# main.net
KiCad netlist of a schematic drawn in EAGLE
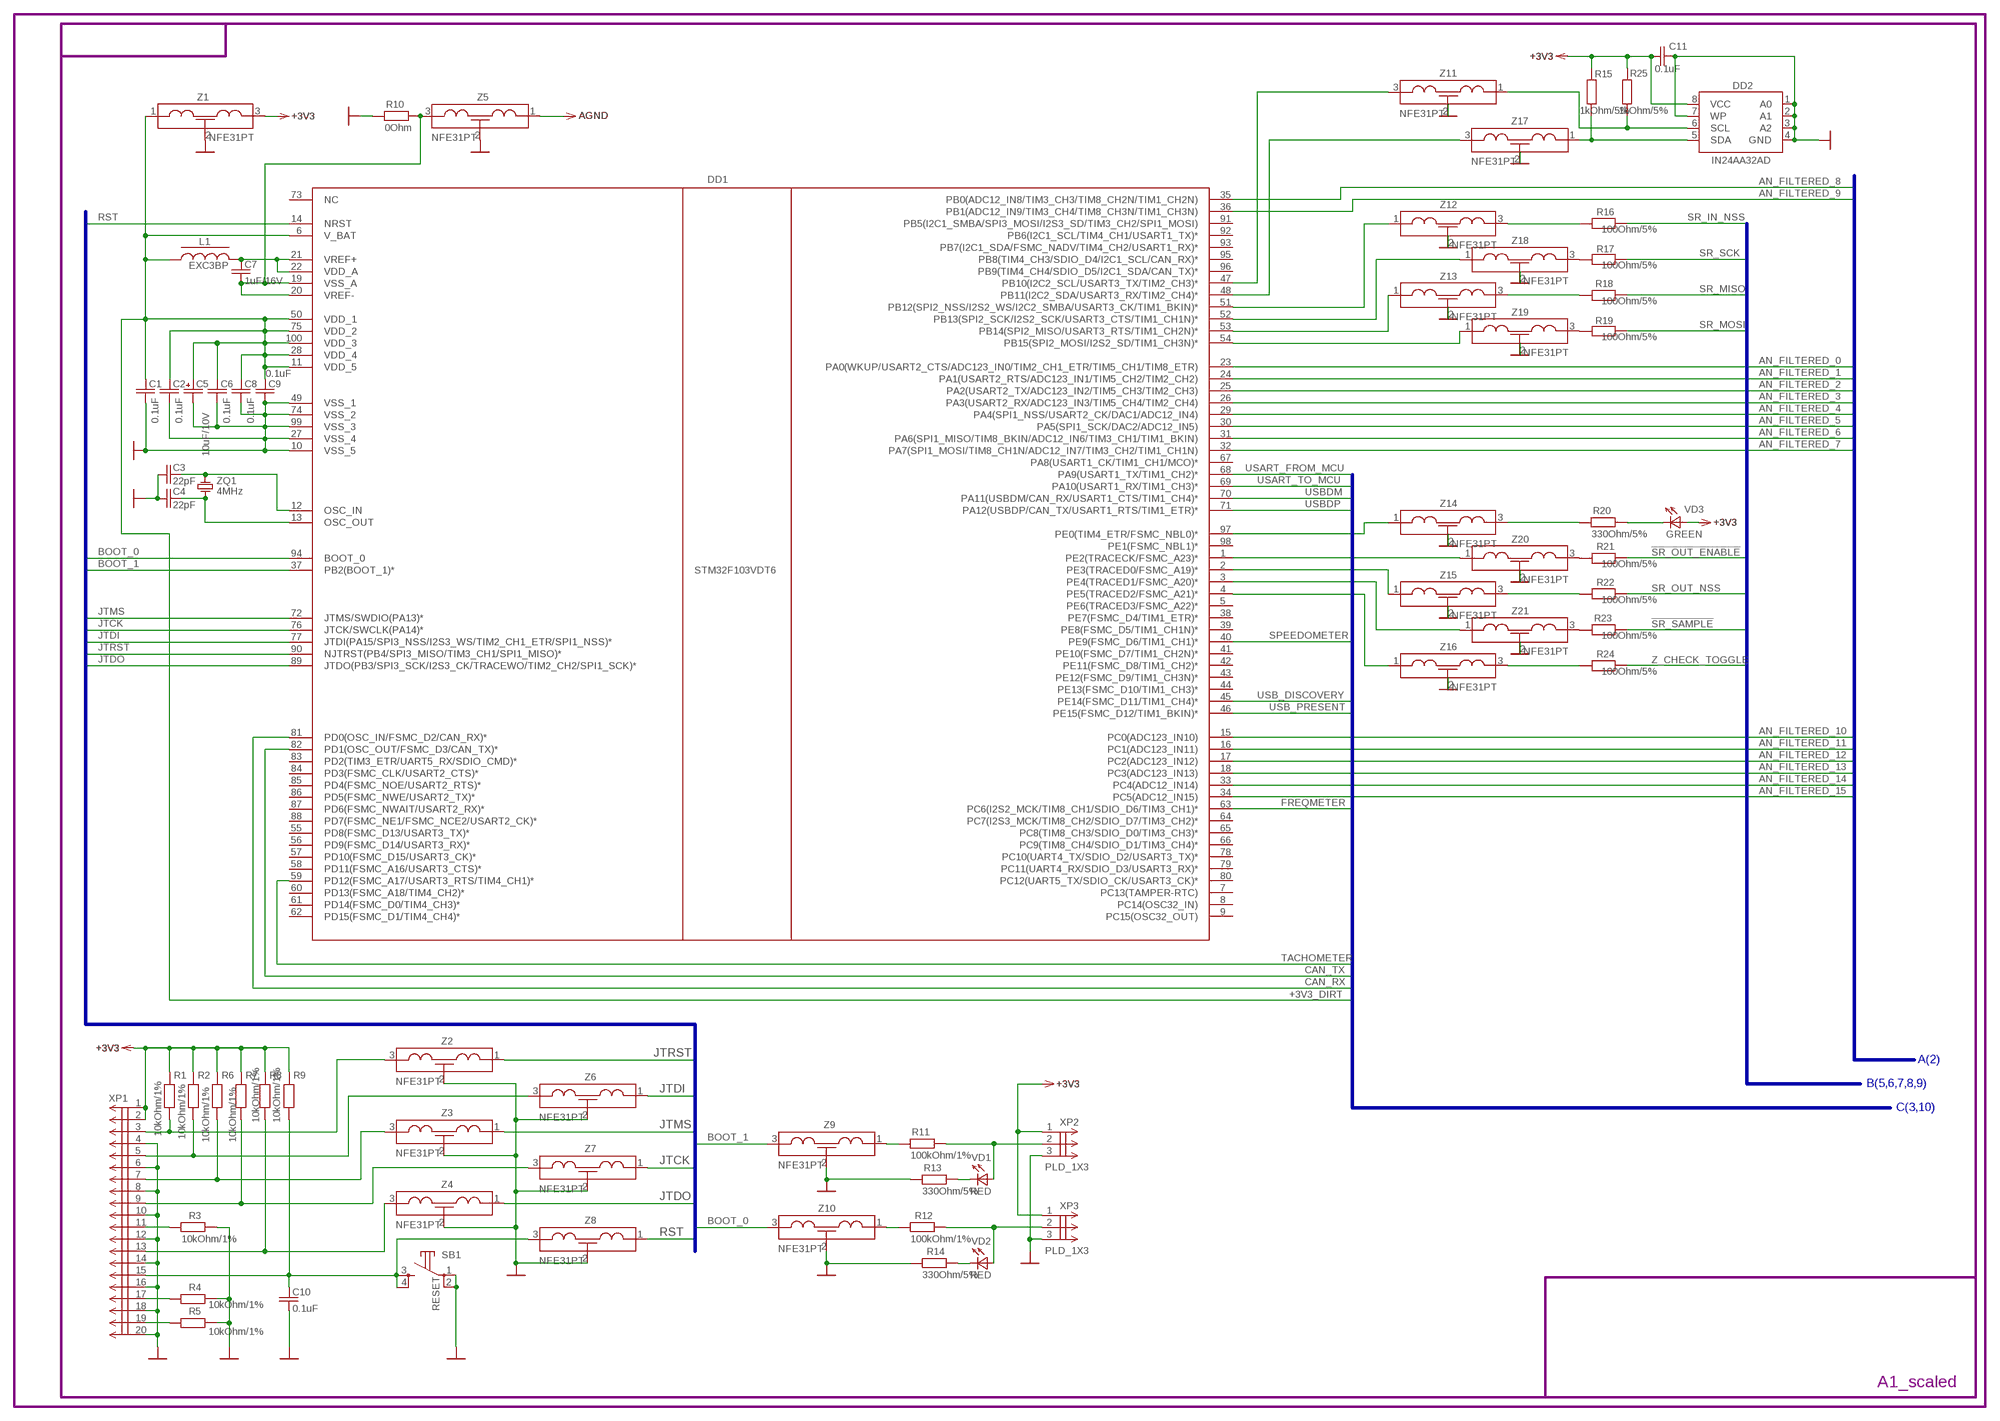
[diagram p0: schematic, sheet 1]
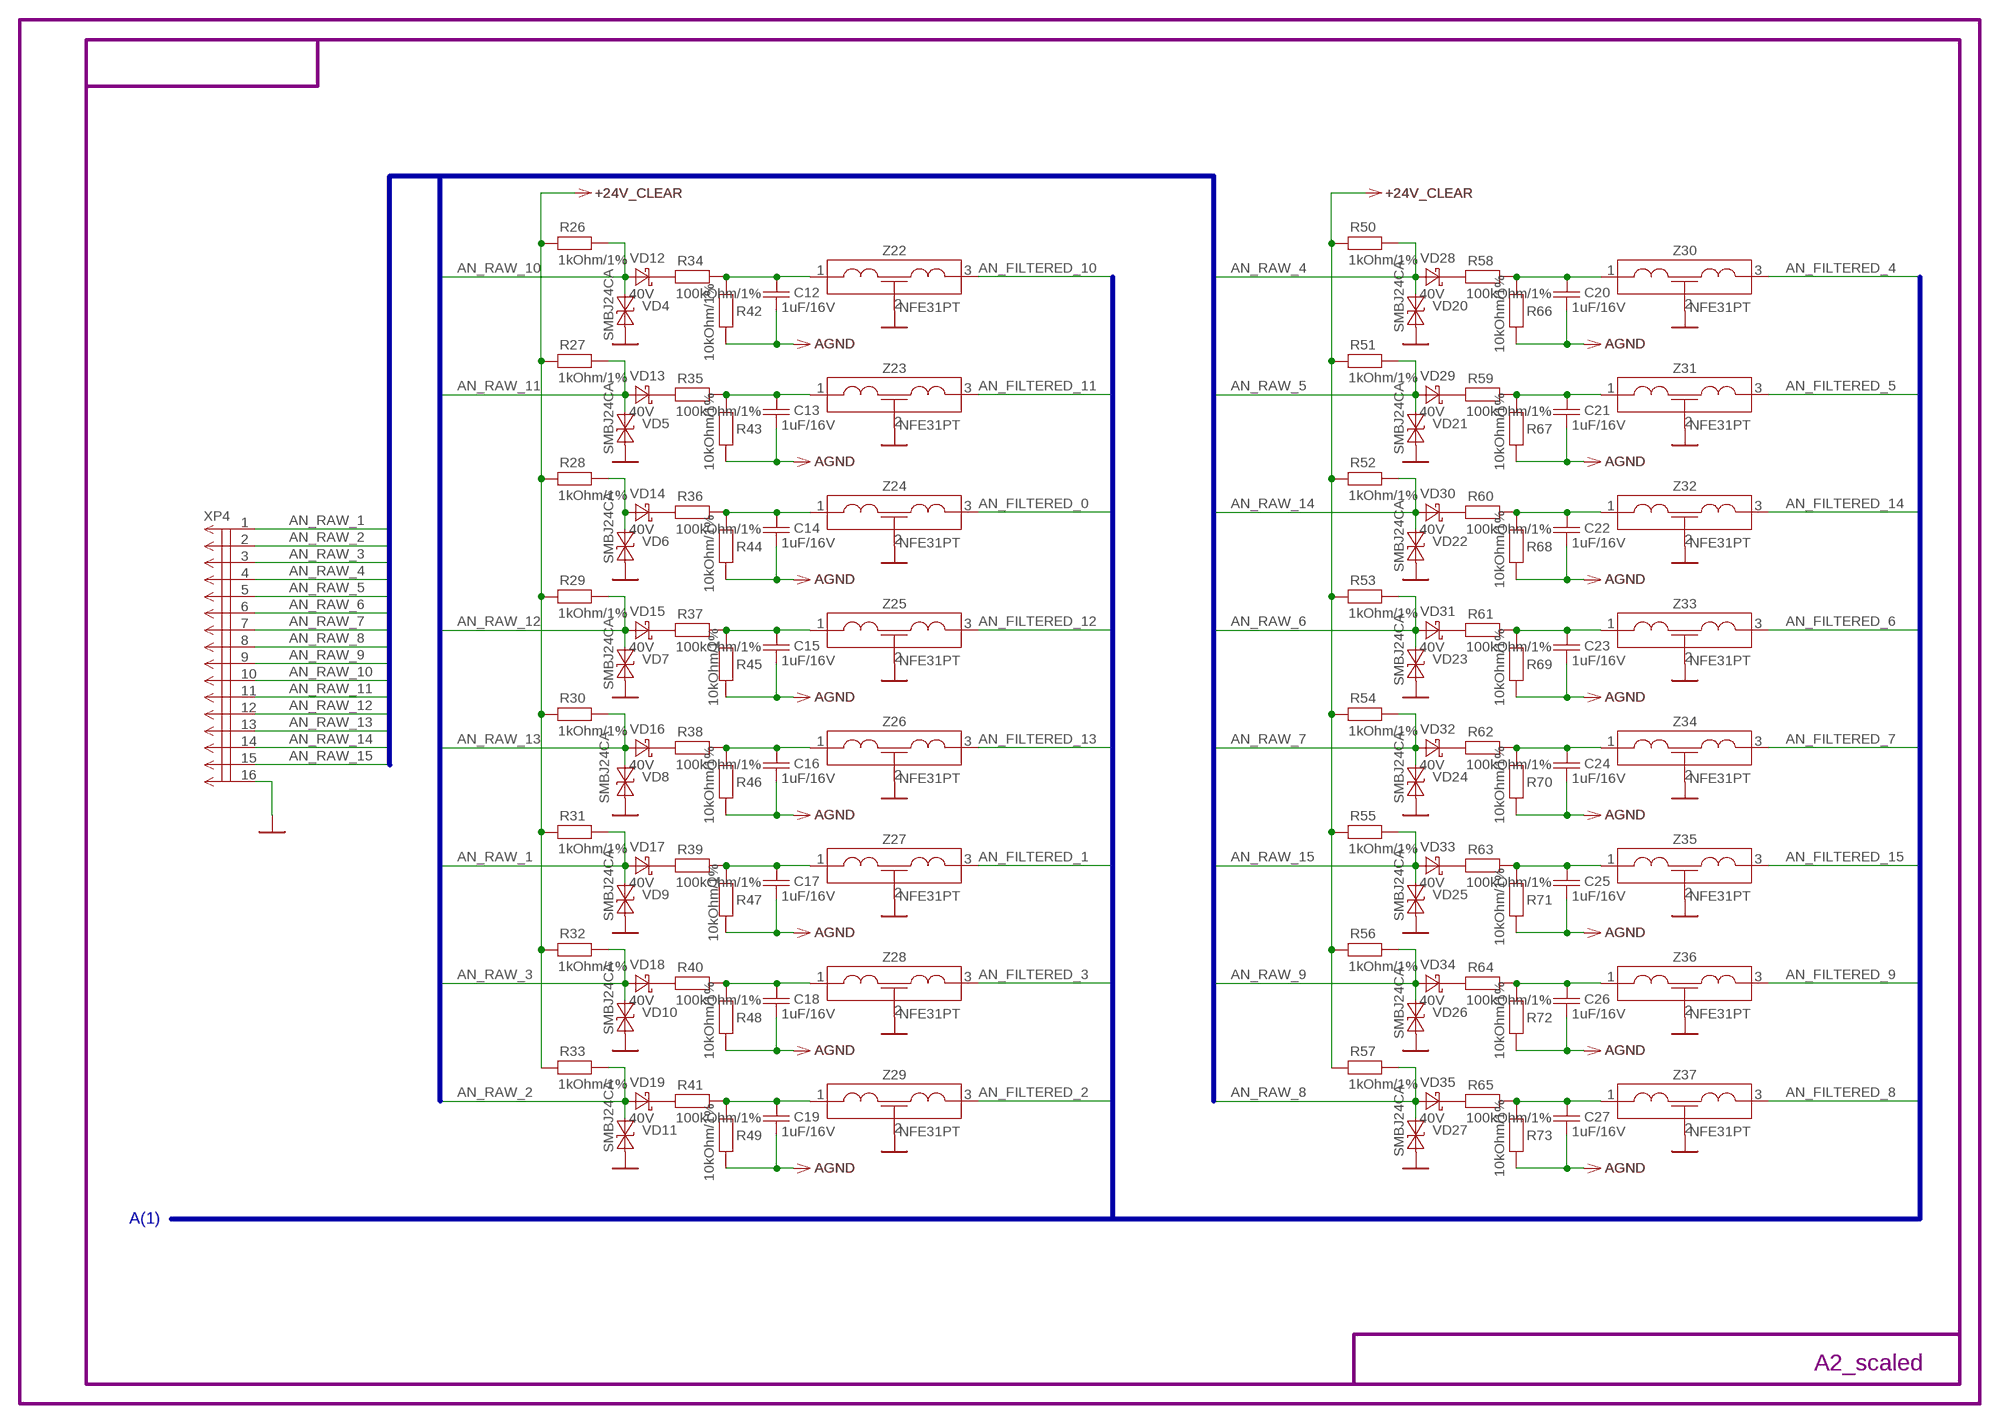
[diagram p1: schematic, sheet 2]
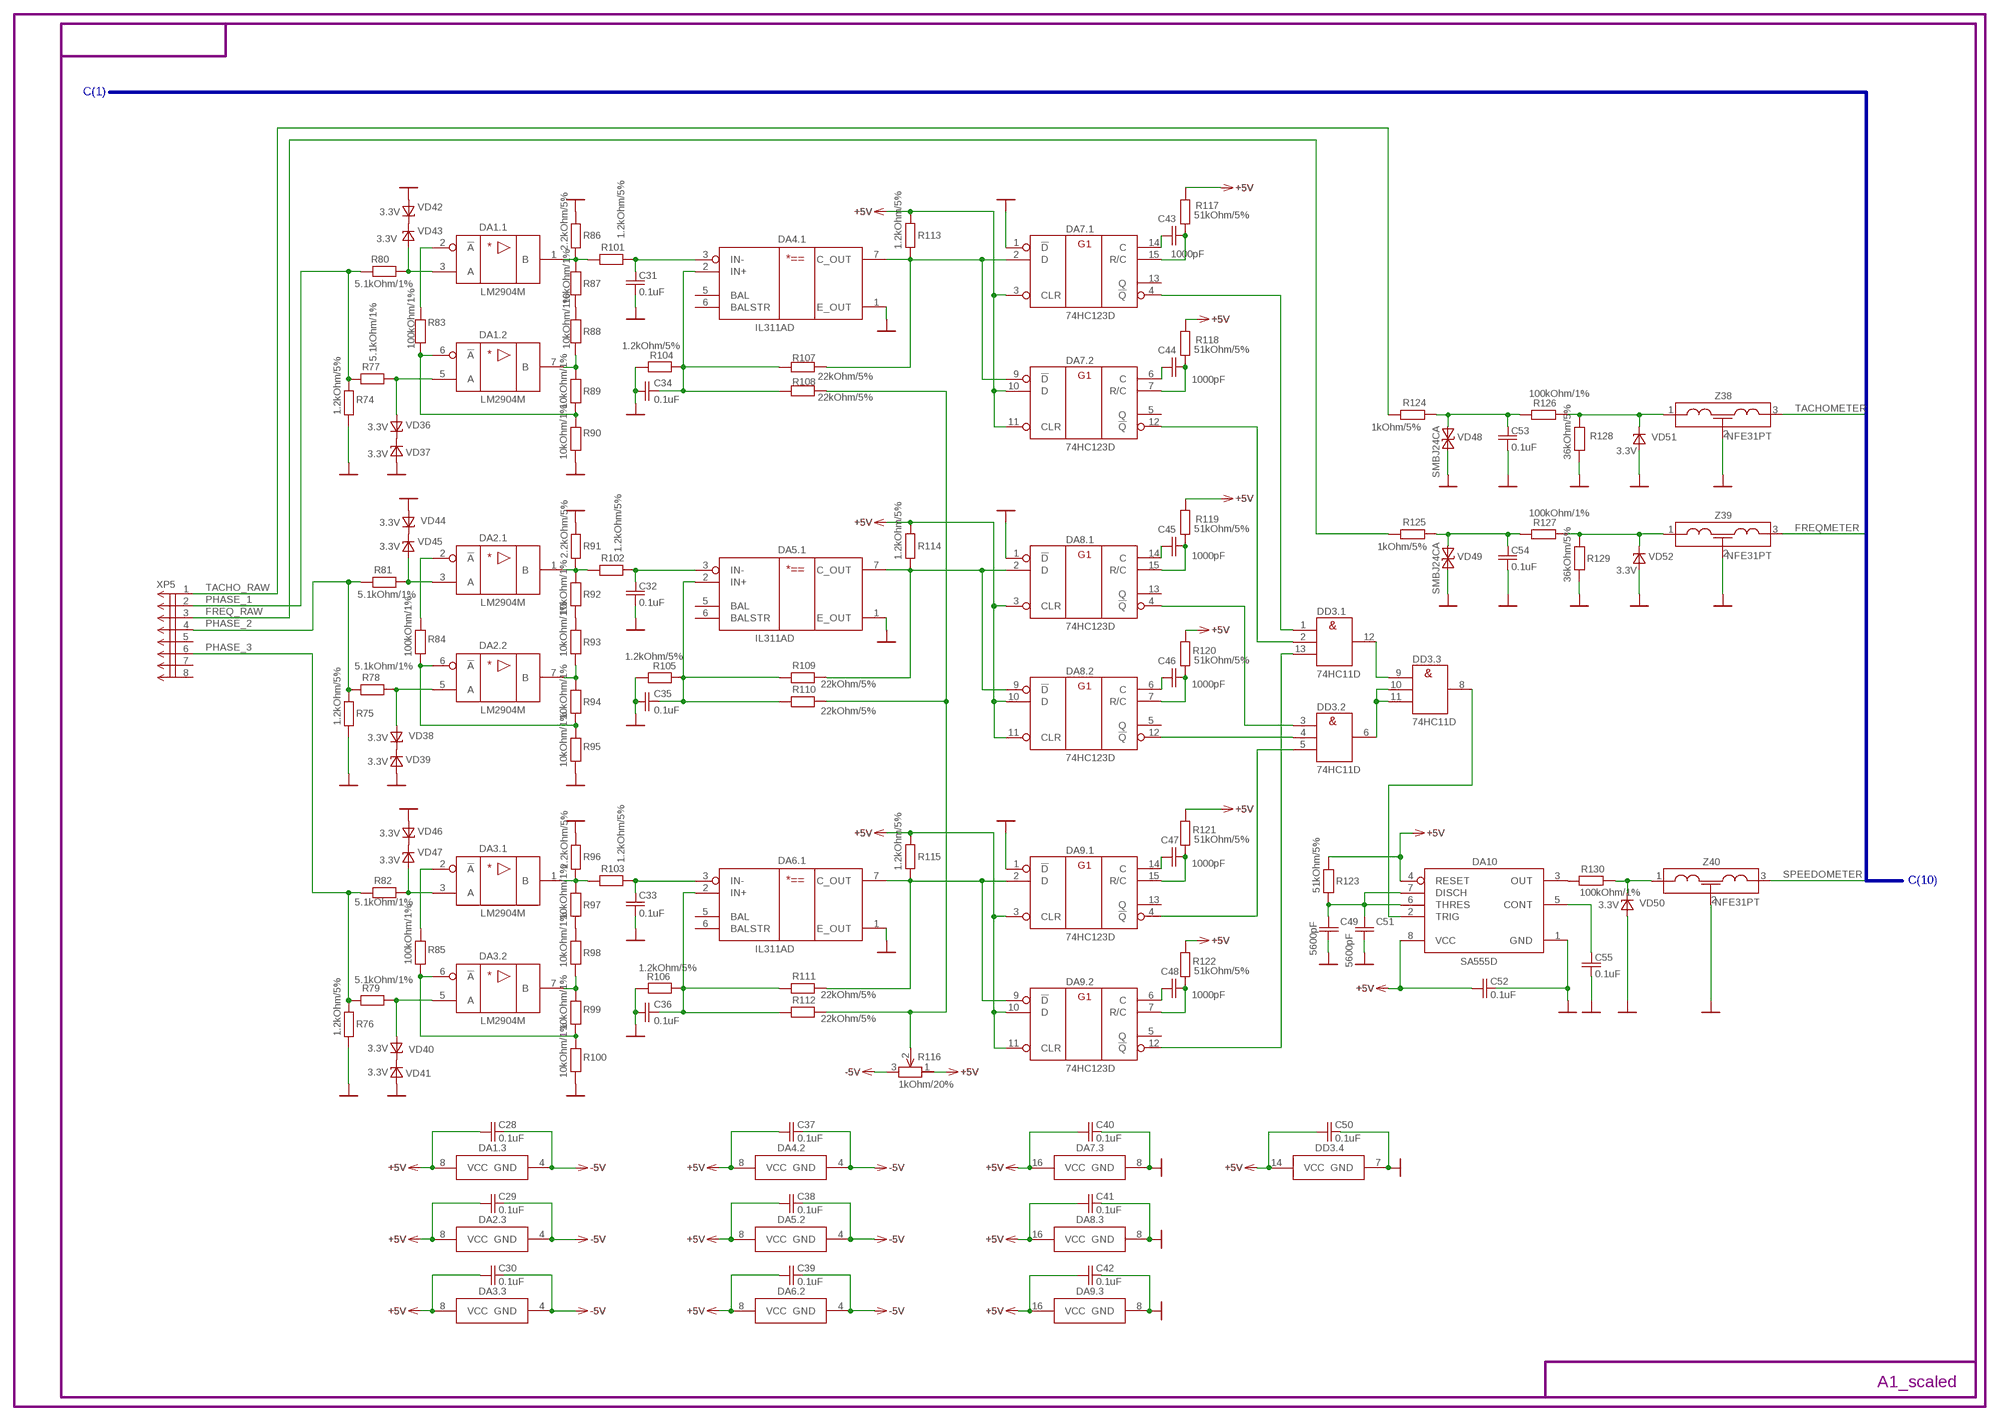
[diagram p2: schematic, sheet 3]
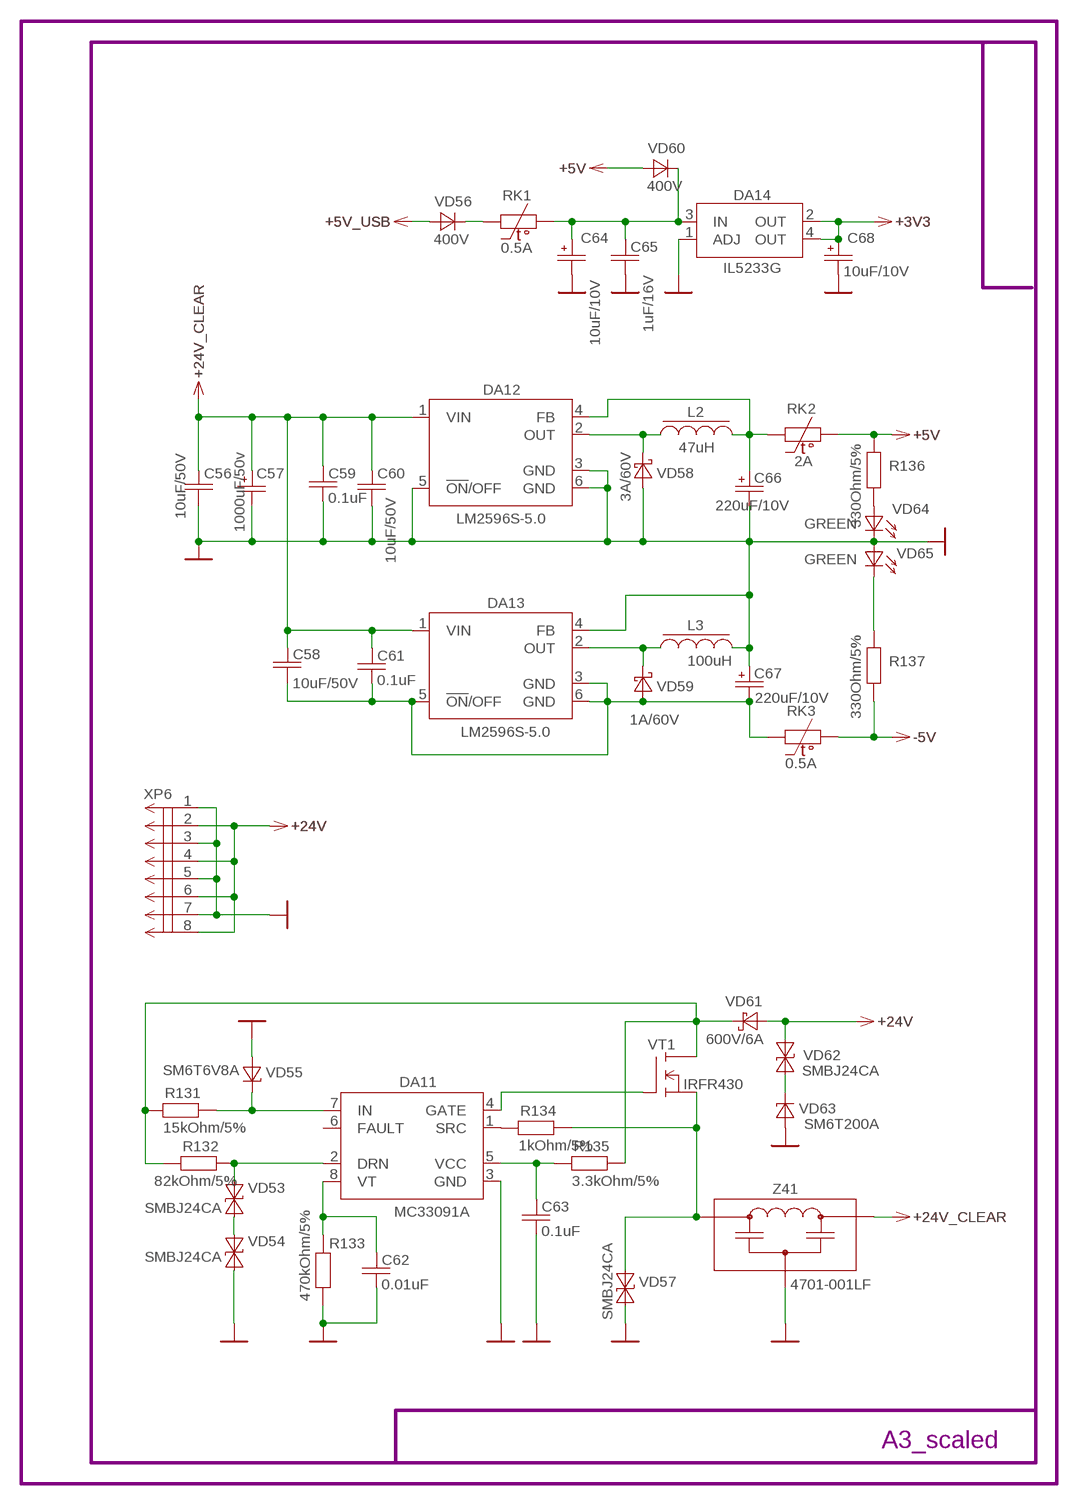
[diagram p3: schematic, sheet 4]
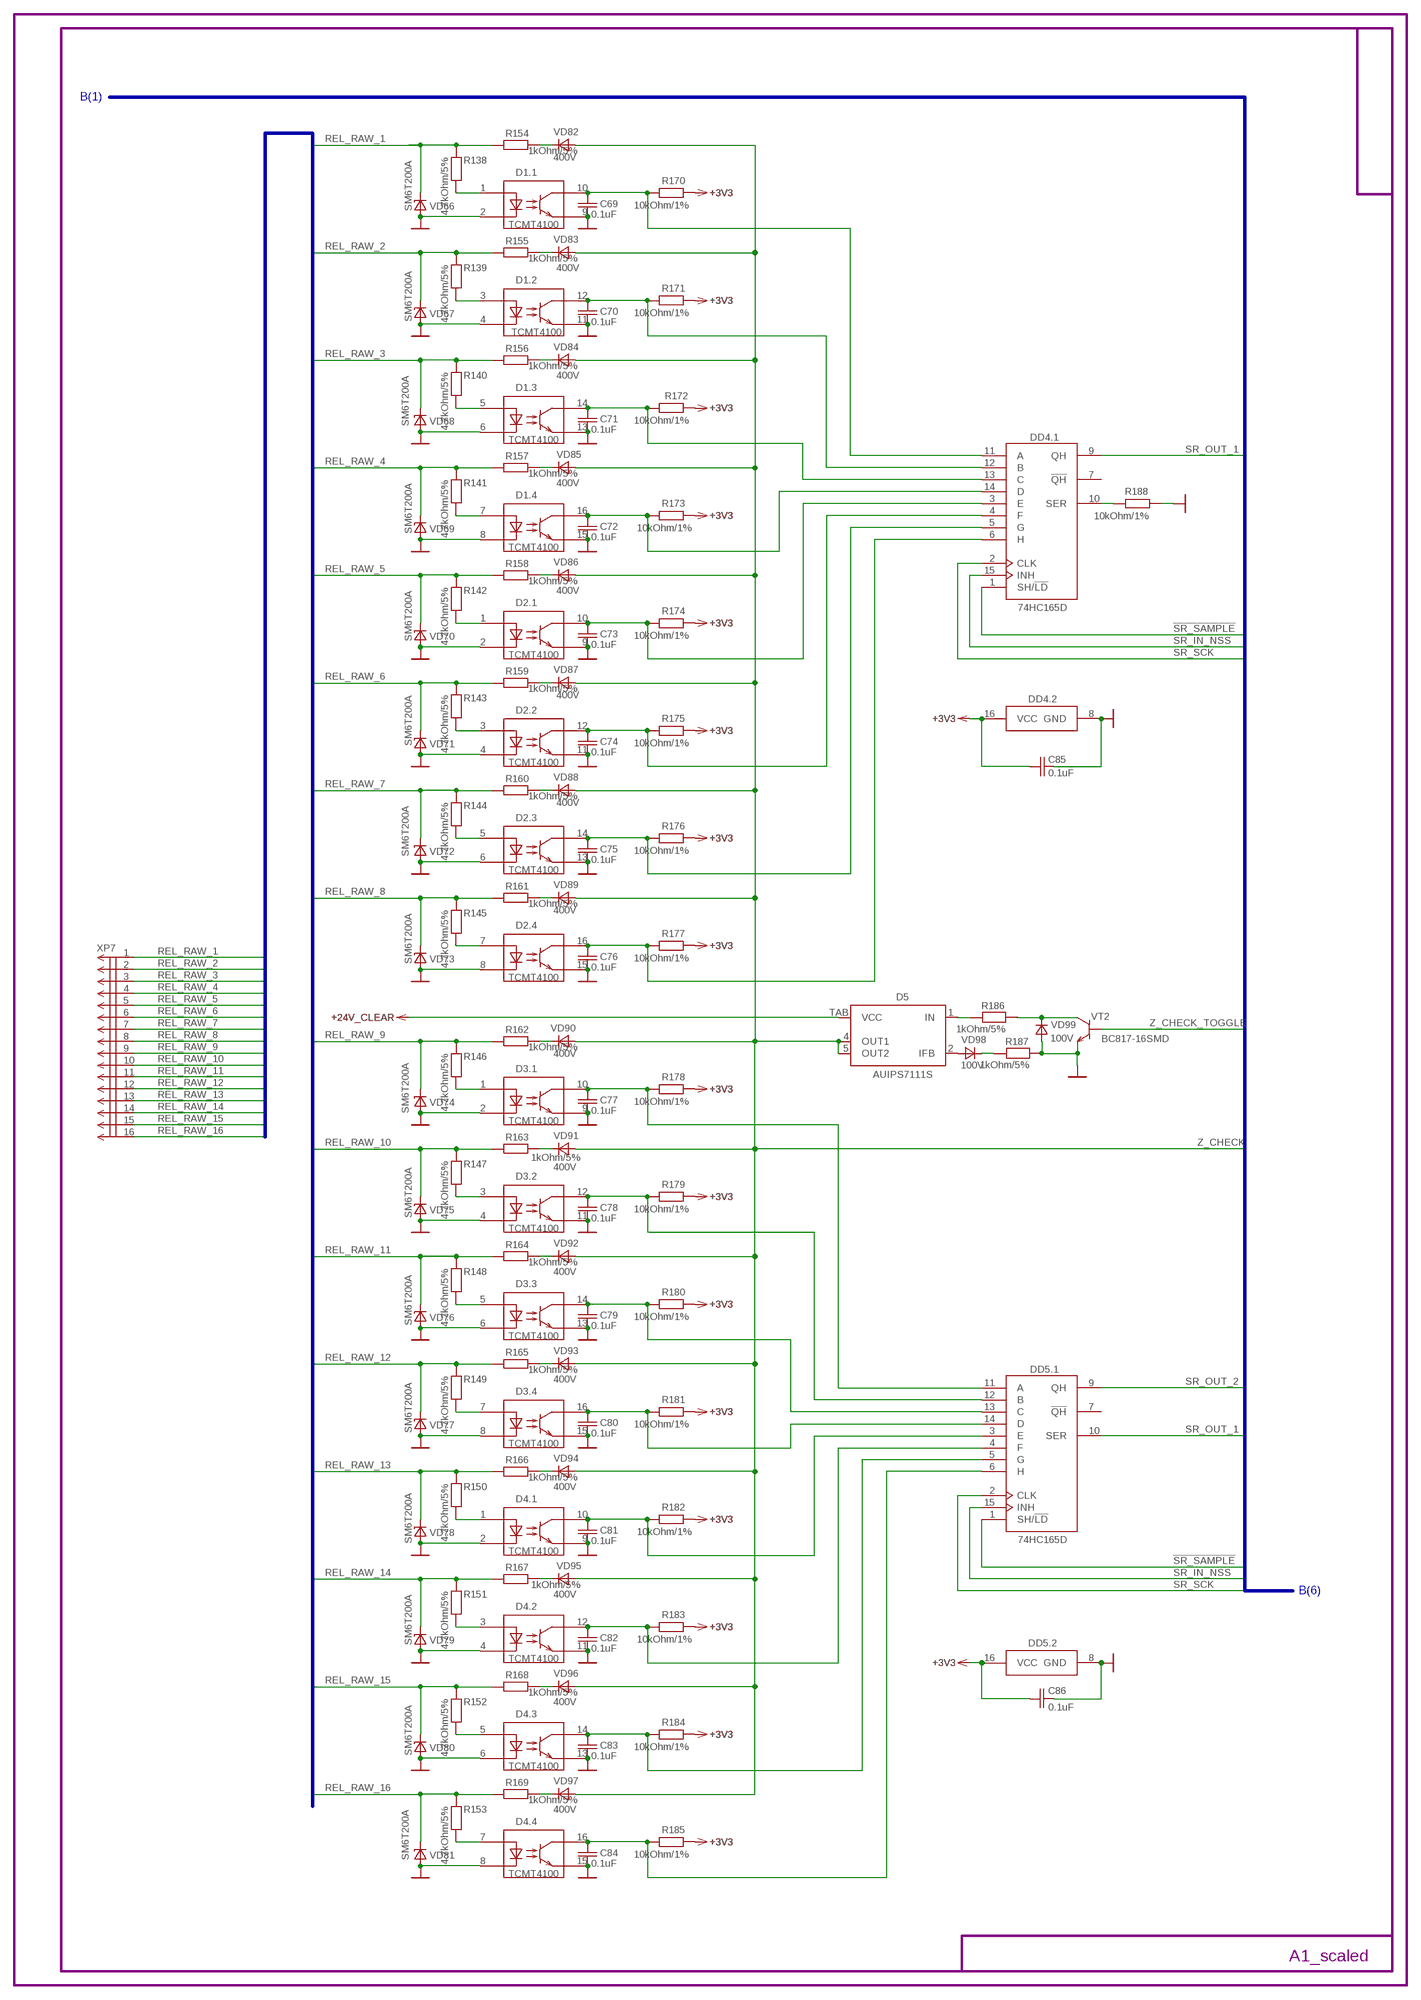
[diagram p4: schematic, sheet 5]
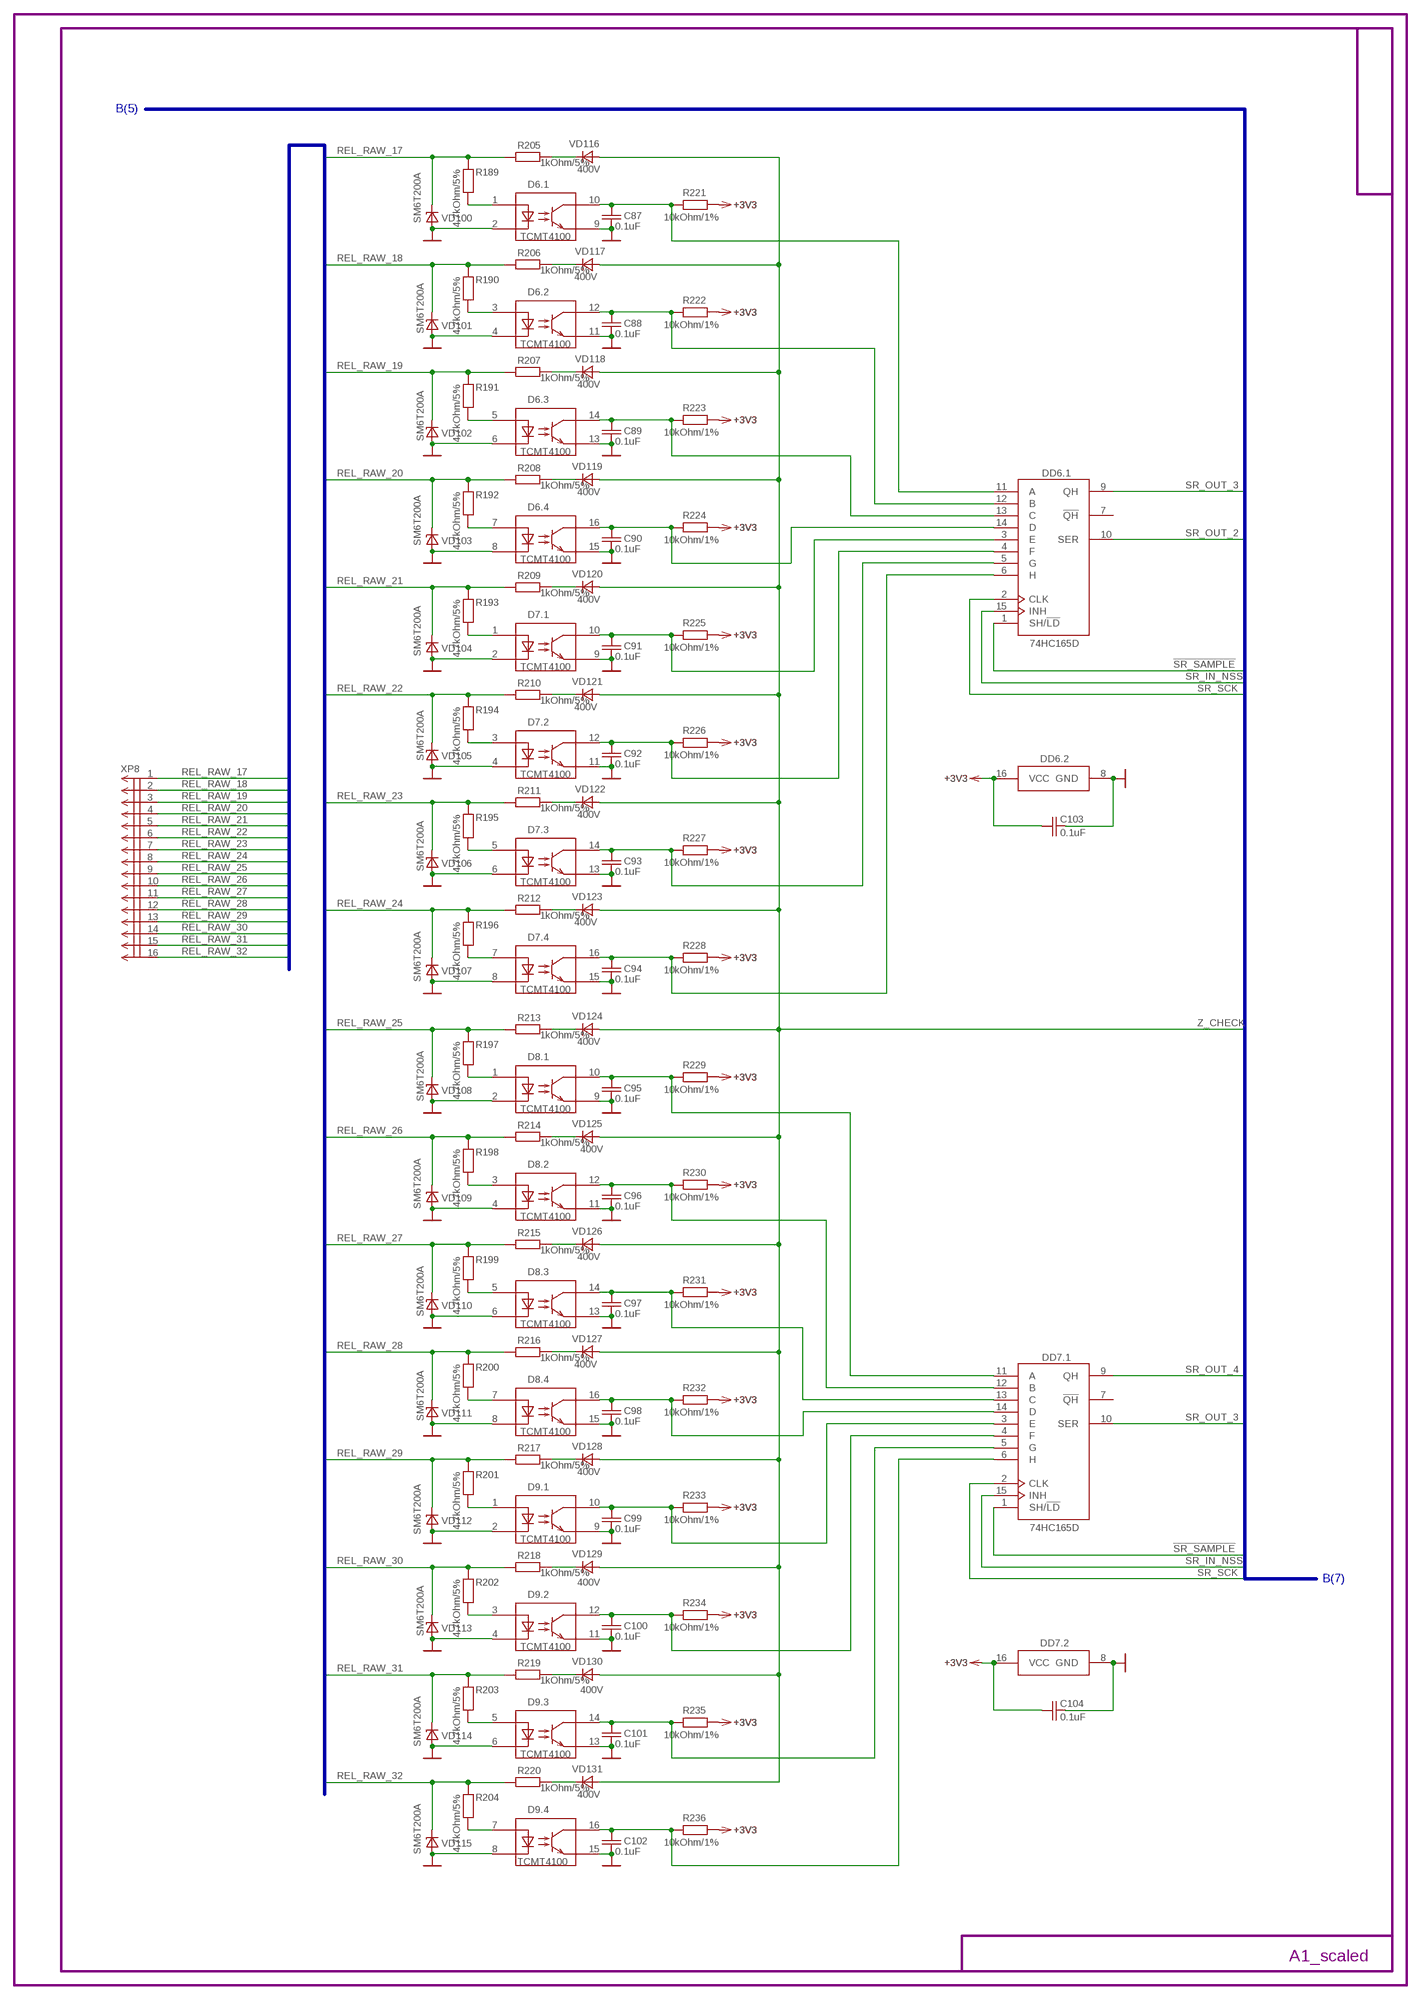
[diagram p5: schematic, sheet 6]
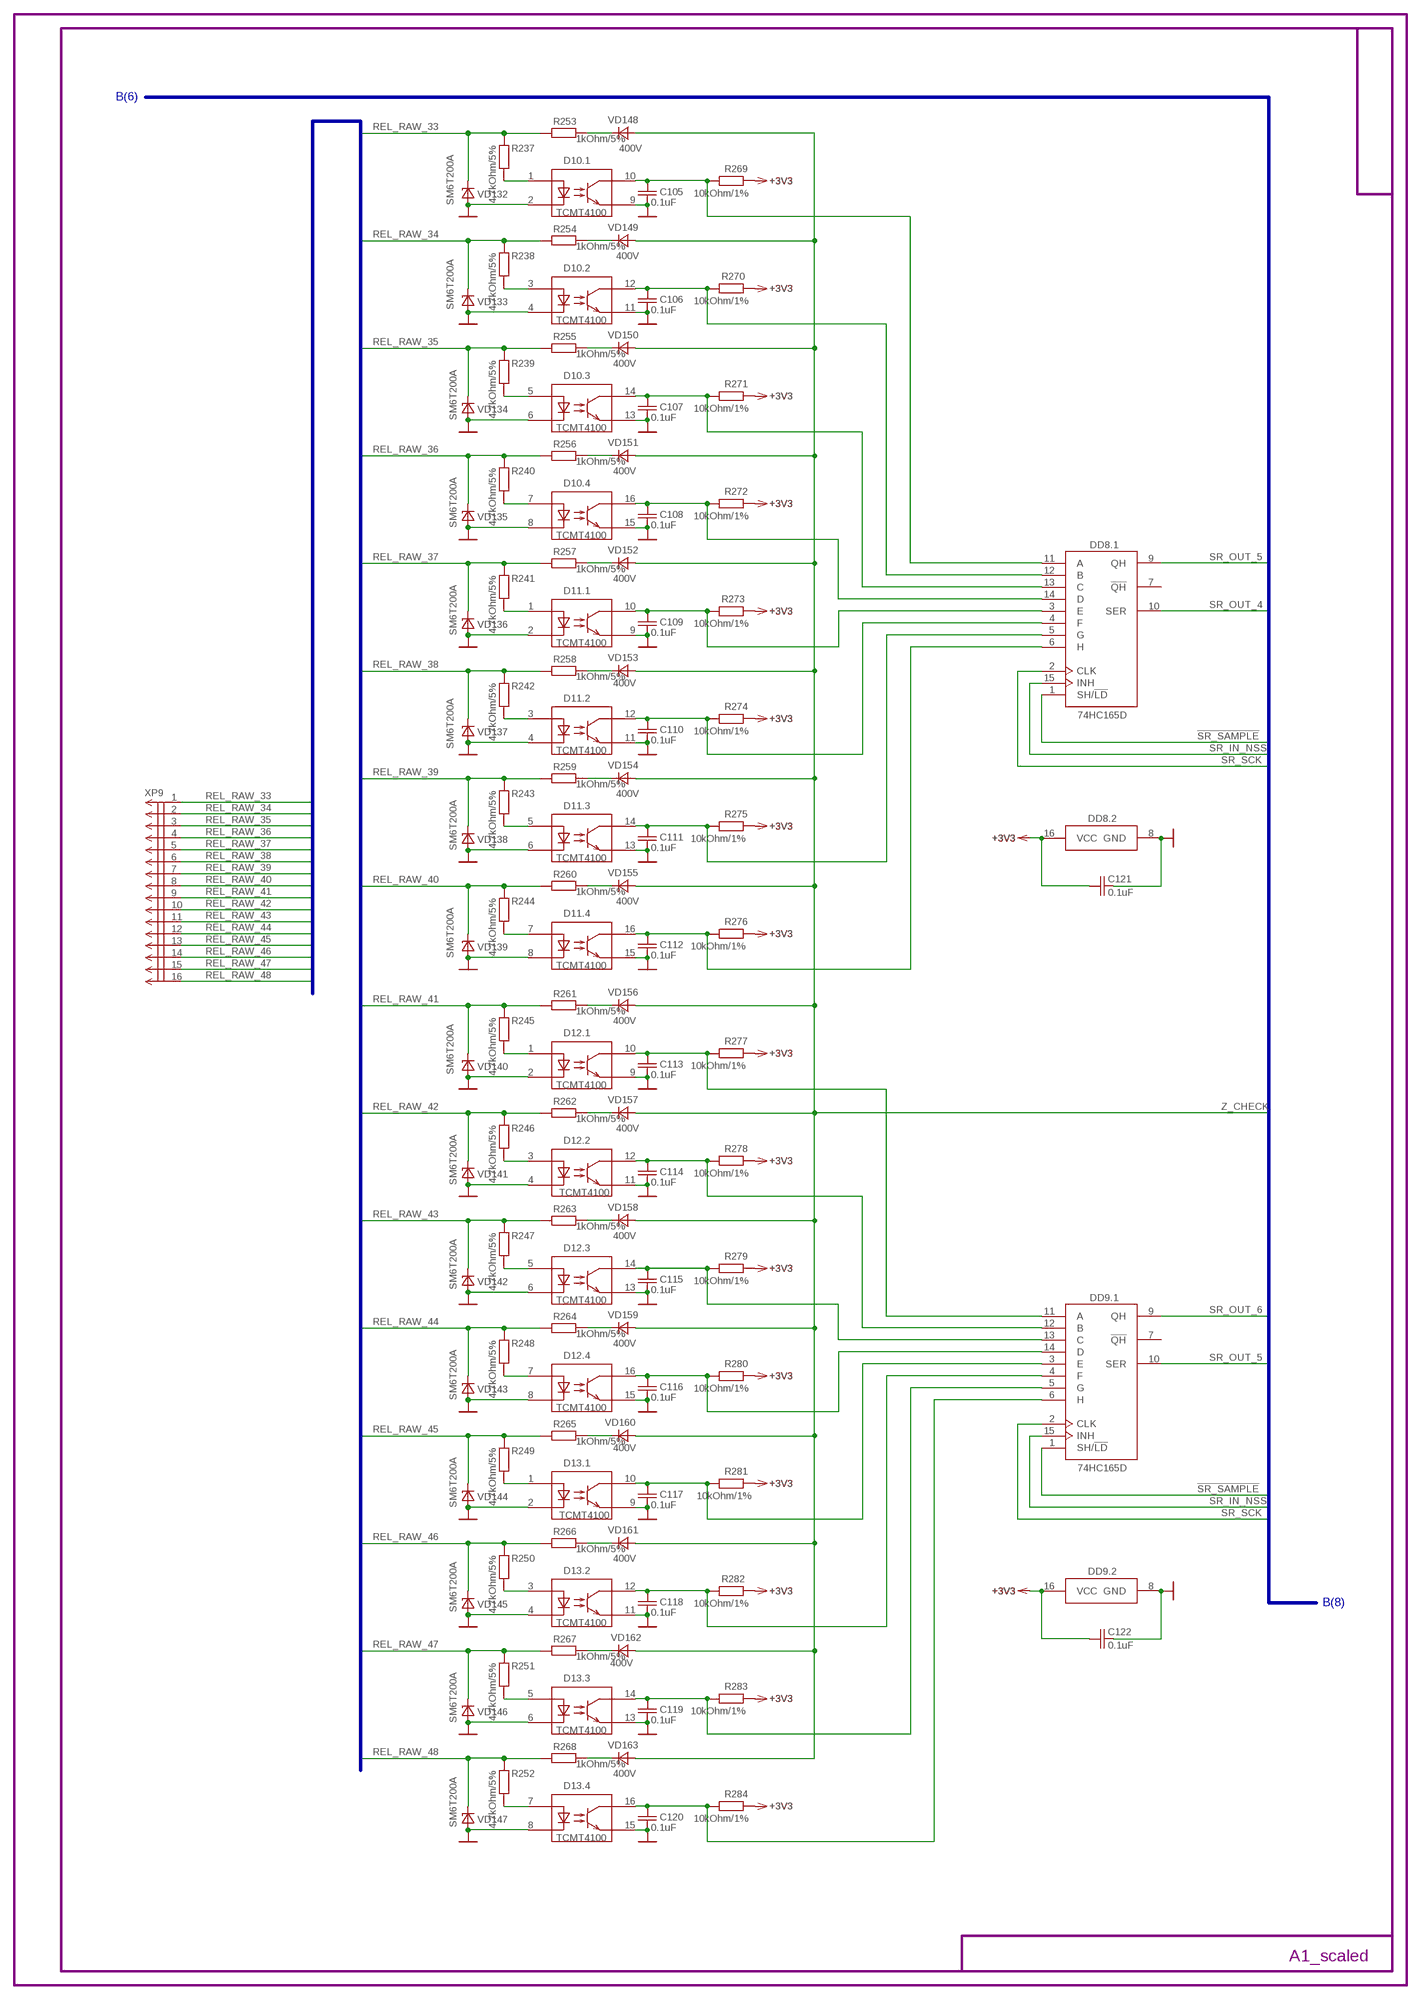
[diagram p6: schematic, sheet 7]
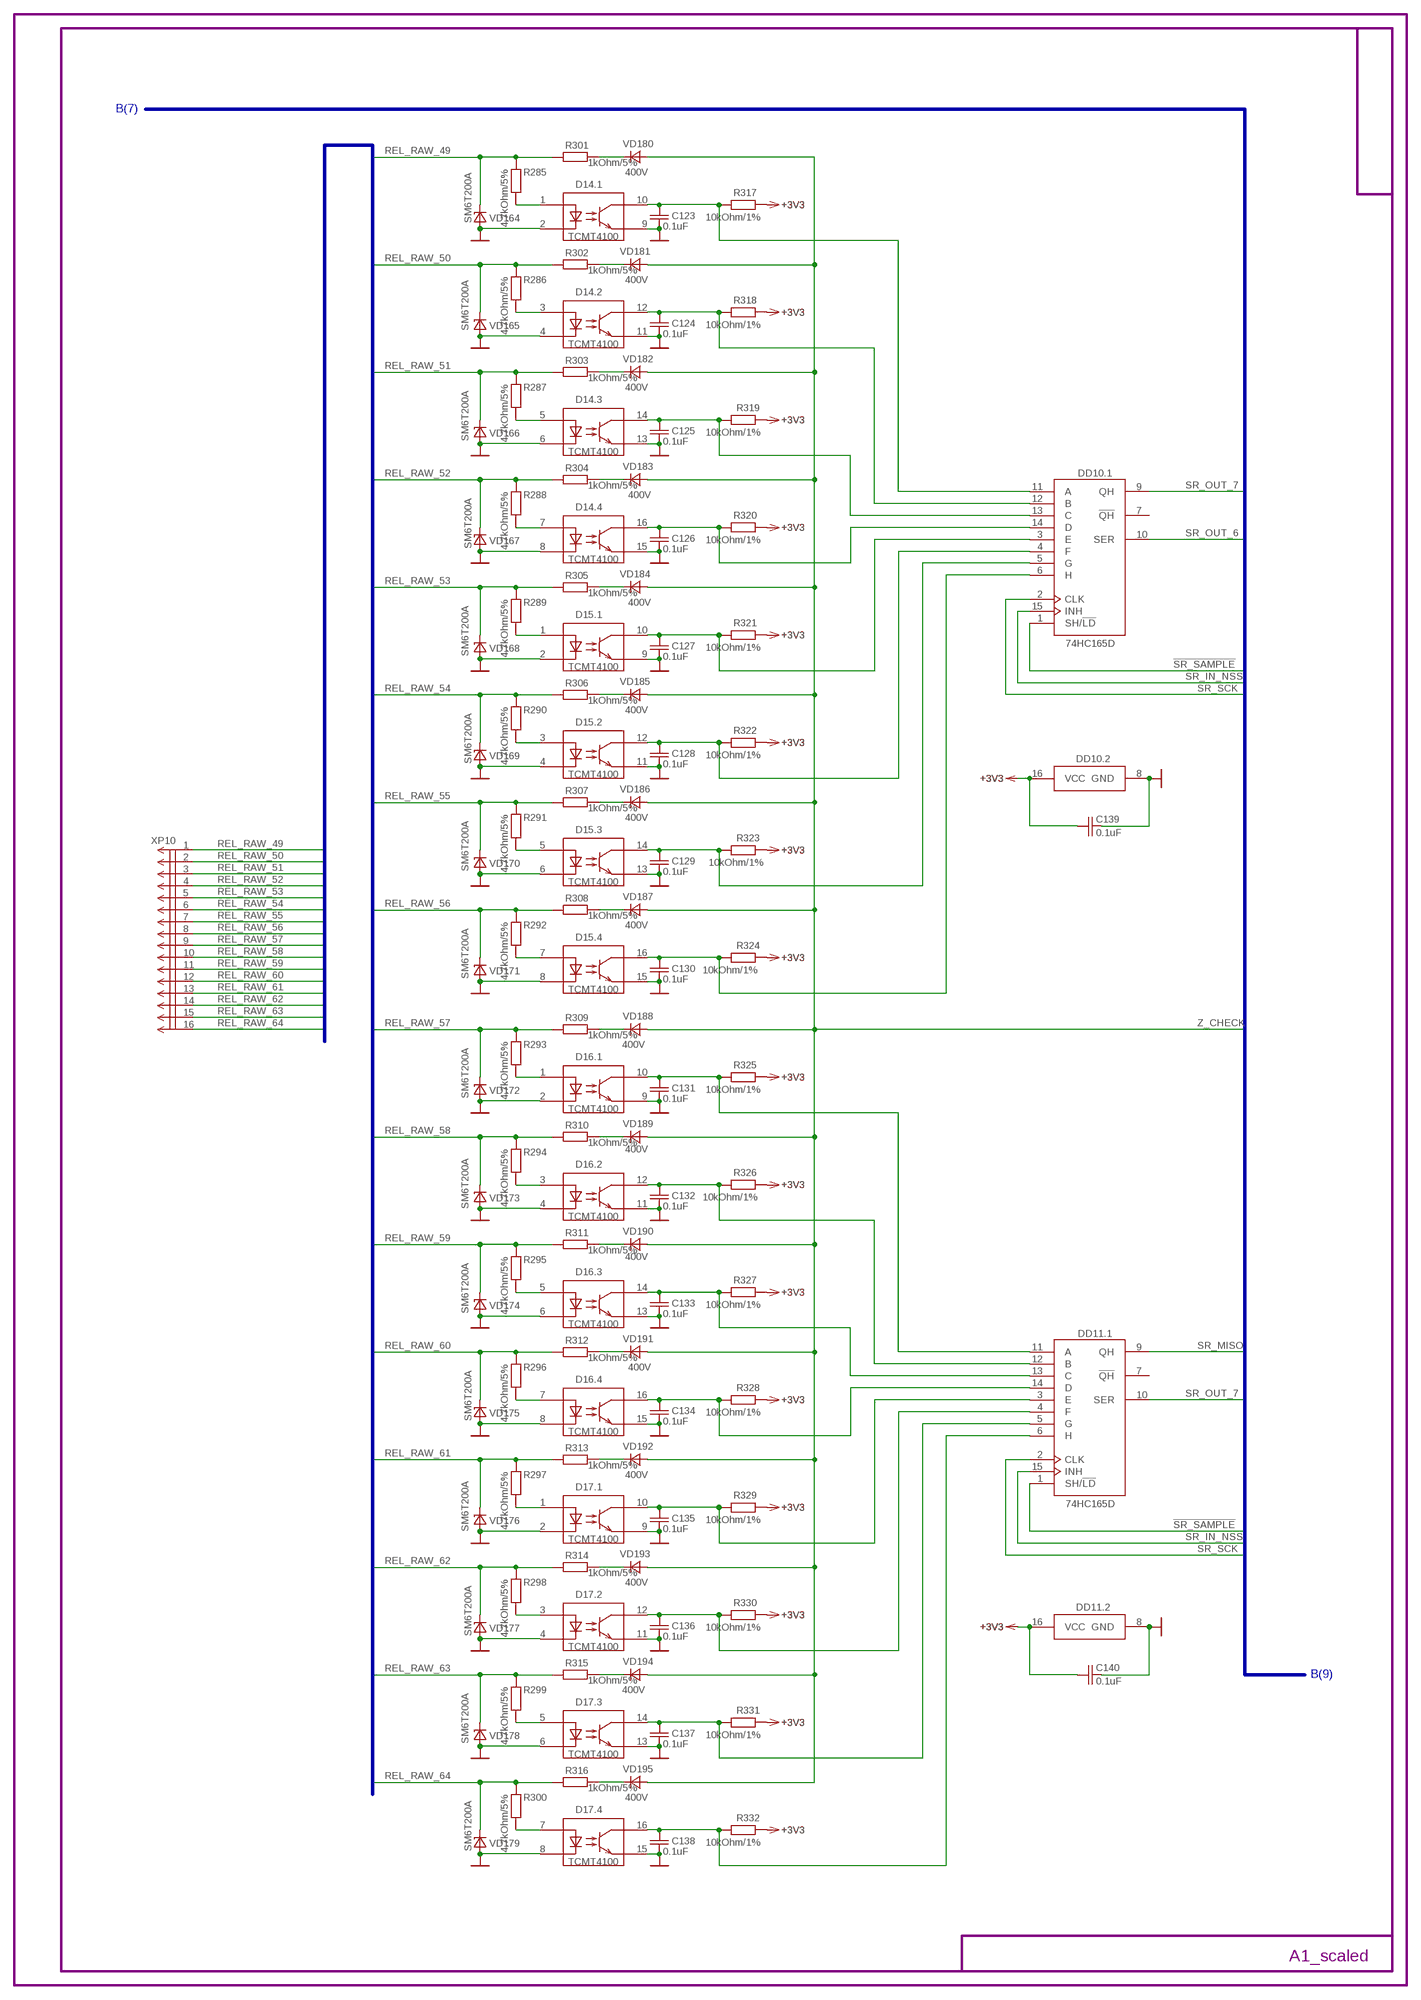
[diagram p7: schematic, sheet 8]
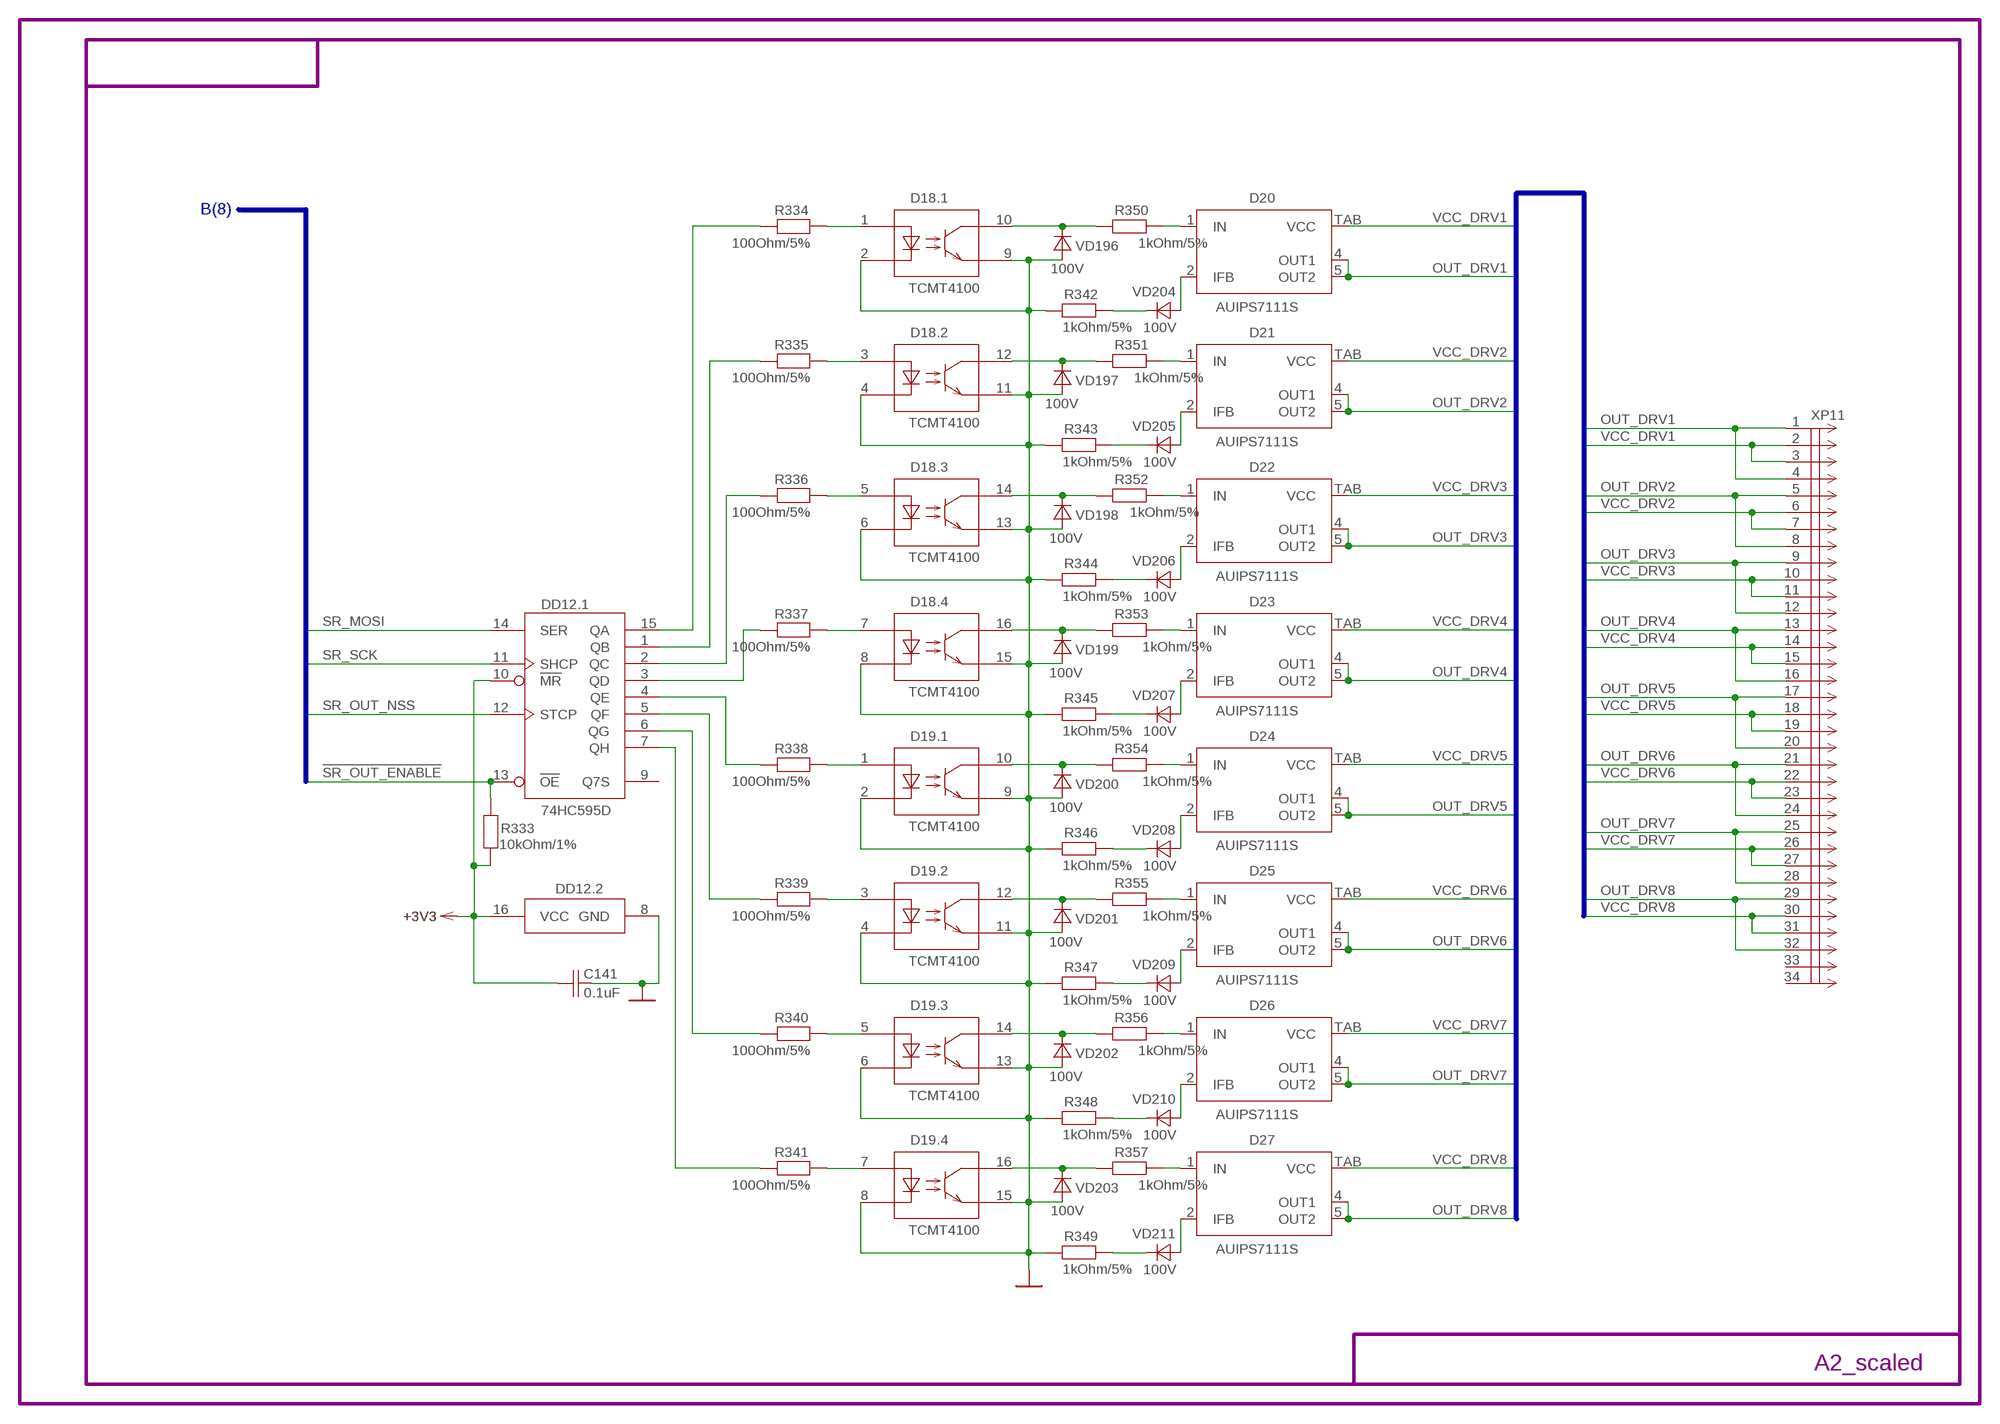
[diagram p8: schematic, sheet 9]
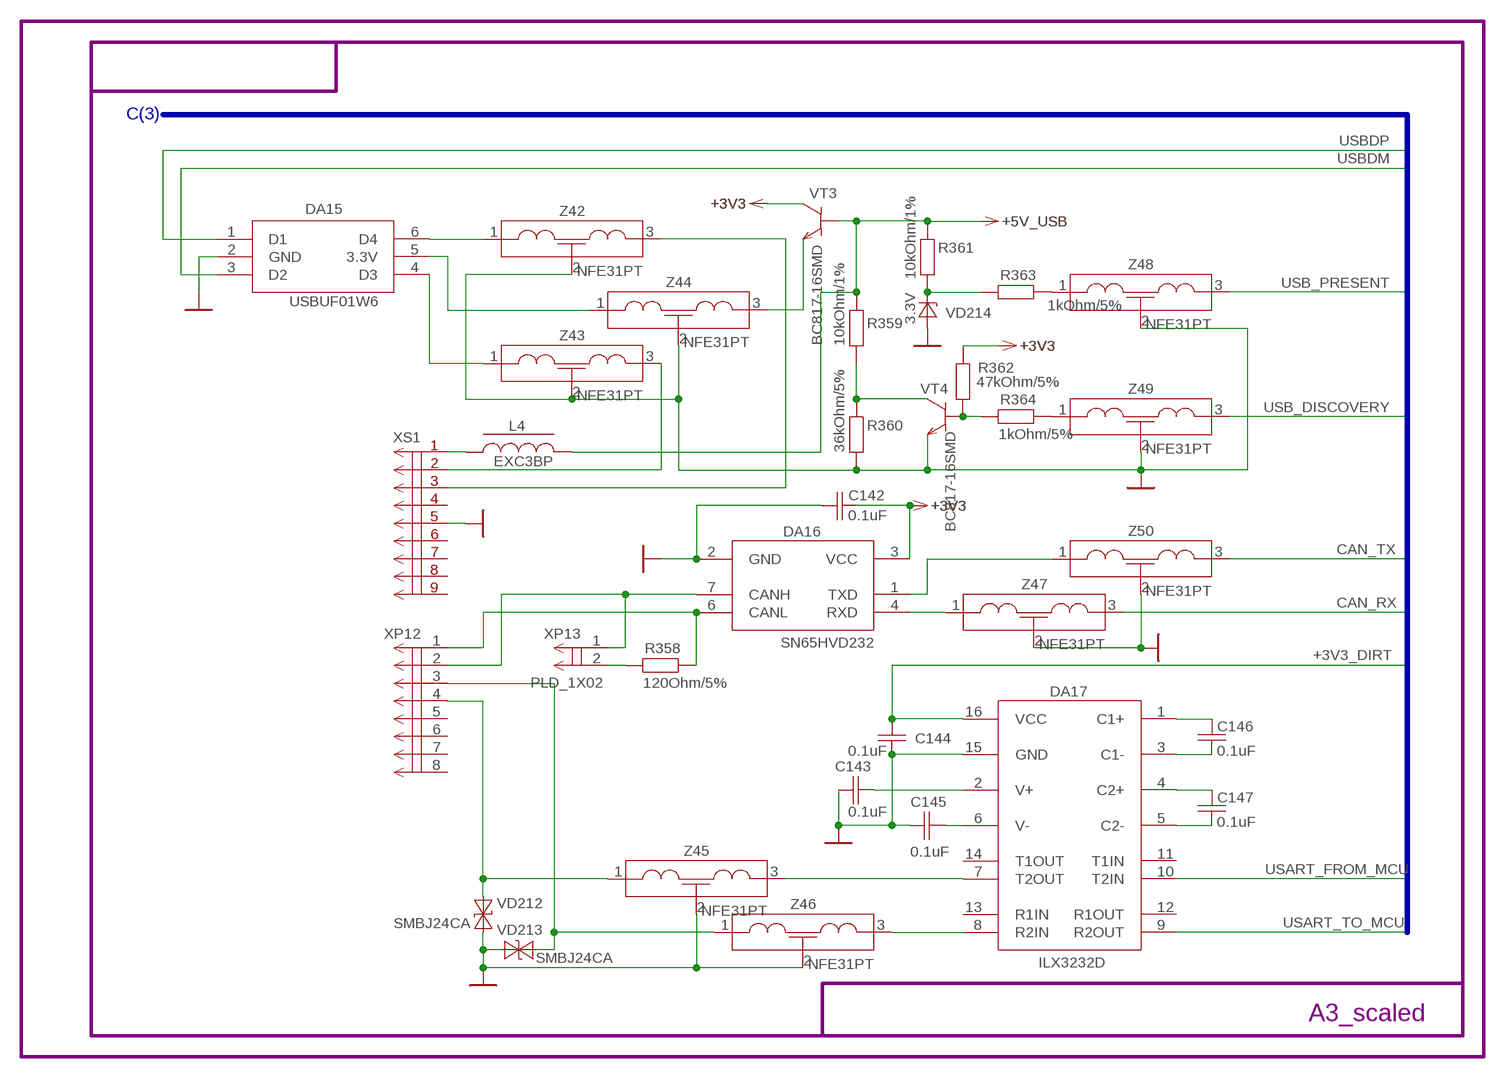
[diagram p9: schematic, sheet 10]
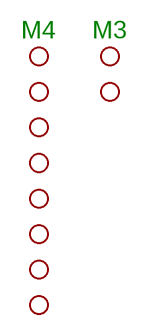
[diagram p10: schematic, sheet 11]

(export (version "E")
  (design (tool "Eeschema 10.0.6"))
  (components
    (comp (ref "C12")
      (value "1uF/16V")
      (footprint "eagle-import:C0603")
      (fields (field (name "PARTNO") "C0603C105K4PACTU"))
      (libsource (lib "eagle-import") (part "C-EUC0603"))
    )
    (comp (ref "C13")
      (value "1uF/16V")
      (footprint "eagle-import:C0603")
      (fields (field (name "PARTNO") "C0603C105K4PACTU"))
      (libsource (lib "eagle-import") (part "C-EUC0603"))
    )
    (comp (ref "C14")
      (value "1uF/16V")
      (footprint "eagle-import:C0603")
      (fields (field (name "PARTNO") "C0603C105K4PACTU"))
      (libsource (lib "eagle-import") (part "C-EUC0603"))
    )
    (comp (ref "C15")
      (value "1uF/16V")
      (footprint "eagle-import:C0603")
      (fields (field (name "PARTNO") "C0603C105K4PACTU"))
      (libsource (lib "eagle-import") (part "C-EUC0603"))
    )
    (comp (ref "C16")
      (value "1uF/16V")
      (footprint "eagle-import:C0603")
      (fields (field (name "PARTNO") "C0603C105K4PACTU"))
      (libsource (lib "eagle-import") (part "C-EUC0603"))
    )
    (comp (ref "C17")
      (value "1uF/16V")
      (footprint "eagle-import:C0603")
      (fields (field (name "PARTNO") "C0603C105K4PACTU"))
      (libsource (lib "eagle-import") (part "C-EUC0603"))
    )
    (comp (ref "C18")
      (value "1uF/16V")
      (footprint "eagle-import:C0603")
      (fields (field (name "PARTNO") "C0603C105K4PACTU"))
      (libsource (lib "eagle-import") (part "C-EUC0603"))
    )
    (comp (ref "C19")
      (value "1uF/16V")
      (footprint "eagle-import:C0603")
      (fields (field (name "PARTNO") "C0603C105K4PACTU"))
      (libsource (lib "eagle-import") (part "C-EUC0603"))
    )
    (comp (ref "C20")
      (value "1uF/16V")
      (footprint "eagle-import:C0603")
      (fields (field (name "PARTNO") "C0603C105K4PACTU"))
      (libsource (lib "eagle-import") (part "C-EUC0603"))
    )
    (comp (ref "C21")
      (value "1uF/16V")
      (footprint "eagle-import:C0603")
      (fields (field (name "PARTNO") "C0603C105K4PACTU"))
      (libsource (lib "eagle-import") (part "C-EUC0603"))
    )
    (comp (ref "C22")
      (value "1uF/16V")
      (footprint "eagle-import:C0603")
      (fields (field (name "PARTNO") "C0603C105K4PACTU"))
      (libsource (lib "eagle-import") (part "C-EUC0603"))
    )
    (comp (ref "C23")
      (value "1uF/16V")
      (footprint "eagle-import:C0603")
      (fields (field (name "PARTNO") "C0603C105K4PACTU"))
      (libsource (lib "eagle-import") (part "C-EUC0603"))
    )
    (comp (ref "C24")
      (value "1uF/16V")
      (footprint "eagle-import:C0603")
      (fields (field (name "PARTNO") "C0603C105K4PACTU"))
      (libsource (lib "eagle-import") (part "C-EUC0603"))
    )
    (comp (ref "C25")
      (value "1uF/16V")
      (footprint "eagle-import:C0603")
      (fields (field (name "PARTNO") "C0603C105K4PACTU"))
      (libsource (lib "eagle-import") (part "C-EUC0603"))
    )
    (comp (ref "C26")
      (value "1uF/16V")
      (footprint "eagle-import:C0603")
      (fields (field (name "PARTNO") "C0603C105K4PACTU"))
      (libsource (lib "eagle-import") (part "C-EUC0603"))
    )
    (comp (ref "C27")
      (value "1uF/16V")
      (footprint "eagle-import:C0603")
      (fields (field (name "PARTNO") "C0603C105K4PACTU"))
      (libsource (lib "eagle-import") (part "C-EUC0603"))
    )
    (comp (ref "R26")
      (value "1kOhm/1%")
      (footprint "eagle-import:R2512")
      (fields (field (name "PARTNO") "RC2512FK-071KL"))
      (libsource (lib "eagle-import") (part "R-EU_R2512"))
    )
    (comp (ref "R27")
      (value "1kOhm/1%")
      (footprint "eagle-import:R2512")
      (fields (field (name "PARTNO") "RC2512FK-071KL"))
      (libsource (lib "eagle-import") (part "R-EU_R2512"))
    )
    (comp (ref "R28")
      (value "1kOhm/1%")
      (footprint "eagle-import:R2512")
      (fields (field (name "PARTNO") "RC2512FK-071KL"))
      (libsource (lib "eagle-import") (part "R-EU_R2512"))
    )
    (comp (ref "R29")
      (value "1kOhm/1%")
      (footprint "eagle-import:R2512")
      (fields (field (name "PARTNO") "RC2512FK-071KL"))
      (libsource (lib "eagle-import") (part "R-EU_R2512"))
    )
    (comp (ref "R30")
      (value "1kOhm/1%")
      (footprint "eagle-import:R2512")
      (fields (field (name "PARTNO") "RC2512FK-071KL"))
      (libsource (lib "eagle-import") (part "R-EU_R2512"))
    )
    (comp (ref "R31")
      (value "1kOhm/1%")
      (footprint "eagle-import:R2512")
      (fields (field (name "PARTNO") "RC2512FK-071KL"))
      (libsource (lib "eagle-import") (part "R-EU_R2512"))
    )
    (comp (ref "R32")
      (value "1kOhm/1%")
      (footprint "eagle-import:R2512")
      (fields (field (name "PARTNO") "RC2512FK-071KL"))
      (libsource (lib "eagle-import") (part "R-EU_R2512"))
    )
    (comp (ref "R33")
      (value "1kOhm/1%")
      (footprint "eagle-import:R2512")
      (fields (field (name "PARTNO") "RC2512FK-071KL"))
      (libsource (lib "eagle-import") (part "R-EU_R2512"))
    )
    (comp (ref "R34")
      (value "100kOhm/1%")
      (footprint "eagle-import:R0603")
      (fields (field (name "PARTNO") "RC0603FR-13100KL"))
      (libsource (lib "eagle-import") (part "R-EU_R0603"))
    )
    (comp (ref "R35")
      (value "100kOhm/1%")
      (footprint "eagle-import:R0603")
      (fields (field (name "PARTNO") "RC0603FR-13100KL"))
      (libsource (lib "eagle-import") (part "R-EU_R0603"))
    )
    (comp (ref "R36")
      (value "100kOhm/1%")
      (footprint "eagle-import:R0603")
      (fields (field (name "PARTNO") "RC0603FR-13100KL"))
      (libsource (lib "eagle-import") (part "R-EU_R0603"))
    )
    (comp (ref "R37")
      (value "100kOhm/1%")
      (footprint "eagle-import:R0603")
      (fields (field (name "PARTNO") "RC0603FR-13100KL"))
      (libsource (lib "eagle-import") (part "R-EU_R0603"))
    )
    (comp (ref "R38")
      (value "100kOhm/1%")
      (footprint "eagle-import:R0603")
      (fields (field (name "PARTNO") "RC0603FR-13100KL"))
      (libsource (lib "eagle-import") (part "R-EU_R0603"))
    )
    (comp (ref "R39")
      (value "100kOhm/1%")
      (footprint "eagle-import:R0603")
      (fields (field (name "PARTNO") "RC0603FR-13100KL"))
      (libsource (lib "eagle-import") (part "R-EU_R0603"))
    )
    (comp (ref "R40")
      (value "100kOhm/1%")
      (footprint "eagle-import:R0603")
      (fields (field (name "PARTNO") "RC0603FR-13100KL"))
      (libsource (lib "eagle-import") (part "R-EU_R0603"))
    )
    (comp (ref "R41")
      (value "100kOhm/1%")
      (footprint "eagle-import:R0603")
      (fields (field (name "PARTNO") "RC0603FR-13100KL"))
      (libsource (lib "eagle-import") (part "R-EU_R0603"))
    )
    (comp (ref "R42")
      (value "10kOhm/1%")
      (footprint "eagle-import:R0603")
      (fields (field (name "PARTNO") "RC0603FR-1010KL"))
      (libsource (lib "eagle-import") (part "R-EU_R0603"))
    )
    (comp (ref "R43")
      (value "10kOhm/1%")
      (footprint "eagle-import:R0603")
      (fields (field (name "PARTNO") "RC0603FR-1010KL"))
      (libsource (lib "eagle-import") (part "R-EU_R0603"))
    )
    (comp (ref "R44")
      (value "10kOhm/1%")
      (footprint "eagle-import:R0603")
      (fields (field (name "PARTNO") "RC0603FR-1010KL"))
      (libsource (lib "eagle-import") (part "R-EU_R0603"))
    )
    (comp (ref "R45")
      (value "10kOhm/1%")
      (footprint "eagle-import:R0603")
      (fields (field (name "PARTNO") "RC0603FR-1010KL"))
      (libsource (lib "eagle-import") (part "R-EU_R0603"))
    )
    (comp (ref "R46")
      (value "10kOhm/1%")
      (footprint "eagle-import:R0603")
      (fields (field (name "PARTNO") "RC0603FR-1010KL"))
      (libsource (lib "eagle-import") (part "R-EU_R0603"))
    )
    (comp (ref "R47")
      (value "10kOhm/1%")
      (footprint "eagle-import:R0603")
      (fields (field (name "PARTNO") "RC0603FR-1010KL"))
      (libsource (lib "eagle-import") (part "R-EU_R0603"))
    )
    (comp (ref "R48")
      (value "10kOhm/1%")
      (footprint "eagle-import:R0603")
      (fields (field (name "PARTNO") "RC0603FR-1010KL"))
      (libsource (lib "eagle-import") (part "R-EU_R0603"))
    )
    (comp (ref "R49")
      (value "10kOhm/1%")
      (footprint "eagle-import:R0603")
      (fields (field (name "PARTNO") "RC0603FR-1010KL"))
      (libsource (lib "eagle-import") (part "R-EU_R0603"))
    )
    (comp (ref "R50")
      (value "1kOhm/1%")
      (footprint "eagle-import:R2512")
      (fields (field (name "PARTNO") "RC2512FK-071KL"))
      (libsource (lib "eagle-import") (part "R-EU_R2512"))
    )
    (comp (ref "R51")
      (value "1kOhm/1%")
      (footprint "eagle-import:R2512")
      (fields (field (name "PARTNO") "RC2512FK-071KL"))
      (libsource (lib "eagle-import") (part "R-EU_R2512"))
    )
    (comp (ref "R52")
      (value "1kOhm/1%")
      (footprint "eagle-import:R2512")
      (fields (field (name "PARTNO") "RC2512FK-071KL"))
      (libsource (lib "eagle-import") (part "R-EU_R2512"))
    )
    (comp (ref "R53")
      (value "1kOhm/1%")
      (footprint "eagle-import:R2512")
      (fields (field (name "PARTNO") "RC2512FK-071KL"))
      (libsource (lib "eagle-import") (part "R-EU_R2512"))
    )
    (comp (ref "R54")
      (value "1kOhm/1%")
      (footprint "eagle-import:R2512")
      (fields (field (name "PARTNO") "RC2512FK-071KL"))
      (libsource (lib "eagle-import") (part "R-EU_R2512"))
    )
    (comp (ref "R55")
      (value "1kOhm/1%")
      (footprint "eagle-import:R2512")
      (fields (field (name "PARTNO") "RC2512FK-071KL"))
      (libsource (lib "eagle-import") (part "R-EU_R2512"))
    )
    (comp (ref "R56")
      (value "1kOhm/1%")
      (footprint "eagle-import:R2512")
      (fields (field (name "PARTNO") "RC2512FK-071KL"))
      (libsource (lib "eagle-import") (part "R-EU_R2512"))
    )
    (comp (ref "R57")
      (value "1kOhm/1%")
      (footprint "eagle-import:R2512")
      (fields (field (name "PARTNO") "RC2512FK-071KL"))
      (libsource (lib "eagle-import") (part "R-EU_R2512"))
    )
    (comp (ref "R58")
      (value "100kOhm/1%")
      (footprint "eagle-import:R0603")
      (fields (field (name "PARTNO") "RC0603FR-13100KL"))
      (libsource (lib "eagle-import") (part "R-EU_R0603"))
    )
    (comp (ref "R59")
      (value "100kOhm/1%")
      (footprint "eagle-import:R0603")
      (fields (field (name "PARTNO") "RC0603FR-13100KL"))
      (libsource (lib "eagle-import") (part "R-EU_R0603"))
    )
    (comp (ref "R60")
      (value "100kOhm/1%")
      (footprint "eagle-import:R0603")
      (fields (field (name "PARTNO") "RC0603FR-13100KL"))
      (libsource (lib "eagle-import") (part "R-EU_R0603"))
    )
    (comp (ref "R61")
      (value "100kOhm/1%")
      (footprint "eagle-import:R0603")
      (fields (field (name "PARTNO") "RC0603FR-13100KL"))
      (libsource (lib "eagle-import") (part "R-EU_R0603"))
    )
    (comp (ref "R62")
      (value "100kOhm/1%")
      (footprint "eagle-import:R0603")
      (fields (field (name "PARTNO") "RC0603FR-13100KL"))
      (libsource (lib "eagle-import") (part "R-EU_R0603"))
    )
    (comp (ref "R63")
      (value "100kOhm/1%")
      (footprint "eagle-import:R0603")
      (fields (field (name "PARTNO") "RC0603FR-13100KL"))
      (libsource (lib "eagle-import") (part "R-EU_R0603"))
    )
    (comp (ref "R64")
      (value "100kOhm/1%")
      (footprint "eagle-import:R0603")
      (fields (field (name "PARTNO") "RC0603FR-13100KL"))
      (libsource (lib "eagle-import") (part "R-EU_R0603"))
    )
    (comp (ref "R65")
      (value "100kOhm/1%")
      (footprint "eagle-import:R0603")
      (fields (field (name "PARTNO") "RC0603FR-13100KL"))
      (libsource (lib "eagle-import") (part "R-EU_R0603"))
    )
    (comp (ref "R66")
      (value "10kOhm/1%")
      (footprint "eagle-import:R0603")
      (fields (field (name "PARTNO") "RC0603FR-1010KL"))
      (libsource (lib "eagle-import") (part "R-EU_R0603"))
    )
    (comp (ref "R67")
      (value "10kOhm/1%")
      (footprint "eagle-import:R0603")
      (fields (field (name "PARTNO") "RC0603FR-1010KL"))
      (libsource (lib "eagle-import") (part "R-EU_R0603"))
    )
    (comp (ref "R68")
      (value "10kOhm/1%")
      (footprint "eagle-import:R0603")
      (fields (field (name "PARTNO") "RC0603FR-1010KL"))
      (libsource (lib "eagle-import") (part "R-EU_R0603"))
    )
    (comp (ref "R69")
      (value "10kOhm/1%")
      (footprint "eagle-import:R0603")
      (fields (field (name "PARTNO") "RC0603FR-1010KL"))
      (libsource (lib "eagle-import") (part "R-EU_R0603"))
    )
    (comp (ref "R70")
      (value "10kOhm/1%")
      (footprint "eagle-import:R0603")
      (fields (field (name "PARTNO") "RC0603FR-1010KL"))
      (libsource (lib "eagle-import") (part "R-EU_R0603"))
    )
    (comp (ref "R71")
      (value "10kOhm/1%")
      (footprint "eagle-import:R0603")
      (fields (field (name "PARTNO") "RC0603FR-1010KL"))
      (libsource (lib "eagle-import") (part "R-EU_R0603"))
    )
    (comp (ref "R72")
      (value "10kOhm/1%")
      (footprint "eagle-import:R0603")
      (fields (field (name "PARTNO") "RC0603FR-1010KL"))
      (libsource (lib "eagle-import") (part "R-EU_R0603"))
    )
    (comp (ref "R73")
      (value "10kOhm/1%")
      (footprint "eagle-import:R0603")
      (fields (field (name "PARTNO") "RC0603FR-1010KL"))
      (libsource (lib "eagle-import") (part "R-EU_R0603"))
    )
    (comp (ref "VD4")
      (value "SMBJ24CA")
      (footprint "eagle-import:SMB-BIDIR")
      (libsource (lib "eagle-import") (part "DIODE-TVS-BIDIR-SMB"))
    )
    (comp (ref "VD5")
      (value "SMBJ24CA")
      (footprint "eagle-import:SMB-BIDIR")
      (libsource (lib "eagle-import") (part "DIODE-TVS-BIDIR-SMB"))
    )
    (comp (ref "VD6")
      (value "SMBJ24CA")
      (footprint "eagle-import:SMB-BIDIR")
      (libsource (lib "eagle-import") (part "DIODE-TVS-BIDIR-SMB"))
    )
    (comp (ref "VD7")
      (value "SMBJ24CA")
      (footprint "eagle-import:SMB-BIDIR")
      (libsource (lib "eagle-import") (part "DIODE-TVS-BIDIR-SMB"))
    )
    (comp (ref "VD8")
      (value "SMBJ24CA")
      (footprint "eagle-import:SMB-BIDIR")
      (libsource (lib "eagle-import") (part "DIODE-TVS-BIDIR-SMB"))
    )
    (comp (ref "VD9")
      (value "SMBJ24CA")
      (footprint "eagle-import:SMB-BIDIR")
      (libsource (lib "eagle-import") (part "DIODE-TVS-BIDIR-SMB"))
    )
    (comp (ref "VD10")
      (value "SMBJ24CA")
      (footprint "eagle-import:SMB-BIDIR")
      (libsource (lib "eagle-import") (part "DIODE-TVS-BIDIR-SMB"))
    )
    (comp (ref "VD11")
      (value "SMBJ24CA")
      (footprint "eagle-import:SMB-BIDIR")
      (libsource (lib "eagle-import") (part "DIODE-TVS-BIDIR-SMB"))
    )
    (comp (ref "VD12")
      (value "40V")
      (footprint "eagle-import:SOD323")
      (fields (field (name "PARTNO") "BAT54JFILM"))
      (libsource (lib "eagle-import") (part "DIODE-SCHOTTKY-SOD323"))
    )
    (comp (ref "VD13")
      (value "40V")
      (footprint "eagle-import:SOD323")
      (fields (field (name "PARTNO") "BAT54JFILM"))
      (libsource (lib "eagle-import") (part "DIODE-SCHOTTKY-SOD323"))
    )
    (comp (ref "VD14")
      (value "40V")
      (footprint "eagle-import:SOD323")
      (fields (field (name "PARTNO") "BAT54JFILM"))
      (libsource (lib "eagle-import") (part "DIODE-SCHOTTKY-SOD323"))
    )
    (comp (ref "VD15")
      (value "40V")
      (footprint "eagle-import:SOD323")
      (fields (field (name "PARTNO") "BAT54JFILM"))
      (libsource (lib "eagle-import") (part "DIODE-SCHOTTKY-SOD323"))
    )
    (comp (ref "VD16")
      (value "40V")
      (footprint "eagle-import:SOD323")
      (fields (field (name "PARTNO") "BAT54JFILM"))
      (libsource (lib "eagle-import") (part "DIODE-SCHOTTKY-SOD323"))
    )
    (comp (ref "VD17")
      (value "40V")
      (footprint "eagle-import:SOD323")
      (fields (field (name "PARTNO") "BAT54JFILM"))
      (libsource (lib "eagle-import") (part "DIODE-SCHOTTKY-SOD323"))
    )
    (comp (ref "VD18")
      (value "40V")
      (footprint "eagle-import:SOD323")
      (fields (field (name "PARTNO") "BAT54JFILM"))
      (libsource (lib "eagle-import") (part "DIODE-SCHOTTKY-SOD323"))
    )
    (comp (ref "VD19")
      (value "40V")
      (footprint "eagle-import:SOD323")
      (fields (field (name "PARTNO") "BAT54JFILM"))
      (libsource (lib "eagle-import") (part "DIODE-SCHOTTKY-SOD323"))
    )
    (comp (ref "VD20")
      (value "SMBJ24CA")
      (footprint "eagle-import:SMB-BIDIR")
      (libsource (lib "eagle-import") (part "DIODE-TVS-BIDIR-SMB"))
    )
    (comp (ref "VD21")
      (value "SMBJ24CA")
      (footprint "eagle-import:SMB-BIDIR")
      (libsource (lib "eagle-import") (part "DIODE-TVS-BIDIR-SMB"))
    )
    (comp (ref "VD22")
      (value "SMBJ24CA")
      (footprint "eagle-import:SMB-BIDIR")
      (libsource (lib "eagle-import") (part "DIODE-TVS-BIDIR-SMB"))
    )
    (comp (ref "VD23")
      (value "SMBJ24CA")
      (footprint "eagle-import:SMB-BIDIR")
      (libsource (lib "eagle-import") (part "DIODE-TVS-BIDIR-SMB"))
    )
    (comp (ref "VD24")
      (value "SMBJ24CA")
      (footprint "eagle-import:SMB-BIDIR")
      (libsource (lib "eagle-import") (part "DIODE-TVS-BIDIR-SMB"))
    )
    (comp (ref "VD25")
      (value "SMBJ24CA")
      (footprint "eagle-import:SMB-BIDIR")
      (libsource (lib "eagle-import") (part "DIODE-TVS-BIDIR-SMB"))
    )
    (comp (ref "VD26")
      (value "SMBJ24CA")
      (footprint "eagle-import:SMB-BIDIR")
      (libsource (lib "eagle-import") (part "DIODE-TVS-BIDIR-SMB"))
    )
    (comp (ref "VD27")
      (value "SMBJ24CA")
      (footprint "eagle-import:SMB-BIDIR")
      (libsource (lib "eagle-import") (part "DIODE-TVS-BIDIR-SMB"))
    )
    (comp (ref "VD28")
      (value "40V")
      (footprint "eagle-import:SOD323")
      (fields (field (name "PARTNO") "BAT54JFILM"))
      (libsource (lib "eagle-import") (part "DIODE-SCHOTTKY-SOD323"))
    )
    (comp (ref "VD29")
      (value "40V")
      (footprint "eagle-import:SOD323")
      (fields (field (name "PARTNO") "BAT54JFILM"))
      (libsource (lib "eagle-import") (part "DIODE-SCHOTTKY-SOD323"))
    )
    (comp (ref "VD30")
      (value "40V")
      (footprint "eagle-import:SOD323")
      (fields (field (name "PARTNO") "BAT54JFILM"))
      (libsource (lib "eagle-import") (part "DIODE-SCHOTTKY-SOD323"))
    )
    (comp (ref "VD31")
      (value "40V")
      (footprint "eagle-import:SOD323")
      (fields (field (name "PARTNO") "BAT54JFILM"))
      (libsource (lib "eagle-import") (part "DIODE-SCHOTTKY-SOD323"))
    )
    (comp (ref "VD32")
      (value "40V")
      (footprint "eagle-import:SOD323")
      (fields (field (name "PARTNO") "BAT54JFILM"))
      (libsource (lib "eagle-import") (part "DIODE-SCHOTTKY-SOD323"))
    )
    (comp (ref "VD33")
      (value "40V")
      (footprint "eagle-import:SOD323")
      (fields (field (name "PARTNO") "BAT54JFILM"))
      (libsource (lib "eagle-import") (part "DIODE-SCHOTTKY-SOD323"))
    )
    (comp (ref "VD34")
      (value "40V")
      (footprint "eagle-import:SOD323")
      (fields (field (name "PARTNO") "BAT54JFILM"))
      (libsource (lib "eagle-import") (part "DIODE-SCHOTTKY-SOD323"))
    )
    (comp (ref "VD35")
      (value "40V")
      (footprint "eagle-import:SOD323")
      (fields (field (name "PARTNO") "BAT54JFILM"))
      (libsource (lib "eagle-import") (part "DIODE-SCHOTTKY-SOD323"))
    )
    (comp (ref "XP4")
      (value "MOLEX-90130-16")
      (footprint "eagle-import:MOLEX-90130-16")
      (fields (field (name "LABEL") "ANALOG") (field (name "PARTNO") "90130-1216"))
      (libsource (lib "eagle-import") (part "MOLEX-90130-16"))
    )
    (comp (ref "Z22")
      (value "NFE31PT")
      (footprint "eagle-import:NFE31")
      (fields (field (name "PARTNO") "NFE31PT152Z1E9"))
      (libsource (lib "eagle-import") (part "NFE31PT"))
    )
    (comp (ref "Z23")
      (value "NFE31PT")
      (footprint "eagle-import:NFE31")
      (fields (field (name "PARTNO") "NFE31PT152Z1E9"))
      (libsource (lib "eagle-import") (part "NFE31PT"))
    )
    (comp (ref "Z24")
      (value "NFE31PT")
      (footprint "eagle-import:NFE31")
      (fields (field (name "PARTNO") "NFE31PT152Z1E9"))
      (libsource (lib "eagle-import") (part "NFE31PT"))
    )
    (comp (ref "Z25")
      (value "NFE31PT")
      (footprint "eagle-import:NFE31")
      (fields (field (name "PARTNO") "NFE31PT152Z1E9"))
      (libsource (lib "eagle-import") (part "NFE31PT"))
    )
    (comp (ref "Z26")
      (value "NFE31PT")
      (footprint "eagle-import:NFE31")
      (fields (field (name "PARTNO") "NFE31PT152Z1E9"))
      (libsource (lib "eagle-import") (part "NFE31PT"))
    )
    (comp (ref "Z27")
      (value "NFE31PT")
      (footprint "eagle-import:NFE31")
      (fields (field (name "PARTNO") "NFE31PT152Z1E9"))
      (libsource (lib "eagle-import") (part "NFE31PT"))
    )
    (comp (ref "Z28")
      (value "NFE31PT")
      (footprint "eagle-import:NFE31")
      (fields (field (name "PARTNO") "NFE31PT152Z1E9"))
      (libsource (lib "eagle-import") (part "NFE31PT"))
    )
    (comp (ref "Z29")
      (value "NFE31PT")
      (footprint "eagle-import:NFE31")
      (fields (field (name "PARTNO") "NFE31PT152Z1E9"))
      (libsource (lib "eagle-import") (part "NFE31PT"))
    )
    (comp (ref "Z30")
      (value "NFE31PT")
      (footprint "eagle-import:NFE31")
      (fields (field (name "PARTNO") "NFE31PT152Z1E9"))
      (libsource (lib "eagle-import") (part "NFE31PT"))
    )
    (comp (ref "Z31")
      (value "NFE31PT")
      (footprint "eagle-import:NFE31")
      (fields (field (name "PARTNO") "NFE31PT152Z1E9"))
      (libsource (lib "eagle-import") (part "NFE31PT"))
    )
    (comp (ref "Z32")
      (value "NFE31PT")
      (footprint "eagle-import:NFE31")
      (fields (field (name "PARTNO") "NFE31PT152Z1E9"))
      (libsource (lib "eagle-import") (part "NFE31PT"))
    )
    (comp (ref "Z33")
      (value "NFE31PT")
      (footprint "eagle-import:NFE31")
      (fields (field (name "PARTNO") "NFE31PT152Z1E9"))
      (libsource (lib "eagle-import") (part "NFE31PT"))
    )
    (comp (ref "Z34")
      (value "NFE31PT")
      (footprint "eagle-import:NFE31")
      (fields (field (name "PARTNO") "NFE31PT152Z1E9"))
      (libsource (lib "eagle-import") (part "NFE31PT"))
    )
    (comp (ref "Z35")
      (value "NFE31PT")
      (footprint "eagle-import:NFE31")
      (fields (field (name "PARTNO") "NFE31PT152Z1E9"))
      (libsource (lib "eagle-import") (part "NFE31PT"))
    )
    (comp (ref "Z36")
      (value "NFE31PT")
      (footprint "eagle-import:NFE31")
      (fields (field (name "PARTNO") "NFE31PT152Z1E9"))
      (libsource (lib "eagle-import") (part "NFE31PT"))
    )
    (comp (ref "Z37")
      (value "NFE31PT")
      (footprint "eagle-import:NFE31")
      (fields (field (name "PARTNO") "NFE31PT152Z1E9"))
      (libsource (lib "eagle-import") (part "NFE31PT"))
    )
    (comp (ref "C28")
      (value "0.1uF")
      (footprint "eagle-import:C0603")
      (fields (field (name "PARTNO") "C0603C104K5RACTU"))
      (libsource (lib "eagle-import") (part "C-EUC0603"))
    )
    (comp (ref "C29")
      (value "0.1uF")
      (footprint "eagle-import:C0603")
      (fields (field (name "PARTNO") "C0603C104K5RACTU"))
      (libsource (lib "eagle-import") (part "C-EUC0603"))
    )
    (comp (ref "C30")
      (value "0.1uF")
      (footprint "eagle-import:C0603")
      (fields (field (name "PARTNO") "C0603C104K5RACTU"))
      (libsource (lib "eagle-import") (part "C-EUC0603"))
    )
    (comp (ref "C31")
      (value "0.1uF")
      (footprint "eagle-import:C0603")
      (fields (field (name "PARTNO") "C0603C104K5RACTU"))
      (libsource (lib "eagle-import") (part "C-EUC0603"))
    )
    (comp (ref "C32")
      (value "0.1uF")
      (footprint "eagle-import:C0603")
      (fields (field (name "PARTNO") "C0603C104K5RACTU"))
      (libsource (lib "eagle-import") (part "C-EUC0603"))
    )
    (comp (ref "C33")
      (value "0.1uF")
      (footprint "eagle-import:C0603")
      (fields (field (name "PARTNO") "C0603C104K5RACTU"))
      (libsource (lib "eagle-import") (part "C-EUC0603"))
    )
    (comp (ref "C34")
      (value "0.1uF")
      (footprint "eagle-import:C0603")
      (fields (field (name "PARTNO") "C0603C104K5RACTU"))
      (libsource (lib "eagle-import") (part "C-EUC0603"))
    )
    (comp (ref "C35")
      (value "0.1uF")
      (footprint "eagle-import:C0603")
      (fields (field (name "PARTNO") "C0603C104K5RACTU"))
      (libsource (lib "eagle-import") (part "C-EUC0603"))
    )
    (comp (ref "C36")
      (value "0.1uF")
      (footprint "eagle-import:C0603")
      (fields (field (name "PARTNO") "C0603C104K5RACTU"))
      (libsource (lib "eagle-import") (part "C-EUC0603"))
    )
    (comp (ref "C37")
      (value "0.1uF")
      (footprint "eagle-import:C0603")
      (fields (field (name "PARTNO") "C0603C104K5RACTU"))
      (libsource (lib "eagle-import") (part "C-EUC0603"))
    )
    (comp (ref "C38")
      (value "0.1uF")
      (footprint "eagle-import:C0603")
      (fields (field (name "PARTNO") "C0603C104K5RACTU"))
      (libsource (lib "eagle-import") (part "C-EUC0603"))
    )
    (comp (ref "C39")
      (value "0.1uF")
      (footprint "eagle-import:C0603")
      (fields (field (name "PARTNO") "C0603C104K5RACTU"))
      (libsource (lib "eagle-import") (part "C-EUC0603"))
    )
    (comp (ref "C40")
      (value "0.1uF")
      (footprint "eagle-import:C0603")
      (fields (field (name "PARTNO") "C0603C104K5RACTU"))
      (libsource (lib "eagle-import") (part "C-EUC0603"))
    )
    (comp (ref "C41")
      (value "0.1uF")
      (footprint "eagle-import:C0603")
      (fields (field (name "PARTNO") "C0603C104K5RACTU"))
      (libsource (lib "eagle-import") (part "C-EUC0603"))
    )
    (comp (ref "C42")
      (value "0.1uF")
      (footprint "eagle-import:C0603")
      (fields (field (name "PARTNO") "C0603C104K5RACTU"))
      (libsource (lib "eagle-import") (part "C-EUC0603"))
    )
    (comp (ref "C43")
      (value "1000pF")
      (footprint "eagle-import:C0603")
      (fields (field (name "PARTNO") "C0603C102K5RACTU"))
      (libsource (lib "eagle-import") (part "C-EUC0603"))
    )
    (comp (ref "C44")
      (value "1000pF")
      (footprint "eagle-import:C0603")
      (fields (field (name "PARTNO") "C0603C102K5RACTU"))
      (libsource (lib "eagle-import") (part "C-EUC0603"))
    )
    (comp (ref "C45")
      (value "1000pF")
      (footprint "eagle-import:C0603")
      (fields (field (name "PARTNO") "C0603C102K5RACTU"))
      (libsource (lib "eagle-import") (part "C-EUC0603"))
    )
    (comp (ref "C46")
      (value "1000pF")
      (footprint "eagle-import:C0603")
      (fields (field (name "PARTNO") "C0603C102K5RACTU"))
      (libsource (lib "eagle-import") (part "C-EUC0603"))
    )
    (comp (ref "C47")
      (value "1000pF")
      (footprint "eagle-import:C0603")
      (fields (field (name "PARTNO") "C0603C102K5RACTU"))
      (libsource (lib "eagle-import") (part "C-EUC0603"))
    )
    (comp (ref "C48")
      (value "1000pF")
      (footprint "eagle-import:C0603")
      (fields (field (name "PARTNO") "C0603C102K5RACTU"))
      (libsource (lib "eagle-import") (part "C-EUC0603"))
    )
    (comp (ref "C49")
      (value "5600pF")
      (footprint "eagle-import:C0603")
      (fields (field (name "PARTNO") "C0603C562K5RACTU"))
      (libsource (lib "eagle-import") (part "C-EUC0603"))
    )
    (comp (ref "C50")
      (value "0.1uF")
      (footprint "eagle-import:C0603")
      (fields (field (name "PARTNO") "C0603C104K5RACTU"))
      (libsource (lib "eagle-import") (part "C-EUC0603"))
    )
    (comp (ref "C51")
      (value "5600pF")
      (footprint "eagle-import:C0603")
      (fields (field (name "PARTNO") "C0603C562K5RACTU"))
      (libsource (lib "eagle-import") (part "C-EUC0603"))
    )
    (comp (ref "C52")
      (value "0.1uF")
      (footprint "eagle-import:C0603")
      (fields (field (name "PARTNO") "C0603C104K5RACTU"))
      (libsource (lib "eagle-import") (part "C-EUC0603"))
    )
    (comp (ref "C53")
      (value "0.1uF")
      (footprint "eagle-import:C0603")
      (fields (field (name "PARTNO") "C0603C104K5RACTU"))
      (libsource (lib "eagle-import") (part "C-EUC0603"))
    )
    (comp (ref "C54")
      (value "0.1uF")
      (footprint "eagle-import:C0603")
      (fields (field (name "PARTNO") "C0603C104K5RACTU"))
      (libsource (lib "eagle-import") (part "C-EUC0603"))
    )
    (comp (ref "C55")
      (value "0.1uF")
      (footprint "eagle-import:C0603")
      (fields (field (name "PARTNO") "C0603C104K5RACTU"))
      (libsource (lib "eagle-import") (part "C-EUC0603"))
    )
    (comp (ref "DA1")
      (value "LM2904M")
      (footprint "eagle-import:SO08")
      (fields (field (name "PARTNO") "LM2904M"))
      (libsource (lib "eagle-import") (part "LM2904M"))
    )
    (comp (ref "DA2")
      (value "LM2904M")
      (footprint "eagle-import:SO08")
      (fields (field (name "PARTNO") "LM2904M"))
      (libsource (lib "eagle-import") (part "LM2904M"))
    )
    (comp (ref "DA3")
      (value "LM2904M")
      (footprint "eagle-import:SO08")
      (fields (field (name "PARTNO") "LM2904M"))
      (libsource (lib "eagle-import") (part "LM2904M"))
    )
    (comp (ref "DA4")
      (value "IL311AD")
      (footprint "eagle-import:SO08")
      (fields (field (name "PARTNO") "IL311AD"))
      (libsource (lib "eagle-import") (part "IL311AD"))
    )
    (comp (ref "DA5")
      (value "IL311AD")
      (footprint "eagle-import:SO08")
      (fields (field (name "PARTNO") "IL311AD"))
      (libsource (lib "eagle-import") (part "IL311AD"))
    )
    (comp (ref "DA6")
      (value "IL311AD")
      (footprint "eagle-import:SO08")
      (fields (field (name "PARTNO") "IL311AD"))
      (libsource (lib "eagle-import") (part "IL311AD"))
    )
    (comp (ref "DA7")
      (value "74HC123D")
      (footprint "eagle-import:SO16")
      (fields (field (name "PARTNO") "IN74HC123AD"))
      (libsource (lib "eagle-import") (part "74123DHC"))
    )
    (comp (ref "DA8")
      (value "74HC123D")
      (footprint "eagle-import:SO16")
      (fields (field (name "PARTNO") "IN74HC123AD"))
      (libsource (lib "eagle-import") (part "74123DHC"))
    )
    (comp (ref "DA9")
      (value "74HC123D")
      (footprint "eagle-import:SO16")
      (fields (field (name "PARTNO") "IN74HC123AD"))
      (libsource (lib "eagle-import") (part "74123DHC"))
    )
    (comp (ref "DA10")
      (value "SA555D")
      (footprint "eagle-import:SO08")
      (libsource (lib "eagle-import") (part "555DSA"))
    )
    (comp (ref "DD3")
      (value "74HC11D")
      (footprint "eagle-import:SO14")
      (fields (field (name "PARTNO") "IN74HC11AD"))
      (libsource (lib "eagle-import") (part "7411DHC"))
    )
    (comp (ref "R74")
      (value "1.2kOhm/5%")
      (footprint "eagle-import:R0603")
      (fields (field (name "PARTNO") "RC0603JR-071K2L"))
      (libsource (lib "eagle-import") (part "R-EU_R0603"))
    )
    (comp (ref "R75")
      (value "1.2kOhm/5%")
      (footprint "eagle-import:R0603")
      (fields (field (name "PARTNO") "RC0603JR-071K2L"))
      (libsource (lib "eagle-import") (part "R-EU_R0603"))
    )
    (comp (ref "R76")
      (value "1.2kOhm/5%")
      (footprint "eagle-import:R0603")
      (fields (field (name "PARTNO") "RC0603JR-071K2L"))
      (libsource (lib "eagle-import") (part "R-EU_R0603"))
    )
    (comp (ref "R77")
      (value "5.1kOhm/1%")
      (footprint "eagle-import:R0603")
      (fields (field (name "PARTNO") "RC0603FR-075K1L"))
      (libsource (lib "eagle-import") (part "R-EU_R0603"))
    )
    (comp (ref "R78")
      (value "5.1kOhm/1%")
      (footprint "eagle-import:R0603")
      (fields (field (name "PARTNO") "RC0603FR-075K1L"))
      (libsource (lib "eagle-import") (part "R-EU_R0603"))
    )
    (comp (ref "R79")
      (value "5.1kOhm/1%")
      (footprint "eagle-import:R0603")
      (fields (field (name "PARTNO") "RC0603FR-075K1L"))
      (libsource (lib "eagle-import") (part "R-EU_R0603"))
    )
    (comp (ref "R80")
      (value "5.1kOhm/1%")
      (footprint "eagle-import:R0603")
      (fields (field (name "PARTNO") "RC0603FR-075K1L"))
      (libsource (lib "eagle-import") (part "R-EU_R0603"))
    )
    (comp (ref "R81")
      (value "5.1kOhm/1%")
      (footprint "eagle-import:R0603")
      (fields (field (name "PARTNO") "RC0603FR-075K1L"))
      (libsource (lib "eagle-import") (part "R-EU_R0603"))
    )
    (comp (ref "R82")
      (value "5.1kOhm/1%")
      (footprint "eagle-import:R0603")
      (fields (field (name "PARTNO") "RC0603FR-075K1L"))
      (libsource (lib "eagle-import") (part "R-EU_R0603"))
    )
    (comp (ref "R83")
      (value "100kOhm/1%")
      (footprint "eagle-import:R0603")
      (fields (field (name "PARTNO") "RC0603FR-13100KL"))
      (libsource (lib "eagle-import") (part "R-EU_R0603"))
    )
    (comp (ref "R84")
      (value "100kOhm/1%")
      (footprint "eagle-import:R0603")
      (fields (field (name "PARTNO") "RC0603FR-13100KL"))
      (libsource (lib "eagle-import") (part "R-EU_R0603"))
    )
    (comp (ref "R85")
      (value "100kOhm/1%")
      (footprint "eagle-import:R0603")
      (fields (field (name "PARTNO") "RC0603FR-13100KL"))
      (libsource (lib "eagle-import") (part "R-EU_R0603"))
    )
    (comp (ref "R86")
      (value "2.2kOhm/5%")
      (footprint "eagle-import:R0603")
      (fields (field (name "PARTNO") "RC0603JR-072K2L"))
      (libsource (lib "eagle-import") (part "R-EU_R0603"))
    )
    (comp (ref "R87")
      (value "10kOhm/1%")
      (footprint "eagle-import:R0603")
      (fields (field (name "PARTNO") "RC0603FR-1010KL"))
      (libsource (lib "eagle-import") (part "R-EU_R0603"))
    )
    (comp (ref "R88")
      (value "10kOhm/1%")
      (footprint "eagle-import:R0603")
      (fields (field (name "PARTNO") "RC0603FR-1010KL"))
      (libsource (lib "eagle-import") (part "R-EU_R0603"))
    )
    (comp (ref "R89")
      (value "10kOhm/1%")
      (footprint "eagle-import:R0603")
      (fields (field (name "PARTNO") "RC0603FR-1010KL"))
      (libsource (lib "eagle-import") (part "R-EU_R0603"))
    )
    (comp (ref "R90")
      (value "10kOhm/1%")
      (footprint "eagle-import:R0603")
      (fields (field (name "PARTNO") "RC0603FR-1010KL"))
      (libsource (lib "eagle-import") (part "R-EU_R0603"))
    )
    (comp (ref "R91")
      (value "2.2kOhm/5%")
      (footprint "eagle-import:R0603")
      (fields (field (name "PARTNO") "RC0603JR-072K2L"))
      (libsource (lib "eagle-import") (part "R-EU_R0603"))
    )
    (comp (ref "R92")
      (value "10kOhm/1%")
      (footprint "eagle-import:R0603")
      (fields (field (name "PARTNO") "RC0603FR-1010KL"))
      (libsource (lib "eagle-import") (part "R-EU_R0603"))
    )
    (comp (ref "R93")
      (value "10kOhm/1%")
      (footprint "eagle-import:R0603")
      (fields (field (name "PARTNO") "RC0603FR-1010KL"))
      (libsource (lib "eagle-import") (part "R-EU_R0603"))
    )
    (comp (ref "R94")
      (value "10kOhm/1%")
      (footprint "eagle-import:R0603")
      (fields (field (name "PARTNO") "RC0603FR-1010KL"))
      (libsource (lib "eagle-import") (part "R-EU_R0603"))
    )
    (comp (ref "R95")
      (value "10kOhm/1%")
      (footprint "eagle-import:R0603")
      (fields (field (name "PARTNO") "RC0603FR-1010KL"))
      (libsource (lib "eagle-import") (part "R-EU_R0603"))
    )
    (comp (ref "R96")
      (value "2.2kOhm/5%")
      (footprint "eagle-import:R0603")
      (fields (field (name "PARTNO") "RC0603JR-072K2L"))
      (libsource (lib "eagle-import") (part "R-EU_R0603"))
    )
    (comp (ref "R97")
      (value "10kOhm/1%")
      (footprint "eagle-import:R0603")
      (fields (field (name "PARTNO") "RC0603FR-1010KL"))
      (libsource (lib "eagle-import") (part "R-EU_R0603"))
    )
    (comp (ref "R98")
      (value "10kOhm/1%")
      (footprint "eagle-import:R0603")
      (fields (field (name "PARTNO") "RC0603FR-1010KL"))
      (libsource (lib "eagle-import") (part "R-EU_R0603"))
    )
    (comp (ref "R99")
      (value "10kOhm/1%")
      (footprint "eagle-import:R0603")
      (fields (field (name "PARTNO") "RC0603FR-1010KL"))
      (libsource (lib "eagle-import") (part "R-EU_R0603"))
    )
    (comp (ref "R100")
      (value "10kOhm/1%")
      (footprint "eagle-import:R0603")
      (fields (field (name "PARTNO") "RC0603FR-1010KL"))
      (libsource (lib "eagle-import") (part "R-EU_R0603"))
    )
    (comp (ref "R101")
      (value "1.2kOhm/5%")
      (footprint "eagle-import:R0603")
      (fields (field (name "PARTNO") "RC0603JR-071K2L"))
      (libsource (lib "eagle-import") (part "R-EU_R0603"))
    )
    (comp (ref "R102")
      (value "1.2kOhm/5%")
      (footprint "eagle-import:R0603")
      (fields (field (name "PARTNO") "RC0603JR-071K2L"))
      (libsource (lib "eagle-import") (part "R-EU_R0603"))
    )
    (comp (ref "R103")
      (value "1.2kOhm/5%")
      (footprint "eagle-import:R0603")
      (fields (field (name "PARTNO") "RC0603JR-071K2L"))
      (libsource (lib "eagle-import") (part "R-EU_R0603"))
    )
    (comp (ref "R104")
      (value "1.2kOhm/5%")
      (footprint "eagle-import:R0603")
      (fields (field (name "PARTNO") "RC0603JR-071K2L"))
      (libsource (lib "eagle-import") (part "R-EU_R0603"))
    )
    (comp (ref "R105")
      (value "1.2kOhm/5%")
      (footprint "eagle-import:R0603")
      (fields (field (name "PARTNO") "RC0603JR-071K2L"))
      (libsource (lib "eagle-import") (part "R-EU_R0603"))
    )
    (comp (ref "R106")
      (value "1.2kOhm/5%")
      (footprint "eagle-import:R0603")
      (fields (field (name "PARTNO") "RC0603JR-071K2L"))
      (libsource (lib "eagle-import") (part "R-EU_R0603"))
    )
    (comp (ref "R107")
      (value "22kOhm/5%")
      (footprint "eagle-import:R0603")
      (fields (field (name "PARTNO") "RC0603JR-0722KL"))
      (libsource (lib "eagle-import") (part "R-EU_R0603"))
    )
    (comp (ref "R108")
      (value "22kOhm/5%")
      (footprint "eagle-import:R0603")
      (fields (field (name "PARTNO") "RC0603JR-0722KL"))
      (libsource (lib "eagle-import") (part "R-EU_R0603"))
    )
    (comp (ref "R109")
      (value "22kOhm/5%")
      (footprint "eagle-import:R0603")
      (fields (field (name "PARTNO") "RC0603JR-0722KL"))
      (libsource (lib "eagle-import") (part "R-EU_R0603"))
    )
    (comp (ref "R110")
      (value "22kOhm/5%")
      (footprint "eagle-import:R0603")
      (fields (field (name "PARTNO") "RC0603JR-0722KL"))
      (libsource (lib "eagle-import") (part "R-EU_R0603"))
    )
    (comp (ref "R111")
      (value "22kOhm/5%")
      (footprint "eagle-import:R0603")
      (fields (field (name "PARTNO") "RC0603JR-0722KL"))
      (libsource (lib "eagle-import") (part "R-EU_R0603"))
    )
    (comp (ref "R112")
      (value "22kOhm/5%")
      (footprint "eagle-import:R0603")
      (fields (field (name "PARTNO") "RC0603JR-0722KL"))
      (libsource (lib "eagle-import") (part "R-EU_R0603"))
    )
    (comp (ref "R113")
      (value "1.2kOhm/5%")
      (footprint "eagle-import:R0603")
      (fields (field (name "PARTNO") "RC0603JR-071K2L"))
      (libsource (lib "eagle-import") (part "R-EU_R0603"))
    )
    (comp (ref "R114")
      (value "1.2kOhm/5%")
      (footprint "eagle-import:R0603")
      (fields (field (name "PARTNO") "RC0603JR-071K2L"))
      (libsource (lib "eagle-import") (part "R-EU_R0603"))
    )
    (comp (ref "R115")
      (value "1.2kOhm/5%")
      (footprint "eagle-import:R0603")
      (fields (field (name "PARTNO") "RC0603JR-071K2L"))
      (libsource (lib "eagle-import") (part "R-EU_R0603"))
    )
    (comp (ref "R116")
      (value "1kOhm/20%")
      (footprint "eagle-import:RTRIMTSM53YJ")
      (fields (field (name "PARTNO") "TSM4YJ102KR05"))
      (libsource (lib "eagle-import") (part "R-TRIMMTSM4YJ"))
    )
    (comp (ref "R117")
      (value "51kOhm/5%")
      (footprint "eagle-import:R0603")
      (fields (field (name "PARTNO") "RC0603JR-0751KL"))
      (libsource (lib "eagle-import") (part "R-EU_R0603"))
    )
    (comp (ref "R118")
      (value "51kOhm/5%")
      (footprint "eagle-import:R0603")
      (fields (field (name "PARTNO") "RC0603JR-0751KL"))
      (libsource (lib "eagle-import") (part "R-EU_R0603"))
    )
    (comp (ref "R119")
      (value "51kOhm/5%")
      (footprint "eagle-import:R0603")
      (fields (field (name "PARTNO") "RC0603JR-0751KL"))
      (libsource (lib "eagle-import") (part "R-EU_R0603"))
    )
    (comp (ref "R120")
      (value "51kOhm/5%")
      (footprint "eagle-import:R0603")
      (fields (field (name "PARTNO") "RC0603JR-0751KL"))
      (libsource (lib "eagle-import") (part "R-EU_R0603"))
    )
    (comp (ref "R121")
      (value "51kOhm/5%")
      (footprint "eagle-import:R0603")
      (fields (field (name "PARTNO") "RC0603JR-0751KL"))
      (libsource (lib "eagle-import") (part "R-EU_R0603"))
    )
    (comp (ref "R122")
      (value "51kOhm/5%")
      (footprint "eagle-import:R0603")
      (fields (field (name "PARTNO") "RC0603JR-0751KL"))
      (libsource (lib "eagle-import") (part "R-EU_R0603"))
    )
    (comp (ref "R123")
      (value "51kOhm/5%")
      (footprint "eagle-import:R0603")
      (fields (field (name "PARTNO") "RC0603JR-0751KL"))
      (libsource (lib "eagle-import") (part "R-EU_R0603"))
    )
    (comp (ref "R124")
      (value "1kOhm/5%")
      (footprint "eagle-import:R2512")
      (fields (field (name "PARTNO") "RC2512JK-071KL"))
      (libsource (lib "eagle-import") (part "R-EU_R2512"))
    )
    (comp (ref "R125")
      (value "1kOhm/5%")
      (footprint "eagle-import:R2512")
      (fields (field (name "PARTNO") "RC2512JK-071KL"))
      (libsource (lib "eagle-import") (part "R-EU_R2512"))
    )
    (comp (ref "R126")
      (value "100kOhm/1%")
      (footprint "eagle-import:R0603")
      (fields (field (name "PARTNO") "RC0603FR-13100KL"))
      (libsource (lib "eagle-import") (part "R-EU_R0603"))
    )
    (comp (ref "R127")
      (value "100kOhm/1%")
      (footprint "eagle-import:R0603")
      (fields (field (name "PARTNO") "RC0603FR-13100KL"))
      (libsource (lib "eagle-import") (part "R-EU_R0603"))
    )
    (comp (ref "R128")
      (value "36kOhm/5%")
      (footprint "eagle-import:R0603")
      (fields (field (name "PARTNO") "ERJ3GEYJ363V"))
      (libsource (lib "eagle-import") (part "R-EU_R0603"))
    )
    (comp (ref "R129")
      (value "36kOhm/5%")
      (footprint "eagle-import:R0603")
      (fields (field (name "PARTNO") "ERJ3GEYJ363V"))
      (libsource (lib "eagle-import") (part "R-EU_R0603"))
    )
    (comp (ref "R130")
      (value "100kOhm/1%")
      (footprint "eagle-import:R0603")
      (fields (field (name "PARTNO") "RC0603FR-13100KL"))
      (libsource (lib "eagle-import") (part "R-EU_R0603"))
    )
    (comp (ref "VD36")
      (value "3.3V")
      (footprint "eagle-import:SOD80")
      (fields (field (name "PARTNO") "BZV55-C3V3"))
      (libsource (lib "eagle-import") (part "DIODE-ZENER-"))
    )
    (comp (ref "VD37")
      (value "3.3V")
      (footprint "eagle-import:SOD80")
      (fields (field (name "PARTNO") "BZV55-C3V3"))
      (libsource (lib "eagle-import") (part "DIODE-ZENER-"))
    )
    (comp (ref "VD38")
      (value "3.3V")
      (footprint "eagle-import:SOD80")
      (fields (field (name "PARTNO") "BZV55-C3V3"))
      (libsource (lib "eagle-import") (part "DIODE-ZENER-"))
    )
    (comp (ref "VD39")
      (value "3.3V")
      (footprint "eagle-import:SOD80")
      (fields (field (name "PARTNO") "BZV55-C3V3"))
      (libsource (lib "eagle-import") (part "DIODE-ZENER-"))
    )
    (comp (ref "VD40")
      (value "3.3V")
      (footprint "eagle-import:SOD80")
      (fields (field (name "PARTNO") "BZV55-C3V3"))
      (libsource (lib "eagle-import") (part "DIODE-ZENER-"))
    )
    (comp (ref "VD41")
      (value "3.3V")
      (footprint "eagle-import:SOD80")
      (fields (field (name "PARTNO") "BZV55-C3V3"))
      (libsource (lib "eagle-import") (part "DIODE-ZENER-"))
    )
    (comp (ref "VD42")
      (value "3.3V")
      (footprint "eagle-import:SOD80")
      (fields (field (name "PARTNO") "BZV55-C3V3"))
      (libsource (lib "eagle-import") (part "DIODE-ZENER-"))
    )
    (comp (ref "VD43")
      (value "3.3V")
      (footprint "eagle-import:SOD80")
      (fields (field (name "PARTNO") "BZV55-C3V3"))
      (libsource (lib "eagle-import") (part "DIODE-ZENER-"))
    )
    (comp (ref "VD44")
      (value "3.3V")
      (footprint "eagle-import:SOD80")
      (fields (field (name "PARTNO") "BZV55-C3V3"))
      (libsource (lib "eagle-import") (part "DIODE-ZENER-"))
    )
    (comp (ref "VD45")
      (value "3.3V")
      (footprint "eagle-import:SOD80")
      (fields (field (name "PARTNO") "BZV55-C3V3"))
      (libsource (lib "eagle-import") (part "DIODE-ZENER-"))
    )
    (comp (ref "VD46")
      (value "3.3V")
      (footprint "eagle-import:SOD80")
      (fields (field (name "PARTNO") "BZV55-C3V3"))
      (libsource (lib "eagle-import") (part "DIODE-ZENER-"))
    )
    (comp (ref "VD47")
      (value "3.3V")
      (footprint "eagle-import:SOD80")
      (fields (field (name "PARTNO") "BZV55-C3V3"))
      (libsource (lib "eagle-import") (part "DIODE-ZENER-"))
    )
    (comp (ref "VD48")
      (value "SMBJ24CA")
      (footprint "eagle-import:SMB-BIDIR")
      (libsource (lib "eagle-import") (part "DIODE-TVS-BIDIR-SMB"))
    )
    (comp (ref "VD49")
      (value "SMBJ24CA")
      (footprint "eagle-import:SMB-BIDIR")
      (libsource (lib "eagle-import") (part "DIODE-TVS-BIDIR-SMB"))
    )
    (comp (ref "VD50")
      (value "3.3V")
      (footprint "eagle-import:SOD80")
      (fields (field (name "PARTNO") "BZV55-C3V3"))
      (libsource (lib "eagle-import") (part "DIODE-ZENER-"))
    )
    (comp (ref "VD51")
      (value "3.3V")
      (footprint "eagle-import:SOD80")
      (fields (field (name "PARTNO") "BZV55-C3V3"))
      (libsource (lib "eagle-import") (part "DIODE-ZENER-"))
    )
    (comp (ref "VD52")
      (value "3.3V")
      (footprint "eagle-import:SOD80")
      (fields (field (name "PARTNO") "BZV55-C3V3"))
      (libsource (lib "eagle-import") (part "DIODE-ZENER-"))
    )
    (comp (ref "XP5")
      (value "MOLEX-90130-08")
      (footprint "eagle-import:MOLEX-90130-08")
      (fields (field (name "LABEL") "FREQUENCY") (field (name "PARTNO") "90130-1208"))
      (libsource (lib "eagle-import") (part "MOLEX-90130-08"))
    )
    (comp (ref "Z38")
      (value "NFE31PT")
      (footprint "eagle-import:NFE31")
      (fields (field (name "PARTNO") "NFE31PT152Z1E9"))
      (libsource (lib "eagle-import") (part "NFE31PT"))
    )
    (comp (ref "Z39")
      (value "NFE31PT")
      (footprint "eagle-import:NFE31")
      (fields (field (name "PARTNO") "NFE31PT152Z1E9"))
      (libsource (lib "eagle-import") (part "NFE31PT"))
    )
    (comp (ref "Z40")
      (value "NFE31PT")
      (footprint "eagle-import:NFE31")
      (fields (field (name "PARTNO") "NFE31PT152Z1E9"))
      (libsource (lib "eagle-import") (part "NFE31PT"))
    )
    (comp (ref "C87")
      (value "0.1uF")
      (footprint "eagle-import:C0603")
      (fields (field (name "PARTNO") "C0603C104K5RACTU"))
      (libsource (lib "eagle-import") (part "C-EUC0603"))
    )
    (comp (ref "C88")
      (value "0.1uF")
      (footprint "eagle-import:C0603")
      (fields (field (name "PARTNO") "C0603C104K5RACTU"))
      (libsource (lib "eagle-import") (part "C-EUC0603"))
    )
    (comp (ref "C89")
      (value "0.1uF")
      (footprint "eagle-import:C0603")
      (fields (field (name "PARTNO") "C0603C104K5RACTU"))
      (libsource (lib "eagle-import") (part "C-EUC0603"))
    )
    (comp (ref "C90")
      (value "0.1uF")
      (footprint "eagle-import:C0603")
      (fields (field (name "PARTNO") "C0603C104K5RACTU"))
      (libsource (lib "eagle-import") (part "C-EUC0603"))
    )
    (comp (ref "C91")
      (value "0.1uF")
      (footprint "eagle-import:C0603")
      (fields (field (name "PARTNO") "C0603C104K5RACTU"))
      (libsource (lib "eagle-import") (part "C-EUC0603"))
    )
    (comp (ref "C92")
      (value "0.1uF")
      (footprint "eagle-import:C0603")
      (fields (field (name "PARTNO") "C0603C104K5RACTU"))
      (libsource (lib "eagle-import") (part "C-EUC0603"))
    )
    (comp (ref "C93")
      (value "0.1uF")
      (footprint "eagle-import:C0603")
      (fields (field (name "PARTNO") "C0603C104K5RACTU"))
      (libsource (lib "eagle-import") (part "C-EUC0603"))
    )
    (comp (ref "C94")
      (value "0.1uF")
      (footprint "eagle-import:C0603")
      (fields (field (name "PARTNO") "C0603C104K5RACTU"))
      (libsource (lib "eagle-import") (part "C-EUC0603"))
    )
    (comp (ref "C95")
      (value "0.1uF")
      (footprint "eagle-import:C0603")
      (fields (field (name "PARTNO") "C0603C104K5RACTU"))
      (libsource (lib "eagle-import") (part "C-EUC0603"))
    )
    (comp (ref "C96")
      (value "0.1uF")
      (footprint "eagle-import:C0603")
      (fields (field (name "PARTNO") "C0603C104K5RACTU"))
      (libsource (lib "eagle-import") (part "C-EUC0603"))
    )
    (comp (ref "C97")
      (value "0.1uF")
      (footprint "eagle-import:C0603")
      (fields (field (name "PARTNO") "C0603C104K5RACTU"))
      (libsource (lib "eagle-import") (part "C-EUC0603"))
    )
    (comp (ref "C98")
      (value "0.1uF")
      (footprint "eagle-import:C0603")
      (fields (field (name "PARTNO") "C0603C104K5RACTU"))
      (libsource (lib "eagle-import") (part "C-EUC0603"))
    )
    (comp (ref "C99")
      (value "0.1uF")
      (footprint "eagle-import:C0603")
      (fields (field (name "PARTNO") "C0603C104K5RACTU"))
      (libsource (lib "eagle-import") (part "C-EUC0603"))
    )
    (comp (ref "C100")
      (value "0.1uF")
      (footprint "eagle-import:C0603")
      (fields (field (name "PARTNO") "C0603C104K5RACTU"))
      (libsource (lib "eagle-import") (part "C-EUC0603"))
    )
    (comp (ref "C101")
      (value "0.1uF")
      (footprint "eagle-import:C0603")
      (fields (field (name "PARTNO") "C0603C104K5RACTU"))
      (libsource (lib "eagle-import") (part "C-EUC0603"))
    )
    (comp (ref "C102")
      (value "0.1uF")
      (footprint "eagle-import:C0603")
      (fields (field (name "PARTNO") "C0603C104K5RACTU"))
      (libsource (lib "eagle-import") (part "C-EUC0603"))
    )
    (comp (ref "C103")
      (value "0.1uF")
      (footprint "eagle-import:C0603")
      (fields (field (name "PARTNO") "C0603C104K5RACTU"))
      (libsource (lib "eagle-import") (part "C-EUC0603"))
    )
    (comp (ref "C104")
      (value "0.1uF")
      (footprint "eagle-import:C0603")
      (fields (field (name "PARTNO") "C0603C104K5RACTU"))
      (libsource (lib "eagle-import") (part "C-EUC0603"))
    )
    (comp (ref "D6")
      (value "TCMT4100")
      (footprint "eagle-import:SO16")
      (fields (field (name "PARTNO") "TCMT4100"))
      (libsource (lib "eagle-import") (part "TCMT4100"))
    )
    (comp (ref "D7")
      (value "TCMT4100")
      (footprint "eagle-import:SO16")
      (fields (field (name "PARTNO") "TCMT4100"))
      (libsource (lib "eagle-import") (part "TCMT4100"))
    )
    (comp (ref "D8")
      (value "TCMT4100")
      (footprint "eagle-import:SO16")
      (fields (field (name "PARTNO") "TCMT4100"))
      (libsource (lib "eagle-import") (part "TCMT4100"))
    )
    (comp (ref "D9")
      (value "TCMT4100")
      (footprint "eagle-import:SO16")
      (fields (field (name "PARTNO") "TCMT4100"))
      (libsource (lib "eagle-import") (part "TCMT4100"))
    )
    (comp (ref "DD6")
      (value "74HC165D")
      (footprint "eagle-import:SO16")
      (fields (field (name "PARTNO") "IN74HC165AD"))
      (libsource (lib "eagle-import") (part "74165DHC"))
    )
    (comp (ref "DD7")
      (value "74HC165D")
      (footprint "eagle-import:SO16")
      (fields (field (name "PARTNO") "IN74HC165AD"))
      (libsource (lib "eagle-import") (part "74165DHC"))
    )
    (comp (ref "R189")
      (value "4.7kOhm/5%")
      (footprint "eagle-import:R1206")
      (fields (field (name "PARTNO") "RC1206JR-074K7L"))
      (libsource (lib "eagle-import") (part "R-EU_R1206"))
    )
    (comp (ref "R190")
      (value "4.7kOhm/5%")
      (footprint "eagle-import:R1206")
      (fields (field (name "PARTNO") "RC1206JR-074K7L"))
      (libsource (lib "eagle-import") (part "R-EU_R1206"))
    )
    (comp (ref "R191")
      (value "4.7kOhm/5%")
      (footprint "eagle-import:R1206")
      (fields (field (name "PARTNO") "RC1206JR-074K7L"))
      (libsource (lib "eagle-import") (part "R-EU_R1206"))
    )
    (comp (ref "R192")
      (value "4.7kOhm/5%")
      (footprint "eagle-import:R1206")
      (fields (field (name "PARTNO") "RC1206JR-074K7L"))
      (libsource (lib "eagle-import") (part "R-EU_R1206"))
    )
    (comp (ref "R193")
      (value "4.7kOhm/5%")
      (footprint "eagle-import:R1206")
      (fields (field (name "PARTNO") "RC1206JR-074K7L"))
      (libsource (lib "eagle-import") (part "R-EU_R1206"))
    )
    (comp (ref "R194")
      (value "4.7kOhm/5%")
      (footprint "eagle-import:R1206")
      (fields (field (name "PARTNO") "RC1206JR-074K7L"))
      (libsource (lib "eagle-import") (part "R-EU_R1206"))
    )
    (comp (ref "R195")
      (value "4.7kOhm/5%")
      (footprint "eagle-import:R1206")
      (fields (field (name "PARTNO") "RC1206JR-074K7L"))
      (libsource (lib "eagle-import") (part "R-EU_R1206"))
    )
    (comp (ref "R196")
      (value "4.7kOhm/5%")
      (footprint "eagle-import:R1206")
      (fields (field (name "PARTNO") "RC1206JR-074K7L"))
      (libsource (lib "eagle-import") (part "R-EU_R1206"))
    )
    (comp (ref "R197")
      (value "4.7kOhm/5%")
      (footprint "eagle-import:R1206")
      (fields (field (name "PARTNO") "RC1206JR-074K7L"))
      (libsource (lib "eagle-import") (part "R-EU_R1206"))
    )
    (comp (ref "R198")
      (value "4.7kOhm/5%")
      (footprint "eagle-import:R1206")
      (fields (field (name "PARTNO") "RC1206JR-074K7L"))
      (libsource (lib "eagle-import") (part "R-EU_R1206"))
    )
    (comp (ref "R199")
      (value "4.7kOhm/5%")
      (footprint "eagle-import:R1206")
      (fields (field (name "PARTNO") "RC1206JR-074K7L"))
      (libsource (lib "eagle-import") (part "R-EU_R1206"))
    )
    (comp (ref "R200")
      (value "4.7kOhm/5%")
      (footprint "eagle-import:R1206")
      (fields (field (name "PARTNO") "RC1206JR-074K7L"))
      (libsource (lib "eagle-import") (part "R-EU_R1206"))
    )
    (comp (ref "R201")
      (value "4.7kOhm/5%")
      (footprint "eagle-import:R1206")
      (fields (field (name "PARTNO") "RC1206JR-074K7L"))
      (libsource (lib "eagle-import") (part "R-EU_R1206"))
    )
    (comp (ref "R202")
      (value "4.7kOhm/5%")
      (footprint "eagle-import:R1206")
      (fields (field (name "PARTNO") "RC1206JR-074K7L"))
      (libsource (lib "eagle-import") (part "R-EU_R1206"))
    )
    (comp (ref "R203")
      (value "4.7kOhm/5%")
      (footprint "eagle-import:R1206")
      (fields (field (name "PARTNO") "RC1206JR-074K7L"))
      (libsource (lib "eagle-import") (part "R-EU_R1206"))
    )
    (comp (ref "R204")
      (value "4.7kOhm/5%")
      (footprint "eagle-import:R1206")
      (fields (field (name "PARTNO") "RC1206JR-074K7L"))
      (libsource (lib "eagle-import") (part "R-EU_R1206"))
    )
    (comp (ref "R205")
      (value "1kOhm/5%")
      (footprint "eagle-import:R2512")
      (fields (field (name "PARTNO") "RC2512JK-071KL"))
      (libsource (lib "eagle-import") (part "R-EU_R2512"))
    )
    (comp (ref "R206")
      (value "1kOhm/5%")
      (footprint "eagle-import:R2512")
      (fields (field (name "PARTNO") "RC2512JK-071KL"))
      (libsource (lib "eagle-import") (part "R-EU_R2512"))
    )
    (comp (ref "R207")
      (value "1kOhm/5%")
      (footprint "eagle-import:R2512")
      (fields (field (name "PARTNO") "RC2512JK-071KL"))
      (libsource (lib "eagle-import") (part "R-EU_R2512"))
    )
    (comp (ref "R208")
      (value "1kOhm/5%")
      (footprint "eagle-import:R2512")
      (fields (field (name "PARTNO") "RC2512JK-071KL"))
      (libsource (lib "eagle-import") (part "R-EU_R2512"))
    )
    (comp (ref "R209")
      (value "1kOhm/5%")
      (footprint "eagle-import:R2512")
      (fields (field (name "PARTNO") "RC2512JK-071KL"))
      (libsource (lib "eagle-import") (part "R-EU_R2512"))
    )
    (comp (ref "R210")
      (value "1kOhm/5%")
      (footprint "eagle-import:R2512")
      (fields (field (name "PARTNO") "RC2512JK-071KL"))
      (libsource (lib "eagle-import") (part "R-EU_R2512"))
    )
    (comp (ref "R211")
      (value "1kOhm/5%")
      (footprint "eagle-import:R2512")
      (fields (field (name "PARTNO") "RC2512JK-071KL"))
      (libsource (lib "eagle-import") (part "R-EU_R2512"))
    )
    (comp (ref "R212")
      (value "1kOhm/5%")
      (footprint "eagle-import:R2512")
      (fields (field (name "PARTNO") "RC2512JK-071KL"))
      (libsource (lib "eagle-import") (part "R-EU_R2512"))
    )
    (comp (ref "R213")
      (value "1kOhm/5%")
      (footprint "eagle-import:R2512")
      (fields (field (name "PARTNO") "RC2512JK-071KL"))
      (libsource (lib "eagle-import") (part "R-EU_R2512"))
    )
    (comp (ref "R214")
      (value "1kOhm/5%")
      (footprint "eagle-import:R2512")
      (fields (field (name "PARTNO") "RC2512JK-071KL"))
      (libsource (lib "eagle-import") (part "R-EU_R2512"))
    )
    (comp (ref "R215")
      (value "1kOhm/5%")
      (footprint "eagle-import:R2512")
      (fields (field (name "PARTNO") "RC2512JK-071KL"))
      (libsource (lib "eagle-import") (part "R-EU_R2512"))
    )
    (comp (ref "R216")
      (value "1kOhm/5%")
      (footprint "eagle-import:R2512")
      (fields (field (name "PARTNO") "RC2512JK-071KL"))
      (libsource (lib "eagle-import") (part "R-EU_R2512"))
    )
    (comp (ref "R217")
      (value "1kOhm/5%")
      (footprint "eagle-import:R2512")
      (fields (field (name "PARTNO") "RC2512JK-071KL"))
      (libsource (lib "eagle-import") (part "R-EU_R2512"))
    )
    (comp (ref "R218")
      (value "1kOhm/5%")
      (footprint "eagle-import:R2512")
      (fields (field (name "PARTNO") "RC2512JK-071KL"))
      (libsource (lib "eagle-import") (part "R-EU_R2512"))
    )
    (comp (ref "R219")
      (value "1kOhm/5%")
      (footprint "eagle-import:R2512")
      (fields (field (name "PARTNO") "RC2512JK-071KL"))
      (libsource (lib "eagle-import") (part "R-EU_R2512"))
    )
    (comp (ref "R220")
      (value "1kOhm/5%")
      (footprint "eagle-import:R2512")
      (fields (field (name "PARTNO") "RC2512JK-071KL"))
      (libsource (lib "eagle-import") (part "R-EU_R2512"))
    )
    (comp (ref "R221")
      (value "10kOhm/1%")
      (footprint "eagle-import:R0603")
      (fields (field (name "PARTNO") "RC0603FR-1010KL"))
      (libsource (lib "eagle-import") (part "R-EU_R0603"))
    )
    (comp (ref "R222")
      (value "10kOhm/1%")
      (footprint "eagle-import:R0603")
      (fields (field (name "PARTNO") "RC0603FR-1010KL"))
      (libsource (lib "eagle-import") (part "R-EU_R0603"))
    )
    (comp (ref "R223")
      (value "10kOhm/1%")
      (footprint "eagle-import:R0603")
      (fields (field (name "PARTNO") "RC0603FR-1010KL"))
      (libsource (lib "eagle-import") (part "R-EU_R0603"))
    )
    (comp (ref "R224")
      (value "10kOhm/1%")
      (footprint "eagle-import:R0603")
      (fields (field (name "PARTNO") "RC0603FR-1010KL"))
      (libsource (lib "eagle-import") (part "R-EU_R0603"))
    )
    (comp (ref "R225")
      (value "10kOhm/1%")
      (footprint "eagle-import:R0603")
      (fields (field (name "PARTNO") "RC0603FR-1010KL"))
      (libsource (lib "eagle-import") (part "R-EU_R0603"))
    )
    (comp (ref "R226")
      (value "10kOhm/1%")
      (footprint "eagle-import:R0603")
      (fields (field (name "PARTNO") "RC0603FR-1010KL"))
      (libsource (lib "eagle-import") (part "R-EU_R0603"))
    )
    (comp (ref "R227")
      (value "10kOhm/1%")
      (footprint "eagle-import:R0603")
      (fields (field (name "PARTNO") "RC0603FR-1010KL"))
      (libsource (lib "eagle-import") (part "R-EU_R0603"))
    )
    (comp (ref "R228")
      (value "10kOhm/1%")
      (footprint "eagle-import:R0603")
      (fields (field (name "PARTNO") "RC0603FR-1010KL"))
      (libsource (lib "eagle-import") (part "R-EU_R0603"))
    )
    (comp (ref "R229")
      (value "10kOhm/1%")
      (footprint "eagle-import:R0603")
      (fields (field (name "PARTNO") "RC0603FR-1010KL"))
      (libsource (lib "eagle-import") (part "R-EU_R0603"))
    )
    (comp (ref "R230")
      (value "10kOhm/1%")
      (footprint "eagle-import:R0603")
      (fields (field (name "PARTNO") "RC0603FR-1010KL"))
      (libsource (lib "eagle-import") (part "R-EU_R0603"))
    )
    (comp (ref "R231")
      (value "10kOhm/1%")
      (footprint "eagle-import:R0603")
      (fields (field (name "PARTNO") "RC0603FR-1010KL"))
      (libsource (lib "eagle-import") (part "R-EU_R0603"))
    )
    (comp (ref "R232")
      (value "10kOhm/1%")
      (footprint "eagle-import:R0603")
      (fields (field (name "PARTNO") "RC0603FR-1010KL"))
      (libsource (lib "eagle-import") (part "R-EU_R0603"))
    )
    (comp (ref "R233")
      (value "10kOhm/1%")
      (footprint "eagle-import:R0603")
      (fields (field (name "PARTNO") "RC0603FR-1010KL"))
      (libsource (lib "eagle-import") (part "R-EU_R0603"))
    )
    (comp (ref "R234")
      (value "10kOhm/1%")
      (footprint "eagle-import:R0603")
      (fields (field (name "PARTNO") "RC0603FR-1010KL"))
      (libsource (lib "eagle-import") (part "R-EU_R0603"))
    )
    (comp (ref "R235")
      (value "10kOhm/1%")
      (footprint "eagle-import:R0603")
      (fields (field (name "PARTNO") "RC0603FR-1010KL"))
      (libsource (lib "eagle-import") (part "R-EU_R0603"))
    )
    (comp (ref "R236")
      (value "10kOhm/1%")
      (footprint "eagle-import:R0603")
      (fields (field (name "PARTNO") "RC0603FR-1010KL"))
      (libsource (lib "eagle-import") (part "R-EU_R0603"))
    )
    (comp (ref "VD100")
      (value "SM6T200A")
      (footprint "eagle-import:SMB")
      (libsource (lib "eagle-import") (part "DIODE-TVS-UNIDIR-SMB"))
    )
    (comp (ref "VD101")
      (value "SM6T200A")
      (footprint "eagle-import:SMB")
      (libsource (lib "eagle-import") (part "DIODE-TVS-UNIDIR-SMB"))
    )
    (comp (ref "VD102")
      (value "SM6T200A")
      (footprint "eagle-import:SMB")
      (libsource (lib "eagle-import") (part "DIODE-TVS-UNIDIR-SMB"))
    )
    (comp (ref "VD103")
      (value "SM6T200A")
      (footprint "eagle-import:SMB")
      (libsource (lib "eagle-import") (part "DIODE-TVS-UNIDIR-SMB"))
    )
    (comp (ref "VD104")
      (value "SM6T200A")
      (footprint "eagle-import:SMB")
      (libsource (lib "eagle-import") (part "DIODE-TVS-UNIDIR-SMB"))
    )
    (comp (ref "VD105")
      (value "SM6T200A")
      (footprint "eagle-import:SMB")
      (libsource (lib "eagle-import") (part "DIODE-TVS-UNIDIR-SMB"))
    )
    (comp (ref "VD106")
      (value "SM6T200A")
      (footprint "eagle-import:SMB")
      (libsource (lib "eagle-import") (part "DIODE-TVS-UNIDIR-SMB"))
    )
    (comp (ref "VD107")
      (value "SM6T200A")
      (footprint "eagle-import:SMB")
      (libsource (lib "eagle-import") (part "DIODE-TVS-UNIDIR-SMB"))
    )
    (comp (ref "VD108")
      (value "SM6T200A")
      (footprint "eagle-import:SMB")
      (libsource (lib "eagle-import") (part "DIODE-TVS-UNIDIR-SMB"))
    )
    (comp (ref "VD109")
      (value "SM6T200A")
      (footprint "eagle-import:SMB")
      (libsource (lib "eagle-import") (part "DIODE-TVS-UNIDIR-SMB"))
    )
    (comp (ref "VD110")
      (value "SM6T200A")
      (footprint "eagle-import:SMB")
      (libsource (lib "eagle-import") (part "DIODE-TVS-UNIDIR-SMB"))
    )
    (comp (ref "VD111")
      (value "SM6T200A")
      (footprint "eagle-import:SMB")
      (libsource (lib "eagle-import") (part "DIODE-TVS-UNIDIR-SMB"))
    )
    (comp (ref "VD112")
      (value "SM6T200A")
      (footprint "eagle-import:SMB")
      (libsource (lib "eagle-import") (part "DIODE-TVS-UNIDIR-SMB"))
    )
    (comp (ref "VD113")
      (value "SM6T200A")
      (footprint "eagle-import:SMB")
      (libsource (lib "eagle-import") (part "DIODE-TVS-UNIDIR-SMB"))
    )
    (comp (ref "VD114")
      (value "SM6T200A")
      (footprint "eagle-import:SMB")
      (libsource (lib "eagle-import") (part "DIODE-TVS-UNIDIR-SMB"))
    )
    (comp (ref "VD115")
      (value "SM6T200A")
      (footprint "eagle-import:SMB")
      (libsource (lib "eagle-import") (part "DIODE-TVS-UNIDIR-SMB"))
    )
    (comp (ref "VD116")
      (value "400V")
      (footprint "eagle-import:SMA")
      (fields (field (name "PARTNO") "S1G-E3/61T"))
      (libsource (lib "eagle-import") (part "DIODE-STANDARD-SMA"))
    )
    (comp (ref "VD117")
      (value "400V")
      (footprint "eagle-import:SMA")
      (fields (field (name "PARTNO") "S1G-E3/61T"))
      (libsource (lib "eagle-import") (part "DIODE-STANDARD-SMA"))
    )
    (comp (ref "VD118")
      (value "400V")
      (footprint "eagle-import:SMA")
      (fields (field (name "PARTNO") "S1G-E3/61T"))
      (libsource (lib "eagle-import") (part "DIODE-STANDARD-SMA"))
    )
    (comp (ref "VD119")
      (value "400V")
      (footprint "eagle-import:SMA")
      (fields (field (name "PARTNO") "S1G-E3/61T"))
      (libsource (lib "eagle-import") (part "DIODE-STANDARD-SMA"))
    )
    (comp (ref "VD120")
      (value "400V")
      (footprint "eagle-import:SMA")
      (fields (field (name "PARTNO") "S1G-E3/61T"))
      (libsource (lib "eagle-import") (part "DIODE-STANDARD-SMA"))
    )
    (comp (ref "VD121")
      (value "400V")
      (footprint "eagle-import:SMA")
      (fields (field (name "PARTNO") "S1G-E3/61T"))
      (libsource (lib "eagle-import") (part "DIODE-STANDARD-SMA"))
    )
    (comp (ref "VD122")
      (value "400V")
      (footprint "eagle-import:SMA")
      (fields (field (name "PARTNO") "S1G-E3/61T"))
      (libsource (lib "eagle-import") (part "DIODE-STANDARD-SMA"))
    )
    (comp (ref "VD123")
      (value "400V")
      (footprint "eagle-import:SMA")
      (fields (field (name "PARTNO") "S1G-E3/61T"))
      (libsource (lib "eagle-import") (part "DIODE-STANDARD-SMA"))
    )
    (comp (ref "VD124")
      (value "400V")
      (footprint "eagle-import:SMA")
      (fields (field (name "PARTNO") "S1G-E3/61T"))
      (libsource (lib "eagle-import") (part "DIODE-STANDARD-SMA"))
    )
    (comp (ref "VD125")
      (value "400V")
      (footprint "eagle-import:SMA")
      (fields (field (name "PARTNO") "S1G-E3/61T"))
      (libsource (lib "eagle-import") (part "DIODE-STANDARD-SMA"))
    )
    (comp (ref "VD126")
      (value "400V")
      (footprint "eagle-import:SMA")
      (fields (field (name "PARTNO") "S1G-E3/61T"))
      (libsource (lib "eagle-import") (part "DIODE-STANDARD-SMA"))
    )
    (comp (ref "VD127")
      (value "400V")
      (footprint "eagle-import:SMA")
      (fields (field (name "PARTNO") "S1G-E3/61T"))
      (libsource (lib "eagle-import") (part "DIODE-STANDARD-SMA"))
    )
    (comp (ref "VD128")
      (value "400V")
      (footprint "eagle-import:SMA")
      (fields (field (name "PARTNO") "S1G-E3/61T"))
      (libsource (lib "eagle-import") (part "DIODE-STANDARD-SMA"))
    )
    (comp (ref "VD129")
      (value "400V")
      (footprint "eagle-import:SMA")
      (fields (field (name "PARTNO") "S1G-E3/61T"))
      (libsource (lib "eagle-import") (part "DIODE-STANDARD-SMA"))
    )
    (comp (ref "VD130")
      (value "400V")
      (footprint "eagle-import:SMA")
      (fields (field (name "PARTNO") "S1G-E3/61T"))
      (libsource (lib "eagle-import") (part "DIODE-STANDARD-SMA"))
    )
    (comp (ref "VD131")
      (value "400V")
      (footprint "eagle-import:SMA")
      (fields (field (name "PARTNO") "S1G-E3/61T"))
      (libsource (lib "eagle-import") (part "DIODE-STANDARD-SMA"))
    )
    (comp (ref "XP8")
      (value "MOLEX-90130-16")
      (footprint "eagle-import:MOLEX-90130-16")
      (fields (field (name "PARTNO") "90130-1216"))
      (libsource (lib "eagle-import") (part "MOLEX-90130-16"))
    )
    (comp (ref "C1")
      (value "0.1uF")
      (footprint "eagle-import:C0603")
      (fields (field (name "PARTNO") "C0603C104K5RACTU"))
      (libsource (lib "eagle-import") (part "C-EUC0603"))
    )
    (comp (ref "C2")
      (value "0.1uF")
      (footprint "eagle-import:C0603")
      (fields (field (name "PARTNO") "C0603C104K5RACTU"))
      (libsource (lib "eagle-import") (part "C-EUC0603"))
    )
    (comp (ref "C3")
      (value "22pF")
      (footprint "eagle-import:C0603")
      (fields (field (name "PARTNO") "C0603C220J5GACTU"))
      (libsource (lib "eagle-import") (part "C-EUC0603"))
    )
    (comp (ref "C4")
      (value "22pF")
      (footprint "eagle-import:C0603")
      (fields (field (name "PARTNO") "C0603C220J5GACTU"))
      (libsource (lib "eagle-import") (part "C-EUC0603"))
    )
    (comp (ref "C5")
      (value "10uF/10V")
      (footprint "eagle-import:A_3216-18W")
      (fields (field (name "PARTNO") "T491A106K010AT"))
      (libsource (lib "eagle-import") (part "CPOL-EUA/3216-18W"))
    )
    (comp (ref "C6")
      (value "0.1uF")
      (footprint "eagle-import:C0603")
      (fields (field (name "PARTNO") "C0603C104K5RACTU"))
      (libsource (lib "eagle-import") (part "C-EUC0603"))
    )
    (comp (ref "C7")
      (value "1uF/16V")
      (footprint "eagle-import:C0603")
      (fields (field (name "PARTNO") "C0603C105K4PACTU"))
      (libsource (lib "eagle-import") (part "C-EUC0603"))
    )
    (comp (ref "C8")
      (value "0.1uF")
      (footprint "eagle-import:C0603")
      (fields (field (name "PARTNO") "C0603C104K5RACTU"))
      (libsource (lib "eagle-import") (part "C-EUC0603"))
    )
    (comp (ref "C9")
      (value "0.1uF")
      (footprint "eagle-import:C0603")
      (fields (field (name "PARTNO") "C0603C104K5RACTU"))
      (libsource (lib "eagle-import") (part "C-EUC0603"))
    )
    (comp (ref "C10")
      (value "0.1uF")
      (footprint "eagle-import:C0603")
      (fields (field (name "PARTNO") "C0603C104K5RACTU"))
      (libsource (lib "eagle-import") (part "C-EUC0603"))
    )
    (comp (ref "C11")
      (value "0.1uF")
      (footprint "eagle-import:C0603")
      (fields (field (name "PARTNO") "C0603C104K5RACTU"))
      (libsource (lib "eagle-import") (part "C-EUC0603"))
    )
    (comp (ref "DD1")
      (value "STM32F103VDT6")
      (footprint "eagle-import:TQFP100")
      (libsource (lib "eagle-import") (part "STM32F103VDT6"))
    )
    (comp (ref "DD2")
      (value "IN24AA32AD")
      (footprint "eagle-import:SO08")
      (libsource (lib "eagle-import") (part "IN24DAA32A"))
    )
    (comp (ref "L1")
      (value "EXC3BP")
      (footprint "eagle-import:L0603")
      (fields (field (name "PARTNO") "EXC3BP121H"))
      (libsource (lib "eagle-import") (part "EXC3BP"))
    )
    (comp (ref "R1")
      (value "10kOhm/1%")
      (footprint "eagle-import:R0603")
      (fields (field (name "PARTNO") "RC0603FR-1010KL"))
      (libsource (lib "eagle-import") (part "R-EU_R0603"))
    )
    (comp (ref "R2")
      (value "10kOhm/1%")
      (footprint "eagle-import:R0603")
      (fields (field (name "PARTNO") "RC0603FR-1010KL"))
      (libsource (lib "eagle-import") (part "R-EU_R0603"))
    )
    (comp (ref "R3")
      (value "10kOhm/1%")
      (footprint "eagle-import:R0603")
      (fields (field (name "PARTNO") "RC0603FR-1010KL"))
      (libsource (lib "eagle-import") (part "R-EU_R0603"))
    )
    (comp (ref "R4")
      (value "10kOhm/1%")
      (footprint "eagle-import:R0603")
      (fields (field (name "PARTNO") "RC0603FR-1010KL"))
      (libsource (lib "eagle-import") (part "R-EU_R0603"))
    )
    (comp (ref "R5")
      (value "10kOhm/1%")
      (footprint "eagle-import:R0603")
      (fields (field (name "PARTNO") "RC0603FR-1010KL"))
      (libsource (lib "eagle-import") (part "R-EU_R0603"))
    )
    (comp (ref "R6")
      (value "10kOhm/1%")
      (footprint "eagle-import:R0603")
      (fields (field (name "PARTNO") "RC0603FR-1010KL"))
      (libsource (lib "eagle-import") (part "R-EU_R0603"))
    )
    (comp (ref "R7")
      (value "10kOhm/1%")
      (footprint "eagle-import:R0603")
      (fields (field (name "PARTNO") "RC0603FR-1010KL"))
      (libsource (lib "eagle-import") (part "R-EU_R0603"))
    )
    (comp (ref "R8")
      (value "10kOhm/1%")
      (footprint "eagle-import:R0603")
      (fields (field (name "PARTNO") "RC0603FR-1010KL"))
      (libsource (lib "eagle-import") (part "R-EU_R0603"))
    )
    (comp (ref "R9")
      (value "10kOhm/1%")
      (footprint "eagle-import:R0603")
      (fields (field (name "PARTNO") "RC0603FR-1010KL"))
      (libsource (lib "eagle-import") (part "R-EU_R0603"))
    )
    (comp (ref "R10")
      (value "0Ohm")
      (footprint "eagle-import:R0805")
      (fields (field (name "PARTNO") "ERJ6GEY0R00V"))
      (libsource (lib "eagle-import") (part "R-EU_R0805"))
    )
    (comp (ref "R11")
      (value "100kOhm/1%")
      (footprint "eagle-import:R0603")
      (fields (field (name "PARTNO") "RC0603FR-13100KL"))
      (libsource (lib "eagle-import") (part "R-EU_R0603"))
    )
    (comp (ref "R12")
      (value "100kOhm/1%")
      (footprint "eagle-import:R0603")
      (fields (field (name "PARTNO") "RC0603FR-13100KL"))
      (libsource (lib "eagle-import") (part "R-EU_R0603"))
    )
    (comp (ref "R13")
      (value "330Ohm/5%")
      (footprint "eagle-import:R0603")
      (fields (field (name "PARTNO") "ERJ3GEYJ331V"))
      (libsource (lib "eagle-import") (part "R-EU_R0603"))
    )
    (comp (ref "R14")
      (value "330Ohm/5%")
      (footprint "eagle-import:R0603")
      (fields (field (name "PARTNO") "ERJ3GEYJ331V"))
      (libsource (lib "eagle-import") (part "R-EU_R0603"))
    )
    (comp (ref "R15")
      (value "1kOhm/5%")
      (footprint "eagle-import:R0805")
      (fields (field (name "PARTNO") "ERJ6GEYJ102V"))
      (libsource (lib "eagle-import") (part "R-EU_R0805"))
    )
    (comp (ref "R16")
      (value "100Ohm/5%")
      (footprint "eagle-import:R0603")
      (fields (field (name "PARTNO") "ERJ3GEYJ101V"))
      (libsource (lib "eagle-import") (part "R-EU_R0603"))
    )
    (comp (ref "R17")
      (value "100Ohm/5%")
      (footprint "eagle-import:R0603")
      (fields (field (name "PARTNO") "ERJ3GEYJ101V"))
      (libsource (lib "eagle-import") (part "R-EU_R0603"))
    )
    (comp (ref "R18")
      (value "100Ohm/5%")
      (footprint "eagle-import:R0603")
      (fields (field (name "PARTNO") "ERJ3GEYJ101V"))
      (libsource (lib "eagle-import") (part "R-EU_R0603"))
    )
    (comp (ref "R19")
      (value "100Ohm/5%")
      (footprint "eagle-import:R0603")
      (fields (field (name "PARTNO") "ERJ3GEYJ101V"))
      (libsource (lib "eagle-import") (part "R-EU_R0603"))
    )
    (comp (ref "R20")
      (value "330Ohm/5%")
      (footprint "eagle-import:R0603")
      (fields (field (name "PARTNO") "ERJ3GEYJ331V"))
      (libsource (lib "eagle-import") (part "R-EU_R0603"))
    )
    (comp (ref "R21")
      (value "100Ohm/5%")
      (footprint "eagle-import:R0603")
      (fields (field (name "PARTNO") "ERJ3GEYJ101V"))
      (libsource (lib "eagle-import") (part "R-EU_R0603"))
    )
    (comp (ref "R22")
      (value "100Ohm/5%")
      (footprint "eagle-import:R0603")
      (fields (field (name "PARTNO") "ERJ3GEYJ101V"))
      (libsource (lib "eagle-import") (part "R-EU_R0603"))
    )
    (comp (ref "R23")
      (value "100Ohm/5%")
      (footprint "eagle-import:R0603")
      (fields (field (name "PARTNO") "ERJ3GEYJ101V"))
      (libsource (lib "eagle-import") (part "R-EU_R0603"))
    )
    (comp (ref "R24")
      (value "100Ohm/5%")
      (footprint "eagle-import:R0603")
      (fields (field (name "PARTNO") "ERJ3GEYJ101V"))
      (libsource (lib "eagle-import") (part "R-EU_R0603"))
    )
    (comp (ref "R25")
      (value "1kOhm/5%")
      (footprint "eagle-import:R0805")
      (fields (field (name "PARTNO") "ERJ6GEYJ102V"))
      (libsource (lib "eagle-import") (part "R-EU_R0805"))
    )
    (comp (ref "SB1")
      (value "RESET")
      (footprint "eagle-import:B3S-10XX")
      (fields (field (name "PARTNO") "4-1437565-2"))
      (libsource (lib "eagle-import") (part "4-1437565-2"))
    )
    (comp (ref "VD1")
      (value "RED")
      (footprint "eagle-import:LED-0805")
      (fields (field (name "PARTNO") "KPHCM-2012EC-T"))
      (libsource (lib "eagle-import") (part "LED0805"))
    )
    (comp (ref "VD2")
      (value "RED")
      (footprint "eagle-import:LED-0805")
      (fields (field (name "PARTNO") "KPHCM-2012EC-T"))
      (libsource (lib "eagle-import") (part "LED0805"))
    )
    (comp (ref "VD3")
      (value "GREEN")
      (footprint "eagle-import:LED-0805")
      (fields (field (name "PARTNO") "KPHCM-2012SGC-T"))
      (libsource (lib "eagle-import") (part "LED0805"))
    )
    (comp (ref "XP1")
      (value "PLD_2X10-SHROUDED")
      (footprint "eagle-import:PLD_2X10_SHROUDED")
      (fields (field (name "LABEL") "JTAG") (field (name "PARTNO") "MC9A12-2034"))
      (libsource (lib "eagle-import") (part "PLD_2X10-SHROUDED"))
    )
    (comp (ref "XP2")
      (value "PLD_1X3")
      (footprint "eagle-import:PLD_1X03")
      (fields (field (name "LABEL") "BOOT_1") (field (name "PARTNO") "825433-3"))
      (libsource (lib "eagle-import") (part "PLD_1X03"))
    )
    (comp (ref "XP3")
      (value "PLD_1X3")
      (footprint "eagle-import:PLD_1X03")
      (fields (field (name "LABEL") "BOOT_0") (field (name "PARTNO") "825433-3"))
      (libsource (lib "eagle-import") (part "PLD_1X03"))
    )
    (comp (ref "Z1")
      (value "NFE31PT")
      (footprint "eagle-import:NFE31")
      (fields (field (name "PARTNO") "NFE31PT152Z1E9"))
      (libsource (lib "eagle-import") (part "NFE31PT"))
    )
    (comp (ref "Z2")
      (value "NFE31PT")
      (footprint "eagle-import:NFE31")
      (fields (field (name "PARTNO") "NFE31PT152Z1E9"))
      (libsource (lib "eagle-import") (part "NFE31PT"))
    )
    (comp (ref "Z3")
      (value "NFE31PT")
      (footprint "eagle-import:NFE31")
      (fields (field (name "PARTNO") "NFE31PT152Z1E9"))
      (libsource (lib "eagle-import") (part "NFE31PT"))
    )
    (comp (ref "Z4")
      (value "NFE31PT")
      (footprint "eagle-import:NFE31")
      (fields (field (name "PARTNO") "NFE31PT152Z1E9"))
      (libsource (lib "eagle-import") (part "NFE31PT"))
    )
    (comp (ref "Z5")
      (value "NFE31PT")
      (footprint "eagle-import:NFE31")
      (fields (field (name "PARTNO") "NFE31PT152Z1E9"))
      (libsource (lib "eagle-import") (part "NFE31PT"))
    )
    (comp (ref "Z6")
      (value "NFE31PT")
      (footprint "eagle-import:NFE31")
      (fields (field (name "PARTNO") "NFE31PT152Z1E9"))
      (libsource (lib "eagle-import") (part "NFE31PT"))
    )
    (comp (ref "Z7")
      (value "NFE31PT")
      (footprint "eagle-import:NFE31")
      (fields (field (name "PARTNO") "NFE31PT152Z1E9"))
      (libsource (lib "eagle-import") (part "NFE31PT"))
    )
    (comp (ref "Z8")
      (value "NFE31PT")
      (footprint "eagle-import:NFE31")
      (fields (field (name "PARTNO") "NFE31PT152Z1E9"))
      (libsource (lib "eagle-import") (part "NFE31PT"))
    )
    (comp (ref "Z9")
      (value "NFE31PT")
      (footprint "eagle-import:NFE31")
      (fields (field (name "PARTNO") "NFE31PT152Z1E9"))
      (libsource (lib "eagle-import") (part "NFE31PT"))
    )
    (comp (ref "Z10")
      (value "NFE31PT")
      (footprint "eagle-import:NFE31")
      (fields (field (name "PARTNO") "NFE31PT152Z1E9"))
      (libsource (lib "eagle-import") (part "NFE31PT"))
    )
    (comp (ref "Z11")
      (value "NFE31PT")
      (footprint "eagle-import:NFE31")
      (fields (field (name "PARTNO") "NFE31PT152Z1E9"))
      (libsource (lib "eagle-import") (part "NFE31PT"))
    )
    (comp (ref "Z12")
      (value "NFE31PT")
      (footprint "eagle-import:NFE31")
      (fields (field (name "PARTNO") "NFE31PT152Z1E9"))
      (libsource (lib "eagle-import") (part "NFE31PT"))
    )
    (comp (ref "Z13")
      (value "NFE31PT")
      (footprint "eagle-import:NFE31")
      (fields (field (name "PARTNO") "NFE31PT152Z1E9"))
      (libsource (lib "eagle-import") (part "NFE31PT"))
    )
    (comp (ref "Z14")
      (value "NFE31PT")
      (footprint "eagle-import:NFE31")
      (fields (field (name "PARTNO") "NFE31PT152Z1E9"))
      (libsource (lib "eagle-import") (part "NFE31PT"))
    )
    (comp (ref "Z15")
      (value "NFE31PT")
      (footprint "eagle-import:NFE31")
      (fields (field (name "PARTNO") "NFE31PT152Z1E9"))
      (libsource (lib "eagle-import") (part "NFE31PT"))
    )
    (comp (ref "Z16")
      (value "NFE31PT")
      (footprint "eagle-import:NFE31")
      (fields (field (name "PARTNO") "NFE31PT152Z1E9"))
      (libsource (lib "eagle-import") (part "NFE31PT"))
    )
    (comp (ref "Z17")
      (value "NFE31PT")
      (footprint "eagle-import:NFE31")
      (fields (field (name "PARTNO") "NFE31PT152Z1E9"))
      (libsource (lib "eagle-import") (part "NFE31PT"))
    )
    (comp (ref "Z18")
      (value "NFE31PT")
      (footprint "eagle-import:NFE31")
      (fields (field (name "PARTNO") "NFE31PT152Z1E9"))
      (libsource (lib "eagle-import") (part "NFE31PT"))
    )
    (comp (ref "Z19")
      (value "NFE31PT")
      (footprint "eagle-import:NFE31")
      (fields (field (name "PARTNO") "NFE31PT152Z1E9"))
      (libsource (lib "eagle-import") (part "NFE31PT"))
    )
    (comp (ref "Z20")
      (value "NFE31PT")
      (footprint "eagle-import:NFE31")
      (fields (field (name "PARTNO") "NFE31PT152Z1E9"))
      (libsource (lib "eagle-import") (part "NFE31PT"))
    )
    (comp (ref "Z21")
      (value "NFE31PT")
      (footprint "eagle-import:NFE31")
      (fields (field (name "PARTNO") "NFE31PT152Z1E9"))
      (libsource (lib "eagle-import") (part "NFE31PT"))
    )
    (comp (ref "ZQ1")
      (value "4MHz")
      (footprint "eagle-import:HC49U-V")
      (fields (field (name "PARTNO") "CA-4.000-18-3050-X"))
      (libsource (lib "eagle-import") (part "CRYSTALHC49UV"))
    )
    (comp (ref "C123")
      (value "0.1uF")
      (footprint "eagle-import:C0603")
      (fields (field (name "PARTNO") "C0603C104K5RACTU"))
      (libsource (lib "eagle-import") (part "C-EUC0603"))
    )
    (comp (ref "C124")
      (value "0.1uF")
      (footprint "eagle-import:C0603")
      (fields (field (name "PARTNO") "C0603C104K5RACTU"))
      (libsource (lib "eagle-import") (part "C-EUC0603"))
    )
    (comp (ref "C125")
      (value "0.1uF")
      (footprint "eagle-import:C0603")
      (fields (field (name "PARTNO") "C0603C104K5RACTU"))
      (libsource (lib "eagle-import") (part "C-EUC0603"))
    )
    (comp (ref "C126")
      (value "0.1uF")
      (footprint "eagle-import:C0603")
      (fields (field (name "PARTNO") "C0603C104K5RACTU"))
      (libsource (lib "eagle-import") (part "C-EUC0603"))
    )
    (comp (ref "C127")
      (value "0.1uF")
      (footprint "eagle-import:C0603")
      (fields (field (name "PARTNO") "C0603C104K5RACTU"))
      (libsource (lib "eagle-import") (part "C-EUC0603"))
    )
    (comp (ref "C128")
      (value "0.1uF")
      (footprint "eagle-import:C0603")
      (fields (field (name "PARTNO") "C0603C104K5RACTU"))
      (libsource (lib "eagle-import") (part "C-EUC0603"))
    )
    (comp (ref "C129")
      (value "0.1uF")
      (footprint "eagle-import:C0603")
      (fields (field (name "PARTNO") "C0603C104K5RACTU"))
      (libsource (lib "eagle-import") (part "C-EUC0603"))
    )
    (comp (ref "C130")
      (value "0.1uF")
      (footprint "eagle-import:C0603")
      (fields (field (name "PARTNO") "C0603C104K5RACTU"))
      (libsource (lib "eagle-import") (part "C-EUC0603"))
    )
    (comp (ref "C131")
      (value "0.1uF")
      (footprint "eagle-import:C0603")
      (fields (field (name "PARTNO") "C0603C104K5RACTU"))
      (libsource (lib "eagle-import") (part "C-EUC0603"))
    )
    (comp (ref "C132")
      (value "0.1uF")
      (footprint "eagle-import:C0603")
      (fields (field (name "PARTNO") "C0603C104K5RACTU"))
      (libsource (lib "eagle-import") (part "C-EUC0603"))
    )
    (comp (ref "C133")
      (value "0.1uF")
      (footprint "eagle-import:C0603")
      (fields (field (name "PARTNO") "C0603C104K5RACTU"))
      (libsource (lib "eagle-import") (part "C-EUC0603"))
    )
    (comp (ref "C134")
      (value "0.1uF")
      (footprint "eagle-import:C0603")
      (fields (field (name "PARTNO") "C0603C104K5RACTU"))
      (libsource (lib "eagle-import") (part "C-EUC0603"))
    )
    (comp (ref "C135")
      (value "0.1uF")
      (footprint "eagle-import:C0603")
      (fields (field (name "PARTNO") "C0603C104K5RACTU"))
      (libsource (lib "eagle-import") (part "C-EUC0603"))
    )
    (comp (ref "C136")
      (value "0.1uF")
      (footprint "eagle-import:C0603")
      (fields (field (name "PARTNO") "C0603C104K5RACTU"))
      (libsource (lib "eagle-import") (part "C-EUC0603"))
    )
    (comp (ref "C137")
      (value "0.1uF")
      (footprint "eagle-import:C0603")
      (fields (field (name "PARTNO") "C0603C104K5RACTU"))
      (libsource (lib "eagle-import") (part "C-EUC0603"))
    )
    (comp (ref "C138")
      (value "0.1uF")
      (footprint "eagle-import:C0603")
      (fields (field (name "PARTNO") "C0603C104K5RACTU"))
      (libsource (lib "eagle-import") (part "C-EUC0603"))
    )
    (comp (ref "C139")
      (value "0.1uF")
      (footprint "eagle-import:C0603")
      (fields (field (name "PARTNO") "C0603C104K5RACTU"))
      (libsource (lib "eagle-import") (part "C-EUC0603"))
    )
    (comp (ref "C140")
      (value "0.1uF")
      (footprint "eagle-import:C0603")
      (fields (field (name "PARTNO") "C0603C104K5RACTU"))
      (libsource (lib "eagle-import") (part "C-EUC0603"))
    )
    (comp (ref "D14")
      (value "TCMT4100")
      (footprint "eagle-import:SO16")
      (fields (field (name "PARTNO") "TCMT4100"))
      (libsource (lib "eagle-import") (part "TCMT4100"))
    )
    (comp (ref "D15")
      (value "TCMT4100")
      (footprint "eagle-import:SO16")
      (fields (field (name "PARTNO") "TCMT4100"))
      (libsource (lib "eagle-import") (part "TCMT4100"))
    )
    (comp (ref "D16")
      (value "TCMT4100")
      (footprint "eagle-import:SO16")
      (fields (field (name "PARTNO") "TCMT4100"))
      (libsource (lib "eagle-import") (part "TCMT4100"))
    )
    (comp (ref "D17")
      (value "TCMT4100")
      (footprint "eagle-import:SO16")
      (fields (field (name "PARTNO") "TCMT4100"))
      (libsource (lib "eagle-import") (part "TCMT4100"))
    )
    (comp (ref "DD10")
      (value "74HC165D")
      (footprint "eagle-import:SO16")
      (fields (field (name "PARTNO") "IN74HC165AD"))
      (libsource (lib "eagle-import") (part "74165DHC"))
    )
    (comp (ref "DD11")
      (value "74HC165D")
      (footprint "eagle-import:SO16")
      (fields (field (name "PARTNO") "IN74HC165AD"))
      (libsource (lib "eagle-import") (part "74165DHC"))
    )
    (comp (ref "R285")
      (value "4.7kOhm/5%")
      (footprint "eagle-import:R1206")
      (fields (field (name "PARTNO") "RC1206JR-074K7L"))
      (libsource (lib "eagle-import") (part "R-EU_R1206"))
    )
    (comp (ref "R286")
      (value "4.7kOhm/5%")
      (footprint "eagle-import:R1206")
      (fields (field (name "PARTNO") "RC1206JR-074K7L"))
      (libsource (lib "eagle-import") (part "R-EU_R1206"))
    )
    (comp (ref "R287")
      (value "4.7kOhm/5%")
      (footprint "eagle-import:R1206")
      (fields (field (name "PARTNO") "RC1206JR-074K7L"))
      (libsource (lib "eagle-import") (part "R-EU_R1206"))
    )
    (comp (ref "R288")
      (value "4.7kOhm/5%")
      (footprint "eagle-import:R1206")
      (fields (field (name "PARTNO") "RC1206JR-074K7L"))
      (libsource (lib "eagle-import") (part "R-EU_R1206"))
    )
    (comp (ref "R289")
      (value "4.7kOhm/5%")
      (footprint "eagle-import:R1206")
      (fields (field (name "PARTNO") "RC1206JR-074K7L"))
      (libsource (lib "eagle-import") (part "R-EU_R1206"))
    )
    (comp (ref "R290")
      (value "4.7kOhm/5%")
      (footprint "eagle-import:R1206")
      (fields (field (name "PARTNO") "RC1206JR-074K7L"))
      (libsource (lib "eagle-import") (part "R-EU_R1206"))
    )
    (comp (ref "R291")
      (value "4.7kOhm/5%")
      (footprint "eagle-import:R1206")
      (fields (field (name "PARTNO") "RC1206JR-074K7L"))
      (libsource (lib "eagle-import") (part "R-EU_R1206"))
    )
    (comp (ref "R292")
      (value "4.7kOhm/5%")
      (footprint "eagle-import:R1206")
      (fields (field (name "PARTNO") "RC1206JR-074K7L"))
      (libsource (lib "eagle-import") (part "R-EU_R1206"))
    )
    (comp (ref "R293")
      (value "4.7kOhm/5%")
      (footprint "eagle-import:R1206")
      (fields (field (name "PARTNO") "RC1206JR-074K7L"))
      (libsource (lib "eagle-import") (part "R-EU_R1206"))
    )
    (comp (ref "R294")
      (value "4.7kOhm/5%")
      (footprint "eagle-import:R1206")
      (fields (field (name "PARTNO") "RC1206JR-074K7L"))
      (libsource (lib "eagle-import") (part "R-EU_R1206"))
    )
    (comp (ref "R295")
      (value "4.7kOhm/5%")
      (footprint "eagle-import:R1206")
      (fields (field (name "PARTNO") "RC1206JR-074K7L"))
      (libsource (lib "eagle-import") (part "R-EU_R1206"))
    )
    (comp (ref "R296")
      (value "4.7kOhm/5%")
      (footprint "eagle-import:R1206")
      (fields (field (name "PARTNO") "RC1206JR-074K7L"))
      (libsource (lib "eagle-import") (part "R-EU_R1206"))
    )
    (comp (ref "R297")
      (value "4.7kOhm/5%")
      (footprint "eagle-import:R1206")
      (fields (field (name "PARTNO") "RC1206JR-074K7L"))
      (libsource (lib "eagle-import") (part "R-EU_R1206"))
    )
    (comp (ref "R298")
      (value "4.7kOhm/5%")
      (footprint "eagle-import:R1206")
      (fields (field (name "PARTNO") "RC1206JR-074K7L"))
      (libsource (lib "eagle-import") (part "R-EU_R1206"))
    )
    (comp (ref "R299")
      (value "4.7kOhm/5%")
      (footprint "eagle-import:R1206")
      (fields (field (name "PARTNO") "RC1206JR-074K7L"))
      (libsource (lib "eagle-import") (part "R-EU_R1206"))
    )
    (comp (ref "R300")
      (value "4.7kOhm/5%")
      (footprint "eagle-import:R1206")
      (fields (field (name "PARTNO") "RC1206JR-074K7L"))
      (libsource (lib "eagle-import") (part "R-EU_R1206"))
    )
    (comp (ref "R301")
      (value "1kOhm/5%")
      (footprint "eagle-import:R2512")
      (fields (field (name "PARTNO") "RC2512JK-071KL"))
      (libsource (lib "eagle-import") (part "R-EU_R2512"))
    )
    (comp (ref "R302")
      (value "1kOhm/5%")
      (footprint "eagle-import:R2512")
      (fields (field (name "PARTNO") "RC2512JK-071KL"))
      (libsource (lib "eagle-import") (part "R-EU_R2512"))
    )
    (comp (ref "R303")
      (value "1kOhm/5%")
      (footprint "eagle-import:R2512")
      (fields (field (name "PARTNO") "RC2512JK-071KL"))
      (libsource (lib "eagle-import") (part "R-EU_R2512"))
    )
    (comp (ref "R304")
      (value "1kOhm/5%")
      (footprint "eagle-import:R2512")
      (fields (field (name "PARTNO") "RC2512JK-071KL"))
      (libsource (lib "eagle-import") (part "R-EU_R2512"))
    )
    (comp (ref "R305")
      (value "1kOhm/5%")
      (footprint "eagle-import:R2512")
      (fields (field (name "PARTNO") "RC2512JK-071KL"))
      (libsource (lib "eagle-import") (part "R-EU_R2512"))
    )
    (comp (ref "R306")
      (value "1kOhm/5%")
      (footprint "eagle-import:R2512")
      (fields (field (name "PARTNO") "RC2512JK-071KL"))
      (libsource (lib "eagle-import") (part "R-EU_R2512"))
    )
    (comp (ref "R307")
      (value "1kOhm/5%")
      (footprint "eagle-import:R2512")
      (fields (field (name "PARTNO") "RC2512JK-071KL"))
      (libsource (lib "eagle-import") (part "R-EU_R2512"))
    )
    (comp (ref "R308")
      (value "1kOhm/5%")
      (footprint "eagle-import:R2512")
      (fields (field (name "PARTNO") "RC2512JK-071KL"))
      (libsource (lib "eagle-import") (part "R-EU_R2512"))
    )
    (comp (ref "R309")
      (value "1kOhm/5%")
      (footprint "eagle-import:R2512")
      (fields (field (name "PARTNO") "RC2512JK-071KL"))
      (libsource (lib "eagle-import") (part "R-EU_R2512"))
    )
    (comp (ref "R310")
      (value "1kOhm/5%")
      (footprint "eagle-import:R2512")
      (fields (field (name "PARTNO") "RC2512JK-071KL"))
      (libsource (lib "eagle-import") (part "R-EU_R2512"))
    )
    (comp (ref "R311")
      (value "1kOhm/5%")
      (footprint "eagle-import:R2512")
      (fields (field (name "PARTNO") "RC2512JK-071KL"))
      (libsource (lib "eagle-import") (part "R-EU_R2512"))
    )
    (comp (ref "R312")
      (value "1kOhm/5%")
      (footprint "eagle-import:R2512")
      (fields (field (name "PARTNO") "RC2512JK-071KL"))
      (libsource (lib "eagle-import") (part "R-EU_R2512"))
    )
    (comp (ref "R313")
      (value "1kOhm/5%")
      (footprint "eagle-import:R2512")
      (fields (field (name "PARTNO") "RC2512JK-071KL"))
      (libsource (lib "eagle-import") (part "R-EU_R2512"))
    )
    (comp (ref "R314")
      (value "1kOhm/5%")
      (footprint "eagle-import:R2512")
      (fields (field (name "PARTNO") "RC2512JK-071KL"))
      (libsource (lib "eagle-import") (part "R-EU_R2512"))
    )
    (comp (ref "R315")
      (value "1kOhm/5%")
      (footprint "eagle-import:R2512")
      (fields (field (name "PARTNO") "RC2512JK-071KL"))
      (libsource (lib "eagle-import") (part "R-EU_R2512"))
    )
    (comp (ref "R316")
      (value "1kOhm/5%")
      (footprint "eagle-import:R2512")
      (fields (field (name "PARTNO") "RC2512JK-071KL"))
      (libsource (lib "eagle-import") (part "R-EU_R2512"))
    )
    (comp (ref "R317")
      (value "10kOhm/1%")
      (footprint "eagle-import:R0603")
      (fields (field (name "PARTNO") "RC0603FR-1010KL"))
      (libsource (lib "eagle-import") (part "R-EU_R0603"))
    )
    (comp (ref "R318")
      (value "10kOhm/1%")
      (footprint "eagle-import:R0603")
      (fields (field (name "PARTNO") "RC0603FR-1010KL"))
      (libsource (lib "eagle-import") (part "R-EU_R0603"))
    )
    (comp (ref "R319")
      (value "10kOhm/1%")
      (footprint "eagle-import:R0603")
      (fields (field (name "PARTNO") "RC0603FR-1010KL"))
      (libsource (lib "eagle-import") (part "R-EU_R0603"))
    )
    (comp (ref "R320")
      (value "10kOhm/1%")
      (footprint "eagle-import:R0603")
      (fields (field (name "PARTNO") "RC0603FR-1010KL"))
      (libsource (lib "eagle-import") (part "R-EU_R0603"))
    )
    (comp (ref "R321")
      (value "10kOhm/1%")
      (footprint "eagle-import:R0603")
      (fields (field (name "PARTNO") "RC0603FR-1010KL"))
      (libsource (lib "eagle-import") (part "R-EU_R0603"))
    )
    (comp (ref "R322")
      (value "10kOhm/1%")
      (footprint "eagle-import:R0603")
      (fields (field (name "PARTNO") "RC0603FR-1010KL"))
      (libsource (lib "eagle-import") (part "R-EU_R0603"))
    )
    (comp (ref "R323")
      (value "10kOhm/1%")
      (footprint "eagle-import:R0603")
      (fields (field (name "PARTNO") "RC0603FR-1010KL"))
      (libsource (lib "eagle-import") (part "R-EU_R0603"))
    )
    (comp (ref "R324")
      (value "10kOhm/1%")
      (footprint "eagle-import:R0603")
      (fields (field (name "PARTNO") "RC0603FR-1010KL"))
      (libsource (lib "eagle-import") (part "R-EU_R0603"))
    )
    (comp (ref "R325")
      (value "10kOhm/1%")
      (footprint "eagle-import:R0603")
      (fields (field (name "PARTNO") "RC0603FR-1010KL"))
      (libsource (lib "eagle-import") (part "R-EU_R0603"))
    )
    (comp (ref "R326")
      (value "10kOhm/1%")
      (footprint "eagle-import:R0603")
      (fields (field (name "PARTNO") "RC0603FR-1010KL"))
      (libsource (lib "eagle-import") (part "R-EU_R0603"))
    )
    (comp (ref "R327")
      (value "10kOhm/1%")
      (footprint "eagle-import:R0603")
      (fields (field (name "PARTNO") "RC0603FR-1010KL"))
      (libsource (lib "eagle-import") (part "R-EU_R0603"))
    )
    (comp (ref "R328")
      (value "10kOhm/1%")
      (footprint "eagle-import:R0603")
      (fields (field (name "PARTNO") "RC0603FR-1010KL"))
      (libsource (lib "eagle-import") (part "R-EU_R0603"))
    )
    (comp (ref "R329")
      (value "10kOhm/1%")
      (footprint "eagle-import:R0603")
      (fields (field (name "PARTNO") "RC0603FR-1010KL"))
      (libsource (lib "eagle-import") (part "R-EU_R0603"))
    )
    (comp (ref "R330")
      (value "10kOhm/1%")
      (footprint "eagle-import:R0603")
      (fields (field (name "PARTNO") "RC0603FR-1010KL"))
      (libsource (lib "eagle-import") (part "R-EU_R0603"))
    )
    (comp (ref "R331")
      (value "10kOhm/1%")
      (footprint "eagle-import:R0603")
      (fields (field (name "PARTNO") "RC0603FR-1010KL"))
      (libsource (lib "eagle-import") (part "R-EU_R0603"))
    )
    (comp (ref "R332")
      (value "10kOhm/1%")
      (footprint "eagle-import:R0603")
      (fields (field (name "PARTNO") "RC0603FR-1010KL"))
      (libsource (lib "eagle-import") (part "R-EU_R0603"))
    )
    (comp (ref "VD164")
      (value "SM6T200A")
      (footprint "eagle-import:SMB")
      (libsource (lib "eagle-import") (part "DIODE-TVS-UNIDIR-SMB"))
    )
    (comp (ref "VD165")
      (value "SM6T200A")
      (footprint "eagle-import:SMB")
      (libsource (lib "eagle-import") (part "DIODE-TVS-UNIDIR-SMB"))
    )
    (comp (ref "VD166")
      (value "SM6T200A")
      (footprint "eagle-import:SMB")
      (libsource (lib "eagle-import") (part "DIODE-TVS-UNIDIR-SMB"))
    )
    (comp (ref "VD167")
      (value "SM6T200A")
      (footprint "eagle-import:SMB")
      (libsource (lib "eagle-import") (part "DIODE-TVS-UNIDIR-SMB"))
    )
    (comp (ref "VD168")
      (value "SM6T200A")
      (footprint "eagle-import:SMB")
      (libsource (lib "eagle-import") (part "DIODE-TVS-UNIDIR-SMB"))
    )
    (comp (ref "VD169")
      (value "SM6T200A")
      (footprint "eagle-import:SMB")
      (libsource (lib "eagle-import") (part "DIODE-TVS-UNIDIR-SMB"))
    )
    (comp (ref "VD170")
      (value "SM6T200A")
      (footprint "eagle-import:SMB")
      (libsource (lib "eagle-import") (part "DIODE-TVS-UNIDIR-SMB"))
    )
    (comp (ref "VD171")
      (value "SM6T200A")
      (footprint "eagle-import:SMB")
      (libsource (lib "eagle-import") (part "DIODE-TVS-UNIDIR-SMB"))
    )
    (comp (ref "VD172")
      (value "SM6T200A")
      (footprint "eagle-import:SMB")
      (libsource (lib "eagle-import") (part "DIODE-TVS-UNIDIR-SMB"))
    )
    (comp (ref "VD173")
      (value "SM6T200A")
      (footprint "eagle-import:SMB")
      (libsource (lib "eagle-import") (part "DIODE-TVS-UNIDIR-SMB"))
    )
    (comp (ref "VD174")
      (value "SM6T200A")
      (footprint "eagle-import:SMB")
      (libsource (lib "eagle-import") (part "DIODE-TVS-UNIDIR-SMB"))
    )
    (comp (ref "VD175")
      (value "SM6T200A")
      (footprint "eagle-import:SMB")
      (libsource (lib "eagle-import") (part "DIODE-TVS-UNIDIR-SMB"))
    )
    (comp (ref "VD176")
      (value "SM6T200A")
      (footprint "eagle-import:SMB")
      (libsource (lib "eagle-import") (part "DIODE-TVS-UNIDIR-SMB"))
    )
    (comp (ref "VD177")
      (value "SM6T200A")
      (footprint "eagle-import:SMB")
      (libsource (lib "eagle-import") (part "DIODE-TVS-UNIDIR-SMB"))
    )
    (comp (ref "VD178")
      (value "SM6T200A")
      (footprint "eagle-import:SMB")
      (libsource (lib "eagle-import") (part "DIODE-TVS-UNIDIR-SMB"))
    )
    (comp (ref "VD179")
      (value "SM6T200A")
      (footprint "eagle-import:SMB")
      (libsource (lib "eagle-import") (part "DIODE-TVS-UNIDIR-SMB"))
    )
    (comp (ref "VD180")
      (value "400V")
      (footprint "eagle-import:SMA")
      (fields (field (name "PARTNO") "S1G-E3/61T"))
      (libsource (lib "eagle-import") (part "DIODE-STANDARD-SMA"))
    )
    (comp (ref "VD181")
      (value "400V")
      (footprint "eagle-import:SMA")
      (fields (field (name "PARTNO") "S1G-E3/61T"))
      (libsource (lib "eagle-import") (part "DIODE-STANDARD-SMA"))
    )
    (comp (ref "VD182")
      (value "400V")
      (footprint "eagle-import:SMA")
      (fields (field (name "PARTNO") "S1G-E3/61T"))
      (libsource (lib "eagle-import") (part "DIODE-STANDARD-SMA"))
    )
    (comp (ref "VD183")
      (value "400V")
      (footprint "eagle-import:SMA")
      (fields (field (name "PARTNO") "S1G-E3/61T"))
      (libsource (lib "eagle-import") (part "DIODE-STANDARD-SMA"))
    )
    (comp (ref "VD184")
      (value "400V")
      (footprint "eagle-import:SMA")
      (fields (field (name "PARTNO") "S1G-E3/61T"))
      (libsource (lib "eagle-import") (part "DIODE-STANDARD-SMA"))
    )
    (comp (ref "VD185")
      (value "400V")
      (footprint "eagle-import:SMA")
      (fields (field (name "PARTNO") "S1G-E3/61T"))
      (libsource (lib "eagle-import") (part "DIODE-STANDARD-SMA"))
    )
    (comp (ref "VD186")
      (value "400V")
      (footprint "eagle-import:SMA")
      (fields (field (name "PARTNO") "S1G-E3/61T"))
      (libsource (lib "eagle-import") (part "DIODE-STANDARD-SMA"))
    )
    (comp (ref "VD187")
      (value "400V")
      (footprint "eagle-import:SMA")
      (fields (field (name "PARTNO") "S1G-E3/61T"))
      (libsource (lib "eagle-import") (part "DIODE-STANDARD-SMA"))
    )
    (comp (ref "VD188")
      (value "400V")
      (footprint "eagle-import:SMA")
      (fields (field (name "PARTNO") "S1G-E3/61T"))
      (libsource (lib "eagle-import") (part "DIODE-STANDARD-SMA"))
    )
    (comp (ref "VD189")
      (value "400V")
      (footprint "eagle-import:SMA")
      (fields (field (name "PARTNO") "S1G-E3/61T"))
      (libsource (lib "eagle-import") (part "DIODE-STANDARD-SMA"))
    )
    (comp (ref "VD190")
      (value "400V")
      (footprint "eagle-import:SMA")
      (fields (field (name "PARTNO") "S1G-E3/61T"))
      (libsource (lib "eagle-import") (part "DIODE-STANDARD-SMA"))
    )
    (comp (ref "VD191")
      (value "400V")
      (footprint "eagle-import:SMA")
      (fields (field (name "PARTNO") "S1G-E3/61T"))
      (libsource (lib "eagle-import") (part "DIODE-STANDARD-SMA"))
    )
    (comp (ref "VD192")
      (value "400V")
      (footprint "eagle-import:SMA")
      (fields (field (name "PARTNO") "S1G-E3/61T"))
      (libsource (lib "eagle-import") (part "DIODE-STANDARD-SMA"))
    )
    (comp (ref "VD193")
      (value "400V")
      (footprint "eagle-import:SMA")
      (fields (field (name "PARTNO") "S1G-E3/61T"))
      (libsource (lib "eagle-import") (part "DIODE-STANDARD-SMA"))
    )
    (comp (ref "VD194")
      (value "400V")
      (footprint "eagle-import:SMA")
      (fields (field (name "PARTNO") "S1G-E3/61T"))
      (libsource (lib "eagle-import") (part "DIODE-STANDARD-SMA"))
    )
    (comp (ref "VD195")
      (value "400V")
      (footprint "eagle-import:SMA")
      (fields (field (name "PARTNO") "S1G-E3/61T"))
      (libsource (lib "eagle-import") (part "DIODE-STANDARD-SMA"))
    )
    (comp (ref "XP10")
      (value "MOLEX-90130-16")
      (footprint "eagle-import:MOLEX-90130-16")
      (fields (field (name "PARTNO") "90130-1216"))
      (libsource (lib "eagle-import") (part "MOLEX-90130-16"))
    )
    (comp (ref "C141")
      (value "0.1uF")
      (footprint "eagle-import:C0603")
      (fields (field (name "PARTNO") "C0603C104K5RACTU"))
      (libsource (lib "eagle-import") (part "C-EUC0603"))
    )
    (comp (ref "D18")
      (value "TCMT4100")
      (footprint "eagle-import:SO16")
      (fields (field (name "PARTNO") "TCMT4100"))
      (libsource (lib "eagle-import") (part "TCMT4100"))
    )
    (comp (ref "D19")
      (value "TCMT4100")
      (footprint "eagle-import:SO16")
      (fields (field (name "PARTNO") "TCMT4100"))
      (libsource (lib "eagle-import") (part "TCMT4100"))
    )
    (comp (ref "D20")
      (value "AUIPS7111S")
      (footprint "eagle-import:TO252-5-11")
      (libsource (lib "eagle-import") (part "AUIPS7111S"))
    )
    (comp (ref "D21")
      (value "AUIPS7111S")
      (footprint "eagle-import:TO252-5-11")
      (libsource (lib "eagle-import") (part "AUIPS7111S"))
    )
    (comp (ref "D22")
      (value "AUIPS7111S")
      (footprint "eagle-import:TO252-5-11")
      (libsource (lib "eagle-import") (part "AUIPS7111S"))
    )
    (comp (ref "D23")
      (value "AUIPS7111S")
      (footprint "eagle-import:TO252-5-11")
      (libsource (lib "eagle-import") (part "AUIPS7111S"))
    )
    (comp (ref "D24")
      (value "AUIPS7111S")
      (footprint "eagle-import:TO252-5-11")
      (libsource (lib "eagle-import") (part "AUIPS7111S"))
    )
    (comp (ref "D25")
      (value "AUIPS7111S")
      (footprint "eagle-import:TO252-5-11")
      (libsource (lib "eagle-import") (part "AUIPS7111S"))
    )
    (comp (ref "D26")
      (value "AUIPS7111S")
      (footprint "eagle-import:TO252-5-11")
      (libsource (lib "eagle-import") (part "AUIPS7111S"))
    )
    (comp (ref "D27")
      (value "AUIPS7111S")
      (footprint "eagle-import:TO252-5-11")
      (libsource (lib "eagle-import") (part "AUIPS7111S"))
    )
    (comp (ref "DD12")
      (value "74HC595D")
      (footprint "eagle-import:SO16")
      (fields (field (name "PARTNO") "IN74HC595AD"))
      (libsource (lib "eagle-import") (part "74595DHC"))
    )
    (comp (ref "R333")
      (value "10kOhm/1%")
      (footprint "eagle-import:R0603")
      (fields (field (name "PARTNO") "RC0603FR-1010KL"))
      (libsource (lib "eagle-import") (part "R-EU_R0603"))
    )
    (comp (ref "R334")
      (value "100Ohm/5%")
      (footprint "eagle-import:R0603")
      (fields (field (name "PARTNO") "ERJ3GEYJ101V"))
      (libsource (lib "eagle-import") (part "R-EU_R0603"))
    )
    (comp (ref "R335")
      (value "100Ohm/5%")
      (footprint "eagle-import:R0603")
      (fields (field (name "PARTNO") "ERJ3GEYJ101V"))
      (libsource (lib "eagle-import") (part "R-EU_R0603"))
    )
    (comp (ref "R336")
      (value "100Ohm/5%")
      (footprint "eagle-import:R0603")
      (fields (field (name "PARTNO") "ERJ3GEYJ101V"))
      (libsource (lib "eagle-import") (part "R-EU_R0603"))
    )
    (comp (ref "R337")
      (value "100Ohm/5%")
      (footprint "eagle-import:R0603")
      (fields (field (name "PARTNO") "ERJ3GEYJ101V"))
      (libsource (lib "eagle-import") (part "R-EU_R0603"))
    )
    (comp (ref "R338")
      (value "100Ohm/5%")
      (footprint "eagle-import:R0603")
      (fields (field (name "PARTNO") "ERJ3GEYJ101V"))
      (libsource (lib "eagle-import") (part "R-EU_R0603"))
    )
    (comp (ref "R339")
      (value "100Ohm/5%")
      (footprint "eagle-import:R0603")
      (fields (field (name "PARTNO") "ERJ3GEYJ101V"))
      (libsource (lib "eagle-import") (part "R-EU_R0603"))
    )
    (comp (ref "R340")
      (value "100Ohm/5%")
      (footprint "eagle-import:R0603")
      (fields (field (name "PARTNO") "ERJ3GEYJ101V"))
      (libsource (lib "eagle-import") (part "R-EU_R0603"))
    )
    (comp (ref "R341")
      (value "100Ohm/5%")
      (footprint "eagle-import:R0603")
      (fields (field (name "PARTNO") "ERJ3GEYJ101V"))
      (libsource (lib "eagle-import") (part "R-EU_R0603"))
    )
    (comp (ref "R342")
      (value "1kOhm/5%")
      (footprint "eagle-import:R0805")
      (fields (field (name "PARTNO") "ERJ6GEYJ102V"))
      (libsource (lib "eagle-import") (part "R-EU_R0805"))
    )
    (comp (ref "R343")
      (value "1kOhm/5%")
      (footprint "eagle-import:R0805")
      (fields (field (name "PARTNO") "ERJ6GEYJ102V"))
      (libsource (lib "eagle-import") (part "R-EU_R0805"))
    )
    (comp (ref "R344")
      (value "1kOhm/5%")
      (footprint "eagle-import:R0805")
      (fields (field (name "PARTNO") "ERJ6GEYJ102V"))
      (libsource (lib "eagle-import") (part "R-EU_R0805"))
    )
    (comp (ref "R345")
      (value "1kOhm/5%")
      (footprint "eagle-import:R0805")
      (fields (field (name "PARTNO") "ERJ6GEYJ102V"))
      (libsource (lib "eagle-import") (part "R-EU_R0805"))
    )
    (comp (ref "R346")
      (value "1kOhm/5%")
      (footprint "eagle-import:R0805")
      (fields (field (name "PARTNO") "ERJ6GEYJ102V"))
      (libsource (lib "eagle-import") (part "R-EU_R0805"))
    )
    (comp (ref "R347")
      (value "1kOhm/5%")
      (footprint "eagle-import:R0805")
      (fields (field (name "PARTNO") "ERJ6GEYJ102V"))
      (libsource (lib "eagle-import") (part "R-EU_R0805"))
    )
    (comp (ref "R348")
      (value "1kOhm/5%")
      (footprint "eagle-import:R0805")
      (fields (field (name "PARTNO") "ERJ6GEYJ102V"))
      (libsource (lib "eagle-import") (part "R-EU_R0805"))
    )
    (comp (ref "R349")
      (value "1kOhm/5%")
      (footprint "eagle-import:R0805")
      (fields (field (name "PARTNO") "ERJ6GEYJ102V"))
      (libsource (lib "eagle-import") (part "R-EU_R0805"))
    )
    (comp (ref "R350")
      (value "1kOhm/5%")
      (footprint "eagle-import:R0805")
      (fields (field (name "PARTNO") "ERJ6GEYJ102V"))
      (libsource (lib "eagle-import") (part "R-EU_R0805"))
    )
    (comp (ref "R351")
      (value "1kOhm/5%")
      (footprint "eagle-import:R0805")
      (fields (field (name "PARTNO") "ERJ6GEYJ102V"))
      (libsource (lib "eagle-import") (part "R-EU_R0805"))
    )
    (comp (ref "R352")
      (value "1kOhm/5%")
      (footprint "eagle-import:R0805")
      (fields (field (name "PARTNO") "ERJ6GEYJ102V"))
      (libsource (lib "eagle-import") (part "R-EU_R0805"))
    )
    (comp (ref "R353")
      (value "1kOhm/5%")
      (footprint "eagle-import:R0805")
      (fields (field (name "PARTNO") "ERJ6GEYJ102V"))
      (libsource (lib "eagle-import") (part "R-EU_R0805"))
    )
    (comp (ref "R354")
      (value "1kOhm/5%")
      (footprint "eagle-import:R0805")
      (fields (field (name "PARTNO") "ERJ6GEYJ102V"))
      (libsource (lib "eagle-import") (part "R-EU_R0805"))
    )
    (comp (ref "R355")
      (value "1kOhm/5%")
      (footprint "eagle-import:R0805")
      (fields (field (name "PARTNO") "ERJ6GEYJ102V"))
      (libsource (lib "eagle-import") (part "R-EU_R0805"))
    )
    (comp (ref "R356")
      (value "1kOhm/5%")
      (footprint "eagle-import:R0805")
      (fields (field (name "PARTNO") "ERJ6GEYJ102V"))
      (libsource (lib "eagle-import") (part "R-EU_R0805"))
    )
    (comp (ref "R357")
      (value "1kOhm/5%")
      (footprint "eagle-import:R0805")
      (fields (field (name "PARTNO") "ERJ6GEYJ102V"))
      (libsource (lib "eagle-import") (part "R-EU_R0805"))
    )
    (comp (ref "VD196")
      (value "100V")
      (footprint "eagle-import:SOD323")
      (fields (field (name "PARTNO") "1N4148WS-V-GS18"))
      (libsource (lib "eagle-import") (part "DIODE-STANDARD-SOD323"))
    )
    (comp (ref "VD197")
      (value "100V")
      (footprint "eagle-import:SOD323")
      (fields (field (name "PARTNO") "1N4148WS-V-GS18"))
      (libsource (lib "eagle-import") (part "DIODE-STANDARD-SOD323"))
    )
    (comp (ref "VD198")
      (value "100V")
      (footprint "eagle-import:SOD323")
      (fields (field (name "PARTNO") "1N4148WS-V-GS18"))
      (libsource (lib "eagle-import") (part "DIODE-STANDARD-SOD323"))
    )
    (comp (ref "VD199")
      (value "100V")
      (footprint "eagle-import:SOD323")
      (fields (field (name "PARTNO") "1N4148WS-V-GS18"))
      (libsource (lib "eagle-import") (part "DIODE-STANDARD-SOD323"))
    )
    (comp (ref "VD200")
      (value "100V")
      (footprint "eagle-import:SOD323")
      (fields (field (name "PARTNO") "1N4148WS-V-GS18"))
      (libsource (lib "eagle-import") (part "DIODE-STANDARD-SOD323"))
    )
    (comp (ref "VD201")
      (value "100V")
      (footprint "eagle-import:SOD323")
      (fields (field (name "PARTNO") "1N4148WS-V-GS18"))
      (libsource (lib "eagle-import") (part "DIODE-STANDARD-SOD323"))
    )
    (comp (ref "VD202")
      (value "100V")
      (footprint "eagle-import:SOD323")
      (fields (field (name "PARTNO") "1N4148WS-V-GS18"))
      (libsource (lib "eagle-import") (part "DIODE-STANDARD-SOD323"))
    )
    (comp (ref "VD203")
      (value "100V")
      (footprint "eagle-import:SOD323")
      (fields (field (name "PARTNO") "1N4148WS-V-GS18"))
      (libsource (lib "eagle-import") (part "DIODE-STANDARD-SOD323"))
    )
    (comp (ref "VD204")
      (value "100V")
      (footprint "eagle-import:SOD323")
      (fields (field (name "PARTNO") "1N4148WS-V-GS18"))
      (libsource (lib "eagle-import") (part "DIODE-STANDARD-SOD323"))
    )
    (comp (ref "VD205")
      (value "100V")
      (footprint "eagle-import:SOD323")
      (fields (field (name "PARTNO") "1N4148WS-V-GS18"))
      (libsource (lib "eagle-import") (part "DIODE-STANDARD-SOD323"))
    )
    (comp (ref "VD206")
      (value "100V")
      (footprint "eagle-import:SOD323")
      (fields (field (name "PARTNO") "1N4148WS-V-GS18"))
      (libsource (lib "eagle-import") (part "DIODE-STANDARD-SOD323"))
    )
    (comp (ref "VD207")
      (value "100V")
      (footprint "eagle-import:SOD323")
      (fields (field (name "PARTNO") "1N4148WS-V-GS18"))
      (libsource (lib "eagle-import") (part "DIODE-STANDARD-SOD323"))
    )
    (comp (ref "VD208")
      (value "100V")
      (footprint "eagle-import:SOD323")
      (fields (field (name "PARTNO") "1N4148WS-V-GS18"))
      (libsource (lib "eagle-import") (part "DIODE-STANDARD-SOD323"))
    )
    (comp (ref "VD209")
      (value "100V")
      (footprint "eagle-import:SOD323")
      (fields (field (name "PARTNO") "1N4148WS-V-GS18"))
      (libsource (lib "eagle-import") (part "DIODE-STANDARD-SOD323"))
    )
    (comp (ref "VD210")
      (value "100V")
      (footprint "eagle-import:SOD323")
      (fields (field (name "PARTNO") "1N4148WS-V-GS18"))
      (libsource (lib "eagle-import") (part "DIODE-STANDARD-SOD323"))
    )
    (comp (ref "VD211")
      (value "100V")
      (footprint "eagle-import:SOD323")
      (fields (field (name "PARTNO") "1N4148WS-V-GS18"))
      (libsource (lib "eagle-import") (part "DIODE-STANDARD-SOD323"))
    )
    (comp (ref "XP11")
      (value "MOLEX-90130-34")
      (footprint "eagle-import:MOLEX-90130-34")
      (fields (field (name "PARTNO") "90130-1234"))
      (libsource (lib "eagle-import") (part "MOLEX-90130-34"))
    )
    (comp (ref "C56")
      (value "10uF/50V")
      (footprint "eagle-import:C2220K")
      (fields (field (name "PARTNO") "22205C106KAT2A"))
      (libsource (lib "eagle-import") (part "C-EUC2220K"))
    )
    (comp (ref "C57")
      (value "1000uF/50v")
      (footprint "eagle-import:E35-16-STRAPPED")
      (fields (field (name "PARTNO") "516D108M050QS6AE3"))
      (libsource (lib "eagle-import") (part "CPOL-EUE35-16AXIAL-STRAPPED"))
    )
    (comp (ref "C58")
      (value "10uF/50V")
      (footprint "eagle-import:C2220K")
      (fields (field (name "PARTNO") "22205C106KAT2A"))
      (libsource (lib "eagle-import") (part "C-EUC2220K"))
    )
    (comp (ref "C59")
      (value "0.1uF")
      (footprint "eagle-import:C0603")
      (fields (field (name "PARTNO") "C0603C104K5RACTU"))
      (libsource (lib "eagle-import") (part "C-EUC0603"))
    )
    (comp (ref "C60")
      (value "10uF/50V")
      (footprint "eagle-import:C2220K")
      (fields (field (name "PARTNO") "22205C106KAT2A"))
      (libsource (lib "eagle-import") (part "C-EUC2220K"))
    )
    (comp (ref "C61")
      (value "0.1uF")
      (footprint "eagle-import:C0603")
      (fields (field (name "PARTNO") "C0603C104K5RACTU"))
      (libsource (lib "eagle-import") (part "C-EUC0603"))
    )
    (comp (ref "C62")
      (value "0.01uF")
      (footprint "eagle-import:C0603")
      (fields (field (name "PARTNO") "C0603C103K5RACTU"))
      (libsource (lib "eagle-import") (part "C-EUC0603"))
    )
    (comp (ref "C63")
      (value "0.1uF")
      (footprint "eagle-import:C0603")
      (fields (field (name "PARTNO") "C0603C104K5RACTU"))
      (libsource (lib "eagle-import") (part "C-EUC0603"))
    )
    (comp (ref "C64")
      (value "10uF/10V")
      (footprint "eagle-import:A_3216-18W")
      (fields (field (name "PARTNO") "T491A106K010AT"))
      (libsource (lib "eagle-import") (part "CPOL-EUA/3216-18W"))
    )
    (comp (ref "C65")
      (value "1uF/16V")
      (footprint "eagle-import:C0603")
      (fields (field (name "PARTNO") "C0603C105K4PACTU"))
      (libsource (lib "eagle-import") (part "C-EUC0603"))
    )
    (comp (ref "C66")
      (value "220uF/10V")
      (footprint "eagle-import:TE-D-7343")
      (fields (field (name "PARTNO") "T491D227K010AT"))
      (libsource (lib "eagle-import") (part "CPOL-EUTE-D-7343"))
    )
    (comp (ref "C67")
      (value "220uF/10V")
      (footprint "eagle-import:TE-D-7343")
      (fields (field (name "PARTNO") "T491D227K010AT"))
      (libsource (lib "eagle-import") (part "CPOL-EUTE-D-7343"))
    )
    (comp (ref "C68")
      (value "10uF/10V")
      (footprint "eagle-import:A_3216-18W")
      (fields (field (name "PARTNO") "T491A106K010AT"))
      (libsource (lib "eagle-import") (part "CPOL-EUA/3216-18W"))
    )
    (comp (ref "DA11")
      (value "MC33091A")
      (footprint "eagle-import:SO08")
      (fields (field (name "PARTNO") "IL33091AD"))
      (libsource (lib "eagle-import") (part "MC33091A"))
    )
    (comp (ref "DA12")
      (value "LM2596S-5.0")
      (footprint "eagle-import:TO263-5")
      (fields (field (name "PARTNO") "LM2596S-5.0/NOPB"))
      (libsource (lib "eagle-import") (part "LM2596?-S5.0"))
    )
    (comp (ref "DA13")
      (value "LM2596S-5.0")
      (footprint "eagle-import:TO263-5")
      (fields (field (name "PARTNO") "LM2596S-5.0/NOPB"))
      (libsource (lib "eagle-import") (part "LM2596?-S5.0"))
    )
    (comp (ref "DA14")
      (value "IL5233G")
      (footprint "eagle-import:SOT223")
      (libsource (lib "eagle-import") (part "IL52G33"))
    )
    (comp (ref "L2")
      (value "47uH")
      (footprint "eagle-import:DRA127")
      (fields (field (name "PARTNO") "DR127-470-R"))
      (libsource (lib "eagle-import") (part "DRA127"))
    )
    (comp (ref "L3")
      (value "100uH")
      (footprint "eagle-import:DRA73")
      (fields (field (name "PARTNO") "DR73-101-R"))
      (libsource (lib "eagle-import") (part "DRA73"))
    )
    (comp (ref "R131")
      (value "15kOhm/5%")
      (footprint "eagle-import:R0805")
      (fields (field (name "PARTNO") "ERJ6GEYJ153V"))
      (libsource (lib "eagle-import") (part "R-EU_R0805"))
    )
    (comp (ref "R132")
      (value "82kOhm/5%")
      (footprint "eagle-import:R0805")
      (fields (field (name "PARTNO") "RC0805JR-0782KL"))
      (libsource (lib "eagle-import") (part "R-EU_R0805"))
    )
    (comp (ref "R133")
      (value "470kOhm/5%")
      (footprint "eagle-import:R0805")
      (fields (field (name "PARTNO") "ERJ6GEYJ474V"))
      (libsource (lib "eagle-import") (part "R-EU_R0805"))
    )
    (comp (ref "R134")
      (value "1kOhm/5%")
      (footprint "eagle-import:R0805")
      (fields (field (name "PARTNO") "ERJ6GEYJ102V"))
      (libsource (lib "eagle-import") (part "R-EU_R0805"))
    )
    (comp (ref "R135")
      (value "3.3kOhm/5%")
      (footprint "eagle-import:R2512")
      (fields (field (name "PARTNO") "35203K3JT"))
      (libsource (lib "eagle-import") (part "R-EU_R2512"))
    )
    (comp (ref "R136")
      (value "330Ohm/5%")
      (footprint "eagle-import:R0603")
      (fields (field (name "PARTNO") "ERJ3GEYJ331V"))
      (libsource (lib "eagle-import") (part "R-EU_R0603"))
    )
    (comp (ref "R137")
      (value "330Ohm/5%")
      (footprint "eagle-import:R0603")
      (fields (field (name "PARTNO") "ERJ3GEYJ331V"))
      (libsource (lib "eagle-import") (part "R-EU_R0603"))
    )
    (comp (ref "RK1")
      (value "0.5A")
      (footprint "eagle-import:RK1210")
      (fields (field (name "PARTNO") "1210L050YR"))
      (libsource (lib "eagle-import") (part "RESETTABLE_FUSE_1210"))
    )
    (comp (ref "RK2")
      (value "2A")
      (footprint "eagle-import:RK1812")
      (fields (field (name "PARTNO") "1812L200DR"))
      (libsource (lib "eagle-import") (part "RESETTABLE_FUSE_1812"))
    )
    (comp (ref "RK3")
      (value "0.5A")
      (footprint "eagle-import:RK1210")
      (fields (field (name "PARTNO") "1210L050YR"))
      (libsource (lib "eagle-import") (part "RESETTABLE_FUSE_1210"))
    )
    (comp (ref "VD53")
      (value "SMBJ24CA")
      (footprint "eagle-import:SMB-BIDIR")
      (libsource (lib "eagle-import") (part "DIODE-TVS-BIDIR-SMB"))
    )
    (comp (ref "VD54")
      (value "SMBJ24CA")
      (footprint "eagle-import:SMB-BIDIR")
      (libsource (lib "eagle-import") (part "DIODE-TVS-BIDIR-SMB"))
    )
    (comp (ref "VD55")
      (value "SM6T6V8A")
      (footprint "eagle-import:SMB")
      (libsource (lib "eagle-import") (part "DIODE-TVS-UNIDIR-SMB"))
    )
    (comp (ref "VD56")
      (value "400V")
      (footprint "eagle-import:SMA")
      (fields (field (name "PARTNO") "S1G-E3/61T"))
      (libsource (lib "eagle-import") (part "DIODE-STANDARD-SMA"))
    )
    (comp (ref "VD57")
      (value "SMBJ24CA")
      (footprint "eagle-import:SMB-BIDIR")
      (libsource (lib "eagle-import") (part "DIODE-TVS-BIDIR-SMB"))
    )
    (comp (ref "VD58")
      (value "3A/60V")
      (footprint "eagle-import:SMC")
      (fields (field (name "PARTNO") "VS-30BQ060TRPBF"))
      (libsource (lib "eagle-import") (part "DIODE-SCHOTTKY-SMC"))
    )
    (comp (ref "VD59")
      (value "1A/60V")
      (footprint "eagle-import:SMB")
      (fields (field (name "PARTNO") "VS-10BQ060TRPBF"))
      (libsource (lib "eagle-import") (part "DIODE-SCHOTTKY-SMB"))
    )
    (comp (ref "VD60")
      (value "400V")
      (footprint "eagle-import:SMA")
      (fields (field (name "PARTNO") "S1G-E3/61T"))
      (libsource (lib "eagle-import") (part "DIODE-STANDARD-SMA"))
    )
    (comp (ref "VD61")
      (value "600V/6A")
      (footprint "eagle-import:DPAK")
      (fields (field (name "PARTNO") "IDD06SG60C"))
      (libsource (lib "eagle-import") (part "IDD06SG60C"))
    )
    (comp (ref "VD62")
      (value "SMBJ24CA")
      (footprint "eagle-import:SMB-BIDIR")
      (libsource (lib "eagle-import") (part "DIODE-TVS-BIDIR-SMB"))
    )
    (comp (ref "VD63")
      (value "SM6T200A")
      (footprint "eagle-import:SMB")
      (libsource (lib "eagle-import") (part "DIODE-TVS-UNIDIR-SMB"))
    )
    (comp (ref "VD64")
      (value "GREEN")
      (footprint "eagle-import:LED-0805")
      (fields (field (name "LABEL") "+5V") (field (name "PARTNO") "KPHCM-2012SGC-T"))
      (libsource (lib "eagle-import") (part "LED0805"))
    )
    (comp (ref "VD65")
      (value "GREEN")
      (footprint "eagle-import:LED-0805")
      (fields (field (name "LABEL") "-5V") (field (name "PARTNO") "KPHCM-2012SGC-T"))
      (libsource (lib "eagle-import") (part "LED0805"))
    )
    (comp (ref "VT1")
      (value "IRFR430")
      (footprint "eagle-import:DPAK")
      (fields (field (name "PARTNO") "IRFR430APBF"))
      (libsource (lib "eagle-import") (part "IRFR430"))
    )
    (comp (ref "XP6")
      (value "MOLEX-90130-08")
      (footprint "eagle-import:MOLEX-90130-08")
      (fields (field (name "LABEL") "POWER") (field (name "PARTNO") "90130-1208"))
      (libsource (lib "eagle-import") (part "MOLEX-90130-08"))
    )
    (comp (ref "Z41")
      (value "4701-001LF")
      (footprint "eagle-import:TUSONIX-4701")
      (libsource (lib "eagle-import") (part "4701-001LF"))
    )
    (comp (ref "JP1")
      (value "STAND-OFF-M4")
      (footprint "eagle-import:STAND-OFF-M4")
      (libsource (lib "eagle-import") (part "STAND-OFF-M4"))
    )
    (comp (ref "JP2")
      (value "STAND-OFF-M4")
      (footprint "eagle-import:STAND-OFF-M4")
      (libsource (lib "eagle-import") (part "STAND-OFF-M4"))
    )
    (comp (ref "JP3")
      (value "STAND-OFF-M4")
      (footprint "eagle-import:STAND-OFF-M4")
      (libsource (lib "eagle-import") (part "STAND-OFF-M4"))
    )
    (comp (ref "JP4")
      (value "STAND-OFF-M4")
      (footprint "eagle-import:STAND-OFF-M4")
      (libsource (lib "eagle-import") (part "STAND-OFF-M4"))
    )
    (comp (ref "JP5")
      (value "STAND-OFF-M4")
      (footprint "eagle-import:STAND-OFF-M4")
      (libsource (lib "eagle-import") (part "STAND-OFF-M4"))
    )
    (comp (ref "JP6")
      (value "STAND-OFF-M4")
      (footprint "eagle-import:STAND-OFF-M4")
      (libsource (lib "eagle-import") (part "STAND-OFF-M4"))
    )
    (comp (ref "JP7")
      (value "STAND-OFF-M4")
      (footprint "eagle-import:STAND-OFF-M4")
      (libsource (lib "eagle-import") (part "STAND-OFF-M4"))
    )
    (comp (ref "JP8")
      (value "STAND-OFF-M4")
      (footprint "eagle-import:STAND-OFF-M4")
      (libsource (lib "eagle-import") (part "STAND-OFF-M4"))
    )
    (comp (ref "JP9")
      (value "STAND-OFF-M3")
      (footprint "eagle-import:STAND-OFF-M3")
      (libsource (lib "eagle-import") (part "STAND-OFF-M3"))
    )
    (comp (ref "JP10")
      (value "STAND-OFF-M3")
      (footprint "eagle-import:STAND-OFF-M3")
      (libsource (lib "eagle-import") (part "STAND-OFF-M3"))
    )
    (comp (ref "C142")
      (value "0.1uF")
      (footprint "eagle-import:C0603")
      (fields (field (name "PARTNO") "C0603C104K5RACTU"))
      (libsource (lib "eagle-import") (part "C-EUC0603"))
    )
    (comp (ref "C143")
      (value "0.1uF")
      (footprint "eagle-import:C0603")
      (fields (field (name "PARTNO") "C0603C104K5RACTU"))
      (libsource (lib "eagle-import") (part "C-EUC0603"))
    )
    (comp (ref "C144")
      (value "0.1uF")
      (footprint "eagle-import:C0603")
      (fields (field (name "PARTNO") "C0603C104K5RACTU"))
      (libsource (lib "eagle-import") (part "C-EUC0603"))
    )
    (comp (ref "C145")
      (value "0.1uF")
      (footprint "eagle-import:C0603")
      (fields (field (name "PARTNO") "C0603C104K5RACTU"))
      (libsource (lib "eagle-import") (part "C-EUC0603"))
    )
    (comp (ref "C146")
      (value "0.1uF")
      (footprint "eagle-import:C0603")
      (fields (field (name "PARTNO") "C0603C104K5RACTU"))
      (libsource (lib "eagle-import") (part "C-EUC0603"))
    )
    (comp (ref "C147")
      (value "0.1uF")
      (footprint "eagle-import:C0603")
      (fields (field (name "PARTNO") "C0603C104K5RACTU"))
      (libsource (lib "eagle-import") (part "C-EUC0603"))
    )
    (comp (ref "DA15")
      (value "USBUF01W6")
      (footprint "eagle-import:SOTT323-6L")
      (libsource (lib "eagle-import") (part "USBUF01W6"))
    )
    (comp (ref "DA16")
      (value "SN65HVD232")
      (footprint "eagle-import:SO08")
      (fields (field (name "PARTNO") "SN65HVD232D"))
      (libsource (lib "eagle-import") (part "SN65HVD232"))
    )
    (comp (ref "DA17")
      (value "ILX3232D")
      (footprint "eagle-import:SO16")
      (libsource (lib "eagle-import") (part "ILX3232D"))
    )
    (comp (ref "L4")
      (value "EXC3BP")
      (footprint "eagle-import:L0603")
      (fields (field (name "PARTNO") "EXC3BP121H"))
      (libsource (lib "eagle-import") (part "EXC3BP"))
    )
    (comp (ref "R358")
      (value "120Ohm/5%")
      (footprint "eagle-import:R1206")
      (fields (field (name "PARTNO") "RC1206JR-07120RL"))
      (libsource (lib "eagle-import") (part "R-EU_R1206"))
    )
    (comp (ref "R359")
      (value "10kOhm/1%")
      (footprint "eagle-import:R0603")
      (fields (field (name "PARTNO") "RC0603FR-1010KL"))
      (libsource (lib "eagle-import") (part "R-EU_R0603"))
    )
    (comp (ref "R360")
      (value "36kOhm/5%")
      (footprint "eagle-import:R0603")
      (fields (field (name "PARTNO") "ERJ3GEYJ363V"))
      (libsource (lib "eagle-import") (part "R-EU_R0603"))
    )
    (comp (ref "R361")
      (value "10kOhm/1%")
      (footprint "eagle-import:R0603")
      (fields (field (name "PARTNO") "RC0603FR-1010KL"))
      (libsource (lib "eagle-import") (part "R-EU_R0603"))
    )
    (comp (ref "R362")
      (value "47kOhm/5%")
      (footprint "eagle-import:R0603")
      (fields (field (name "PARTNO") "ERJ3GEYJ473V"))
      (libsource (lib "eagle-import") (part "R-EU_R0603"))
    )
    (comp (ref "R363")
      (value "1kOhm/5%")
      (footprint "eagle-import:R0805")
      (fields (field (name "PARTNO") "ERJ6GEYJ102V"))
      (libsource (lib "eagle-import") (part "R-EU_R0805"))
    )
    (comp (ref "R364")
      (value "1kOhm/5%")
      (footprint "eagle-import:R0805")
      (fields (field (name "PARTNO") "ERJ6GEYJ102V"))
      (libsource (lib "eagle-import") (part "R-EU_R0805"))
    )
    (comp (ref "VD212")
      (value "SMBJ24CA")
      (footprint "eagle-import:SMB-BIDIR")
      (libsource (lib "eagle-import") (part "DIODE-TVS-BIDIR-SMB"))
    )
    (comp (ref "VD213")
      (value "SMBJ24CA")
      (footprint "eagle-import:SMB-BIDIR")
      (libsource (lib "eagle-import") (part "DIODE-TVS-BIDIR-SMB"))
    )
    (comp (ref "VD214")
      (value "3.3V")
      (footprint "eagle-import:SOD80")
      (fields (field (name "PARTNO") "BZV55-C3V3"))
      (libsource (lib "eagle-import") (part "DIODE-ZENER-"))
    )
    (comp (ref "VT3")
      (value "BC817-16SMD")
      (footprint "eagle-import:SOT23-BEC")
      (fields (field (name "PARTNO") "BC817"))
      (libsource (lib "eagle-import") (part "BC817SMD-16"))
    )
    (comp (ref "VT4")
      (value "BC817-16SMD")
      (footprint "eagle-import:SOT23-BEC")
      (fields (field (name "PARTNO") "BC817"))
      (libsource (lib "eagle-import") (part "BC817SMD-16"))
    )
    (comp (ref "XP12")
      (value "MOLEX-90130-08")
      (footprint "eagle-import:MOLEX-90130-08")
      (fields (field (name "LABEL") "INTERFACES") (field (name "PARTNO") "90142-0008"))
      (libsource (lib "eagle-import") (part "MOLEX-90130-08"))
    )
    (comp (ref "XP13")
      (value "PLD_1X02")
      (footprint "eagle-import:PLD_1X02")
      (fields (field (name "PARTNO") "825433-2"))
      (libsource (lib "eagle-import") (part "PLD_1X02"))
    )
    (comp (ref "XS1")
      (value "USB-MINIB_(SOVOK-UGO)")
      (footprint "eagle-import:USB-MINIB")
      (fields (field (name "PARTNO") "MUBS1-05SN2"))
      (libsource (lib "eagle-import") (part "USB-MINIB_(SOVOK-UGO)"))
    )
    (comp (ref "Z42")
      (value "NFE31PT")
      (footprint "eagle-import:NFE31")
      (fields (field (name "PARTNO") "NFE31PT152Z1E9"))
      (libsource (lib "eagle-import") (part "NFE31PT"))
    )
    (comp (ref "Z43")
      (value "NFE31PT")
      (footprint "eagle-import:NFE31")
      (fields (field (name "PARTNO") "NFE31PT152Z1E9"))
      (libsource (lib "eagle-import") (part "NFE31PT"))
    )
    (comp (ref "Z44")
      (value "NFE31PT")
      (footprint "eagle-import:NFE31")
      (fields (field (name "PARTNO") "NFE31PT152Z1E9"))
      (libsource (lib "eagle-import") (part "NFE31PT"))
    )
    (comp (ref "Z45")
      (value "NFE31PT")
      (footprint "eagle-import:NFE31")
      (fields (field (name "PARTNO") "NFE31PT152Z1E9"))
      (libsource (lib "eagle-import") (part "NFE31PT"))
    )
    (comp (ref "Z46")
      (value "NFE31PT")
      (footprint "eagle-import:NFE31")
      (fields (field (name "PARTNO") "NFE31PT152Z1E9"))
      (libsource (lib "eagle-import") (part "NFE31PT"))
    )
    (comp (ref "Z47")
      (value "NFE31PT")
      (footprint "eagle-import:NFE31")
      (fields (field (name "PARTNO") "NFE31PT152Z1E9"))
      (libsource (lib "eagle-import") (part "NFE31PT"))
    )
    (comp (ref "Z48")
      (value "NFE31PT")
      (footprint "eagle-import:NFE31")
      (fields (field (name "PARTNO") "NFE31PT152Z1E9"))
      (libsource (lib "eagle-import") (part "NFE31PT"))
    )
    (comp (ref "Z49")
      (value "NFE31PT")
      (footprint "eagle-import:NFE31")
      (fields (field (name "PARTNO") "NFE31PT152Z1E9"))
      (libsource (lib "eagle-import") (part "NFE31PT"))
    )
    (comp (ref "Z50")
      (value "NFE31PT")
      (footprint "eagle-import:NFE31")
      (fields (field (name "PARTNO") "NFE31PT152Z1E9"))
      (libsource (lib "eagle-import") (part "NFE31PT"))
    )
    (comp (ref "C105")
      (value "0.1uF")
      (footprint "eagle-import:C0603")
      (fields (field (name "PARTNO") "C0603C104K5RACTU"))
      (libsource (lib "eagle-import") (part "C-EUC0603"))
    )
    (comp (ref "C106")
      (value "0.1uF")
      (footprint "eagle-import:C0603")
      (fields (field (name "PARTNO") "C0603C104K5RACTU"))
      (libsource (lib "eagle-import") (part "C-EUC0603"))
    )
    (comp (ref "C107")
      (value "0.1uF")
      (footprint "eagle-import:C0603")
      (fields (field (name "PARTNO") "C0603C104K5RACTU"))
      (libsource (lib "eagle-import") (part "C-EUC0603"))
    )
    (comp (ref "C108")
      (value "0.1uF")
      (footprint "eagle-import:C0603")
      (fields (field (name "PARTNO") "C0603C104K5RACTU"))
      (libsource (lib "eagle-import") (part "C-EUC0603"))
    )
    (comp (ref "C109")
      (value "0.1uF")
      (footprint "eagle-import:C0603")
      (fields (field (name "PARTNO") "C0603C104K5RACTU"))
      (libsource (lib "eagle-import") (part "C-EUC0603"))
    )
    (comp (ref "C110")
      (value "0.1uF")
      (footprint "eagle-import:C0603")
      (fields (field (name "PARTNO") "C0603C104K5RACTU"))
      (libsource (lib "eagle-import") (part "C-EUC0603"))
    )
    (comp (ref "C111")
      (value "0.1uF")
      (footprint "eagle-import:C0603")
      (fields (field (name "PARTNO") "C0603C104K5RACTU"))
      (libsource (lib "eagle-import") (part "C-EUC0603"))
    )
    (comp (ref "C112")
      (value "0.1uF")
      (footprint "eagle-import:C0603")
      (fields (field (name "PARTNO") "C0603C104K5RACTU"))
      (libsource (lib "eagle-import") (part "C-EUC0603"))
    )
    (comp (ref "C113")
      (value "0.1uF")
      (footprint "eagle-import:C0603")
      (fields (field (name "PARTNO") "C0603C104K5RACTU"))
      (libsource (lib "eagle-import") (part "C-EUC0603"))
    )
    (comp (ref "C114")
      (value "0.1uF")
      (footprint "eagle-import:C0603")
      (fields (field (name "PARTNO") "C0603C104K5RACTU"))
      (libsource (lib "eagle-import") (part "C-EUC0603"))
    )
    (comp (ref "C115")
      (value "0.1uF")
      (footprint "eagle-import:C0603")
      (fields (field (name "PARTNO") "C0603C104K5RACTU"))
      (libsource (lib "eagle-import") (part "C-EUC0603"))
    )
    (comp (ref "C116")
      (value "0.1uF")
      (footprint "eagle-import:C0603")
      (fields (field (name "PARTNO") "C0603C104K5RACTU"))
      (libsource (lib "eagle-import") (part "C-EUC0603"))
    )
    (comp (ref "C117")
      (value "0.1uF")
      (footprint "eagle-import:C0603")
      (fields (field (name "PARTNO") "C0603C104K5RACTU"))
      (libsource (lib "eagle-import") (part "C-EUC0603"))
    )
    (comp (ref "C118")
      (value "0.1uF")
      (footprint "eagle-import:C0603")
      (fields (field (name "PARTNO") "C0603C104K5RACTU"))
      (libsource (lib "eagle-import") (part "C-EUC0603"))
    )
    (comp (ref "C119")
      (value "0.1uF")
      (footprint "eagle-import:C0603")
      (fields (field (name "PARTNO") "C0603C104K5RACTU"))
      (libsource (lib "eagle-import") (part "C-EUC0603"))
    )
    (comp (ref "C120")
      (value "0.1uF")
      (footprint "eagle-import:C0603")
      (fields (field (name "PARTNO") "C0603C104K5RACTU"))
      (libsource (lib "eagle-import") (part "C-EUC0603"))
    )
    (comp (ref "C121")
      (value "0.1uF")
      (footprint "eagle-import:C0603")
      (fields (field (name "PARTNO") "C0603C104K5RACTU"))
      (libsource (lib "eagle-import") (part "C-EUC0603"))
    )
    (comp (ref "C122")
      (value "0.1uF")
      (footprint "eagle-import:C0603")
      (fields (field (name "PARTNO") "C0603C104K5RACTU"))
      (libsource (lib "eagle-import") (part "C-EUC0603"))
    )
    (comp (ref "D10")
      (value "TCMT4100")
      (footprint "eagle-import:SO16")
      (fields (field (name "PARTNO") "TCMT4100"))
      (libsource (lib "eagle-import") (part "TCMT4100"))
    )
    (comp (ref "D11")
      (value "TCMT4100")
      (footprint "eagle-import:SO16")
      (fields (field (name "PARTNO") "TCMT4100"))
      (libsource (lib "eagle-import") (part "TCMT4100"))
    )
    (comp (ref "D12")
      (value "TCMT4100")
      (footprint "eagle-import:SO16")
      (fields (field (name "PARTNO") "TCMT4100"))
      (libsource (lib "eagle-import") (part "TCMT4100"))
    )
    (comp (ref "D13")
      (value "TCMT4100")
      (footprint "eagle-import:SO16")
      (fields (field (name "PARTNO") "TCMT4100"))
      (libsource (lib "eagle-import") (part "TCMT4100"))
    )
    (comp (ref "DD8")
      (value "74HC165D")
      (footprint "eagle-import:SO16")
      (fields (field (name "PARTNO") "IN74HC165AD"))
      (libsource (lib "eagle-import") (part "74165DHC"))
    )
    (comp (ref "DD9")
      (value "74HC165D")
      (footprint "eagle-import:SO16")
      (fields (field (name "PARTNO") "IN74HC165AD"))
      (libsource (lib "eagle-import") (part "74165DHC"))
    )
    (comp (ref "R237")
      (value "4.7kOhm/5%")
      (footprint "eagle-import:R1206")
      (fields (field (name "PARTNO") "RC1206JR-074K7L"))
      (libsource (lib "eagle-import") (part "R-EU_R1206"))
    )
    (comp (ref "R238")
      (value "4.7kOhm/5%")
      (footprint "eagle-import:R1206")
      (fields (field (name "PARTNO") "RC1206JR-074K7L"))
      (libsource (lib "eagle-import") (part "R-EU_R1206"))
    )
    (comp (ref "R239")
      (value "4.7kOhm/5%")
      (footprint "eagle-import:R1206")
      (fields (field (name "PARTNO") "RC1206JR-074K7L"))
      (libsource (lib "eagle-import") (part "R-EU_R1206"))
    )
    (comp (ref "R240")
      (value "4.7kOhm/5%")
      (footprint "eagle-import:R1206")
      (fields (field (name "PARTNO") "RC1206JR-074K7L"))
      (libsource (lib "eagle-import") (part "R-EU_R1206"))
    )
    (comp (ref "R241")
      (value "4.7kOhm/5%")
      (footprint "eagle-import:R1206")
      (fields (field (name "PARTNO") "RC1206JR-074K7L"))
      (libsource (lib "eagle-import") (part "R-EU_R1206"))
    )
    (comp (ref "R242")
      (value "4.7kOhm/5%")
      (footprint "eagle-import:R1206")
      (fields (field (name "PARTNO") "RC1206JR-074K7L"))
      (libsource (lib "eagle-import") (part "R-EU_R1206"))
    )
    (comp (ref "R243")
      (value "4.7kOhm/5%")
      (footprint "eagle-import:R1206")
      (fields (field (name "PARTNO") "RC1206JR-074K7L"))
      (libsource (lib "eagle-import") (part "R-EU_R1206"))
    )
    (comp (ref "R244")
      (value "4.7kOhm/5%")
      (footprint "eagle-import:R1206")
      (fields (field (name "PARTNO") "RC1206JR-074K7L"))
      (libsource (lib "eagle-import") (part "R-EU_R1206"))
    )
    (comp (ref "R245")
      (value "4.7kOhm/5%")
      (footprint "eagle-import:R1206")
      (fields (field (name "PARTNO") "RC1206JR-074K7L"))
      (libsource (lib "eagle-import") (part "R-EU_R1206"))
    )
    (comp (ref "R246")
      (value "4.7kOhm/5%")
      (footprint "eagle-import:R1206")
      (fields (field (name "PARTNO") "RC1206JR-074K7L"))
      (libsource (lib "eagle-import") (part "R-EU_R1206"))
    )
    (comp (ref "R247")
      (value "4.7kOhm/5%")
      (footprint "eagle-import:R1206")
      (fields (field (name "PARTNO") "RC1206JR-074K7L"))
      (libsource (lib "eagle-import") (part "R-EU_R1206"))
    )
    (comp (ref "R248")
      (value "4.7kOhm/5%")
      (footprint "eagle-import:R1206")
      (fields (field (name "PARTNO") "RC1206JR-074K7L"))
      (libsource (lib "eagle-import") (part "R-EU_R1206"))
    )
    (comp (ref "R249")
      (value "4.7kOhm/5%")
      (footprint "eagle-import:R1206")
      (fields (field (name "PARTNO") "RC1206JR-074K7L"))
      (libsource (lib "eagle-import") (part "R-EU_R1206"))
    )
    (comp (ref "R250")
      (value "4.7kOhm/5%")
      (footprint "eagle-import:R1206")
      (fields (field (name "PARTNO") "RC1206JR-074K7L"))
      (libsource (lib "eagle-import") (part "R-EU_R1206"))
    )
    (comp (ref "R251")
      (value "4.7kOhm/5%")
      (footprint "eagle-import:R1206")
      (fields (field (name "PARTNO") "RC1206JR-074K7L"))
      (libsource (lib "eagle-import") (part "R-EU_R1206"))
    )
    (comp (ref "R252")
      (value "4.7kOhm/5%")
      (footprint "eagle-import:R1206")
      (fields (field (name "PARTNO") "RC1206JR-074K7L"))
      (libsource (lib "eagle-import") (part "R-EU_R1206"))
    )
    (comp (ref "R253")
      (value "1kOhm/5%")
      (footprint "eagle-import:R2512")
      (fields (field (name "PARTNO") "RC2512JK-071KL"))
      (libsource (lib "eagle-import") (part "R-EU_R2512"))
    )
    (comp (ref "R254")
      (value "1kOhm/5%")
      (footprint "eagle-import:R2512")
      (fields (field (name "PARTNO") "RC2512JK-071KL"))
      (libsource (lib "eagle-import") (part "R-EU_R2512"))
    )
    (comp (ref "R255")
      (value "1kOhm/5%")
      (footprint "eagle-import:R2512")
      (fields (field (name "PARTNO") "RC2512JK-071KL"))
      (libsource (lib "eagle-import") (part "R-EU_R2512"))
    )
    (comp (ref "R256")
      (value "1kOhm/5%")
      (footprint "eagle-import:R2512")
      (fields (field (name "PARTNO") "RC2512JK-071KL"))
      (libsource (lib "eagle-import") (part "R-EU_R2512"))
    )
    (comp (ref "R257")
      (value "1kOhm/5%")
      (footprint "eagle-import:R2512")
      (fields (field (name "PARTNO") "RC2512JK-071KL"))
      (libsource (lib "eagle-import") (part "R-EU_R2512"))
    )
    (comp (ref "R258")
      (value "1kOhm/5%")
      (footprint "eagle-import:R2512")
      (fields (field (name "PARTNO") "RC2512JK-071KL"))
      (libsource (lib "eagle-import") (part "R-EU_R2512"))
    )
    (comp (ref "R259")
      (value "1kOhm/5%")
      (footprint "eagle-import:R2512")
      (fields (field (name "PARTNO") "RC2512JK-071KL"))
      (libsource (lib "eagle-import") (part "R-EU_R2512"))
    )
    (comp (ref "R260")
      (value "1kOhm/5%")
      (footprint "eagle-import:R2512")
      (fields (field (name "PARTNO") "RC2512JK-071KL"))
      (libsource (lib "eagle-import") (part "R-EU_R2512"))
    )
    (comp (ref "R261")
      (value "1kOhm/5%")
      (footprint "eagle-import:R2512")
      (fields (field (name "PARTNO") "RC2512JK-071KL"))
      (libsource (lib "eagle-import") (part "R-EU_R2512"))
    )
    (comp (ref "R262")
      (value "1kOhm/5%")
      (footprint "eagle-import:R2512")
      (fields (field (name "PARTNO") "RC2512JK-071KL"))
      (libsource (lib "eagle-import") (part "R-EU_R2512"))
    )
    (comp (ref "R263")
      (value "1kOhm/5%")
      (footprint "eagle-import:R2512")
      (fields (field (name "PARTNO") "RC2512JK-071KL"))
      (libsource (lib "eagle-import") (part "R-EU_R2512"))
    )
    (comp (ref "R264")
      (value "1kOhm/5%")
      (footprint "eagle-import:R2512")
      (fields (field (name "PARTNO") "RC2512JK-071KL"))
      (libsource (lib "eagle-import") (part "R-EU_R2512"))
    )
    (comp (ref "R265")
      (value "1kOhm/5%")
      (footprint "eagle-import:R2512")
      (fields (field (name "PARTNO") "RC2512JK-071KL"))
      (libsource (lib "eagle-import") (part "R-EU_R2512"))
    )
    (comp (ref "R266")
      (value "1kOhm/5%")
      (footprint "eagle-import:R2512")
      (fields (field (name "PARTNO") "RC2512JK-071KL"))
      (libsource (lib "eagle-import") (part "R-EU_R2512"))
    )
    (comp (ref "R267")
      (value "1kOhm/5%")
      (footprint "eagle-import:R2512")
      (fields (field (name "PARTNO") "RC2512JK-071KL"))
      (libsource (lib "eagle-import") (part "R-EU_R2512"))
    )
    (comp (ref "R268")
      (value "1kOhm/5%")
      (footprint "eagle-import:R2512")
      (fields (field (name "PARTNO") "RC2512JK-071KL"))
      (libsource (lib "eagle-import") (part "R-EU_R2512"))
    )
    (comp (ref "R269")
      (value "10kOhm/1%")
      (footprint "eagle-import:R0603")
      (fields (field (name "PARTNO") "RC0603FR-1010KL"))
      (libsource (lib "eagle-import") (part "R-EU_R0603"))
    )
    (comp (ref "R270")
      (value "10kOhm/1%")
      (footprint "eagle-import:R0603")
      (fields (field (name "PARTNO") "RC0603FR-1010KL"))
      (libsource (lib "eagle-import") (part "R-EU_R0603"))
    )
    (comp (ref "R271")
      (value "10kOhm/1%")
      (footprint "eagle-import:R0603")
      (fields (field (name "PARTNO") "RC0603FR-1010KL"))
      (libsource (lib "eagle-import") (part "R-EU_R0603"))
    )
    (comp (ref "R272")
      (value "10kOhm/1%")
      (footprint "eagle-import:R0603")
      (fields (field (name "PARTNO") "RC0603FR-1010KL"))
      (libsource (lib "eagle-import") (part "R-EU_R0603"))
    )
    (comp (ref "R273")
      (value "10kOhm/1%")
      (footprint "eagle-import:R0603")
      (fields (field (name "PARTNO") "RC0603FR-1010KL"))
      (libsource (lib "eagle-import") (part "R-EU_R0603"))
    )
    (comp (ref "R274")
      (value "10kOhm/1%")
      (footprint "eagle-import:R0603")
      (fields (field (name "PARTNO") "RC0603FR-1010KL"))
      (libsource (lib "eagle-import") (part "R-EU_R0603"))
    )
    (comp (ref "R275")
      (value "10kOhm/1%")
      (footprint "eagle-import:R0603")
      (fields (field (name "PARTNO") "RC0603FR-1010KL"))
      (libsource (lib "eagle-import") (part "R-EU_R0603"))
    )
    (comp (ref "R276")
      (value "10kOhm/1%")
      (footprint "eagle-import:R0603")
      (fields (field (name "PARTNO") "RC0603FR-1010KL"))
      (libsource (lib "eagle-import") (part "R-EU_R0603"))
    )
    (comp (ref "R277")
      (value "10kOhm/1%")
      (footprint "eagle-import:R0603")
      (fields (field (name "PARTNO") "RC0603FR-1010KL"))
      (libsource (lib "eagle-import") (part "R-EU_R0603"))
    )
    (comp (ref "R278")
      (value "10kOhm/1%")
      (footprint "eagle-import:R0603")
      (fields (field (name "PARTNO") "RC0603FR-1010KL"))
      (libsource (lib "eagle-import") (part "R-EU_R0603"))
    )
    (comp (ref "R279")
      (value "10kOhm/1%")
      (footprint "eagle-import:R0603")
      (fields (field (name "PARTNO") "RC0603FR-1010KL"))
      (libsource (lib "eagle-import") (part "R-EU_R0603"))
    )
    (comp (ref "R280")
      (value "10kOhm/1%")
      (footprint "eagle-import:R0603")
      (fields (field (name "PARTNO") "RC0603FR-1010KL"))
      (libsource (lib "eagle-import") (part "R-EU_R0603"))
    )
    (comp (ref "R281")
      (value "10kOhm/1%")
      (footprint "eagle-import:R0603")
      (fields (field (name "PARTNO") "RC0603FR-1010KL"))
      (libsource (lib "eagle-import") (part "R-EU_R0603"))
    )
    (comp (ref "R282")
      (value "10kOhm/1%")
      (footprint "eagle-import:R0603")
      (fields (field (name "PARTNO") "RC0603FR-1010KL"))
      (libsource (lib "eagle-import") (part "R-EU_R0603"))
    )
    (comp (ref "R283")
      (value "10kOhm/1%")
      (footprint "eagle-import:R0603")
      (fields (field (name "PARTNO") "RC0603FR-1010KL"))
      (libsource (lib "eagle-import") (part "R-EU_R0603"))
    )
    (comp (ref "R284")
      (value "10kOhm/1%")
      (footprint "eagle-import:R0603")
      (fields (field (name "PARTNO") "RC0603FR-1010KL"))
      (libsource (lib "eagle-import") (part "R-EU_R0603"))
    )
    (comp (ref "VD132")
      (value "SM6T200A")
      (footprint "eagle-import:SMB")
      (libsource (lib "eagle-import") (part "DIODE-TVS-UNIDIR-SMB"))
    )
    (comp (ref "VD133")
      (value "SM6T200A")
      (footprint "eagle-import:SMB")
      (libsource (lib "eagle-import") (part "DIODE-TVS-UNIDIR-SMB"))
    )
    (comp (ref "VD134")
      (value "SM6T200A")
      (footprint "eagle-import:SMB")
      (libsource (lib "eagle-import") (part "DIODE-TVS-UNIDIR-SMB"))
    )
    (comp (ref "VD135")
      (value "SM6T200A")
      (footprint "eagle-import:SMB")
      (libsource (lib "eagle-import") (part "DIODE-TVS-UNIDIR-SMB"))
    )
    (comp (ref "VD136")
      (value "SM6T200A")
      (footprint "eagle-import:SMB")
      (libsource (lib "eagle-import") (part "DIODE-TVS-UNIDIR-SMB"))
    )
    (comp (ref "VD137")
      (value "SM6T200A")
      (footprint "eagle-import:SMB")
      (libsource (lib "eagle-import") (part "DIODE-TVS-UNIDIR-SMB"))
    )
    (comp (ref "VD138")
      (value "SM6T200A")
      (footprint "eagle-import:SMB")
      (libsource (lib "eagle-import") (part "DIODE-TVS-UNIDIR-SMB"))
    )
    (comp (ref "VD139")
      (value "SM6T200A")
      (footprint "eagle-import:SMB")
      (libsource (lib "eagle-import") (part "DIODE-TVS-UNIDIR-SMB"))
    )
    (comp (ref "VD140")
      (value "SM6T200A")
      (footprint "eagle-import:SMB")
      (libsource (lib "eagle-import") (part "DIODE-TVS-UNIDIR-SMB"))
    )
    (comp (ref "VD141")
      (value "SM6T200A")
      (footprint "eagle-import:SMB")
      (libsource (lib "eagle-import") (part "DIODE-TVS-UNIDIR-SMB"))
    )
    (comp (ref "VD142")
      (value "SM6T200A")
      (footprint "eagle-import:SMB")
      (libsource (lib "eagle-import") (part "DIODE-TVS-UNIDIR-SMB"))
    )
    (comp (ref "VD143")
      (value "SM6T200A")
      (footprint "eagle-import:SMB")
      (libsource (lib "eagle-import") (part "DIODE-TVS-UNIDIR-SMB"))
    )
    (comp (ref "VD144")
      (value "SM6T200A")
      (footprint "eagle-import:SMB")
      (libsource (lib "eagle-import") (part "DIODE-TVS-UNIDIR-SMB"))
    )
    (comp (ref "VD145")
      (value "SM6T200A")
      (footprint "eagle-import:SMB")
      (libsource (lib "eagle-import") (part "DIODE-TVS-UNIDIR-SMB"))
    )
    (comp (ref "VD146")
      (value "SM6T200A")
      (footprint "eagle-import:SMB")
      (libsource (lib "eagle-import") (part "DIODE-TVS-UNIDIR-SMB"))
    )
    (comp (ref "VD147")
      (value "SM6T200A")
      (footprint "eagle-import:SMB")
      (libsource (lib "eagle-import") (part "DIODE-TVS-UNIDIR-SMB"))
    )
    (comp (ref "VD148")
      (value "400V")
      (footprint "eagle-import:SMA")
      (fields (field (name "PARTNO") "S1G-E3/61T"))
      (libsource (lib "eagle-import") (part "DIODE-STANDARD-SMA"))
    )
    (comp (ref "VD149")
      (value "400V")
      (footprint "eagle-import:SMA")
      (fields (field (name "PARTNO") "S1G-E3/61T"))
      (libsource (lib "eagle-import") (part "DIODE-STANDARD-SMA"))
    )
    (comp (ref "VD150")
      (value "400V")
      (footprint "eagle-import:SMA")
      (fields (field (name "PARTNO") "S1G-E3/61T"))
      (libsource (lib "eagle-import") (part "DIODE-STANDARD-SMA"))
    )
    (comp (ref "VD151")
      (value "400V")
      (footprint "eagle-import:SMA")
      (fields (field (name "PARTNO") "S1G-E3/61T"))
      (libsource (lib "eagle-import") (part "DIODE-STANDARD-SMA"))
    )
    (comp (ref "VD152")
      (value "400V")
      (footprint "eagle-import:SMA")
      (fields (field (name "PARTNO") "S1G-E3/61T"))
      (libsource (lib "eagle-import") (part "DIODE-STANDARD-SMA"))
    )
    (comp (ref "VD153")
      (value "400V")
      (footprint "eagle-import:SMA")
      (fields (field (name "PARTNO") "S1G-E3/61T"))
      (libsource (lib "eagle-import") (part "DIODE-STANDARD-SMA"))
    )
    (comp (ref "VD154")
      (value "400V")
      (footprint "eagle-import:SMA")
      (fields (field (name "PARTNO") "S1G-E3/61T"))
      (libsource (lib "eagle-import") (part "DIODE-STANDARD-SMA"))
    )
    (comp (ref "VD155")
      (value "400V")
      (footprint "eagle-import:SMA")
      (fields (field (name "PARTNO") "S1G-E3/61T"))
      (libsource (lib "eagle-import") (part "DIODE-STANDARD-SMA"))
    )
    (comp (ref "VD156")
      (value "400V")
      (footprint "eagle-import:SMA")
      (fields (field (name "PARTNO") "S1G-E3/61T"))
      (libsource (lib "eagle-import") (part "DIODE-STANDARD-SMA"))
    )
    (comp (ref "VD157")
      (value "400V")
      (footprint "eagle-import:SMA")
      (fields (field (name "PARTNO") "S1G-E3/61T"))
      (libsource (lib "eagle-import") (part "DIODE-STANDARD-SMA"))
    )
    (comp (ref "VD158")
      (value "400V")
      (footprint "eagle-import:SMA")
      (fields (field (name "PARTNO") "S1G-E3/61T"))
      (libsource (lib "eagle-import") (part "DIODE-STANDARD-SMA"))
    )
    (comp (ref "VD159")
      (value "400V")
      (footprint "eagle-import:SMA")
      (fields (field (name "PARTNO") "S1G-E3/61T"))
      (libsource (lib "eagle-import") (part "DIODE-STANDARD-SMA"))
    )
    (comp (ref "VD160")
      (value "400V")
      (footprint "eagle-import:SMA")
      (fields (field (name "PARTNO") "S1G-E3/61T"))
      (libsource (lib "eagle-import") (part "DIODE-STANDARD-SMA"))
    )
    (comp (ref "VD161")
      (value "400V")
      (footprint "eagle-import:SMA")
      (fields (field (name "PARTNO") "S1G-E3/61T"))
      (libsource (lib "eagle-import") (part "DIODE-STANDARD-SMA"))
    )
    (comp (ref "VD162")
      (value "400V")
      (footprint "eagle-import:SMA")
      (fields (field (name "PARTNO") "S1G-E3/61T"))
      (libsource (lib "eagle-import") (part "DIODE-STANDARD-SMA"))
    )
    (comp (ref "VD163")
      (value "400V")
      (footprint "eagle-import:SMA")
      (fields (field (name "PARTNO") "S1G-E3/61T"))
      (libsource (lib "eagle-import") (part "DIODE-STANDARD-SMA"))
    )
    (comp (ref "XP9")
      (value "MOLEX-90130-16")
      (footprint "eagle-import:MOLEX-90130-16")
      (fields (field (name "PARTNO") "90130-1216"))
      (libsource (lib "eagle-import") (part "MOLEX-90130-16"))
    )
    (comp (ref "C69")
      (value "0.1uF")
      (footprint "eagle-import:C0603")
      (fields (field (name "PARTNO") "C0603C104K5RACTU"))
      (libsource (lib "eagle-import") (part "C-EUC0603"))
    )
    (comp (ref "C70")
      (value "0.1uF")
      (footprint "eagle-import:C0603")
      (fields (field (name "PARTNO") "C0603C104K5RACTU"))
      (libsource (lib "eagle-import") (part "C-EUC0603"))
    )
    (comp (ref "C71")
      (value "0.1uF")
      (footprint "eagle-import:C0603")
      (fields (field (name "PARTNO") "C0603C104K5RACTU"))
      (libsource (lib "eagle-import") (part "C-EUC0603"))
    )
    (comp (ref "C72")
      (value "0.1uF")
      (footprint "eagle-import:C0603")
      (fields (field (name "PARTNO") "C0603C104K5RACTU"))
      (libsource (lib "eagle-import") (part "C-EUC0603"))
    )
    (comp (ref "C73")
      (value "0.1uF")
      (footprint "eagle-import:C0603")
      (fields (field (name "PARTNO") "C0603C104K5RACTU"))
      (libsource (lib "eagle-import") (part "C-EUC0603"))
    )
    (comp (ref "C74")
      (value "0.1uF")
      (footprint "eagle-import:C0603")
      (fields (field (name "PARTNO") "C0603C104K5RACTU"))
      (libsource (lib "eagle-import") (part "C-EUC0603"))
    )
    (comp (ref "C75")
      (value "0.1uF")
      (footprint "eagle-import:C0603")
      (fields (field (name "PARTNO") "C0603C104K5RACTU"))
      (libsource (lib "eagle-import") (part "C-EUC0603"))
    )
    (comp (ref "C76")
      (value "0.1uF")
      (footprint "eagle-import:C0603")
      (fields (field (name "PARTNO") "C0603C104K5RACTU"))
      (libsource (lib "eagle-import") (part "C-EUC0603"))
    )
    (comp (ref "C77")
      (value "0.1uF")
      (footprint "eagle-import:C0603")
      (fields (field (name "PARTNO") "C0603C104K5RACTU"))
      (libsource (lib "eagle-import") (part "C-EUC0603"))
    )
    (comp (ref "C78")
      (value "0.1uF")
      (footprint "eagle-import:C0603")
      (fields (field (name "PARTNO") "C0603C104K5RACTU"))
      (libsource (lib "eagle-import") (part "C-EUC0603"))
    )
    (comp (ref "C79")
      (value "0.1uF")
      (footprint "eagle-import:C0603")
      (fields (field (name "PARTNO") "C0603C104K5RACTU"))
      (libsource (lib "eagle-import") (part "C-EUC0603"))
    )
    (comp (ref "C80")
      (value "0.1uF")
      (footprint "eagle-import:C0603")
      (fields (field (name "PARTNO") "C0603C104K5RACTU"))
      (libsource (lib "eagle-import") (part "C-EUC0603"))
    )
    (comp (ref "C81")
      (value "0.1uF")
      (footprint "eagle-import:C0603")
      (fields (field (name "PARTNO") "C0603C104K5RACTU"))
      (libsource (lib "eagle-import") (part "C-EUC0603"))
    )
    (comp (ref "C82")
      (value "0.1uF")
      (footprint "eagle-import:C0603")
      (fields (field (name "PARTNO") "C0603C104K5RACTU"))
      (libsource (lib "eagle-import") (part "C-EUC0603"))
    )
    (comp (ref "C83")
      (value "0.1uF")
      (footprint "eagle-import:C0603")
      (fields (field (name "PARTNO") "C0603C104K5RACTU"))
      (libsource (lib "eagle-import") (part "C-EUC0603"))
    )
    (comp (ref "C84")
      (value "0.1uF")
      (footprint "eagle-import:C0603")
      (fields (field (name "PARTNO") "C0603C104K5RACTU"))
      (libsource (lib "eagle-import") (part "C-EUC0603"))
    )
    (comp (ref "C85")
      (value "0.1uF")
      (footprint "eagle-import:C0603")
      (fields (field (name "PARTNO") "C0603C104K5RACTU"))
      (libsource (lib "eagle-import") (part "C-EUC0603"))
    )
    (comp (ref "C86")
      (value "0.1uF")
      (footprint "eagle-import:C0603")
      (fields (field (name "PARTNO") "C0603C104K5RACTU"))
      (libsource (lib "eagle-import") (part "C-EUC0603"))
    )
    (comp (ref "D1")
      (value "TCMT4100")
      (footprint "eagle-import:SO16")
      (fields (field (name "PARTNO") "TCMT4100"))
      (libsource (lib "eagle-import") (part "TCMT4100"))
    )
    (comp (ref "D2")
      (value "TCMT4100")
      (footprint "eagle-import:SO16")
      (fields (field (name "PARTNO") "TCMT4100"))
      (libsource (lib "eagle-import") (part "TCMT4100"))
    )
    (comp (ref "D3")
      (value "TCMT4100")
      (footprint "eagle-import:SO16")
      (fields (field (name "PARTNO") "TCMT4100"))
      (libsource (lib "eagle-import") (part "TCMT4100"))
    )
    (comp (ref "D4")
      (value "TCMT4100")
      (footprint "eagle-import:SO16")
      (fields (field (name "PARTNO") "TCMT4100"))
      (libsource (lib "eagle-import") (part "TCMT4100"))
    )
    (comp (ref "D5")
      (value "AUIPS7111S")
      (footprint "eagle-import:TO252-5-11")
      (libsource (lib "eagle-import") (part "AUIPS7111S"))
    )
    (comp (ref "DD4")
      (value "74HC165D")
      (footprint "eagle-import:SO16")
      (fields (field (name "PARTNO") "IN74HC165AD"))
      (libsource (lib "eagle-import") (part "74165DHC"))
    )
    (comp (ref "DD5")
      (value "74HC165D")
      (footprint "eagle-import:SO16")
      (fields (field (name "PARTNO") "IN74HC165AD"))
      (libsource (lib "eagle-import") (part "74165DHC"))
    )
    (comp (ref "R138")
      (value "4.7kOhm/5%")
      (footprint "eagle-import:R1206")
      (fields (field (name "PARTNO") "RC1206JR-074K7L"))
      (libsource (lib "eagle-import") (part "R-EU_R1206"))
    )
    (comp (ref "R139")
      (value "4.7kOhm/5%")
      (footprint "eagle-import:R1206")
      (fields (field (name "PARTNO") "RC1206JR-074K7L"))
      (libsource (lib "eagle-import") (part "R-EU_R1206"))
    )
    (comp (ref "R140")
      (value "4.7kOhm/5%")
      (footprint "eagle-import:R1206")
      (fields (field (name "PARTNO") "RC1206JR-074K7L"))
      (libsource (lib "eagle-import") (part "R-EU_R1206"))
    )
    (comp (ref "R141")
      (value "4.7kOhm/5%")
      (footprint "eagle-import:R1206")
      (fields (field (name "PARTNO") "RC1206JR-074K7L"))
      (libsource (lib "eagle-import") (part "R-EU_R1206"))
    )
    (comp (ref "R142")
      (value "4.7kOhm/5%")
      (footprint "eagle-import:R1206")
      (fields (field (name "PARTNO") "RC1206JR-074K7L"))
      (libsource (lib "eagle-import") (part "R-EU_R1206"))
    )
    (comp (ref "R143")
      (value "4.7kOhm/5%")
      (footprint "eagle-import:R1206")
      (fields (field (name "PARTNO") "RC1206JR-074K7L"))
      (libsource (lib "eagle-import") (part "R-EU_R1206"))
    )
    (comp (ref "R144")
      (value "4.7kOhm/5%")
      (footprint "eagle-import:R1206")
      (fields (field (name "PARTNO") "RC1206JR-074K7L"))
      (libsource (lib "eagle-import") (part "R-EU_R1206"))
    )
    (comp (ref "R145")
      (value "4.7kOhm/5%")
      (footprint "eagle-import:R1206")
      (fields (field (name "PARTNO") "RC1206JR-074K7L"))
      (libsource (lib "eagle-import") (part "R-EU_R1206"))
    )
    (comp (ref "R146")
      (value "4.7kOhm/5%")
      (footprint "eagle-import:R1206")
      (fields (field (name "PARTNO") "RC1206JR-074K7L"))
      (libsource (lib "eagle-import") (part "R-EU_R1206"))
    )
    (comp (ref "R147")
      (value "4.7kOhm/5%")
      (footprint "eagle-import:R1206")
      (fields (field (name "PARTNO") "RC1206JR-074K7L"))
      (libsource (lib "eagle-import") (part "R-EU_R1206"))
    )
    (comp (ref "R148")
      (value "4.7kOhm/5%")
      (footprint "eagle-import:R1206")
      (fields (field (name "PARTNO") "RC1206JR-074K7L"))
      (libsource (lib "eagle-import") (part "R-EU_R1206"))
    )
    (comp (ref "R149")
      (value "4.7kOhm/5%")
      (footprint "eagle-import:R1206")
      (fields (field (name "PARTNO") "RC1206JR-074K7L"))
      (libsource (lib "eagle-import") (part "R-EU_R1206"))
    )
    (comp (ref "R150")
      (value "4.7kOhm/5%")
      (footprint "eagle-import:R1206")
      (fields (field (name "PARTNO") "RC1206JR-074K7L"))
      (libsource (lib "eagle-import") (part "R-EU_R1206"))
    )
    (comp (ref "R151")
      (value "4.7kOhm/5%")
      (footprint "eagle-import:R1206")
      (fields (field (name "PARTNO") "RC1206JR-074K7L"))
      (libsource (lib "eagle-import") (part "R-EU_R1206"))
    )
    (comp (ref "R152")
      (value "4.7kOhm/5%")
      (footprint "eagle-import:R1206")
      (fields (field (name "PARTNO") "RC1206JR-074K7L"))
      (libsource (lib "eagle-import") (part "R-EU_R1206"))
    )
    (comp (ref "R153")
      (value "4.7kOhm/5%")
      (footprint "eagle-import:R1206")
      (fields (field (name "PARTNO") "RC1206JR-074K7L"))
      (libsource (lib "eagle-import") (part "R-EU_R1206"))
    )
    (comp (ref "R154")
      (value "1kOhm/5%")
      (footprint "eagle-import:R2512")
      (fields (field (name "PARTNO") "RC2512JK-071KL"))
      (libsource (lib "eagle-import") (part "R-EU_R2512"))
    )
    (comp (ref "R155")
      (value "1kOhm/5%")
      (footprint "eagle-import:R2512")
      (fields (field (name "PARTNO") "RC2512JK-071KL"))
      (libsource (lib "eagle-import") (part "R-EU_R2512"))
    )
    (comp (ref "R156")
      (value "1kOhm/5%")
      (footprint "eagle-import:R2512")
      (fields (field (name "PARTNO") "RC2512JK-071KL"))
      (libsource (lib "eagle-import") (part "R-EU_R2512"))
    )
    (comp (ref "R157")
      (value "1kOhm/5%")
      (footprint "eagle-import:R2512")
      (fields (field (name "PARTNO") "RC2512JK-071KL"))
      (libsource (lib "eagle-import") (part "R-EU_R2512"))
    )
    (comp (ref "R158")
      (value "1kOhm/5%")
      (footprint "eagle-import:R2512")
      (fields (field (name "PARTNO") "RC2512JK-071KL"))
      (libsource (lib "eagle-import") (part "R-EU_R2512"))
    )
    (comp (ref "R159")
      (value "1kOhm/5%")
      (footprint "eagle-import:R2512")
      (fields (field (name "PARTNO") "RC2512JK-071KL"))
      (libsource (lib "eagle-import") (part "R-EU_R2512"))
    )
    (comp (ref "R160")
      (value "1kOhm/5%")
      (footprint "eagle-import:R2512")
      (fields (field (name "PARTNO") "RC2512JK-071KL"))
      (libsource (lib "eagle-import") (part "R-EU_R2512"))
    )
    (comp (ref "R161")
      (value "1kOhm/5%")
      (footprint "eagle-import:R2512")
      (fields (field (name "PARTNO") "RC2512JK-071KL"))
      (libsource (lib "eagle-import") (part "R-EU_R2512"))
    )
    (comp (ref "R162")
      (value "1kOhm/5%")
      (footprint "eagle-import:R2512")
      (fields (field (name "PARTNO") "RC2512JK-071KL"))
      (libsource (lib "eagle-import") (part "R-EU_R2512"))
    )
    (comp (ref "R163")
      (value "1kOhm/5%")
      (footprint "eagle-import:R2512")
      (fields (field (name "PARTNO") "RC2512JK-071KL"))
      (libsource (lib "eagle-import") (part "R-EU_R2512"))
    )
    (comp (ref "R164")
      (value "1kOhm/5%")
      (footprint "eagle-import:R2512")
      (fields (field (name "PARTNO") "RC2512JK-071KL"))
      (libsource (lib "eagle-import") (part "R-EU_R2512"))
    )
    (comp (ref "R165")
      (value "1kOhm/5%")
      (footprint "eagle-import:R2512")
      (fields (field (name "PARTNO") "RC2512JK-071KL"))
      (libsource (lib "eagle-import") (part "R-EU_R2512"))
    )
    (comp (ref "R166")
      (value "1kOhm/5%")
      (footprint "eagle-import:R2512")
      (fields (field (name "PARTNO") "RC2512JK-071KL"))
      (libsource (lib "eagle-import") (part "R-EU_R2512"))
    )
    (comp (ref "R167")
      (value "1kOhm/5%")
      (footprint "eagle-import:R2512")
      (fields (field (name "PARTNO") "RC2512JK-071KL"))
      (libsource (lib "eagle-import") (part "R-EU_R2512"))
    )
    (comp (ref "R168")
      (value "1kOhm/5%")
      (footprint "eagle-import:R2512")
      (fields (field (name "PARTNO") "RC2512JK-071KL"))
      (libsource (lib "eagle-import") (part "R-EU_R2512"))
    )
    (comp (ref "R169")
      (value "1kOhm/5%")
      (footprint "eagle-import:R2512")
      (fields (field (name "PARTNO") "RC2512JK-071KL"))
      (libsource (lib "eagle-import") (part "R-EU_R2512"))
    )
    (comp (ref "R170")
      (value "10kOhm/1%")
      (footprint "eagle-import:R0603")
      (fields (field (name "PARTNO") "RC0603FR-1010KL"))
      (libsource (lib "eagle-import") (part "R-EU_R0603"))
    )
    (comp (ref "R171")
      (value "10kOhm/1%")
      (footprint "eagle-import:R0603")
      (fields (field (name "PARTNO") "RC0603FR-1010KL"))
      (libsource (lib "eagle-import") (part "R-EU_R0603"))
    )
    (comp (ref "R172")
      (value "10kOhm/1%")
      (footprint "eagle-import:R0603")
      (fields (field (name "PARTNO") "RC0603FR-1010KL"))
      (libsource (lib "eagle-import") (part "R-EU_R0603"))
    )
    (comp (ref "R173")
      (value "10kOhm/1%")
      (footprint "eagle-import:R0603")
      (fields (field (name "PARTNO") "RC0603FR-1010KL"))
      (libsource (lib "eagle-import") (part "R-EU_R0603"))
    )
    (comp (ref "R174")
      (value "10kOhm/1%")
      (footprint "eagle-import:R0603")
      (fields (field (name "PARTNO") "RC0603FR-1010KL"))
      (libsource (lib "eagle-import") (part "R-EU_R0603"))
    )
    (comp (ref "R175")
      (value "10kOhm/1%")
      (footprint "eagle-import:R0603")
      (fields (field (name "PARTNO") "RC0603FR-1010KL"))
      (libsource (lib "eagle-import") (part "R-EU_R0603"))
    )
    (comp (ref "R176")
      (value "10kOhm/1%")
      (footprint "eagle-import:R0603")
      (fields (field (name "PARTNO") "RC0603FR-1010KL"))
      (libsource (lib "eagle-import") (part "R-EU_R0603"))
    )
    (comp (ref "R177")
      (value "10kOhm/1%")
      (footprint "eagle-import:R0603")
      (fields (field (name "PARTNO") "RC0603FR-1010KL"))
      (libsource (lib "eagle-import") (part "R-EU_R0603"))
    )
    (comp (ref "R178")
      (value "10kOhm/1%")
      (footprint "eagle-import:R0603")
      (fields (field (name "PARTNO") "RC0603FR-1010KL"))
      (libsource (lib "eagle-import") (part "R-EU_R0603"))
    )
    (comp (ref "R179")
      (value "10kOhm/1%")
      (footprint "eagle-import:R0603")
      (fields (field (name "PARTNO") "RC0603FR-1010KL"))
      (libsource (lib "eagle-import") (part "R-EU_R0603"))
    )
    (comp (ref "R180")
      (value "10kOhm/1%")
      (footprint "eagle-import:R0603")
      (fields (field (name "PARTNO") "RC0603FR-1010KL"))
      (libsource (lib "eagle-import") (part "R-EU_R0603"))
    )
    (comp (ref "R181")
      (value "10kOhm/1%")
      (footprint "eagle-import:R0603")
      (fields (field (name "PARTNO") "RC0603FR-1010KL"))
      (libsource (lib "eagle-import") (part "R-EU_R0603"))
    )
    (comp (ref "R182")
      (value "10kOhm/1%")
      (footprint "eagle-import:R0603")
      (fields (field (name "PARTNO") "RC0603FR-1010KL"))
      (libsource (lib "eagle-import") (part "R-EU_R0603"))
    )
    (comp (ref "R183")
      (value "10kOhm/1%")
      (footprint "eagle-import:R0603")
      (fields (field (name "PARTNO") "RC0603FR-1010KL"))
      (libsource (lib "eagle-import") (part "R-EU_R0603"))
    )
    (comp (ref "R184")
      (value "10kOhm/1%")
      (footprint "eagle-import:R0603")
      (fields (field (name "PARTNO") "RC0603FR-1010KL"))
      (libsource (lib "eagle-import") (part "R-EU_R0603"))
    )
    (comp (ref "R185")
      (value "10kOhm/1%")
      (footprint "eagle-import:R0603")
      (fields (field (name "PARTNO") "RC0603FR-1010KL"))
      (libsource (lib "eagle-import") (part "R-EU_R0603"))
    )
    (comp (ref "R186")
      (value "1kOhm/5%")
      (footprint "eagle-import:R0805")
      (fields (field (name "PARTNO") "ERJ6GEYJ102V"))
      (libsource (lib "eagle-import") (part "R-EU_R0805"))
    )
    (comp (ref "R187")
      (value "1kOhm/5%")
      (footprint "eagle-import:R0805")
      (fields (field (name "PARTNO") "ERJ6GEYJ102V"))
      (libsource (lib "eagle-import") (part "R-EU_R0805"))
    )
    (comp (ref "R188")
      (value "10kOhm/1%")
      (footprint "eagle-import:R0603")
      (fields (field (name "PARTNO") "RC0603FR-1010KL"))
      (libsource (lib "eagle-import") (part "R-EU_R0603"))
    )
    (comp (ref "VD66")
      (value "SM6T200A")
      (footprint "eagle-import:SMB")
      (libsource (lib "eagle-import") (part "DIODE-TVS-UNIDIR-SMB"))
    )
    (comp (ref "VD67")
      (value "SM6T200A")
      (footprint "eagle-import:SMB")
      (libsource (lib "eagle-import") (part "DIODE-TVS-UNIDIR-SMB"))
    )
    (comp (ref "VD68")
      (value "SM6T200A")
      (footprint "eagle-import:SMB")
      (libsource (lib "eagle-import") (part "DIODE-TVS-UNIDIR-SMB"))
    )
    (comp (ref "VD69")
      (value "SM6T200A")
      (footprint "eagle-import:SMB")
      (libsource (lib "eagle-import") (part "DIODE-TVS-UNIDIR-SMB"))
    )
    (comp (ref "VD70")
      (value "SM6T200A")
      (footprint "eagle-import:SMB")
      (libsource (lib "eagle-import") (part "DIODE-TVS-UNIDIR-SMB"))
    )
    (comp (ref "VD71")
      (value "SM6T200A")
      (footprint "eagle-import:SMB")
      (libsource (lib "eagle-import") (part "DIODE-TVS-UNIDIR-SMB"))
    )
    (comp (ref "VD72")
      (value "SM6T200A")
      (footprint "eagle-import:SMB")
      (libsource (lib "eagle-import") (part "DIODE-TVS-UNIDIR-SMB"))
    )
    (comp (ref "VD73")
      (value "SM6T200A")
      (footprint "eagle-import:SMB")
      (libsource (lib "eagle-import") (part "DIODE-TVS-UNIDIR-SMB"))
    )
    (comp (ref "VD74")
      (value "SM6T200A")
      (footprint "eagle-import:SMB")
      (libsource (lib "eagle-import") (part "DIODE-TVS-UNIDIR-SMB"))
    )
    (comp (ref "VD75")
      (value "SM6T200A")
      (footprint "eagle-import:SMB")
      (libsource (lib "eagle-import") (part "DIODE-TVS-UNIDIR-SMB"))
    )
    (comp (ref "VD76")
      (value "SM6T200A")
      (footprint "eagle-import:SMB")
      (libsource (lib "eagle-import") (part "DIODE-TVS-UNIDIR-SMB"))
    )
    (comp (ref "VD77")
      (value "SM6T200A")
      (footprint "eagle-import:SMB")
      (libsource (lib "eagle-import") (part "DIODE-TVS-UNIDIR-SMB"))
    )
    (comp (ref "VD78")
      (value "SM6T200A")
      (footprint "eagle-import:SMB")
      (libsource (lib "eagle-import") (part "DIODE-TVS-UNIDIR-SMB"))
    )
    (comp (ref "VD79")
      (value "SM6T200A")
      (footprint "eagle-import:SMB")
      (libsource (lib "eagle-import") (part "DIODE-TVS-UNIDIR-SMB"))
    )
    (comp (ref "VD80")
      (value "SM6T200A")
      (footprint "eagle-import:SMB")
      (libsource (lib "eagle-import") (part "DIODE-TVS-UNIDIR-SMB"))
    )
    (comp (ref "VD81")
      (value "SM6T200A")
      (footprint "eagle-import:SMB")
      (libsource (lib "eagle-import") (part "DIODE-TVS-UNIDIR-SMB"))
    )
    (comp (ref "VD82")
      (value "400V")
      (footprint "eagle-import:SMA")
      (fields (field (name "PARTNO") "S1G-E3/61T"))
      (libsource (lib "eagle-import") (part "DIODE-STANDARD-SMA"))
    )
    (comp (ref "VD83")
      (value "400V")
      (footprint "eagle-import:SMA")
      (fields (field (name "PARTNO") "S1G-E3/61T"))
      (libsource (lib "eagle-import") (part "DIODE-STANDARD-SMA"))
    )
    (comp (ref "VD84")
      (value "400V")
      (footprint "eagle-import:SMA")
      (fields (field (name "PARTNO") "S1G-E3/61T"))
      (libsource (lib "eagle-import") (part "DIODE-STANDARD-SMA"))
    )
    (comp (ref "VD85")
      (value "400V")
      (footprint "eagle-import:SMA")
      (fields (field (name "PARTNO") "S1G-E3/61T"))
      (libsource (lib "eagle-import") (part "DIODE-STANDARD-SMA"))
    )
    (comp (ref "VD86")
      (value "400V")
      (footprint "eagle-import:SMA")
      (fields (field (name "PARTNO") "S1G-E3/61T"))
      (libsource (lib "eagle-import") (part "DIODE-STANDARD-SMA"))
    )
    (comp (ref "VD87")
      (value "400V")
      (footprint "eagle-import:SMA")
      (fields (field (name "PARTNO") "S1G-E3/61T"))
      (libsource (lib "eagle-import") (part "DIODE-STANDARD-SMA"))
    )
    (comp (ref "VD88")
      (value "400V")
      (footprint "eagle-import:SMA")
      (fields (field (name "PARTNO") "S1G-E3/61T"))
      (libsource (lib "eagle-import") (part "DIODE-STANDARD-SMA"))
    )
    (comp (ref "VD89")
      (value "400V")
      (footprint "eagle-import:SMA")
      (fields (field (name "PARTNO") "S1G-E3/61T"))
      (libsource (lib "eagle-import") (part "DIODE-STANDARD-SMA"))
    )
    (comp (ref "VD90")
      (value "400V")
      (footprint "eagle-import:SMA")
      (fields (field (name "PARTNO") "S1G-E3/61T"))
      (libsource (lib "eagle-import") (part "DIODE-STANDARD-SMA"))
    )
    (comp (ref "VD91")
      (value "400V")
      (footprint "eagle-import:SMA")
      (fields (field (name "PARTNO") "S1G-E3/61T"))
      (libsource (lib "eagle-import") (part "DIODE-STANDARD-SMA"))
    )
    (comp (ref "VD92")
      (value "400V")
      (footprint "eagle-import:SMA")
      (fields (field (name "PARTNO") "S1G-E3/61T"))
      (libsource (lib "eagle-import") (part "DIODE-STANDARD-SMA"))
    )
    (comp (ref "VD93")
      (value "400V")
      (footprint "eagle-import:SMA")
      (fields (field (name "PARTNO") "S1G-E3/61T"))
      (libsource (lib "eagle-import") (part "DIODE-STANDARD-SMA"))
    )
    (comp (ref "VD94")
      (value "400V")
      (footprint "eagle-import:SMA")
      (fields (field (name "PARTNO") "S1G-E3/61T"))
      (libsource (lib "eagle-import") (part "DIODE-STANDARD-SMA"))
    )
    (comp (ref "VD95")
      (value "400V")
      (footprint "eagle-import:SMA")
      (fields (field (name "PARTNO") "S1G-E3/61T"))
      (libsource (lib "eagle-import") (part "DIODE-STANDARD-SMA"))
    )
    (comp (ref "VD96")
      (value "400V")
      (footprint "eagle-import:SMA")
      (fields (field (name "PARTNO") "S1G-E3/61T"))
      (libsource (lib "eagle-import") (part "DIODE-STANDARD-SMA"))
    )
    (comp (ref "VD97")
      (value "400V")
      (footprint "eagle-import:SMA")
      (fields (field (name "PARTNO") "S1G-E3/61T"))
      (libsource (lib "eagle-import") (part "DIODE-STANDARD-SMA"))
    )
    (comp (ref "VD98")
      (value "100V")
      (footprint "eagle-import:SOD323")
      (fields (field (name "PARTNO") "1N4148WS-V-GS18"))
      (libsource (lib "eagle-import") (part "DIODE-STANDARD-SOD323"))
    )
    (comp (ref "VD99")
      (value "100V")
      (footprint "eagle-import:SOD323")
      (fields (field (name "PARTNO") "1N4148WS-V-GS18"))
      (libsource (lib "eagle-import") (part "DIODE-STANDARD-SOD323"))
    )
    (comp (ref "VT2")
      (value "BC817-16SMD")
      (footprint "eagle-import:SOT23-BEC")
      (fields (field (name "PARTNO") "BC817"))
      (libsource (lib "eagle-import") (part "BC817SMD-16"))
    )
    (comp (ref "XP7")
      (value "MOLEX-90130-16")
      (footprint "eagle-import:MOLEX-90130-16")
      (fields (field (name "LABEL") "DISCRETE(1..16)") (field (name "PARTNO") "90130-1216"))
      (libsource (lib "eagle-import") (part "MOLEX-90130-16"))
    )
  )
  (nets
    (net (code "1") (name "+3V3") (class "Default")
      (node (ref "C103") (pin "1") (pinfunction "1_1") (pintype "passive"))
      (node (ref "C104") (pin "1") (pinfunction "1_1") (pintype "passive"))
      (node (ref "C11") (pin "2") (pinfunction "2_2") (pintype "passive"))
      (node (ref "C121") (pin "1") (pinfunction "1_1") (pintype "passive"))
      (node (ref "C122") (pin "1") (pinfunction "1_1") (pintype "passive"))
      (node (ref "C139") (pin "1") (pinfunction "1_1") (pintype "passive"))
      (node (ref "C140") (pin "1") (pinfunction "1_1") (pintype "passive"))
      (node (ref "C141") (pin "1") (pinfunction "1_1") (pintype "passive"))
      (node (ref "C142") (pin "2") (pinfunction "2_2") (pintype "passive"))
      (node (ref "C68") (pin "+") (pinfunction "+_+") (pintype "passive"))
      (node (ref "C85") (pin "1") (pinfunction "1_1") (pintype "passive"))
      (node (ref "C86") (pin "1") (pinfunction "1_1") (pintype "passive"))
      (node (ref "DA14") (pin "2") (pinfunction "OUT_2") (pintype "power_in"))
      (node (ref "DA14") (pin "4") (pinfunction "OUT_4") (pintype "power_in"))
      (node (ref "DA16") (pin "3") (pinfunction "VCC_3") (pintype "power_in"))
      (node (ref "DD10") (pin "16") (pinfunction "VCC_16") (pintype "power_in"))
      (node (ref "DD11") (pin "16") (pinfunction "VCC_16") (pintype "power_in"))
      (node (ref "DD12") (pin "10") (pinfunction "~{MR}_10") (pintype "input"))
      (node (ref "DD12") (pin "16") (pinfunction "VCC_16") (pintype "power_in"))
      (node (ref "DD2") (pin "8") (pinfunction "VCC_8") (pintype "power_in"))
      (node (ref "DD4") (pin "16") (pinfunction "VCC_16") (pintype "power_in"))
      (node (ref "DD5") (pin "16") (pinfunction "VCC_16") (pintype "power_in"))
      (node (ref "DD6") (pin "16") (pinfunction "VCC_16") (pintype "power_in"))
      (node (ref "DD7") (pin "16") (pinfunction "VCC_16") (pintype "power_in"))
      (node (ref "DD8") (pin "16") (pinfunction "VCC_16") (pintype "power_in"))
      (node (ref "DD9") (pin "16") (pinfunction "VCC_16") (pintype "power_in"))
      (node (ref "R1") (pin "2") (pinfunction "2_2") (pintype "passive"))
      (node (ref "R15") (pin "1") (pinfunction "1_1") (pintype "passive"))
      (node (ref "R170") (pin "1") (pinfunction "1_1") (pintype "passive"))
      (node (ref "R171") (pin "1") (pinfunction "1_1") (pintype "passive"))
      (node (ref "R172") (pin "1") (pinfunction "1_1") (pintype "passive"))
      (node (ref "R173") (pin "1") (pinfunction "1_1") (pintype "passive"))
      (node (ref "R174") (pin "1") (pinfunction "1_1") (pintype "passive"))
      (node (ref "R175") (pin "1") (pinfunction "1_1") (pintype "passive"))
      (node (ref "R176") (pin "1") (pinfunction "1_1") (pintype "passive"))
      (node (ref "R177") (pin "1") (pinfunction "1_1") (pintype "passive"))
      (node (ref "R178") (pin "1") (pinfunction "1_1") (pintype "passive"))
      (node (ref "R179") (pin "1") (pinfunction "1_1") (pintype "passive"))
      (node (ref "R180") (pin "1") (pinfunction "1_1") (pintype "passive"))
      (node (ref "R181") (pin "1") (pinfunction "1_1") (pintype "passive"))
      (node (ref "R182") (pin "1") (pinfunction "1_1") (pintype "passive"))
      (node (ref "R183") (pin "1") (pinfunction "1_1") (pintype "passive"))
      (node (ref "R184") (pin "1") (pinfunction "1_1") (pintype "passive"))
      (node (ref "R185") (pin "1") (pinfunction "1_1") (pintype "passive"))
      (node (ref "R2") (pin "2") (pinfunction "2_2") (pintype "passive"))
      (node (ref "R221") (pin "1") (pinfunction "1_1") (pintype "passive"))
      (node (ref "R222") (pin "1") (pinfunction "1_1") (pintype "passive"))
      (node (ref "R223") (pin "1") (pinfunction "1_1") (pintype "passive"))
      (node (ref "R224") (pin "1") (pinfunction "1_1") (pintype "passive"))
      (node (ref "R225") (pin "1") (pinfunction "1_1") (pintype "passive"))
      (node (ref "R226") (pin "1") (pinfunction "1_1") (pintype "passive"))
      (node (ref "R227") (pin "1") (pinfunction "1_1") (pintype "passive"))
      (node (ref "R228") (pin "1") (pinfunction "1_1") (pintype "passive"))
      (node (ref "R229") (pin "1") (pinfunction "1_1") (pintype "passive"))
      (node (ref "R230") (pin "1") (pinfunction "1_1") (pintype "passive"))
      (node (ref "R231") (pin "1") (pinfunction "1_1") (pintype "passive"))
      (node (ref "R232") (pin "1") (pinfunction "1_1") (pintype "passive"))
      (node (ref "R233") (pin "1") (pinfunction "1_1") (pintype "passive"))
      (node (ref "R234") (pin "1") (pinfunction "1_1") (pintype "passive"))
      (node (ref "R235") (pin "1") (pinfunction "1_1") (pintype "passive"))
      (node (ref "R236") (pin "1") (pinfunction "1_1") (pintype "passive"))
      (node (ref "R25") (pin "1") (pinfunction "1_1") (pintype "passive"))
      (node (ref "R269") (pin "1") (pinfunction "1_1") (pintype "passive"))
      (node (ref "R270") (pin "1") (pinfunction "1_1") (pintype "passive"))
      (node (ref "R271") (pin "1") (pinfunction "1_1") (pintype "passive"))
      (node (ref "R272") (pin "1") (pinfunction "1_1") (pintype "passive"))
      (node (ref "R273") (pin "1") (pinfunction "1_1") (pintype "passive"))
      (node (ref "R274") (pin "1") (pinfunction "1_1") (pintype "passive"))
      (node (ref "R275") (pin "1") (pinfunction "1_1") (pintype "passive"))
      (node (ref "R276") (pin "1") (pinfunction "1_1") (pintype "passive"))
      (node (ref "R277") (pin "1") (pinfunction "1_1") (pintype "passive"))
      (node (ref "R278") (pin "1") (pinfunction "1_1") (pintype "passive"))
      (node (ref "R279") (pin "1") (pinfunction "1_1") (pintype "passive"))
      (node (ref "R280") (pin "1") (pinfunction "1_1") (pintype "passive"))
      (node (ref "R281") (pin "1") (pinfunction "1_1") (pintype "passive"))
      (node (ref "R282") (pin "1") (pinfunction "1_1") (pintype "passive"))
      (node (ref "R283") (pin "1") (pinfunction "1_1") (pintype "passive"))
      (node (ref "R284") (pin "1") (pinfunction "1_1") (pintype "passive"))
      (node (ref "R317") (pin "1") (pinfunction "1_1") (pintype "passive"))
      (node (ref "R318") (pin "1") (pinfunction "1_1") (pintype "passive"))
      (node (ref "R319") (pin "1") (pinfunction "1_1") (pintype "passive"))
      (node (ref "R320") (pin "1") (pinfunction "1_1") (pintype "passive"))
      (node (ref "R321") (pin "1") (pinfunction "1_1") (pintype "passive"))
      (node (ref "R322") (pin "1") (pinfunction "1_1") (pintype "passive"))
      (node (ref "R323") (pin "1") (pinfunction "1_1") (pintype "passive"))
      (node (ref "R324") (pin "1") (pinfunction "1_1") (pintype "passive"))
      (node (ref "R325") (pin "1") (pinfunction "1_1") (pintype "passive"))
      (node (ref "R326") (pin "1") (pinfunction "1_1") (pintype "passive"))
      (node (ref "R327") (pin "1") (pinfunction "1_1") (pintype "passive"))
      (node (ref "R328") (pin "1") (pinfunction "1_1") (pintype "passive"))
      (node (ref "R329") (pin "1") (pinfunction "1_1") (pintype "passive"))
      (node (ref "R330") (pin "1") (pinfunction "1_1") (pintype "passive"))
      (node (ref "R331") (pin "1") (pinfunction "1_1") (pintype "passive"))
      (node (ref "R332") (pin "1") (pinfunction "1_1") (pintype "passive"))
      (node (ref "R333") (pin "2") (pinfunction "2_2") (pintype "passive"))
      (node (ref "R362") (pin "2") (pinfunction "2_2") (pintype "passive"))
      (node (ref "R6") (pin "2") (pinfunction "2_2") (pintype "passive"))
      (node (ref "R7") (pin "2") (pinfunction "2_2") (pintype "passive"))
      (node (ref "R8") (pin "2") (pinfunction "2_2") (pintype "passive"))
      (node (ref "R9") (pin "2") (pinfunction "2_2") (pintype "passive"))
      (node (ref "VD3") (pin "A") (pinfunction "A_A") (pintype "passive"))
      (node (ref "VT3") (pin "C") (pinfunction "C_C") (pintype "passive"))
      (node (ref "XP1") (pin "1") (pinfunction "1_1") (pintype "passive"))
      (node (ref "XP1") (pin "2") (pinfunction "2_2") (pintype "passive"))
      (node (ref "XP2") (pin "1") (pinfunction "1_1") (pintype "passive"))
      (node (ref "XP3") (pin "1") (pinfunction "1_1") (pintype "passive"))
      (node (ref "Z1") (pin "3") (pinfunction "3_3") (pintype "passive"))
    )
    (net (code "2") (name "+3V3_DIRT") (class "Default")
      (node (ref "C1") (pin "1") (pinfunction "1_1") (pintype "passive"))
      (node (ref "C144") (pin "1") (pinfunction "1_1") (pintype "passive"))
      (node (ref "C2") (pin "1") (pinfunction "1_1") (pintype "passive"))
      (node (ref "C5") (pin "+") (pinfunction "+_+") (pintype "passive"))
      (node (ref "C6") (pin "1") (pinfunction "1_1") (pintype "passive"))
      (node (ref "C8") (pin "1") (pinfunction "1_1") (pintype "passive"))
      (node (ref "C9") (pin "1") (pinfunction "1_1") (pintype "passive"))
      (node (ref "DA17") (pin "16") (pinfunction "VCC_16") (pintype "power_in"))
      (node (ref "DD1") (pin "100") (pinfunction "VDD_3_100") (pintype "power_in"))
      (node (ref "DD1") (pin "11") (pinfunction "VDD_5_11") (pintype "power_in"))
      (node (ref "DD1") (pin "28") (pinfunction "VDD_4_28") (pintype "power_in"))
      (node (ref "DD1") (pin "50") (pinfunction "VDD_1_50") (pintype "power_in"))
      (node (ref "DD1") (pin "6") (pinfunction "V_BAT_6") (pintype "power_in"))
      (node (ref "DD1") (pin "75") (pinfunction "VDD_2_75") (pintype "power_in"))
      (node (ref "L1") (pin "1") (pinfunction "1_1") (pintype "passive"))
      (node (ref "Z1") (pin "1") (pinfunction "1_1") (pintype "passive"))
    )
    (net (code "3") (name "+5V") (class "Default")
      (node (ref "C28") (pin "1") (pinfunction "1_1") (pintype "passive"))
      (node (ref "C29") (pin "1") (pinfunction "1_1") (pintype "passive"))
      (node (ref "C30") (pin "1") (pinfunction "1_1") (pintype "passive"))
      (node (ref "C37") (pin "1") (pinfunction "1_1") (pintype "passive"))
      (node (ref "C38") (pin "1") (pinfunction "1_1") (pintype "passive"))
      (node (ref "C39") (pin "1") (pinfunction "1_1") (pintype "passive"))
      (node (ref "C40") (pin "1") (pinfunction "1_1") (pintype "passive"))
      (node (ref "C41") (pin "1") (pinfunction "1_1") (pintype "passive"))
      (node (ref "C42") (pin "1") (pinfunction "1_1") (pintype "passive"))
      (node (ref "C50") (pin "1") (pinfunction "1_1") (pintype "passive"))
      (node (ref "C52") (pin "1") (pinfunction "1_1") (pintype "passive"))
      (node (ref "DA1") (pin "8") (pinfunction "VCC_8") (pintype "power_in"))
      (node (ref "DA10") (pin "4") (pinfunction "RESET_4") (pintype "input"))
      (node (ref "DA10") (pin "8") (pinfunction "VCC_8") (pintype "power_in"))
      (node (ref "DA2") (pin "8") (pinfunction "VCC_8") (pintype "power_in"))
      (node (ref "DA3") (pin "8") (pinfunction "VCC_8") (pintype "power_in"))
      (node (ref "DA4") (pin "8") (pinfunction "VCC_8") (pintype "power_in"))
      (node (ref "DA5") (pin "8") (pinfunction "VCC_8") (pintype "power_in"))
      (node (ref "DA6") (pin "8") (pinfunction "VCC_8") (pintype "power_in"))
      (node (ref "DA7") (pin "10") (pinfunction "D_10") (pintype "input"))
      (node (ref "DA7") (pin "11") (pinfunction "CLR_11") (pintype "input"))
      (node (ref "DA7") (pin "16") (pinfunction "VCC_16") (pintype "power_in"))
      (node (ref "DA7") (pin "3") (pinfunction "CLR_3") (pintype "input"))
      (node (ref "DA8") (pin "10") (pinfunction "D_10") (pintype "input"))
      (node (ref "DA8") (pin "11") (pinfunction "CLR_11") (pintype "input"))
      (node (ref "DA8") (pin "16") (pinfunction "VCC_16") (pintype "power_in"))
      (node (ref "DA8") (pin "3") (pinfunction "CLR_3") (pintype "input"))
      (node (ref "DA9") (pin "10") (pinfunction "D_10") (pintype "input"))
      (node (ref "DA9") (pin "11") (pinfunction "CLR_11") (pintype "input"))
      (node (ref "DA9") (pin "16") (pinfunction "VCC_16") (pintype "power_in"))
      (node (ref "DA9") (pin "3") (pinfunction "CLR_3") (pintype "input"))
      (node (ref "DD3") (pin "14") (pinfunction "VCC_14") (pintype "power_in"))
      (node (ref "R113") (pin "1") (pinfunction "1_1") (pintype "passive"))
      (node (ref "R114") (pin "1") (pinfunction "1_1") (pintype "passive"))
      (node (ref "R115") (pin "1") (pinfunction "1_1") (pintype "passive"))
      (node (ref "R116") (pin "1") (pinfunction "A_1") (pintype "passive"))
      (node (ref "R117") (pin "2") (pinfunction "2_2") (pintype "passive"))
      (node (ref "R118") (pin "2") (pinfunction "2_2") (pintype "passive"))
      (node (ref "R119") (pin "2") (pinfunction "2_2") (pintype "passive"))
      (node (ref "R120") (pin "2") (pinfunction "2_2") (pintype "passive"))
      (node (ref "R121") (pin "2") (pinfunction "2_2") (pintype "passive"))
      (node (ref "R122") (pin "2") (pinfunction "2_2") (pintype "passive"))
      (node (ref "R123") (pin "2") (pinfunction "2_2") (pintype "passive"))
      (node (ref "R136") (pin "1") (pinfunction "1_1") (pintype "passive"))
      (node (ref "RK2") (pin "2") (pinfunction "P$2_2") (pintype "passive"))
      (node (ref "VD60") (pin "A") (pinfunction "A_A") (pintype "passive"))
    )
    (net (code "4") (name "+5V_USB") (class "Default")
      (node (ref "L4") (pin "2") (pinfunction "2_2") (pintype "passive"))
      (node (ref "R359") (pin "2") (pinfunction "2_2") (pintype "passive"))
      (node (ref "R361") (pin "2") (pinfunction "2_2") (pintype "passive"))
      (node (ref "VD56") (pin "A") (pinfunction "A_A") (pintype "passive"))
      (node (ref "VT3") (pin "B") (pinfunction "B_B") (pintype "passive"))
    )
    (net (code "5") (name "+24V") (class "Default")
      (node (ref "VD61") (pin "3") (pinfunction "A_3") (pintype "passive"))
      (node (ref "VD62") (pin "A1") (pinfunction "A1_A1") (pintype "passive"))
      (node (ref "XP6") (pin "2") (pinfunction "2_2") (pintype "passive"))
      (node (ref "XP6") (pin "4") (pinfunction "4_4") (pintype "passive"))
      (node (ref "XP6") (pin "6") (pinfunction "6_6") (pintype "passive"))
      (node (ref "XP6") (pin "8") (pinfunction "8_8") (pintype "passive"))
    )
    (net (code "6") (name "+24V_CLEAR") (class "Default")
      (node (ref "C56") (pin "2") (pinfunction "2_2") (pintype "passive"))
      (node (ref "C57") (pin "+") (pinfunction "+_+") (pintype "passive"))
      (node (ref "C58") (pin "2") (pinfunction "2_2") (pintype "passive"))
      (node (ref "C59") (pin "1") (pinfunction "1_1") (pintype "passive"))
      (node (ref "C60") (pin "2") (pinfunction "2_2") (pintype "passive"))
      (node (ref "C61") (pin "1") (pinfunction "1_1") (pintype "passive"))
      (node (ref "D5") (pin "TAB") (pinfunction "VCC_TAB") (pintype "power_in"))
      (node (ref "DA12") (pin "1") (pinfunction "VIN_1") (pintype "input"))
      (node (ref "DA13") (pin "1") (pinfunction "VIN_1") (pintype "input"))
      (node (ref "R26") (pin "1") (pinfunction "1_1") (pintype "passive"))
      (node (ref "R27") (pin "1") (pinfunction "1_1") (pintype "passive"))
      (node (ref "R28") (pin "1") (pinfunction "1_1") (pintype "passive"))
      (node (ref "R29") (pin "1") (pinfunction "1_1") (pintype "passive"))
      (node (ref "R30") (pin "1") (pinfunction "1_1") (pintype "passive"))
      (node (ref "R31") (pin "1") (pinfunction "1_1") (pintype "passive"))
      (node (ref "R32") (pin "1") (pinfunction "1_1") (pintype "passive"))
      (node (ref "R33") (pin "1") (pinfunction "1_1") (pintype "passive"))
      (node (ref "R50") (pin "1") (pinfunction "1_1") (pintype "passive"))
      (node (ref "R51") (pin "1") (pinfunction "1_1") (pintype "passive"))
      (node (ref "R52") (pin "1") (pinfunction "1_1") (pintype "passive"))
      (node (ref "R53") (pin "1") (pinfunction "1_1") (pintype "passive"))
      (node (ref "R54") (pin "1") (pinfunction "1_1") (pintype "passive"))
      (node (ref "R55") (pin "1") (pinfunction "1_1") (pintype "passive"))
      (node (ref "R56") (pin "1") (pinfunction "1_1") (pintype "passive"))
      (node (ref "R57") (pin "1") (pinfunction "1_1") (pintype "passive"))
      (node (ref "Z41") (pin "3") (pinfunction "3_3") (pintype "passive"))
    )
    (net (code "7") (name "-5V") (class "Default")
      (node (ref "C28") (pin "2") (pinfunction "2_2") (pintype "passive"))
      (node (ref "C29") (pin "2") (pinfunction "2_2") (pintype "passive"))
      (node (ref "C30") (pin "2") (pinfunction "2_2") (pintype "passive"))
      (node (ref "C37") (pin "2") (pinfunction "2_2") (pintype "passive"))
      (node (ref "C38") (pin "2") (pinfunction "2_2") (pintype "passive"))
      (node (ref "C39") (pin "2") (pinfunction "2_2") (pintype "passive"))
      (node (ref "DA1") (pin "4") (pinfunction "GND_4") (pintype "power_in"))
      (node (ref "DA2") (pin "4") (pinfunction "GND_4") (pintype "power_in"))
      (node (ref "DA3") (pin "4") (pinfunction "GND_4") (pintype "power_in"))
      (node (ref "DA4") (pin "4") (pinfunction "GND_4") (pintype "power_in"))
      (node (ref "DA5") (pin "4") (pinfunction "GND_4") (pintype "power_in"))
      (node (ref "DA6") (pin "4") (pinfunction "GND_4") (pintype "power_in"))
      (node (ref "R116") (pin "3") (pinfunction "E_3") (pintype "passive"))
      (node (ref "R137") (pin "2") (pinfunction "2_2") (pintype "passive"))
      (node (ref "RK3") (pin "2") (pinfunction "P$2_2") (pintype "passive"))
    )
    (net (code "8") (name "AGND") (class "Default")
      (node (ref "C12") (pin "2") (pinfunction "2_2") (pintype "passive"))
      (node (ref "C13") (pin "2") (pinfunction "2_2") (pintype "passive"))
      (node (ref "C14") (pin "2") (pinfunction "2_2") (pintype "passive"))
      (node (ref "C15") (pin "2") (pinfunction "2_2") (pintype "passive"))
      (node (ref "C16") (pin "2") (pinfunction "2_2") (pintype "passive"))
      (node (ref "C17") (pin "2") (pinfunction "2_2") (pintype "passive"))
      (node (ref "C18") (pin "2") (pinfunction "2_2") (pintype "passive"))
      (node (ref "C19") (pin "2") (pinfunction "2_2") (pintype "passive"))
      (node (ref "C20") (pin "2") (pinfunction "2_2") (pintype "passive"))
      (node (ref "C21") (pin "2") (pinfunction "2_2") (pintype "passive"))
      (node (ref "C22") (pin "2") (pinfunction "2_2") (pintype "passive"))
      (node (ref "C23") (pin "2") (pinfunction "2_2") (pintype "passive"))
      (node (ref "C24") (pin "2") (pinfunction "2_2") (pintype "passive"))
      (node (ref "C25") (pin "2") (pinfunction "2_2") (pintype "passive"))
      (node (ref "C26") (pin "2") (pinfunction "2_2") (pintype "passive"))
      (node (ref "C27") (pin "2") (pinfunction "2_2") (pintype "passive"))
      (node (ref "R42") (pin "1") (pinfunction "1_1") (pintype "passive"))
      (node (ref "R43") (pin "1") (pinfunction "1_1") (pintype "passive"))
      (node (ref "R44") (pin "1") (pinfunction "1_1") (pintype "passive"))
      (node (ref "R45") (pin "1") (pinfunction "1_1") (pintype "passive"))
      (node (ref "R46") (pin "1") (pinfunction "1_1") (pintype "passive"))
      (node (ref "R47") (pin "1") (pinfunction "1_1") (pintype "passive"))
      (node (ref "R48") (pin "1") (pinfunction "1_1") (pintype "passive"))
      (node (ref "R49") (pin "1") (pinfunction "1_1") (pintype "passive"))
      (node (ref "R66") (pin "1") (pinfunction "1_1") (pintype "passive"))
      (node (ref "R67") (pin "1") (pinfunction "1_1") (pintype "passive"))
      (node (ref "R68") (pin "1") (pinfunction "1_1") (pintype "passive"))
      (node (ref "R69") (pin "1") (pinfunction "1_1") (pintype "passive"))
      (node (ref "R70") (pin "1") (pinfunction "1_1") (pintype "passive"))
      (node (ref "R71") (pin "1") (pinfunction "1_1") (pintype "passive"))
      (node (ref "R72") (pin "1") (pinfunction "1_1") (pintype "passive"))
      (node (ref "R73") (pin "1") (pinfunction "1_1") (pintype "passive"))
      (node (ref "Z5") (pin "1") (pinfunction "1_1") (pintype "passive"))
    )
    (net (code "9") (name "AN_FILTERED_0") (class "Default")
      (node (ref "DD1") (pin "23") (pinfunction "PA0(WKUP/USART2_CTS/ADC123_IN0/TIM2_CH1_ETR/TIM5_CH1/TIM8_ETR)_23") (pintype "bidirectional"))
      (node (ref "Z24") (pin "3") (pinfunction "3_3") (pintype "passive"))
    )
    (net (code "10") (name "AN_FILTERED_1") (class "Default")
      (node (ref "DD1") (pin "24") (pinfunction "PA1(USART2_RTS/ADC123_IN1/TIM5_CH2/TIM2_CH2)_24") (pintype "bidirectional"))
      (node (ref "Z27") (pin "3") (pinfunction "3_3") (pintype "passive"))
    )
    (net (code "11") (name "AN_FILTERED_2") (class "Default")
      (node (ref "DD1") (pin "25") (pinfunction "PA2(USART2_TX/ADC123_IN2/TIM5_CH3/TIM2_CH3)_25") (pintype "bidirectional"))
      (node (ref "Z29") (pin "3") (pinfunction "3_3") (pintype "passive"))
    )
    (net (code "12") (name "AN_FILTERED_3") (class "Default")
      (node (ref "DD1") (pin "26") (pinfunction "PA3(USART2_RX/ADC123_IN3/TIM5_CH4/TIM2_CH4)_26") (pintype "bidirectional"))
      (node (ref "Z28") (pin "3") (pinfunction "3_3") (pintype "passive"))
    )
    (net (code "13") (name "AN_FILTERED_4") (class "Default")
      (node (ref "DD1") (pin "29") (pinfunction "PA4(SPI1_NSS/USART2_CK/DAC1/ADC12_IN4)_29") (pintype "bidirectional"))
      (node (ref "Z30") (pin "3") (pinfunction "3_3") (pintype "passive"))
    )
    (net (code "14") (name "AN_FILTERED_5") (class "Default")
      (node (ref "DD1") (pin "30") (pinfunction "PA5(SPI1_SCK/DAC2/ADC12_IN5)_30") (pintype "bidirectional"))
      (node (ref "Z31") (pin "3") (pinfunction "3_3") (pintype "passive"))
    )
    (net (code "15") (name "AN_FILTERED_6") (class "Default")
      (node (ref "DD1") (pin "31") (pinfunction "PA6(SPI1_MISO/TIM8_BKIN/ADC12_IN6/TIM3_CH1/TIM1_BKIN)_31") (pintype "bidirectional"))
      (node (ref "Z33") (pin "3") (pinfunction "3_3") (pintype "passive"))
    )
    (net (code "16") (name "AN_FILTERED_7") (class "Default")
      (node (ref "DD1") (pin "32") (pinfunction "PA7(SPI1_MOSI/TIM8_CH1N/ADC12_IN7/TIM3_CH2/TIM1_CH1N)_32") (pintype "bidirectional"))
      (node (ref "Z34") (pin "3") (pinfunction "3_3") (pintype "passive"))
    )
    (net (code "17") (name "AN_FILTERED_8") (class "Default")
      (node (ref "DD1") (pin "35") (pinfunction "PB0(ADC12_IN8/TIM3_CH3/TIM8_CH2N/TIM1_CH2N)_35") (pintype "bidirectional"))
      (node (ref "Z37") (pin "3") (pinfunction "3_3") (pintype "passive"))
    )
    (net (code "18") (name "AN_FILTERED_9") (class "Default")
      (node (ref "DD1") (pin "36") (pinfunction "PB1(ADC12_IN9/TIM3_CH4/TIM8_CH3N/TIM1_CH3N)_36") (pintype "bidirectional"))
      (node (ref "Z36") (pin "3") (pinfunction "3_3") (pintype "passive"))
    )
    (net (code "19") (name "AN_FILTERED_10") (class "Default")
      (node (ref "DD1") (pin "15") (pinfunction "PC0(ADC123_IN10)_15") (pintype "bidirectional"))
      (node (ref "Z22") (pin "3") (pinfunction "3_3") (pintype "passive"))
    )
    (net (code "20") (name "AN_FILTERED_11") (class "Default")
      (node (ref "DD1") (pin "16") (pinfunction "PC1(ADC123_IN11)_16") (pintype "bidirectional"))
      (node (ref "Z23") (pin "3") (pinfunction "3_3") (pintype "passive"))
    )
    (net (code "21") (name "AN_FILTERED_12") (class "Default")
      (node (ref "DD1") (pin "17") (pinfunction "PC2(ADC123_IN12)_17") (pintype "bidirectional"))
      (node (ref "Z25") (pin "3") (pinfunction "3_3") (pintype "passive"))
    )
    (net (code "22") (name "AN_FILTERED_13") (class "Default")
      (node (ref "DD1") (pin "18") (pinfunction "PC3(ADC123_IN13)_18") (pintype "bidirectional"))
      (node (ref "Z26") (pin "3") (pinfunction "3_3") (pintype "passive"))
    )
    (net (code "23") (name "AN_FILTERED_14") (class "Default")
      (node (ref "DD1") (pin "33") (pinfunction "PC4(ADC12_IN14)_33") (pintype "bidirectional"))
      (node (ref "Z32") (pin "3") (pinfunction "3_3") (pintype "passive"))
    )
    (net (code "24") (name "AN_FILTERED_15") (class "Default")
      (node (ref "DD1") (pin "34") (pinfunction "PC5(ADC12_IN15)_34") (pintype "bidirectional"))
      (node (ref "Z35") (pin "3") (pinfunction "3_3") (pintype "passive"))
    )
    (net (code "25") (name "AN_RAW_1") (class "Default")
      (node (ref "R31") (pin "2") (pinfunction "2_2") (pintype "passive"))
      (node (ref "VD17") (pin "A") (pinfunction "A_A") (pintype "passive"))
      (node (ref "VD9") (pin "A1") (pinfunction "A1_A1") (pintype "passive"))
      (node (ref "XP4") (pin "1") (pinfunction "1_1") (pintype "passive"))
    )
    (net (code "26") (name "AN_RAW_2") (class "Default")
      (node (ref "R33") (pin "2") (pinfunction "2_2") (pintype "passive"))
      (node (ref "VD11") (pin "A1") (pinfunction "A1_A1") (pintype "passive"))
      (node (ref "VD19") (pin "A") (pinfunction "A_A") (pintype "passive"))
      (node (ref "XP4") (pin "2") (pinfunction "2_2") (pintype "passive"))
    )
    (net (code "27") (name "AN_RAW_3") (class "Default")
      (node (ref "R32") (pin "2") (pinfunction "2_2") (pintype "passive"))
      (node (ref "VD10") (pin "A1") (pinfunction "A1_A1") (pintype "passive"))
      (node (ref "VD18") (pin "A") (pinfunction "A_A") (pintype "passive"))
      (node (ref "XP4") (pin "3") (pinfunction "3_3") (pintype "passive"))
    )
    (net (code "28") (name "AN_RAW_4") (class "Default")
      (node (ref "R50") (pin "2") (pinfunction "2_2") (pintype "passive"))
      (node (ref "VD20") (pin "A1") (pinfunction "A1_A1") (pintype "passive"))
      (node (ref "VD28") (pin "A") (pinfunction "A_A") (pintype "passive"))
      (node (ref "XP4") (pin "4") (pinfunction "4_4") (pintype "passive"))
    )
    (net (code "29") (name "AN_RAW_5") (class "Default")
      (node (ref "R51") (pin "2") (pinfunction "2_2") (pintype "passive"))
      (node (ref "VD21") (pin "A1") (pinfunction "A1_A1") (pintype "passive"))
      (node (ref "VD29") (pin "A") (pinfunction "A_A") (pintype "passive"))
      (node (ref "XP4") (pin "5") (pinfunction "5_5") (pintype "passive"))
    )
    (net (code "30") (name "AN_RAW_6") (class "Default")
      (node (ref "R53") (pin "2") (pinfunction "2_2") (pintype "passive"))
      (node (ref "VD23") (pin "A1") (pinfunction "A1_A1") (pintype "passive"))
      (node (ref "VD31") (pin "A") (pinfunction "A_A") (pintype "passive"))
      (node (ref "XP4") (pin "6") (pinfunction "6_6") (pintype "passive"))
    )
    (net (code "31") (name "AN_RAW_7") (class "Default")
      (node (ref "R54") (pin "2") (pinfunction "2_2") (pintype "passive"))
      (node (ref "VD24") (pin "A1") (pinfunction "A1_A1") (pintype "passive"))
      (node (ref "VD32") (pin "A") (pinfunction "A_A") (pintype "passive"))
      (node (ref "XP4") (pin "7") (pinfunction "7_7") (pintype "passive"))
    )
    (net (code "32") (name "AN_RAW_8") (class "Default")
      (node (ref "R57") (pin "2") (pinfunction "2_2") (pintype "passive"))
      (node (ref "VD27") (pin "A1") (pinfunction "A1_A1") (pintype "passive"))
      (node (ref "VD35") (pin "A") (pinfunction "A_A") (pintype "passive"))
      (node (ref "XP4") (pin "8") (pinfunction "8_8") (pintype "passive"))
    )
    (net (code "33") (name "AN_RAW_9") (class "Default")
      (node (ref "R56") (pin "2") (pinfunction "2_2") (pintype "passive"))
      (node (ref "VD26") (pin "A1") (pinfunction "A1_A1") (pintype "passive"))
      (node (ref "VD34") (pin "A") (pinfunction "A_A") (pintype "passive"))
      (node (ref "XP4") (pin "9") (pinfunction "9_9") (pintype "passive"))
    )
    (net (code "34") (name "AN_RAW_10") (class "Default")
      (node (ref "R26") (pin "2") (pinfunction "2_2") (pintype "passive"))
      (node (ref "VD12") (pin "A") (pinfunction "A_A") (pintype "passive"))
      (node (ref "VD4") (pin "A1") (pinfunction "A1_A1") (pintype "passive"))
      (node (ref "XP4") (pin "10") (pinfunction "10_10") (pintype "passive"))
    )
    (net (code "35") (name "AN_RAW_11") (class "Default")
      (node (ref "R27") (pin "2") (pinfunction "2_2") (pintype "passive"))
      (node (ref "VD13") (pin "A") (pinfunction "A_A") (pintype "passive"))
      (node (ref "VD5") (pin "A1") (pinfunction "A1_A1") (pintype "passive"))
      (node (ref "XP4") (pin "11") (pinfunction "11_11") (pintype "passive"))
    )
    (net (code "36") (name "AN_RAW_12") (class "Default")
      (node (ref "R29") (pin "2") (pinfunction "2_2") (pintype "passive"))
      (node (ref "VD15") (pin "A") (pinfunction "A_A") (pintype "passive"))
      (node (ref "VD7") (pin "A1") (pinfunction "A1_A1") (pintype "passive"))
      (node (ref "XP4") (pin "12") (pinfunction "12_12") (pintype "passive"))
    )
    (net (code "37") (name "AN_RAW_13") (class "Default")
      (node (ref "R30") (pin "2") (pinfunction "2_2") (pintype "passive"))
      (node (ref "VD16") (pin "A") (pinfunction "A_A") (pintype "passive"))
      (node (ref "VD8") (pin "A1") (pinfunction "A1_A1") (pintype "passive"))
      (node (ref "XP4") (pin "13") (pinfunction "13_13") (pintype "passive"))
    )
    (net (code "38") (name "AN_RAW_14") (class "Default")
      (node (ref "R52") (pin "2") (pinfunction "2_2") (pintype "passive"))
      (node (ref "VD22") (pin "A1") (pinfunction "A1_A1") (pintype "passive"))
      (node (ref "VD30") (pin "A") (pinfunction "A_A") (pintype "passive"))
      (node (ref "XP4") (pin "14") (pinfunction "14_14") (pintype "passive"))
    )
    (net (code "39") (name "AN_RAW_15") (class "Default")
      (node (ref "R55") (pin "2") (pinfunction "2_2") (pintype "passive"))
      (node (ref "VD25") (pin "A1") (pinfunction "A1_A1") (pintype "passive"))
      (node (ref "VD33") (pin "A") (pinfunction "A_A") (pintype "passive"))
      (node (ref "XP4") (pin "15") (pinfunction "15_15") (pintype "passive"))
    )
    (net (code "40") (name "BOOT_0") (class "Default")
      (node (ref "DD1") (pin "94") (pinfunction "BOOT_0_94") (pintype "input"))
      (node (ref "Z10") (pin "3") (pinfunction "3_3") (pintype "passive"))
    )
    (net (code "41") (name "BOOT_1") (class "Default")
      (node (ref "DD1") (pin "37") (pinfunction "PB2(BOOT_1)*_37") (pintype "bidirectional"))
      (node (ref "Z9") (pin "3") (pinfunction "3_3") (pintype "passive"))
    )
    (net (code "42") (name "CAN_RX") (class "Default")
      (node (ref "DD1") (pin "81") (pinfunction "PD0(OSC_IN/FSMC_D2/CAN_RX)*_81") (pintype "bidirectional"))
      (node (ref "Z47") (pin "3") (pinfunction "3_3") (pintype "passive"))
    )
    (net (code "43") (name "CAN_TX") (class "Default")
      (node (ref "DD1") (pin "82") (pinfunction "PD1(OSC_OUT/FSMC_D3/CAN_TX)*_82") (pintype "bidirectional"))
      (node (ref "Z50") (pin "3") (pinfunction "3_3") (pintype "passive"))
    )
    (net (code "44") (name "FREQMETER") (class "Default")
      (node (ref "DD1") (pin "63") (pinfunction "PC6(I2S2_MCK/TIM8_CH1/SDIO_D6/TIM3_CH1)*_63") (pintype "bidirectional"))
      (node (ref "Z39") (pin "3") (pinfunction "3_3") (pintype "passive"))
    )
    (net (code "45") (name "FREQ_RAW") (class "Default")
      (node (ref "R125") (pin "2") (pinfunction "2_2") (pintype "passive"))
      (node (ref "XP5") (pin "3") (pinfunction "3_3") (pintype "passive"))
    )
    (net (code "46") (name "GND") (class "Default")
      (node (ref "C1") (pin "2") (pinfunction "2_2") (pintype "passive"))
      (node (ref "C10") (pin "2") (pinfunction "2_2") (pintype "passive"))
      (node (ref "C100") (pin "2") (pinfunction "2_2") (pintype "passive"))
      (node (ref "C101") (pin "2") (pinfunction "2_2") (pintype "passive"))
      (node (ref "C102") (pin "2") (pinfunction "2_2") (pintype "passive"))
      (node (ref "C103") (pin "2") (pinfunction "2_2") (pintype "passive"))
      (node (ref "C104") (pin "2") (pinfunction "2_2") (pintype "passive"))
      (node (ref "C105") (pin "2") (pinfunction "2_2") (pintype "passive"))
      (node (ref "C106") (pin "2") (pinfunction "2_2") (pintype "passive"))
      (node (ref "C107") (pin "2") (pinfunction "2_2") (pintype "passive"))
      (node (ref "C108") (pin "2") (pinfunction "2_2") (pintype "passive"))
      (node (ref "C109") (pin "2") (pinfunction "2_2") (pintype "passive"))
      (node (ref "C11") (pin "1") (pinfunction "1_1") (pintype "passive"))
      (node (ref "C110") (pin "2") (pinfunction "2_2") (pintype "passive"))
      (node (ref "C111") (pin "2") (pinfunction "2_2") (pintype "passive"))
      (node (ref "C112") (pin "2") (pinfunction "2_2") (pintype "passive"))
      (node (ref "C113") (pin "2") (pinfunction "2_2") (pintype "passive"))
      (node (ref "C114") (pin "2") (pinfunction "2_2") (pintype "passive"))
      (node (ref "C115") (pin "2") (pinfunction "2_2") (pintype "passive"))
      (node (ref "C116") (pin "2") (pinfunction "2_2") (pintype "passive"))
      (node (ref "C117") (pin "2") (pinfunction "2_2") (pintype "passive"))
      (node (ref "C118") (pin "2") (pinfunction "2_2") (pintype "passive"))
      (node (ref "C119") (pin "2") (pinfunction "2_2") (pintype "passive"))
      (node (ref "C120") (pin "2") (pinfunction "2_2") (pintype "passive"))
      (node (ref "C121") (pin "2") (pinfunction "2_2") (pintype "passive"))
      (node (ref "C122") (pin "2") (pinfunction "2_2") (pintype "passive"))
      (node (ref "C123") (pin "2") (pinfunction "2_2") (pintype "passive"))
      (node (ref "C124") (pin "2") (pinfunction "2_2") (pintype "passive"))
      (node (ref "C125") (pin "2") (pinfunction "2_2") (pintype "passive"))
      (node (ref "C126") (pin "2") (pinfunction "2_2") (pintype "passive"))
      (node (ref "C127") (pin "2") (pinfunction "2_2") (pintype "passive"))
      (node (ref "C128") (pin "2") (pinfunction "2_2") (pintype "passive"))
      (node (ref "C129") (pin "2") (pinfunction "2_2") (pintype "passive"))
      (node (ref "C130") (pin "2") (pinfunction "2_2") (pintype "passive"))
      (node (ref "C131") (pin "2") (pinfunction "2_2") (pintype "passive"))
      (node (ref "C132") (pin "2") (pinfunction "2_2") (pintype "passive"))
      (node (ref "C133") (pin "2") (pinfunction "2_2") (pintype "passive"))
      (node (ref "C134") (pin "2") (pinfunction "2_2") (pintype "passive"))
      (node (ref "C135") (pin "2") (pinfunction "2_2") (pintype "passive"))
      (node (ref "C136") (pin "2") (pinfunction "2_2") (pintype "passive"))
      (node (ref "C137") (pin "2") (pinfunction "2_2") (pintype "passive"))
      (node (ref "C138") (pin "2") (pinfunction "2_2") (pintype "passive"))
      (node (ref "C139") (pin "2") (pinfunction "2_2") (pintype "passive"))
      (node (ref "C140") (pin "2") (pinfunction "2_2") (pintype "passive"))
      (node (ref "C141") (pin "2") (pinfunction "2_2") (pintype "passive"))
      (node (ref "C142") (pin "1") (pinfunction "1_1") (pintype "passive"))
      (node (ref "C143") (pin "2") (pinfunction "2_2") (pintype "passive"))
      (node (ref "C144") (pin "2") (pinfunction "2_2") (pintype "passive"))
      (node (ref "C145") (pin "2") (pinfunction "2_2") (pintype "passive"))
      (node (ref "C2") (pin "2") (pinfunction "2_2") (pintype "passive"))
      (node (ref "C3") (pin "2") (pinfunction "2_2") (pintype "passive"))
      (node (ref "C31") (pin "1") (pinfunction "1_1") (pintype "passive"))
      (node (ref "C32") (pin "1") (pinfunction "1_1") (pintype "passive"))
      (node (ref "C33") (pin "1") (pinfunction "1_1") (pintype "passive"))
      (node (ref "C34") (pin "2") (pinfunction "2_2") (pintype "passive"))
      (node (ref "C35") (pin "2") (pinfunction "2_2") (pintype "passive"))
      (node (ref "C36") (pin "2") (pinfunction "2_2") (pintype "passive"))
      (node (ref "C4") (pin "2") (pinfunction "2_2") (pintype "passive"))
      (node (ref "C40") (pin "2") (pinfunction "2_2") (pintype "passive"))
      (node (ref "C41") (pin "2") (pinfunction "2_2") (pintype "passive"))
      (node (ref "C42") (pin "2") (pinfunction "2_2") (pintype "passive"))
      (node (ref "C49") (pin "2") (pinfunction "2_2") (pintype "passive"))
      (node (ref "C5") (pin "-") (pinfunction "-_-") (pintype "passive"))
      (node (ref "C50") (pin "2") (pinfunction "2_2") (pintype "passive"))
      (node (ref "C51") (pin "2") (pinfunction "2_2") (pintype "passive"))
      (node (ref "C52") (pin "2") (pinfunction "2_2") (pintype "passive"))
      (node (ref "C53") (pin "1") (pinfunction "1_1") (pintype "passive"))
      (node (ref "C54") (pin "1") (pinfunction "1_1") (pintype "passive"))
      (node (ref "C55") (pin "2") (pinfunction "2_2") (pintype "passive"))
      (node (ref "C56") (pin "1") (pinfunction "1_1") (pintype "passive"))
      (node (ref "C57") (pin "-") (pinfunction "-_-") (pintype "passive"))
      (node (ref "C59") (pin "2") (pinfunction "2_2") (pintype "passive"))
      (node (ref "C6") (pin "2") (pinfunction "2_2") (pintype "passive"))
      (node (ref "C60") (pin "1") (pinfunction "1_1") (pintype "passive"))
      (node (ref "C62") (pin "2") (pinfunction "2_2") (pintype "passive"))
      (node (ref "C63") (pin "2") (pinfunction "2_2") (pintype "passive"))
      (node (ref "C64") (pin "-") (pinfunction "-_-") (pintype "passive"))
      (node (ref "C65") (pin "2") (pinfunction "2_2") (pintype "passive"))
      (node (ref "C66") (pin "-") (pinfunction "-_-") (pintype "passive"))
      (node (ref "C67") (pin "+") (pinfunction "+_+") (pintype "passive"))
      (node (ref "C68") (pin "-") (pinfunction "-_-") (pintype "passive"))
      (node (ref "C69") (pin "2") (pinfunction "2_2") (pintype "passive"))
      (node (ref "C70") (pin "2") (pinfunction "2_2") (pintype "passive"))
      (node (ref "C71") (pin "2") (pinfunction "2_2") (pintype "passive"))
      (node (ref "C72") (pin "2") (pinfunction "2_2") (pintype "passive"))
      (node (ref "C73") (pin "2") (pinfunction "2_2") (pintype "passive"))
      (node (ref "C74") (pin "2") (pinfunction "2_2") (pintype "passive"))
      (node (ref "C75") (pin "2") (pinfunction "2_2") (pintype "passive"))
      (node (ref "C76") (pin "2") (pinfunction "2_2") (pintype "passive"))
      (node (ref "C77") (pin "2") (pinfunction "2_2") (pintype "passive"))
      (node (ref "C78") (pin "2") (pinfunction "2_2") (pintype "passive"))
      (node (ref "C79") (pin "2") (pinfunction "2_2") (pintype "passive"))
      (node (ref "C8") (pin "2") (pinfunction "2_2") (pintype "passive"))
      (node (ref "C80") (pin "2") (pinfunction "2_2") (pintype "passive"))
      (node (ref "C81") (pin "2") (pinfunction "2_2") (pintype "passive"))
      (node (ref "C82") (pin "2") (pinfunction "2_2") (pintype "passive"))
      (node (ref "C83") (pin "2") (pinfunction "2_2") (pintype "passive"))
      (node (ref "C84") (pin "2") (pinfunction "2_2") (pintype "passive"))
      (node (ref "C85") (pin "2") (pinfunction "2_2") (pintype "passive"))
      (node (ref "C86") (pin "2") (pinfunction "2_2") (pintype "passive"))
      (node (ref "C87") (pin "2") (pinfunction "2_2") (pintype "passive"))
      (node (ref "C88") (pin "2") (pinfunction "2_2") (pintype "passive"))
      (node (ref "C89") (pin "2") (pinfunction "2_2") (pintype "passive"))
      (node (ref "C9") (pin "2") (pinfunction "2_2") (pintype "passive"))
      (node (ref "C90") (pin "2") (pinfunction "2_2") (pintype "passive"))
      (node (ref "C91") (pin "2") (pinfunction "2_2") (pintype "passive"))
      (node (ref "C92") (pin "2") (pinfunction "2_2") (pintype "passive"))
      (node (ref "C93") (pin "2") (pinfunction "2_2") (pintype "passive"))
      (node (ref "C94") (pin "2") (pinfunction "2_2") (pintype "passive"))
      (node (ref "C95") (pin "2") (pinfunction "2_2") (pintype "passive"))
      (node (ref "C96") (pin "2") (pinfunction "2_2") (pintype "passive"))
      (node (ref "C97") (pin "2") (pinfunction "2_2") (pintype "passive"))
      (node (ref "C98") (pin "2") (pinfunction "2_2") (pintype "passive"))
      (node (ref "C99") (pin "2") (pinfunction "2_2") (pintype "passive"))
      (node (ref "D1") (pin "11") (pinfunction "TE_11") (pintype "bidirectional"))
      (node (ref "D1") (pin "13") (pinfunction "TE_13") (pintype "bidirectional"))
      (node (ref "D1") (pin "15") (pinfunction "TE_15") (pintype "bidirectional"))
      (node (ref "D1") (pin "2") (pinfunction "DC_2") (pintype "passive"))
      (node (ref "D1") (pin "4") (pinfunction "DC_4") (pintype "passive"))
      (node (ref "D1") (pin "6") (pinfunction "DC_6") (pintype "passive"))
      (node (ref "D1") (pin "8") (pinfunction "DC_8") (pintype "passive"))
      (node (ref "D1") (pin "9") (pinfunction "TE_9") (pintype "bidirectional"))
      (node (ref "D10") (pin "11") (pinfunction "TE_11") (pintype "bidirectional"))
      (node (ref "D10") (pin "13") (pinfunction "TE_13") (pintype "bidirectional"))
      (node (ref "D10") (pin "15") (pinfunction "TE_15") (pintype "bidirectional"))
      (node (ref "D10") (pin "2") (pinfunction "DC_2") (pintype "passive"))
      (node (ref "D10") (pin "4") (pinfunction "DC_4") (pintype "passive"))
      (node (ref "D10") (pin "6") (pinfunction "DC_6") (pintype "passive"))
      (node (ref "D10") (pin "8") (pinfunction "DC_8") (pintype "passive"))
      (node (ref "D10") (pin "9") (pinfunction "TE_9") (pintype "bidirectional"))
      (node (ref "D11") (pin "11") (pinfunction "TE_11") (pintype "bidirectional"))
      (node (ref "D11") (pin "13") (pinfunction "TE_13") (pintype "bidirectional"))
      (node (ref "D11") (pin "15") (pinfunction "TE_15") (pintype "bidirectional"))
      (node (ref "D11") (pin "2") (pinfunction "DC_2") (pintype "passive"))
      (node (ref "D11") (pin "4") (pinfunction "DC_4") (pintype "passive"))
      (node (ref "D11") (pin "6") (pinfunction "DC_6") (pintype "passive"))
      (node (ref "D11") (pin "8") (pinfunction "DC_8") (pintype "passive"))
      (node (ref "D11") (pin "9") (pinfunction "TE_9") (pintype "bidirectional"))
      (node (ref "D12") (pin "11") (pinfunction "TE_11") (pintype "bidirectional"))
      (node (ref "D12") (pin "13") (pinfunction "TE_13") (pintype "bidirectional"))
      (node (ref "D12") (pin "15") (pinfunction "TE_15") (pintype "bidirectional"))
      (node (ref "D12") (pin "2") (pinfunction "DC_2") (pintype "passive"))
      (node (ref "D12") (pin "4") (pinfunction "DC_4") (pintype "passive"))
      (node (ref "D12") (pin "6") (pinfunction "DC_6") (pintype "passive"))
      (node (ref "D12") (pin "8") (pinfunction "DC_8") (pintype "passive"))
      (node (ref "D12") (pin "9") (pinfunction "TE_9") (pintype "bidirectional"))
      (node (ref "D13") (pin "11") (pinfunction "TE_11") (pintype "bidirectional"))
      (node (ref "D13") (pin "13") (pinfunction "TE_13") (pintype "bidirectional"))
      (node (ref "D13") (pin "15") (pinfunction "TE_15") (pintype "bidirectional"))
      (node (ref "D13") (pin "2") (pinfunction "DC_2") (pintype "passive"))
      (node (ref "D13") (pin "4") (pinfunction "DC_4") (pintype "passive"))
      (node (ref "D13") (pin "6") (pinfunction "DC_6") (pintype "passive"))
      (node (ref "D13") (pin "8") (pinfunction "DC_8") (pintype "passive"))
      (node (ref "D13") (pin "9") (pinfunction "TE_9") (pintype "bidirectional"))
      (node (ref "D14") (pin "11") (pinfunction "TE_11") (pintype "bidirectional"))
      (node (ref "D14") (pin "13") (pinfunction "TE_13") (pintype "bidirectional"))
      (node (ref "D14") (pin "15") (pinfunction "TE_15") (pintype "bidirectional"))
      (node (ref "D14") (pin "2") (pinfunction "DC_2") (pintype "passive"))
      (node (ref "D14") (pin "4") (pinfunction "DC_4") (pintype "passive"))
      (node (ref "D14") (pin "6") (pinfunction "DC_6") (pintype "passive"))
      (node (ref "D14") (pin "8") (pinfunction "DC_8") (pintype "passive"))
      (node (ref "D14") (pin "9") (pinfunction "TE_9") (pintype "bidirectional"))
      (node (ref "D15") (pin "11") (pinfunction "TE_11") (pintype "bidirectional"))
      (node (ref "D15") (pin "13") (pinfunction "TE_13") (pintype "bidirectional"))
      (node (ref "D15") (pin "15") (pinfunction "TE_15") (pintype "bidirectional"))
      (node (ref "D15") (pin "2") (pinfunction "DC_2") (pintype "passive"))
      (node (ref "D15") (pin "4") (pinfunction "DC_4") (pintype "passive"))
      (node (ref "D15") (pin "6") (pinfunction "DC_6") (pintype "passive"))
      (node (ref "D15") (pin "8") (pinfunction "DC_8") (pintype "passive"))
      (node (ref "D15") (pin "9") (pinfunction "TE_9") (pintype "bidirectional"))
      (node (ref "D16") (pin "11") (pinfunction "TE_11") (pintype "bidirectional"))
      (node (ref "D16") (pin "13") (pinfunction "TE_13") (pintype "bidirectional"))
      (node (ref "D16") (pin "15") (pinfunction "TE_15") (pintype "bidirectional"))
      (node (ref "D16") (pin "2") (pinfunction "DC_2") (pintype "passive"))
      (node (ref "D16") (pin "4") (pinfunction "DC_4") (pintype "passive"))
      (node (ref "D16") (pin "6") (pinfunction "DC_6") (pintype "passive"))
      (node (ref "D16") (pin "8") (pinfunction "DC_8") (pintype "passive"))
      (node (ref "D16") (pin "9") (pinfunction "TE_9") (pintype "bidirectional"))
      (node (ref "D17") (pin "11") (pinfunction "TE_11") (pintype "bidirectional"))
      (node (ref "D17") (pin "13") (pinfunction "TE_13") (pintype "bidirectional"))
      (node (ref "D17") (pin "15") (pinfunction "TE_15") (pintype "bidirectional"))
      (node (ref "D17") (pin "2") (pinfunction "DC_2") (pintype "passive"))
      (node (ref "D17") (pin "4") (pinfunction "DC_4") (pintype "passive"))
      (node (ref "D17") (pin "6") (pinfunction "DC_6") (pintype "passive"))
      (node (ref "D17") (pin "8") (pinfunction "DC_8") (pintype "passive"))
      (node (ref "D17") (pin "9") (pinfunction "TE_9") (pintype "bidirectional"))
      (node (ref "D18") (pin "11") (pinfunction "TE_11") (pintype "bidirectional"))
      (node (ref "D18") (pin "13") (pinfunction "TE_13") (pintype "bidirectional"))
      (node (ref "D18") (pin "15") (pinfunction "TE_15") (pintype "bidirectional"))
      (node (ref "D18") (pin "2") (pinfunction "DC_2") (pintype "passive"))
      (node (ref "D18") (pin "4") (pinfunction "DC_4") (pintype "passive"))
      (node (ref "D18") (pin "6") (pinfunction "DC_6") (pintype "passive"))
      (node (ref "D18") (pin "8") (pinfunction "DC_8") (pintype "passive"))
      (node (ref "D18") (pin "9") (pinfunction "TE_9") (pintype "bidirectional"))
      (node (ref "D19") (pin "11") (pinfunction "TE_11") (pintype "bidirectional"))
      (node (ref "D19") (pin "13") (pinfunction "TE_13") (pintype "bidirectional"))
      (node (ref "D19") (pin "15") (pinfunction "TE_15") (pintype "bidirectional"))
      (node (ref "D19") (pin "2") (pinfunction "DC_2") (pintype "passive"))
      (node (ref "D19") (pin "4") (pinfunction "DC_4") (pintype "passive"))
      (node (ref "D19") (pin "6") (pinfunction "DC_6") (pintype "passive"))
      (node (ref "D19") (pin "8") (pinfunction "DC_8") (pintype "passive"))
      (node (ref "D19") (pin "9") (pinfunction "TE_9") (pintype "bidirectional"))
      (node (ref "D2") (pin "11") (pinfunction "TE_11") (pintype "bidirectional"))
      (node (ref "D2") (pin "13") (pinfunction "TE_13") (pintype "bidirectional"))
      (node (ref "D2") (pin "15") (pinfunction "TE_15") (pintype "bidirectional"))
      (node (ref "D2") (pin "2") (pinfunction "DC_2") (pintype "passive"))
      (node (ref "D2") (pin "4") (pinfunction "DC_4") (pintype "passive"))
      (node (ref "D2") (pin "6") (pinfunction "DC_6") (pintype "passive"))
      (node (ref "D2") (pin "8") (pinfunction "DC_8") (pintype "passive"))
      (node (ref "D2") (pin "9") (pinfunction "TE_9") (pintype "bidirectional"))
      (node (ref "D3") (pin "11") (pinfunction "TE_11") (pintype "bidirectional"))
      (node (ref "D3") (pin "13") (pinfunction "TE_13") (pintype "bidirectional"))
      (node (ref "D3") (pin "15") (pinfunction "TE_15") (pintype "bidirectional"))
      (node (ref "D3") (pin "2") (pinfunction "DC_2") (pintype "passive"))
      (node (ref "D3") (pin "4") (pinfunction "DC_4") (pintype "passive"))
      (node (ref "D3") (pin "6") (pinfunction "DC_6") (pintype "passive"))
      (node (ref "D3") (pin "8") (pinfunction "DC_8") (pintype "passive"))
      (node (ref "D3") (pin "9") (pinfunction "TE_9") (pintype "bidirectional"))
      (node (ref "D4") (pin "11") (pinfunction "TE_11") (pintype "bidirectional"))
      (node (ref "D4") (pin "13") (pinfunction "TE_13") (pintype "bidirectional"))
      (node (ref "D4") (pin "15") (pinfunction "TE_15") (pintype "bidirectional"))
      (node (ref "D4") (pin "2") (pinfunction "DC_2") (pintype "passive"))
      (node (ref "D4") (pin "4") (pinfunction "DC_4") (pintype "passive"))
      (node (ref "D4") (pin "6") (pinfunction "DC_6") (pintype "passive"))
      (node (ref "D4") (pin "8") (pinfunction "DC_8") (pintype "passive"))
      (node (ref "D4") (pin "9") (pinfunction "TE_9") (pintype "bidirectional"))
      (node (ref "D6") (pin "11") (pinfunction "TE_11") (pintype "bidirectional"))
      (node (ref "D6") (pin "13") (pinfunction "TE_13") (pintype "bidirectional"))
      (node (ref "D6") (pin "15") (pinfunction "TE_15") (pintype "bidirectional"))
      (node (ref "D6") (pin "2") (pinfunction "DC_2") (pintype "passive"))
      (node (ref "D6") (pin "4") (pinfunction "DC_4") (pintype "passive"))
      (node (ref "D6") (pin "6") (pinfunction "DC_6") (pintype "passive"))
      (node (ref "D6") (pin "8") (pinfunction "DC_8") (pintype "passive"))
      (node (ref "D6") (pin "9") (pinfunction "TE_9") (pintype "bidirectional"))
      (node (ref "D7") (pin "11") (pinfunction "TE_11") (pintype "bidirectional"))
      (node (ref "D7") (pin "13") (pinfunction "TE_13") (pintype "bidirectional"))
      (node (ref "D7") (pin "15") (pinfunction "TE_15") (pintype "bidirectional"))
      (node (ref "D7") (pin "2") (pinfunction "DC_2") (pintype "passive"))
      (node (ref "D7") (pin "4") (pinfunction "DC_4") (pintype "passive"))
      (node (ref "D7") (pin "6") (pinfunction "DC_6") (pintype "passive"))
      (node (ref "D7") (pin "8") (pinfunction "DC_8") (pintype "passive"))
      (node (ref "D7") (pin "9") (pinfunction "TE_9") (pintype "bidirectional"))
      (node (ref "D8") (pin "11") (pinfunction "TE_11") (pintype "bidirectional"))
      (node (ref "D8") (pin "13") (pinfunction "TE_13") (pintype "bidirectional"))
      (node (ref "D8") (pin "15") (pinfunction "TE_15") (pintype "bidirectional"))
      (node (ref "D8") (pin "2") (pinfunction "DC_2") (pintype "passive"))
      (node (ref "D8") (pin "4") (pinfunction "DC_4") (pintype "passive"))
      (node (ref "D8") (pin "6") (pinfunction "DC_6") (pintype "passive"))
      (node (ref "D8") (pin "8") (pinfunction "DC_8") (pintype "passive"))
      (node (ref "D8") (pin "9") (pinfunction "TE_9") (pintype "bidirectional"))
      (node (ref "D9") (pin "11") (pinfunction "TE_11") (pintype "bidirectional"))
      (node (ref "D9") (pin "13") (pinfunction "TE_13") (pintype "bidirectional"))
      (node (ref "D9") (pin "15") (pinfunction "TE_15") (pintype "bidirectional"))
      (node (ref "D9") (pin "2") (pinfunction "DC_2") (pintype "passive"))
      (node (ref "D9") (pin "4") (pinfunction "DC_4") (pintype "passive"))
      (node (ref "D9") (pin "6") (pinfunction "DC_6") (pintype "passive"))
      (node (ref "D9") (pin "8") (pinfunction "DC_8") (pintype "passive"))
      (node (ref "D9") (pin "9") (pinfunction "TE_9") (pintype "bidirectional"))
      (node (ref "DA10") (pin "1") (pinfunction "GND_1") (pintype "power_in"))
      (node (ref "DA11") (pin "3") (pinfunction "GND_3") (pintype "power_in"))
      (node (ref "DA12") (pin "3") (pinfunction "GND_3") (pintype "input"))
      (node (ref "DA12") (pin "5") (pinfunction "~{ON}/OFF_5") (pintype "input"))
      (node (ref "DA12") (pin "6") (pinfunction "GND_6") (pintype "input"))
      (node (ref "DA13") (pin "4") (pinfunction "FB_4") (pintype "input"))
      (node (ref "DA14") (pin "1") (pinfunction "ADJ_1") (pintype "input"))
      (node (ref "DA15") (pin "2") (pinfunction "GND_2") (pintype "power_in"))
      (node (ref "DA16") (pin "2") (pinfunction "GND_2") (pintype "power_in"))
      (node (ref "DA17") (pin "15") (pinfunction "GND_15") (pintype "power_in"))
      (node (ref "DA4") (pin "1") (pinfunction "E_OUT_1") (pintype "bidirectional"))
      (node (ref "DA5") (pin "1") (pinfunction "E_OUT_1") (pintype "bidirectional"))
      (node (ref "DA6") (pin "1") (pinfunction "E_OUT_1") (pintype "bidirectional"))
      (node (ref "DA7") (pin "1") (pinfunction "~{D}_1") (pintype "input"))
      (node (ref "DA7") (pin "8") (pinfunction "GND_8") (pintype "power_in"))
      (node (ref "DA8") (pin "1") (pinfunction "~{D}_1") (pintype "input"))
      (node (ref "DA8") (pin "8") (pinfunction "GND_8") (pintype "power_in"))
      (node (ref "DA9") (pin "1") (pinfunction "~{D}_1") (pintype "input"))
      (node (ref "DA9") (pin "8") (pinfunction "GND_8") (pintype "power_in"))
      (node (ref "DD1") (pin "10") (pinfunction "VSS_5_10") (pintype "power_in"))
      (node (ref "DD1") (pin "27") (pinfunction "VSS_4_27") (pintype "power_in"))
      (node (ref "DD1") (pin "49") (pinfunction "VSS_1_49") (pintype "power_in"))
      (node (ref "DD1") (pin "74") (pinfunction "VSS_2_74") (pintype "power_in"))
      (node (ref "DD1") (pin "99") (pinfunction "VSS_3_99") (pintype "power_in"))
      (node (ref "DD10") (pin "8") (pinfunction "GND_8") (pintype "power_in"))
      (node (ref "DD11") (pin "8") (pinfunction "GND_8") (pintype "power_in"))
      (node (ref "DD12") (pin "8") (pinfunction "GND_8") (pintype "power_in"))
      (node (ref "DD2") (pin "1") (pinfunction "A0_1") (pintype "input"))
      (node (ref "DD2") (pin "2") (pinfunction "A1_2") (pintype "input"))
      (node (ref "DD2") (pin "3") (pinfunction "A2_3") (pintype "input"))
      (node (ref "DD2") (pin "4") (pinfunction "GND_4") (pintype "power_in"))
      (node (ref "DD2") (pin "7") (pinfunction "WP_7") (pintype "input"))
      (node (ref "DD3") (pin "7") (pinfunction "GND_7") (pintype "power_in"))
      (node (ref "DD4") (pin "8") (pinfunction "GND_8") (pintype "power_in"))
      (node (ref "DD5") (pin "8") (pinfunction "GND_8") (pintype "power_in"))
      (node (ref "DD6") (pin "8") (pinfunction "GND_8") (pintype "power_in"))
      (node (ref "DD7") (pin "8") (pinfunction "GND_8") (pintype "power_in"))
      (node (ref "DD8") (pin "8") (pinfunction "GND_8") (pintype "power_in"))
      (node (ref "DD9") (pin "8") (pinfunction "GND_8") (pintype "power_in"))
      (node (ref "L3") (pin "2") (pinfunction "2_2") (pintype "passive"))
      (node (ref "R10") (pin "1") (pinfunction "1_1") (pintype "passive"))
      (node (ref "R100") (pin "1") (pinfunction "1_1") (pintype "passive"))
      (node (ref "R104") (pin "2") (pinfunction "2_2") (pintype "passive"))
      (node (ref "R105") (pin "2") (pinfunction "2_2") (pintype "passive"))
      (node (ref "R106") (pin "2") (pinfunction "2_2") (pintype "passive"))
      (node (ref "R128") (pin "1") (pinfunction "1_1") (pintype "passive"))
      (node (ref "R129") (pin "1") (pinfunction "1_1") (pintype "passive"))
      (node (ref "R13") (pin "1") (pinfunction "1_1") (pintype "passive"))
      (node (ref "R133") (pin "1") (pinfunction "1_1") (pintype "passive"))
      (node (ref "R14") (pin "1") (pinfunction "1_1") (pintype "passive"))
      (node (ref "R187") (pin "1") (pinfunction "1_1") (pintype "passive"))
      (node (ref "R188") (pin "1") (pinfunction "1_1") (pintype "passive"))
      (node (ref "R3") (pin "2") (pinfunction "2_2") (pintype "passive"))
      (node (ref "R342") (pin "1") (pinfunction "1_1") (pintype "passive"))
      (node (ref "R343") (pin "1") (pinfunction "1_1") (pintype "passive"))
      (node (ref "R344") (pin "1") (pinfunction "1_1") (pintype "passive"))
      (node (ref "R345") (pin "1") (pinfunction "1_1") (pintype "passive"))
      (node (ref "R346") (pin "1") (pinfunction "1_1") (pintype "passive"))
      (node (ref "R347") (pin "1") (pinfunction "1_1") (pintype "passive"))
      (node (ref "R348") (pin "1") (pinfunction "1_1") (pintype "passive"))
      (node (ref "R349") (pin "1") (pinfunction "1_1") (pintype "passive"))
      (node (ref "R360") (pin "1") (pinfunction "1_1") (pintype "passive"))
      (node (ref "R4") (pin "2") (pinfunction "2_2") (pintype "passive"))
      (node (ref "R5") (pin "2") (pinfunction "2_2") (pintype "passive"))
      (node (ref "R74") (pin "1") (pinfunction "1_1") (pintype "passive"))
      (node (ref "R75") (pin "1") (pinfunction "1_1") (pintype "passive"))
      (node (ref "R76") (pin "1") (pinfunction "1_1") (pintype "passive"))
      (node (ref "R86") (pin "2") (pinfunction "2_2") (pintype "passive"))
      (node (ref "R90") (pin "1") (pinfunction "1_1") (pintype "passive"))
      (node (ref "R91") (pin "2") (pinfunction "2_2") (pintype "passive"))
      (node (ref "R95") (pin "1") (pinfunction "1_1") (pintype "passive"))
      (node (ref "R96") (pin "2") (pinfunction "2_2") (pintype "passive"))
      (node (ref "SB1") (pin "1") (pinfunction "1_1") (pintype "passive"))
      (node (ref "SB1") (pin "2") (pinfunction "2_2") (pintype "passive"))
      (node (ref "VD10") (pin "A2") (pinfunction "A2_A2") (pintype "passive"))
      (node (ref "VD100") (pin "A") (pinfunction "A_A") (pintype "passive"))
      (node (ref "VD101") (pin "A") (pinfunction "A_A") (pintype "passive"))
      (node (ref "VD102") (pin "A") (pinfunction "A_A") (pintype "passive"))
      (node (ref "VD103") (pin "A") (pinfunction "A_A") (pintype "passive"))
      (node (ref "VD104") (pin "A") (pinfunction "A_A") (pintype "passive"))
      (node (ref "VD105") (pin "A") (pinfunction "A_A") (pintype "passive"))
      (node (ref "VD106") (pin "A") (pinfunction "A_A") (pintype "passive"))
      (node (ref "VD107") (pin "A") (pinfunction "A_A") (pintype "passive"))
      (node (ref "VD108") (pin "A") (pinfunction "A_A") (pintype "passive"))
      (node (ref "VD109") (pin "A") (pinfunction "A_A") (pintype "passive"))
      (node (ref "VD11") (pin "A2") (pinfunction "A2_A2") (pintype "passive"))
      (node (ref "VD110") (pin "A") (pinfunction "A_A") (pintype "passive"))
      (node (ref "VD111") (pin "A") (pinfunction "A_A") (pintype "passive"))
      (node (ref "VD112") (pin "A") (pinfunction "A_A") (pintype "passive"))
      (node (ref "VD113") (pin "A") (pinfunction "A_A") (pintype "passive"))
      (node (ref "VD114") (pin "A") (pinfunction "A_A") (pintype "passive"))
      (node (ref "VD115") (pin "A") (pinfunction "A_A") (pintype "passive"))
      (node (ref "VD132") (pin "A") (pinfunction "A_A") (pintype "passive"))
      (node (ref "VD133") (pin "A") (pinfunction "A_A") (pintype "passive"))
      (node (ref "VD134") (pin "A") (pinfunction "A_A") (pintype "passive"))
      (node (ref "VD135") (pin "A") (pinfunction "A_A") (pintype "passive"))
      (node (ref "VD136") (pin "A") (pinfunction "A_A") (pintype "passive"))
      (node (ref "VD137") (pin "A") (pinfunction "A_A") (pintype "passive"))
      (node (ref "VD138") (pin "A") (pinfunction "A_A") (pintype "passive"))
      (node (ref "VD139") (pin "A") (pinfunction "A_A") (pintype "passive"))
      (node (ref "VD140") (pin "A") (pinfunction "A_A") (pintype "passive"))
      (node (ref "VD141") (pin "A") (pinfunction "A_A") (pintype "passive"))
      (node (ref "VD142") (pin "A") (pinfunction "A_A") (pintype "passive"))
      (node (ref "VD143") (pin "A") (pinfunction "A_A") (pintype "passive"))
      (node (ref "VD144") (pin "A") (pinfunction "A_A") (pintype "passive"))
      (node (ref "VD145") (pin "A") (pinfunction "A_A") (pintype "passive"))
      (node (ref "VD146") (pin "A") (pinfunction "A_A") (pintype "passive"))
      (node (ref "VD147") (pin "A") (pinfunction "A_A") (pintype "passive"))
      (node (ref "VD164") (pin "A") (pinfunction "A_A") (pintype "passive"))
      (node (ref "VD165") (pin "A") (pinfunction "A_A") (pintype "passive"))
      (node (ref "VD166") (pin "A") (pinfunction "A_A") (pintype "passive"))
      (node (ref "VD167") (pin "A") (pinfunction "A_A") (pintype "passive"))
      (node (ref "VD168") (pin "A") (pinfunction "A_A") (pintype "passive"))
      (node (ref "VD169") (pin "A") (pinfunction "A_A") (pintype "passive"))
      (node (ref "VD170") (pin "A") (pinfunction "A_A") (pintype "passive"))
      (node (ref "VD171") (pin "A") (pinfunction "A_A") (pintype "passive"))
      (node (ref "VD172") (pin "A") (pinfunction "A_A") (pintype "passive"))
      (node (ref "VD173") (pin "A") (pinfunction "A_A") (pintype "passive"))
      (node (ref "VD174") (pin "A") (pinfunction "A_A") (pintype "passive"))
      (node (ref "VD175") (pin "A") (pinfunction "A_A") (pintype "passive"))
      (node (ref "VD176") (pin "A") (pinfunction "A_A") (pintype "passive"))
      (node (ref "VD177") (pin "A") (pinfunction "A_A") (pintype "passive"))
      (node (ref "VD178") (pin "A") (pinfunction "A_A") (pintype "passive"))
      (node (ref "VD179") (pin "A") (pinfunction "A_A") (pintype "passive"))
      (node (ref "VD196") (pin "A") (pinfunction "A_A") (pintype "passive"))
      (node (ref "VD197") (pin "A") (pinfunction "A_A") (pintype "passive"))
      (node (ref "VD198") (pin "A") (pinfunction "A_A") (pintype "passive"))
      (node (ref "VD199") (pin "A") (pinfunction "A_A") (pintype "passive"))
      (node (ref "VD20") (pin "A2") (pinfunction "A2_A2") (pintype "passive"))
      (node (ref "VD200") (pin "A") (pinfunction "A_A") (pintype "passive"))
      (node (ref "VD201") (pin "A") (pinfunction "A_A") (pintype "passive"))
      (node (ref "VD202") (pin "A") (pinfunction "A_A") (pintype "passive"))
      (node (ref "VD203") (pin "A") (pinfunction "A_A") (pintype "passive"))
      (node (ref "VD21") (pin "A2") (pinfunction "A2_A2") (pintype "passive"))
      (node (ref "VD212") (pin "A1") (pinfunction "A1_A1") (pintype "passive"))
      (node (ref "VD213") (pin "A1") (pinfunction "A1_A1") (pintype "passive"))
      (node (ref "VD214") (pin "A") (pinfunction "A_A") (pintype "passive"))
      (node (ref "VD22") (pin "A2") (pinfunction "A2_A2") (pintype "passive"))
      (node (ref "VD23") (pin "A2") (pinfunction "A2_A2") (pintype "passive"))
      (node (ref "VD24") (pin "A2") (pinfunction "A2_A2") (pintype "passive"))
      (node (ref "VD25") (pin "A2") (pinfunction "A2_A2") (pintype "passive"))
      (node (ref "VD26") (pin "A2") (pinfunction "A2_A2") (pintype "passive"))
      (node (ref "VD27") (pin "A2") (pinfunction "A2_A2") (pintype "passive"))
      (node (ref "VD37") (pin "A") (pinfunction "A_A") (pintype "passive"))
      (node (ref "VD39") (pin "A") (pinfunction "A_A") (pintype "passive"))
      (node (ref "VD4") (pin "A2") (pinfunction "A2_A2") (pintype "passive"))
      (node (ref "VD41") (pin "A") (pinfunction "A_A") (pintype "passive"))
      (node (ref "VD42") (pin "A") (pinfunction "A_A") (pintype "passive"))
      (node (ref "VD44") (pin "A") (pinfunction "A_A") (pintype "passive"))
      (node (ref "VD46") (pin "A") (pinfunction "A_A") (pintype "passive"))
      (node (ref "VD48") (pin "A2") (pinfunction "A2_A2") (pintype "passive"))
      (node (ref "VD49") (pin "A2") (pinfunction "A2_A2") (pintype "passive"))
      (node (ref "VD5") (pin "A2") (pinfunction "A2_A2") (pintype "passive"))
      (node (ref "VD50") (pin "A") (pinfunction "A_A") (pintype "passive"))
      (node (ref "VD51") (pin "A") (pinfunction "A_A") (pintype "passive"))
      (node (ref "VD52") (pin "A") (pinfunction "A_A") (pintype "passive"))
      (node (ref "VD54") (pin "A1") (pinfunction "A1_A1") (pintype "passive"))
      (node (ref "VD55") (pin "A") (pinfunction "A_A") (pintype "passive"))
      (node (ref "VD57") (pin "A2") (pinfunction "A2_A2") (pintype "passive"))
      (node (ref "VD58") (pin "A") (pinfunction "A_A") (pintype "passive"))
      (node (ref "VD6") (pin "A2") (pinfunction "A2_A2") (pintype "passive"))
      (node (ref "VD63") (pin "A") (pinfunction "A_A") (pintype "passive"))
      (node (ref "VD64") (pin "C") (pinfunction "C_C") (pintype "passive"))
      (node (ref "VD65") (pin "A") (pinfunction "A_A") (pintype "passive"))
      (node (ref "VD66") (pin "A") (pinfunction "A_A") (pintype "passive"))
      (node (ref "VD67") (pin "A") (pinfunction "A_A") (pintype "passive"))
      (node (ref "VD68") (pin "A") (pinfunction "A_A") (pintype "passive"))
      (node (ref "VD69") (pin "A") (pinfunction "A_A") (pintype "passive"))
      (node (ref "VD7") (pin "A2") (pinfunction "A2_A2") (pintype "passive"))
      (node (ref "VD70") (pin "A") (pinfunction "A_A") (pintype "passive"))
      (node (ref "VD71") (pin "A") (pinfunction "A_A") (pintype "passive"))
      (node (ref "VD72") (pin "A") (pinfunction "A_A") (pintype "passive"))
      (node (ref "VD73") (pin "A") (pinfunction "A_A") (pintype "passive"))
      (node (ref "VD74") (pin "A") (pinfunction "A_A") (pintype "passive"))
      (node (ref "VD75") (pin "A") (pinfunction "A_A") (pintype "passive"))
      (node (ref "VD76") (pin "A") (pinfunction "A_A") (pintype "passive"))
      (node (ref "VD77") (pin "A") (pinfunction "A_A") (pintype "passive"))
      (node (ref "VD78") (pin "A") (pinfunction "A_A") (pintype "passive"))
      (node (ref "VD79") (pin "A") (pinfunction "A_A") (pintype "passive"))
      (node (ref "VD8") (pin "A2") (pinfunction "A2_A2") (pintype "passive"))
      (node (ref "VD80") (pin "A") (pinfunction "A_A") (pintype "passive"))
      (node (ref "VD81") (pin "A") (pinfunction "A_A") (pintype "passive"))
      (node (ref "VD9") (pin "A2") (pinfunction "A2_A2") (pintype "passive"))
      (node (ref "VD99") (pin "A") (pinfunction "A_A") (pintype "passive"))
      (node (ref "VT2") (pin "E") (pinfunction "E_E") (pintype "passive"))
      (node (ref "VT4") (pin "E") (pinfunction "E_E") (pintype "passive"))
      (node (ref "XP1") (pin "10") (pinfunction "10_10") (pintype "passive"))
      (node (ref "XP1") (pin "12") (pinfunction "12_12") (pintype "passive"))
      (node (ref "XP1") (pin "14") (pinfunction "14_14") (pintype "passive"))
      (node (ref "XP1") (pin "16") (pinfunction "16_16") (pintype "passive"))
      (node (ref "XP1") (pin "18") (pinfunction "18_18") (pintype "passive"))
      (node (ref "XP1") (pin "20") (pinfunction "20_20") (pintype "passive"))
      (node (ref "XP1") (pin "4") (pinfunction "4_4") (pintype "passive"))
      (node (ref "XP1") (pin "6") (pinfunction "6_6") (pintype "passive"))
      (node (ref "XP1") (pin "8") (pinfunction "8_8") (pintype "passive"))
      (node (ref "XP2") (pin "3") (pinfunction "3_3") (pintype "passive"))
      (node (ref "XP3") (pin "3") (pinfunction "3_3") (pintype "passive"))
      (node (ref "XP4") (pin "16") (pinfunction "16_16") (pintype "passive"))
      (node (ref "XP6") (pin "1") (pinfunction "1_1") (pintype "passive"))
      (node (ref "XP6") (pin "3") (pinfunction "3_3") (pintype "passive"))
      (node (ref "XP6") (pin "5") (pinfunction "5_5") (pintype "passive"))
      (node (ref "XP6") (pin "7") (pinfunction "7_7") (pintype "passive"))
      (node (ref "XS1") (pin "GND") (pinfunction "5_GND") (pintype "passive"))
      (node (ref "Z1") (pin "2") (pinfunction "2_2") (pintype "passive"))
      (node (ref "Z10") (pin "2") (pinfunction "2_2") (pintype "passive"))
      (node (ref "Z11") (pin "2") (pinfunction "2_2") (pintype "passive"))
      (node (ref "Z12") (pin "2") (pinfunction "2_2") (pintype "passive"))
      (node (ref "Z13") (pin "2") (pinfunction "2_2") (pintype "passive"))
      (node (ref "Z14") (pin "2") (pinfunction "2_2") (pintype "passive"))
      (node (ref "Z15") (pin "2") (pinfunction "2_2") (pintype "passive"))
      (node (ref "Z16") (pin "2") (pinfunction "2_2") (pintype "passive"))
      (node (ref "Z17") (pin "2") (pinfunction "2_2") (pintype "passive"))
      (node (ref "Z18") (pin "2") (pinfunction "2_2") (pintype "passive"))
      (node (ref "Z19") (pin "2") (pinfunction "2_2") (pintype "passive"))
      (node (ref "Z2") (pin "2") (pinfunction "2_2") (pintype "passive"))
      (node (ref "Z20") (pin "2") (pinfunction "2_2") (pintype "passive"))
      (node (ref "Z21") (pin "2") (pinfunction "2_2") (pintype "passive"))
      (node (ref "Z22") (pin "2") (pinfunction "2_2") (pintype "passive"))
      (node (ref "Z23") (pin "2") (pinfunction "2_2") (pintype "passive"))
      (node (ref "Z24") (pin "2") (pinfunction "2_2") (pintype "passive"))
      (node (ref "Z25") (pin "2") (pinfunction "2_2") (pintype "passive"))
      (node (ref "Z26") (pin "2") (pinfunction "2_2") (pintype "passive"))
      (node (ref "Z27") (pin "2") (pinfunction "2_2") (pintype "passive"))
      (node (ref "Z28") (pin "2") (pinfunction "2_2") (pintype "passive"))
      (node (ref "Z29") (pin "2") (pinfunction "2_2") (pintype "passive"))
      (node (ref "Z3") (pin "2") (pinfunction "2_2") (pintype "passive"))
      (node (ref "Z30") (pin "2") (pinfunction "2_2") (pintype "passive"))
      (node (ref "Z31") (pin "2") (pinfunction "2_2") (pintype "passive"))
      (node (ref "Z32") (pin "2") (pinfunction "2_2") (pintype "passive"))
      (node (ref "Z33") (pin "2") (pinfunction "2_2") (pintype "passive"))
      (node (ref "Z34") (pin "2") (pinfunction "2_2") (pintype "passive"))
      (node (ref "Z35") (pin "2") (pinfunction "2_2") (pintype "passive"))
      (node (ref "Z36") (pin "2") (pinfunction "2_2") (pintype "passive"))
      (node (ref "Z37") (pin "2") (pinfunction "2_2") (pintype "passive"))
      (node (ref "Z38") (pin "2") (pinfunction "2_2") (pintype "passive"))
      (node (ref "Z39") (pin "2") (pinfunction "2_2") (pintype "passive"))
      (node (ref "Z4") (pin "2") (pinfunction "2_2") (pintype "passive"))
      (node (ref "Z40") (pin "2") (pinfunction "2_2") (pintype "passive"))
      (node (ref "Z41") (pin "2") (pinfunction "2_2") (pintype "passive"))
      (node (ref "Z42") (pin "2") (pinfunction "2_2") (pintype "passive"))
      (node (ref "Z43") (pin "2") (pinfunction "2_2") (pintype "passive"))
      (node (ref "Z44") (pin "2") (pinfunction "2_2") (pintype "passive"))
      (node (ref "Z45") (pin "2") (pinfunction "2_2") (pintype "passive"))
      (node (ref "Z46") (pin "2") (pinfunction "2_2") (pintype "passive"))
      (node (ref "Z47") (pin "2") (pinfunction "2_2") (pintype "passive"))
      (node (ref "Z48") (pin "2") (pinfunction "2_2") (pintype "passive"))
      (node (ref "Z49") (pin "2") (pinfunction "2_2") (pintype "passive"))
      (node (ref "Z5") (pin "2") (pinfunction "2_2") (pintype "passive"))
      (node (ref "Z50") (pin "2") (pinfunction "2_2") (pintype "passive"))
      (node (ref "Z6") (pin "2") (pinfunction "2_2") (pintype "passive"))
      (node (ref "Z7") (pin "2") (pinfunction "2_2") (pintype "passive"))
      (node (ref "Z8") (pin "2") (pinfunction "2_2") (pintype "passive"))
      (node (ref "Z9") (pin "2") (pinfunction "2_2") (pintype "passive"))
    )
    (net (code "47") (name "JTCK") (class "Default")
      (node (ref "DD1") (pin "76") (pinfunction "JTCK/SWCLK(PA14)*_76") (pintype "bidirectional"))
      (node (ref "Z7") (pin "1") (pinfunction "1_1") (pintype "passive"))
    )
    (net (code "48") (name "JTDI") (class "Default")
      (node (ref "DD1") (pin "77") (pinfunction "JTDI(PA15/SPI3_NSS/I2S3_WS/TIM2_CH1_ETR/SPI1_NSS)*_77") (pintype "bidirectional"))
      (node (ref "Z6") (pin "1") (pinfunction "1_1") (pintype "passive"))
    )
    (net (code "49") (name "JTDO") (class "Default")
      (node (ref "DD1") (pin "89") (pinfunction "JTDO(PB3/SPI3_SCK/I2S3_CK/TRACEWO/TIM2_CH2/SPI1_SCK)*_89") (pintype "bidirectional"))
      (node (ref "Z4") (pin "1") (pinfunction "1_1") (pintype "passive"))
    )
    (net (code "50") (name "JTMS") (class "Default")
      (node (ref "DD1") (pin "72") (pinfunction "JTMS/SWDIO(PA13)*_72") (pintype "bidirectional"))
      (node (ref "Z3") (pin "1") (pinfunction "1_1") (pintype "passive"))
    )
    (net (code "51") (name "JTRST") (class "Default")
      (node (ref "DD1") (pin "90") (pinfunction "NJTRST(PB4/SPI3_MISO/TIM3_CH1/SPI1_MISO)*_90") (pintype "bidirectional"))
      (node (ref "Z2") (pin "1") (pinfunction "1_1") (pintype "passive"))
    )
    (net (code "52") (name "Net-(C10-Pad1)") (class "Default")
      (node (ref "C10") (pin "1") (pinfunction "1_1") (pintype "passive"))
      (node (ref "R9") (pin "1") (pinfunction "1_1") (pintype "passive"))
      (node (ref "SB1") (pin "3") (pinfunction "3_3") (pintype "passive"))
      (node (ref "SB1") (pin "4") (pinfunction "4_4") (pintype "passive"))
      (node (ref "XP1") (pin "15") (pinfunction "15_15") (pintype "passive"))
      (node (ref "Z8") (pin "3") (pinfunction "3_3") (pintype "passive"))
    )
    (net (code "53") (name "Net-(C12-Pad1)") (class "Default")
      (node (ref "C12") (pin "1") (pinfunction "1_1") (pintype "passive"))
      (node (ref "R34") (pin "2") (pinfunction "2_2") (pintype "passive"))
      (node (ref "R42") (pin "2") (pinfunction "2_2") (pintype "passive"))
      (node (ref "Z22") (pin "1") (pinfunction "1_1") (pintype "passive"))
    )
    (net (code "54") (name "Net-(C13-Pad1)") (class "Default")
      (node (ref "C13") (pin "1") (pinfunction "1_1") (pintype "passive"))
      (node (ref "R35") (pin "2") (pinfunction "2_2") (pintype "passive"))
      (node (ref "R43") (pin "2") (pinfunction "2_2") (pintype "passive"))
      (node (ref "Z23") (pin "1") (pinfunction "1_1") (pintype "passive"))
    )
    (net (code "55") (name "Net-(C14-Pad1)") (class "Default")
      (node (ref "C14") (pin "1") (pinfunction "1_1") (pintype "passive"))
      (node (ref "R36") (pin "2") (pinfunction "2_2") (pintype "passive"))
      (node (ref "R44") (pin "2") (pinfunction "2_2") (pintype "passive"))
      (node (ref "Z24") (pin "1") (pinfunction "1_1") (pintype "passive"))
    )
    (net (code "56") (name "Net-(C15-Pad1)") (class "Default")
      (node (ref "C15") (pin "1") (pinfunction "1_1") (pintype "passive"))
      (node (ref "R37") (pin "2") (pinfunction "2_2") (pintype "passive"))
      (node (ref "R45") (pin "2") (pinfunction "2_2") (pintype "passive"))
      (node (ref "Z25") (pin "1") (pinfunction "1_1") (pintype "passive"))
    )
    (net (code "57") (name "Net-(C16-Pad1)") (class "Default")
      (node (ref "C16") (pin "1") (pinfunction "1_1") (pintype "passive"))
      (node (ref "R38") (pin "2") (pinfunction "2_2") (pintype "passive"))
      (node (ref "R46") (pin "2") (pinfunction "2_2") (pintype "passive"))
      (node (ref "Z26") (pin "1") (pinfunction "1_1") (pintype "passive"))
    )
    (net (code "58") (name "Net-(C17-Pad1)") (class "Default")
      (node (ref "C17") (pin "1") (pinfunction "1_1") (pintype "passive"))
      (node (ref "R39") (pin "2") (pinfunction "2_2") (pintype "passive"))
      (node (ref "R47") (pin "2") (pinfunction "2_2") (pintype "passive"))
      (node (ref "Z27") (pin "1") (pinfunction "1_1") (pintype "passive"))
    )
    (net (code "59") (name "Net-(C18-Pad1)") (class "Default")
      (node (ref "C18") (pin "1") (pinfunction "1_1") (pintype "passive"))
      (node (ref "R40") (pin "2") (pinfunction "2_2") (pintype "passive"))
      (node (ref "R48") (pin "2") (pinfunction "2_2") (pintype "passive"))
      (node (ref "Z28") (pin "1") (pinfunction "1_1") (pintype "passive"))
    )
    (net (code "60") (name "Net-(C19-Pad1)") (class "Default")
      (node (ref "C19") (pin "1") (pinfunction "1_1") (pintype "passive"))
      (node (ref "R41") (pin "2") (pinfunction "2_2") (pintype "passive"))
      (node (ref "R49") (pin "2") (pinfunction "2_2") (pintype "passive"))
      (node (ref "Z29") (pin "1") (pinfunction "1_1") (pintype "passive"))
    )
    (net (code "61") (name "Net-(C20-Pad1)") (class "Default")
      (node (ref "C20") (pin "1") (pinfunction "1_1") (pintype "passive"))
      (node (ref "R58") (pin "2") (pinfunction "2_2") (pintype "passive"))
      (node (ref "R66") (pin "2") (pinfunction "2_2") (pintype "passive"))
      (node (ref "Z30") (pin "1") (pinfunction "1_1") (pintype "passive"))
    )
    (net (code "62") (name "Net-(C21-Pad1)") (class "Default")
      (node (ref "C21") (pin "1") (pinfunction "1_1") (pintype "passive"))
      (node (ref "R59") (pin "2") (pinfunction "2_2") (pintype "passive"))
      (node (ref "R67") (pin "2") (pinfunction "2_2") (pintype "passive"))
      (node (ref "Z31") (pin "1") (pinfunction "1_1") (pintype "passive"))
    )
    (net (code "63") (name "Net-(C22-Pad1)") (class "Default")
      (node (ref "C22") (pin "1") (pinfunction "1_1") (pintype "passive"))
      (node (ref "R60") (pin "2") (pinfunction "2_2") (pintype "passive"))
      (node (ref "R68") (pin "2") (pinfunction "2_2") (pintype "passive"))
      (node (ref "Z32") (pin "1") (pinfunction "1_1") (pintype "passive"))
    )
    (net (code "64") (name "Net-(C23-Pad1)") (class "Default")
      (node (ref "C23") (pin "1") (pinfunction "1_1") (pintype "passive"))
      (node (ref "R61") (pin "2") (pinfunction "2_2") (pintype "passive"))
      (node (ref "R69") (pin "2") (pinfunction "2_2") (pintype "passive"))
      (node (ref "Z33") (pin "1") (pinfunction "1_1") (pintype "passive"))
    )
    (net (code "65") (name "Net-(C24-Pad1)") (class "Default")
      (node (ref "C24") (pin "1") (pinfunction "1_1") (pintype "passive"))
      (node (ref "R62") (pin "2") (pinfunction "2_2") (pintype "passive"))
      (node (ref "R70") (pin "2") (pinfunction "2_2") (pintype "passive"))
      (node (ref "Z34") (pin "1") (pinfunction "1_1") (pintype "passive"))
    )
    (net (code "66") (name "Net-(C25-Pad1)") (class "Default")
      (node (ref "C25") (pin "1") (pinfunction "1_1") (pintype "passive"))
      (node (ref "R63") (pin "2") (pinfunction "2_2") (pintype "passive"))
      (node (ref "R71") (pin "2") (pinfunction "2_2") (pintype "passive"))
      (node (ref "Z35") (pin "1") (pinfunction "1_1") (pintype "passive"))
    )
    (net (code "67") (name "Net-(C26-Pad1)") (class "Default")
      (node (ref "C26") (pin "1") (pinfunction "1_1") (pintype "passive"))
      (node (ref "R64") (pin "2") (pinfunction "2_2") (pintype "passive"))
      (node (ref "R72") (pin "2") (pinfunction "2_2") (pintype "passive"))
      (node (ref "Z36") (pin "1") (pinfunction "1_1") (pintype "passive"))
    )
    (net (code "68") (name "Net-(C27-Pad1)") (class "Default")
      (node (ref "C27") (pin "1") (pinfunction "1_1") (pintype "passive"))
      (node (ref "R65") (pin "2") (pinfunction "2_2") (pintype "passive"))
      (node (ref "R73") (pin "2") (pinfunction "2_2") (pintype "passive"))
      (node (ref "Z37") (pin "1") (pinfunction "1_1") (pintype "passive"))
    )
    (net (code "69") (name "Net-(C53-Pad2)") (class "Default")
      (node (ref "C53") (pin "2") (pinfunction "2_2") (pintype "passive"))
      (node (ref "R124") (pin "1") (pinfunction "1_1") (pintype "passive"))
      (node (ref "R126") (pin "1") (pinfunction "1_1") (pintype "passive"))
      (node (ref "VD48") (pin "A1") (pinfunction "A1_A1") (pintype "passive"))
    )
    (net (code "70") (name "Net-(C54-Pad2)") (class "Default")
      (node (ref "C54") (pin "2") (pinfunction "2_2") (pintype "passive"))
      (node (ref "R125") (pin "1") (pinfunction "1_1") (pintype "passive"))
      (node (ref "R127") (pin "1") (pinfunction "1_1") (pintype "passive"))
      (node (ref "VD49") (pin "A1") (pinfunction "A1_A1") (pintype "passive"))
    )
    (net (code "71") (name "Net-(D1A-DA)") (class "Default")
      (node (ref "D1") (pin "1") (pinfunction "DA_1") (pintype "passive"))
      (node (ref "R138") (pin "2") (pinfunction "2_2") (pintype "passive"))
    )
    (net (code "72") (name "Net-(D1A-TC)") (class "Default")
      (node (ref "C69") (pin "1") (pinfunction "1_1") (pintype "passive"))
      (node (ref "D1") (pin "10") (pinfunction "TC_10") (pintype "bidirectional"))
      (node (ref "DD4") (pin "11") (pinfunction "A_11") (pintype "input"))
      (node (ref "R170") (pin "2") (pinfunction "2_2") (pintype "passive"))
    )
    (net (code "73") (name "Net-(D1B-DA)") (class "Default")
      (node (ref "D1") (pin "3") (pinfunction "DA_3") (pintype "passive"))
      (node (ref "R139") (pin "2") (pinfunction "2_2") (pintype "passive"))
    )
    (net (code "74") (name "Net-(D1B-TC)") (class "Default")
      (node (ref "C70") (pin "1") (pinfunction "1_1") (pintype "passive"))
      (node (ref "D1") (pin "12") (pinfunction "TC_12") (pintype "bidirectional"))
      (node (ref "DD4") (pin "12") (pinfunction "B_12") (pintype "input"))
      (node (ref "R171") (pin "2") (pinfunction "2_2") (pintype "passive"))
    )
    (net (code "75") (name "Net-(D1C-DA)") (class "Default")
      (node (ref "D1") (pin "5") (pinfunction "DA_5") (pintype "passive"))
      (node (ref "R140") (pin "2") (pinfunction "2_2") (pintype "passive"))
    )
    (net (code "76") (name "Net-(D1C-TC)") (class "Default")
      (node (ref "C71") (pin "1") (pinfunction "1_1") (pintype "passive"))
      (node (ref "D1") (pin "14") (pinfunction "TC_14") (pintype "bidirectional"))
      (node (ref "DD4") (pin "13") (pinfunction "C_13") (pintype "input"))
      (node (ref "R172") (pin "2") (pinfunction "2_2") (pintype "passive"))
    )
    (net (code "77") (name "Net-(D1D-DA)") (class "Default")
      (node (ref "D1") (pin "7") (pinfunction "DA_7") (pintype "passive"))
      (node (ref "R141") (pin "2") (pinfunction "2_2") (pintype "passive"))
    )
    (net (code "78") (name "Net-(D1D-TC)") (class "Default")
      (node (ref "C72") (pin "1") (pinfunction "1_1") (pintype "passive"))
      (node (ref "D1") (pin "16") (pinfunction "TC_16") (pintype "bidirectional"))
      (node (ref "DD4") (pin "14") (pinfunction "D_14") (pintype "input"))
      (node (ref "R173") (pin "2") (pinfunction "2_2") (pintype "passive"))
    )
    (net (code "79") (name "Net-(D2A-DA)") (class "Default")
      (node (ref "D2") (pin "1") (pinfunction "DA_1") (pintype "passive"))
      (node (ref "R142") (pin "2") (pinfunction "2_2") (pintype "passive"))
    )
    (net (code "80") (name "Net-(D2A-TC)") (class "Default")
      (node (ref "C73") (pin "1") (pinfunction "1_1") (pintype "passive"))
      (node (ref "D2") (pin "10") (pinfunction "TC_10") (pintype "bidirectional"))
      (node (ref "DD4") (pin "3") (pinfunction "E_3") (pintype "input"))
      (node (ref "R174") (pin "2") (pinfunction "2_2") (pintype "passive"))
    )
    (net (code "81") (name "Net-(D2B-DA)") (class "Default")
      (node (ref "D2") (pin "3") (pinfunction "DA_3") (pintype "passive"))
      (node (ref "R143") (pin "2") (pinfunction "2_2") (pintype "passive"))
    )
    (net (code "82") (name "Net-(D2B-TC)") (class "Default")
      (node (ref "C74") (pin "1") (pinfunction "1_1") (pintype "passive"))
      (node (ref "D2") (pin "12") (pinfunction "TC_12") (pintype "bidirectional"))
      (node (ref "DD4") (pin "4") (pinfunction "F_4") (pintype "input"))
      (node (ref "R175") (pin "2") (pinfunction "2_2") (pintype "passive"))
    )
    (net (code "83") (name "Net-(D2C-DA)") (class "Default")
      (node (ref "D2") (pin "5") (pinfunction "DA_5") (pintype "passive"))
      (node (ref "R144") (pin "2") (pinfunction "2_2") (pintype "passive"))
    )
    (net (code "84") (name "Net-(D2C-TC)") (class "Default")
      (node (ref "C75") (pin "1") (pinfunction "1_1") (pintype "passive"))
      (node (ref "D2") (pin "14") (pinfunction "TC_14") (pintype "bidirectional"))
      (node (ref "DD4") (pin "5") (pinfunction "G_5") (pintype "input"))
      (node (ref "R176") (pin "2") (pinfunction "2_2") (pintype "passive"))
    )
    (net (code "85") (name "Net-(D2D-DA)") (class "Default")
      (node (ref "D2") (pin "7") (pinfunction "DA_7") (pintype "passive"))
      (node (ref "R145") (pin "2") (pinfunction "2_2") (pintype "passive"))
    )
    (net (code "86") (name "Net-(D2D-TC)") (class "Default")
      (node (ref "C76") (pin "1") (pinfunction "1_1") (pintype "passive"))
      (node (ref "D2") (pin "16") (pinfunction "TC_16") (pintype "bidirectional"))
      (node (ref "DD4") (pin "6") (pinfunction "H_6") (pintype "input"))
      (node (ref "R177") (pin "2") (pinfunction "2_2") (pintype "passive"))
    )
    (net (code "87") (name "Net-(D3A-DA)") (class "Default")
      (node (ref "D3") (pin "1") (pinfunction "DA_1") (pintype "passive"))
      (node (ref "R146") (pin "2") (pinfunction "2_2") (pintype "passive"))
    )
    (net (code "88") (name "Net-(D3A-TC)") (class "Default")
      (node (ref "C77") (pin "1") (pinfunction "1_1") (pintype "passive"))
      (node (ref "D3") (pin "10") (pinfunction "TC_10") (pintype "bidirectional"))
      (node (ref "DD5") (pin "11") (pinfunction "A_11") (pintype "input"))
      (node (ref "R178") (pin "2") (pinfunction "2_2") (pintype "passive"))
    )
    (net (code "89") (name "Net-(D3B-DA)") (class "Default")
      (node (ref "D3") (pin "3") (pinfunction "DA_3") (pintype "passive"))
      (node (ref "R147") (pin "2") (pinfunction "2_2") (pintype "passive"))
    )
    (net (code "90") (name "Net-(D3B-TC)") (class "Default")
      (node (ref "C78") (pin "1") (pinfunction "1_1") (pintype "passive"))
      (node (ref "D3") (pin "12") (pinfunction "TC_12") (pintype "bidirectional"))
      (node (ref "DD5") (pin "12") (pinfunction "B_12") (pintype "input"))
      (node (ref "R179") (pin "2") (pinfunction "2_2") (pintype "passive"))
    )
    (net (code "91") (name "Net-(D3C-DA)") (class "Default")
      (node (ref "D3") (pin "5") (pinfunction "DA_5") (pintype "passive"))
      (node (ref "R148") (pin "2") (pinfunction "2_2") (pintype "passive"))
    )
    (net (code "92") (name "Net-(D3C-TC)") (class "Default")
      (node (ref "C79") (pin "1") (pinfunction "1_1") (pintype "passive"))
      (node (ref "D3") (pin "14") (pinfunction "TC_14") (pintype "bidirectional"))
      (node (ref "DD5") (pin "13") (pinfunction "C_13") (pintype "input"))
      (node (ref "R180") (pin "2") (pinfunction "2_2") (pintype "passive"))
    )
    (net (code "93") (name "Net-(D3D-DA)") (class "Default")
      (node (ref "D3") (pin "7") (pinfunction "DA_7") (pintype "passive"))
      (node (ref "R149") (pin "2") (pinfunction "2_2") (pintype "passive"))
    )
    (net (code "94") (name "Net-(D3D-TC)") (class "Default")
      (node (ref "C80") (pin "1") (pinfunction "1_1") (pintype "passive"))
      (node (ref "D3") (pin "16") (pinfunction "TC_16") (pintype "bidirectional"))
      (node (ref "DD5") (pin "14") (pinfunction "D_14") (pintype "input"))
      (node (ref "R181") (pin "2") (pinfunction "2_2") (pintype "passive"))
    )
    (net (code "95") (name "Net-(D4A-DA)") (class "Default")
      (node (ref "D4") (pin "1") (pinfunction "DA_1") (pintype "passive"))
      (node (ref "R150") (pin "2") (pinfunction "2_2") (pintype "passive"))
    )
    (net (code "96") (name "Net-(D4A-TC)") (class "Default")
      (node (ref "C81") (pin "1") (pinfunction "1_1") (pintype "passive"))
      (node (ref "D4") (pin "10") (pinfunction "TC_10") (pintype "bidirectional"))
      (node (ref "DD5") (pin "3") (pinfunction "E_3") (pintype "input"))
      (node (ref "R182") (pin "2") (pinfunction "2_2") (pintype "passive"))
    )
    (net (code "97") (name "Net-(D4B-DA)") (class "Default")
      (node (ref "D4") (pin "3") (pinfunction "DA_3") (pintype "passive"))
      (node (ref "R151") (pin "2") (pinfunction "2_2") (pintype "passive"))
    )
    (net (code "98") (name "Net-(D4B-TC)") (class "Default")
      (node (ref "C82") (pin "1") (pinfunction "1_1") (pintype "passive"))
      (node (ref "D4") (pin "12") (pinfunction "TC_12") (pintype "bidirectional"))
      (node (ref "DD5") (pin "4") (pinfunction "F_4") (pintype "input"))
      (node (ref "R183") (pin "2") (pinfunction "2_2") (pintype "passive"))
    )
    (net (code "99") (name "Net-(D4C-DA)") (class "Default")
      (node (ref "D4") (pin "5") (pinfunction "DA_5") (pintype "passive"))
      (node (ref "R152") (pin "2") (pinfunction "2_2") (pintype "passive"))
    )
    (net (code "100") (name "Net-(D4C-TC)") (class "Default")
      (node (ref "C83") (pin "1") (pinfunction "1_1") (pintype "passive"))
      (node (ref "D4") (pin "14") (pinfunction "TC_14") (pintype "bidirectional"))
      (node (ref "DD5") (pin "5") (pinfunction "G_5") (pintype "input"))
      (node (ref "R184") (pin "2") (pinfunction "2_2") (pintype "passive"))
    )
    (net (code "101") (name "Net-(D4D-DA)") (class "Default")
      (node (ref "D4") (pin "7") (pinfunction "DA_7") (pintype "passive"))
      (node (ref "R153") (pin "2") (pinfunction "2_2") (pintype "passive"))
    )
    (net (code "102") (name "Net-(D4D-TC)") (class "Default")
      (node (ref "C84") (pin "1") (pinfunction "1_1") (pintype "passive"))
      (node (ref "D4") (pin "16") (pinfunction "TC_16") (pintype "bidirectional"))
      (node (ref "DD5") (pin "6") (pinfunction "H_6") (pintype "input"))
      (node (ref "R185") (pin "2") (pinfunction "2_2") (pintype "passive"))
    )
    (net (code "103") (name "Net-(D5-IFB)") (class "Default")
      (node (ref "D5") (pin "2") (pinfunction "IFB_2") (pintype "output"))
      (node (ref "VD98") (pin "A") (pinfunction "A_A") (pintype "passive"))
    )
    (net (code "104") (name "Net-(D5-IN)") (class "Default")
      (node (ref "D5") (pin "1") (pinfunction "IN_1") (pintype "input"))
      (node (ref "R186") (pin "2") (pinfunction "2_2") (pintype "passive"))
    )
    (net (code "105") (name "Net-(D6A-DA)") (class "Default")
      (node (ref "D6") (pin "1") (pinfunction "DA_1") (pintype "passive"))
      (node (ref "R189") (pin "2") (pinfunction "2_2") (pintype "passive"))
    )
    (net (code "106") (name "Net-(D6A-TC)") (class "Default")
      (node (ref "C87") (pin "1") (pinfunction "1_1") (pintype "passive"))
      (node (ref "D6") (pin "10") (pinfunction "TC_10") (pintype "bidirectional"))
      (node (ref "DD6") (pin "11") (pinfunction "A_11") (pintype "input"))
      (node (ref "R221") (pin "2") (pinfunction "2_2") (pintype "passive"))
    )
    (net (code "107") (name "Net-(D6B-DA)") (class "Default")
      (node (ref "D6") (pin "3") (pinfunction "DA_3") (pintype "passive"))
      (node (ref "R190") (pin "2") (pinfunction "2_2") (pintype "passive"))
    )
    (net (code "108") (name "Net-(D6B-TC)") (class "Default")
      (node (ref "C88") (pin "1") (pinfunction "1_1") (pintype "passive"))
      (node (ref "D6") (pin "12") (pinfunction "TC_12") (pintype "bidirectional"))
      (node (ref "DD6") (pin "12") (pinfunction "B_12") (pintype "input"))
      (node (ref "R222") (pin "2") (pinfunction "2_2") (pintype "passive"))
    )
    (net (code "109") (name "Net-(D6C-DA)") (class "Default")
      (node (ref "D6") (pin "5") (pinfunction "DA_5") (pintype "passive"))
      (node (ref "R191") (pin "2") (pinfunction "2_2") (pintype "passive"))
    )
    (net (code "110") (name "Net-(D6C-TC)") (class "Default")
      (node (ref "C89") (pin "1") (pinfunction "1_1") (pintype "passive"))
      (node (ref "D6") (pin "14") (pinfunction "TC_14") (pintype "bidirectional"))
      (node (ref "DD6") (pin "13") (pinfunction "C_13") (pintype "input"))
      (node (ref "R223") (pin "2") (pinfunction "2_2") (pintype "passive"))
    )
    (net (code "111") (name "Net-(D6D-DA)") (class "Default")
      (node (ref "D6") (pin "7") (pinfunction "DA_7") (pintype "passive"))
      (node (ref "R192") (pin "2") (pinfunction "2_2") (pintype "passive"))
    )
    (net (code "112") (name "Net-(D6D-TC)") (class "Default")
      (node (ref "C90") (pin "1") (pinfunction "1_1") (pintype "passive"))
      (node (ref "D6") (pin "16") (pinfunction "TC_16") (pintype "bidirectional"))
      (node (ref "DD6") (pin "14") (pinfunction "D_14") (pintype "input"))
      (node (ref "R224") (pin "2") (pinfunction "2_2") (pintype "passive"))
    )
    (net (code "113") (name "Net-(D7A-DA)") (class "Default")
      (node (ref "D7") (pin "1") (pinfunction "DA_1") (pintype "passive"))
      (node (ref "R193") (pin "2") (pinfunction "2_2") (pintype "passive"))
    )
    (net (code "114") (name "Net-(D7A-TC)") (class "Default")
      (node (ref "C91") (pin "1") (pinfunction "1_1") (pintype "passive"))
      (node (ref "D7") (pin "10") (pinfunction "TC_10") (pintype "bidirectional"))
      (node (ref "DD6") (pin "3") (pinfunction "E_3") (pintype "input"))
      (node (ref "R225") (pin "2") (pinfunction "2_2") (pintype "passive"))
    )
    (net (code "115") (name "Net-(D7B-DA)") (class "Default")
      (node (ref "D7") (pin "3") (pinfunction "DA_3") (pintype "passive"))
      (node (ref "R194") (pin "2") (pinfunction "2_2") (pintype "passive"))
    )
    (net (code "116") (name "Net-(D7B-TC)") (class "Default")
      (node (ref "C92") (pin "1") (pinfunction "1_1") (pintype "passive"))
      (node (ref "D7") (pin "12") (pinfunction "TC_12") (pintype "bidirectional"))
      (node (ref "DD6") (pin "4") (pinfunction "F_4") (pintype "input"))
      (node (ref "R226") (pin "2") (pinfunction "2_2") (pintype "passive"))
    )
    (net (code "117") (name "Net-(D7C-DA)") (class "Default")
      (node (ref "D7") (pin "5") (pinfunction "DA_5") (pintype "passive"))
      (node (ref "R195") (pin "2") (pinfunction "2_2") (pintype "passive"))
    )
    (net (code "118") (name "Net-(D7C-TC)") (class "Default")
      (node (ref "C93") (pin "1") (pinfunction "1_1") (pintype "passive"))
      (node (ref "D7") (pin "14") (pinfunction "TC_14") (pintype "bidirectional"))
      (node (ref "DD6") (pin "5") (pinfunction "G_5") (pintype "input"))
      (node (ref "R227") (pin "2") (pinfunction "2_2") (pintype "passive"))
    )
    (net (code "119") (name "Net-(D7D-DA)") (class "Default")
      (node (ref "D7") (pin "7") (pinfunction "DA_7") (pintype "passive"))
      (node (ref "R196") (pin "2") (pinfunction "2_2") (pintype "passive"))
    )
    (net (code "120") (name "Net-(D7D-TC)") (class "Default")
      (node (ref "C94") (pin "1") (pinfunction "1_1") (pintype "passive"))
      (node (ref "D7") (pin "16") (pinfunction "TC_16") (pintype "bidirectional"))
      (node (ref "DD6") (pin "6") (pinfunction "H_6") (pintype "input"))
      (node (ref "R228") (pin "2") (pinfunction "2_2") (pintype "passive"))
    )
    (net (code "121") (name "Net-(D8A-DA)") (class "Default")
      (node (ref "D8") (pin "1") (pinfunction "DA_1") (pintype "passive"))
      (node (ref "R197") (pin "2") (pinfunction "2_2") (pintype "passive"))
    )
    (net (code "122") (name "Net-(D8A-TC)") (class "Default")
      (node (ref "C95") (pin "1") (pinfunction "1_1") (pintype "passive"))
      (node (ref "D8") (pin "10") (pinfunction "TC_10") (pintype "bidirectional"))
      (node (ref "DD7") (pin "11") (pinfunction "A_11") (pintype "input"))
      (node (ref "R229") (pin "2") (pinfunction "2_2") (pintype "passive"))
    )
    (net (code "123") (name "Net-(D8B-DA)") (class "Default")
      (node (ref "D8") (pin "3") (pinfunction "DA_3") (pintype "passive"))
      (node (ref "R198") (pin "2") (pinfunction "2_2") (pintype "passive"))
    )
    (net (code "124") (name "Net-(D8B-TC)") (class "Default")
      (node (ref "C96") (pin "1") (pinfunction "1_1") (pintype "passive"))
      (node (ref "D8") (pin "12") (pinfunction "TC_12") (pintype "bidirectional"))
      (node (ref "DD7") (pin "12") (pinfunction "B_12") (pintype "input"))
      (node (ref "R230") (pin "2") (pinfunction "2_2") (pintype "passive"))
    )
    (net (code "125") (name "Net-(D8C-DA)") (class "Default")
      (node (ref "D8") (pin "5") (pinfunction "DA_5") (pintype "passive"))
      (node (ref "R199") (pin "2") (pinfunction "2_2") (pintype "passive"))
    )
    (net (code "126") (name "Net-(D8C-TC)") (class "Default")
      (node (ref "C97") (pin "1") (pinfunction "1_1") (pintype "passive"))
      (node (ref "D8") (pin "14") (pinfunction "TC_14") (pintype "bidirectional"))
      (node (ref "DD7") (pin "13") (pinfunction "C_13") (pintype "input"))
      (node (ref "R231") (pin "2") (pinfunction "2_2") (pintype "passive"))
    )
    (net (code "127") (name "Net-(D8D-DA)") (class "Default")
      (node (ref "D8") (pin "7") (pinfunction "DA_7") (pintype "passive"))
      (node (ref "R200") (pin "2") (pinfunction "2_2") (pintype "passive"))
    )
    (net (code "128") (name "Net-(D8D-TC)") (class "Default")
      (node (ref "C98") (pin "1") (pinfunction "1_1") (pintype "passive"))
      (node (ref "D8") (pin "16") (pinfunction "TC_16") (pintype "bidirectional"))
      (node (ref "DD7") (pin "14") (pinfunction "D_14") (pintype "input"))
      (node (ref "R232") (pin "2") (pinfunction "2_2") (pintype "passive"))
    )
    (net (code "129") (name "Net-(D9A-DA)") (class "Default")
      (node (ref "D9") (pin "1") (pinfunction "DA_1") (pintype "passive"))
      (node (ref "R201") (pin "2") (pinfunction "2_2") (pintype "passive"))
    )
    (net (code "130") (name "Net-(D9A-TC)") (class "Default")
      (node (ref "C99") (pin "1") (pinfunction "1_1") (pintype "passive"))
      (node (ref "D9") (pin "10") (pinfunction "TC_10") (pintype "bidirectional"))
      (node (ref "DD7") (pin "3") (pinfunction "E_3") (pintype "input"))
      (node (ref "R233") (pin "2") (pinfunction "2_2") (pintype "passive"))
    )
    (net (code "131") (name "Net-(D9B-DA)") (class "Default")
      (node (ref "D9") (pin "3") (pinfunction "DA_3") (pintype "passive"))
      (node (ref "R202") (pin "2") (pinfunction "2_2") (pintype "passive"))
    )
    (net (code "132") (name "Net-(D9B-TC)") (class "Default")
      (node (ref "C100") (pin "1") (pinfunction "1_1") (pintype "passive"))
      (node (ref "D9") (pin "12") (pinfunction "TC_12") (pintype "bidirectional"))
      (node (ref "DD7") (pin "4") (pinfunction "F_4") (pintype "input"))
      (node (ref "R234") (pin "2") (pinfunction "2_2") (pintype "passive"))
    )
    (net (code "133") (name "Net-(D9C-DA)") (class "Default")
      (node (ref "D9") (pin "5") (pinfunction "DA_5") (pintype "passive"))
      (node (ref "R203") (pin "2") (pinfunction "2_2") (pintype "passive"))
    )
    (net (code "134") (name "Net-(D9C-TC)") (class "Default")
      (node (ref "C101") (pin "1") (pinfunction "1_1") (pintype "passive"))
      (node (ref "D9") (pin "14") (pinfunction "TC_14") (pintype "bidirectional"))
      (node (ref "DD7") (pin "5") (pinfunction "G_5") (pintype "input"))
      (node (ref "R235") (pin "2") (pinfunction "2_2") (pintype "passive"))
    )
    (net (code "135") (name "Net-(D9D-DA)") (class "Default")
      (node (ref "D9") (pin "7") (pinfunction "DA_7") (pintype "passive"))
      (node (ref "R204") (pin "2") (pinfunction "2_2") (pintype "passive"))
    )
    (net (code "136") (name "Net-(D9D-TC)") (class "Default")
      (node (ref "C102") (pin "1") (pinfunction "1_1") (pintype "passive"))
      (node (ref "D9") (pin "16") (pinfunction "TC_16") (pintype "bidirectional"))
      (node (ref "DD7") (pin "6") (pinfunction "H_6") (pintype "input"))
      (node (ref "R236") (pin "2") (pinfunction "2_2") (pintype "passive"))
    )
    (net (code "137") (name "Net-(D10A-DA)") (class "Default")
      (node (ref "D10") (pin "1") (pinfunction "DA_1") (pintype "passive"))
      (node (ref "R237") (pin "2") (pinfunction "2_2") (pintype "passive"))
    )
    (net (code "138") (name "Net-(D10A-TC)") (class "Default")
      (node (ref "C105") (pin "1") (pinfunction "1_1") (pintype "passive"))
      (node (ref "D10") (pin "10") (pinfunction "TC_10") (pintype "bidirectional"))
      (node (ref "DD8") (pin "11") (pinfunction "A_11") (pintype "input"))
      (node (ref "R269") (pin "2") (pinfunction "2_2") (pintype "passive"))
    )
    (net (code "139") (name "Net-(D10B-DA)") (class "Default")
      (node (ref "D10") (pin "3") (pinfunction "DA_3") (pintype "passive"))
      (node (ref "R238") (pin "2") (pinfunction "2_2") (pintype "passive"))
    )
    (net (code "140") (name "Net-(D10B-TC)") (class "Default")
      (node (ref "C106") (pin "1") (pinfunction "1_1") (pintype "passive"))
      (node (ref "D10") (pin "12") (pinfunction "TC_12") (pintype "bidirectional"))
      (node (ref "DD8") (pin "12") (pinfunction "B_12") (pintype "input"))
      (node (ref "R270") (pin "2") (pinfunction "2_2") (pintype "passive"))
    )
    (net (code "141") (name "Net-(D10C-DA)") (class "Default")
      (node (ref "D10") (pin "5") (pinfunction "DA_5") (pintype "passive"))
      (node (ref "R239") (pin "2") (pinfunction "2_2") (pintype "passive"))
    )
    (net (code "142") (name "Net-(D10C-TC)") (class "Default")
      (node (ref "C107") (pin "1") (pinfunction "1_1") (pintype "passive"))
      (node (ref "D10") (pin "14") (pinfunction "TC_14") (pintype "bidirectional"))
      (node (ref "DD8") (pin "13") (pinfunction "C_13") (pintype "input"))
      (node (ref "R271") (pin "2") (pinfunction "2_2") (pintype "passive"))
    )
    (net (code "143") (name "Net-(D10D-DA)") (class "Default")
      (node (ref "D10") (pin "7") (pinfunction "DA_7") (pintype "passive"))
      (node (ref "R240") (pin "2") (pinfunction "2_2") (pintype "passive"))
    )
    (net (code "144") (name "Net-(D10D-TC)") (class "Default")
      (node (ref "C108") (pin "1") (pinfunction "1_1") (pintype "passive"))
      (node (ref "D10") (pin "16") (pinfunction "TC_16") (pintype "bidirectional"))
      (node (ref "DD8") (pin "14") (pinfunction "D_14") (pintype "input"))
      (node (ref "R272") (pin "2") (pinfunction "2_2") (pintype "passive"))
    )
    (net (code "145") (name "Net-(D11A-DA)") (class "Default")
      (node (ref "D11") (pin "1") (pinfunction "DA_1") (pintype "passive"))
      (node (ref "R241") (pin "2") (pinfunction "2_2") (pintype "passive"))
    )
    (net (code "146") (name "Net-(D11A-TC)") (class "Default")
      (node (ref "C109") (pin "1") (pinfunction "1_1") (pintype "passive"))
      (node (ref "D11") (pin "10") (pinfunction "TC_10") (pintype "bidirectional"))
      (node (ref "DD8") (pin "3") (pinfunction "E_3") (pintype "input"))
      (node (ref "R273") (pin "2") (pinfunction "2_2") (pintype "passive"))
    )
    (net (code "147") (name "Net-(D11B-DA)") (class "Default")
      (node (ref "D11") (pin "3") (pinfunction "DA_3") (pintype "passive"))
      (node (ref "R242") (pin "2") (pinfunction "2_2") (pintype "passive"))
    )
    (net (code "148") (name "Net-(D11B-TC)") (class "Default")
      (node (ref "C110") (pin "1") (pinfunction "1_1") (pintype "passive"))
      (node (ref "D11") (pin "12") (pinfunction "TC_12") (pintype "bidirectional"))
      (node (ref "DD8") (pin "4") (pinfunction "F_4") (pintype "input"))
      (node (ref "R274") (pin "2") (pinfunction "2_2") (pintype "passive"))
    )
    (net (code "149") (name "Net-(D11C-DA)") (class "Default")
      (node (ref "D11") (pin "5") (pinfunction "DA_5") (pintype "passive"))
      (node (ref "R243") (pin "2") (pinfunction "2_2") (pintype "passive"))
    )
    (net (code "150") (name "Net-(D11C-TC)") (class "Default")
      (node (ref "C111") (pin "1") (pinfunction "1_1") (pintype "passive"))
      (node (ref "D11") (pin "14") (pinfunction "TC_14") (pintype "bidirectional"))
      (node (ref "DD8") (pin "5") (pinfunction "G_5") (pintype "input"))
      (node (ref "R275") (pin "2") (pinfunction "2_2") (pintype "passive"))
    )
    (net (code "151") (name "Net-(D11D-DA)") (class "Default")
      (node (ref "D11") (pin "7") (pinfunction "DA_7") (pintype "passive"))
      (node (ref "R244") (pin "2") (pinfunction "2_2") (pintype "passive"))
    )
    (net (code "152") (name "Net-(D11D-TC)") (class "Default")
      (node (ref "C112") (pin "1") (pinfunction "1_1") (pintype "passive"))
      (node (ref "D11") (pin "16") (pinfunction "TC_16") (pintype "bidirectional"))
      (node (ref "DD8") (pin "6") (pinfunction "H_6") (pintype "input"))
      (node (ref "R276") (pin "2") (pinfunction "2_2") (pintype "passive"))
    )
    (net (code "153") (name "Net-(D12A-DA)") (class "Default")
      (node (ref "D12") (pin "1") (pinfunction "DA_1") (pintype "passive"))
      (node (ref "R245") (pin "2") (pinfunction "2_2") (pintype "passive"))
    )
    (net (code "154") (name "Net-(D12A-TC)") (class "Default")
      (node (ref "C113") (pin "1") (pinfunction "1_1") (pintype "passive"))
      (node (ref "D12") (pin "10") (pinfunction "TC_10") (pintype "bidirectional"))
      (node (ref "DD9") (pin "11") (pinfunction "A_11") (pintype "input"))
      (node (ref "R277") (pin "2") (pinfunction "2_2") (pintype "passive"))
    )
    (net (code "155") (name "Net-(D12B-DA)") (class "Default")
      (node (ref "D12") (pin "3") (pinfunction "DA_3") (pintype "passive"))
      (node (ref "R246") (pin "2") (pinfunction "2_2") (pintype "passive"))
    )
    (net (code "156") (name "Net-(D12B-TC)") (class "Default")
      (node (ref "C114") (pin "1") (pinfunction "1_1") (pintype "passive"))
      (node (ref "D12") (pin "12") (pinfunction "TC_12") (pintype "bidirectional"))
      (node (ref "DD9") (pin "12") (pinfunction "B_12") (pintype "input"))
      (node (ref "R278") (pin "2") (pinfunction "2_2") (pintype "passive"))
    )
    (net (code "157") (name "Net-(D12C-DA)") (class "Default")
      (node (ref "D12") (pin "5") (pinfunction "DA_5") (pintype "passive"))
      (node (ref "R247") (pin "2") (pinfunction "2_2") (pintype "passive"))
    )
    (net (code "158") (name "Net-(D12C-TC)") (class "Default")
      (node (ref "C115") (pin "1") (pinfunction "1_1") (pintype "passive"))
      (node (ref "D12") (pin "14") (pinfunction "TC_14") (pintype "bidirectional"))
      (node (ref "DD9") (pin "13") (pinfunction "C_13") (pintype "input"))
      (node (ref "R279") (pin "2") (pinfunction "2_2") (pintype "passive"))
    )
    (net (code "159") (name "Net-(D12D-DA)") (class "Default")
      (node (ref "D12") (pin "7") (pinfunction "DA_7") (pintype "passive"))
      (node (ref "R248") (pin "2") (pinfunction "2_2") (pintype "passive"))
    )
    (net (code "160") (name "Net-(D12D-TC)") (class "Default")
      (node (ref "C116") (pin "1") (pinfunction "1_1") (pintype "passive"))
      (node (ref "D12") (pin "16") (pinfunction "TC_16") (pintype "bidirectional"))
      (node (ref "DD9") (pin "14") (pinfunction "D_14") (pintype "input"))
      (node (ref "R280") (pin "2") (pinfunction "2_2") (pintype "passive"))
    )
    (net (code "161") (name "Net-(D13A-DA)") (class "Default")
      (node (ref "D13") (pin "1") (pinfunction "DA_1") (pintype "passive"))
      (node (ref "R249") (pin "2") (pinfunction "2_2") (pintype "passive"))
    )
    (net (code "162") (name "Net-(D13A-TC)") (class "Default")
      (node (ref "C117") (pin "1") (pinfunction "1_1") (pintype "passive"))
      (node (ref "D13") (pin "10") (pinfunction "TC_10") (pintype "bidirectional"))
      (node (ref "DD9") (pin "3") (pinfunction "E_3") (pintype "input"))
      (node (ref "R281") (pin "2") (pinfunction "2_2") (pintype "passive"))
    )
    (net (code "163") (name "Net-(D13B-DA)") (class "Default")
      (node (ref "D13") (pin "3") (pinfunction "DA_3") (pintype "passive"))
      (node (ref "R250") (pin "2") (pinfunction "2_2") (pintype "passive"))
    )
    (net (code "164") (name "Net-(D13B-TC)") (class "Default")
      (node (ref "C118") (pin "1") (pinfunction "1_1") (pintype "passive"))
      (node (ref "D13") (pin "12") (pinfunction "TC_12") (pintype "bidirectional"))
      (node (ref "DD9") (pin "4") (pinfunction "F_4") (pintype "input"))
      (node (ref "R282") (pin "2") (pinfunction "2_2") (pintype "passive"))
    )
    (net (code "165") (name "Net-(D13C-DA)") (class "Default")
      (node (ref "D13") (pin "5") (pinfunction "DA_5") (pintype "passive"))
      (node (ref "R251") (pin "2") (pinfunction "2_2") (pintype "passive"))
    )
    (net (code "166") (name "Net-(D13C-TC)") (class "Default")
      (node (ref "C119") (pin "1") (pinfunction "1_1") (pintype "passive"))
      (node (ref "D13") (pin "14") (pinfunction "TC_14") (pintype "bidirectional"))
      (node (ref "DD9") (pin "5") (pinfunction "G_5") (pintype "input"))
      (node (ref "R283") (pin "2") (pinfunction "2_2") (pintype "passive"))
    )
    (net (code "167") (name "Net-(D13D-DA)") (class "Default")
      (node (ref "D13") (pin "7") (pinfunction "DA_7") (pintype "passive"))
      (node (ref "R252") (pin "2") (pinfunction "2_2") (pintype "passive"))
    )
    (net (code "168") (name "Net-(D13D-TC)") (class "Default")
      (node (ref "C120") (pin "1") (pinfunction "1_1") (pintype "passive"))
      (node (ref "D13") (pin "16") (pinfunction "TC_16") (pintype "bidirectional"))
      (node (ref "DD9") (pin "6") (pinfunction "H_6") (pintype "input"))
      (node (ref "R284") (pin "2") (pinfunction "2_2") (pintype "passive"))
    )
    (net (code "169") (name "Net-(D14A-DA)") (class "Default")
      (node (ref "D14") (pin "1") (pinfunction "DA_1") (pintype "passive"))
      (node (ref "R285") (pin "2") (pinfunction "2_2") (pintype "passive"))
    )
    (net (code "170") (name "Net-(D14A-TC)") (class "Default")
      (node (ref "C123") (pin "1") (pinfunction "1_1") (pintype "passive"))
      (node (ref "D14") (pin "10") (pinfunction "TC_10") (pintype "bidirectional"))
      (node (ref "DD10") (pin "11") (pinfunction "A_11") (pintype "input"))
      (node (ref "R317") (pin "2") (pinfunction "2_2") (pintype "passive"))
    )
    (net (code "171") (name "Net-(D14B-DA)") (class "Default")
      (node (ref "D14") (pin "3") (pinfunction "DA_3") (pintype "passive"))
      (node (ref "R286") (pin "2") (pinfunction "2_2") (pintype "passive"))
    )
    (net (code "172") (name "Net-(D14B-TC)") (class "Default")
      (node (ref "C124") (pin "1") (pinfunction "1_1") (pintype "passive"))
      (node (ref "D14") (pin "12") (pinfunction "TC_12") (pintype "bidirectional"))
      (node (ref "DD10") (pin "12") (pinfunction "B_12") (pintype "input"))
      (node (ref "R318") (pin "2") (pinfunction "2_2") (pintype "passive"))
    )
    (net (code "173") (name "Net-(D14C-DA)") (class "Default")
      (node (ref "D14") (pin "5") (pinfunction "DA_5") (pintype "passive"))
      (node (ref "R287") (pin "2") (pinfunction "2_2") (pintype "passive"))
    )
    (net (code "174") (name "Net-(D14C-TC)") (class "Default")
      (node (ref "C125") (pin "1") (pinfunction "1_1") (pintype "passive"))
      (node (ref "D14") (pin "14") (pinfunction "TC_14") (pintype "bidirectional"))
      (node (ref "DD10") (pin "13") (pinfunction "C_13") (pintype "input"))
      (node (ref "R319") (pin "2") (pinfunction "2_2") (pintype "passive"))
    )
    (net (code "175") (name "Net-(D14D-DA)") (class "Default")
      (node (ref "D14") (pin "7") (pinfunction "DA_7") (pintype "passive"))
      (node (ref "R288") (pin "2") (pinfunction "2_2") (pintype "passive"))
    )
    (net (code "176") (name "Net-(D14D-TC)") (class "Default")
      (node (ref "C126") (pin "1") (pinfunction "1_1") (pintype "passive"))
      (node (ref "D14") (pin "16") (pinfunction "TC_16") (pintype "bidirectional"))
      (node (ref "DD10") (pin "14") (pinfunction "D_14") (pintype "input"))
      (node (ref "R320") (pin "2") (pinfunction "2_2") (pintype "passive"))
    )
    (net (code "177") (name "Net-(D15A-DA)") (class "Default")
      (node (ref "D15") (pin "1") (pinfunction "DA_1") (pintype "passive"))
      (node (ref "R289") (pin "2") (pinfunction "2_2") (pintype "passive"))
    )
    (net (code "178") (name "Net-(D15A-TC)") (class "Default")
      (node (ref "C127") (pin "1") (pinfunction "1_1") (pintype "passive"))
      (node (ref "D15") (pin "10") (pinfunction "TC_10") (pintype "bidirectional"))
      (node (ref "DD10") (pin "3") (pinfunction "E_3") (pintype "input"))
      (node (ref "R321") (pin "2") (pinfunction "2_2") (pintype "passive"))
    )
    (net (code "179") (name "Net-(D15B-DA)") (class "Default")
      (node (ref "D15") (pin "3") (pinfunction "DA_3") (pintype "passive"))
      (node (ref "R290") (pin "2") (pinfunction "2_2") (pintype "passive"))
    )
    (net (code "180") (name "Net-(D15B-TC)") (class "Default")
      (node (ref "C128") (pin "1") (pinfunction "1_1") (pintype "passive"))
      (node (ref "D15") (pin "12") (pinfunction "TC_12") (pintype "bidirectional"))
      (node (ref "DD10") (pin "4") (pinfunction "F_4") (pintype "input"))
      (node (ref "R322") (pin "2") (pinfunction "2_2") (pintype "passive"))
    )
    (net (code "181") (name "Net-(D15C-DA)") (class "Default")
      (node (ref "D15") (pin "5") (pinfunction "DA_5") (pintype "passive"))
      (node (ref "R291") (pin "2") (pinfunction "2_2") (pintype "passive"))
    )
    (net (code "182") (name "Net-(D15C-TC)") (class "Default")
      (node (ref "C129") (pin "1") (pinfunction "1_1") (pintype "passive"))
      (node (ref "D15") (pin "14") (pinfunction "TC_14") (pintype "bidirectional"))
      (node (ref "DD10") (pin "5") (pinfunction "G_5") (pintype "input"))
      (node (ref "R323") (pin "2") (pinfunction "2_2") (pintype "passive"))
    )
    (net (code "183") (name "Net-(D15D-DA)") (class "Default")
      (node (ref "D15") (pin "7") (pinfunction "DA_7") (pintype "passive"))
      (node (ref "R292") (pin "2") (pinfunction "2_2") (pintype "passive"))
    )
    (net (code "184") (name "Net-(D15D-TC)") (class "Default")
      (node (ref "C130") (pin "1") (pinfunction "1_1") (pintype "passive"))
      (node (ref "D15") (pin "16") (pinfunction "TC_16") (pintype "bidirectional"))
      (node (ref "DD10") (pin "6") (pinfunction "H_6") (pintype "input"))
      (node (ref "R324") (pin "2") (pinfunction "2_2") (pintype "passive"))
    )
    (net (code "185") (name "Net-(D16A-DA)") (class "Default")
      (node (ref "D16") (pin "1") (pinfunction "DA_1") (pintype "passive"))
      (node (ref "R293") (pin "2") (pinfunction "2_2") (pintype "passive"))
    )
    (net (code "186") (name "Net-(D16A-TC)") (class "Default")
      (node (ref "C131") (pin "1") (pinfunction "1_1") (pintype "passive"))
      (node (ref "D16") (pin "10") (pinfunction "TC_10") (pintype "bidirectional"))
      (node (ref "DD11") (pin "11") (pinfunction "A_11") (pintype "input"))
      (node (ref "R325") (pin "2") (pinfunction "2_2") (pintype "passive"))
    )
    (net (code "187") (name "Net-(D16B-DA)") (class "Default")
      (node (ref "D16") (pin "3") (pinfunction "DA_3") (pintype "passive"))
      (node (ref "R294") (pin "2") (pinfunction "2_2") (pintype "passive"))
    )
    (net (code "188") (name "Net-(D16B-TC)") (class "Default")
      (node (ref "C132") (pin "1") (pinfunction "1_1") (pintype "passive"))
      (node (ref "D16") (pin "12") (pinfunction "TC_12") (pintype "bidirectional"))
      (node (ref "DD11") (pin "12") (pinfunction "B_12") (pintype "input"))
      (node (ref "R326") (pin "2") (pinfunction "2_2") (pintype "passive"))
    )
    (net (code "189") (name "Net-(D16C-DA)") (class "Default")
      (node (ref "D16") (pin "5") (pinfunction "DA_5") (pintype "passive"))
      (node (ref "R295") (pin "2") (pinfunction "2_2") (pintype "passive"))
    )
    (net (code "190") (name "Net-(D16C-TC)") (class "Default")
      (node (ref "C133") (pin "1") (pinfunction "1_1") (pintype "passive"))
      (node (ref "D16") (pin "14") (pinfunction "TC_14") (pintype "bidirectional"))
      (node (ref "DD11") (pin "13") (pinfunction "C_13") (pintype "input"))
      (node (ref "R327") (pin "2") (pinfunction "2_2") (pintype "passive"))
    )
    (net (code "191") (name "Net-(D16D-DA)") (class "Default")
      (node (ref "D16") (pin "7") (pinfunction "DA_7") (pintype "passive"))
      (node (ref "R296") (pin "2") (pinfunction "2_2") (pintype "passive"))
    )
    (net (code "192") (name "Net-(D16D-TC)") (class "Default")
      (node (ref "C134") (pin "1") (pinfunction "1_1") (pintype "passive"))
      (node (ref "D16") (pin "16") (pinfunction "TC_16") (pintype "bidirectional"))
      (node (ref "DD11") (pin "14") (pinfunction "D_14") (pintype "input"))
      (node (ref "R328") (pin "2") (pinfunction "2_2") (pintype "passive"))
    )
    (net (code "193") (name "Net-(D17A-DA)") (class "Default")
      (node (ref "D17") (pin "1") (pinfunction "DA_1") (pintype "passive"))
      (node (ref "R297") (pin "2") (pinfunction "2_2") (pintype "passive"))
    )
    (net (code "194") (name "Net-(D17A-TC)") (class "Default")
      (node (ref "C135") (pin "1") (pinfunction "1_1") (pintype "passive"))
      (node (ref "D17") (pin "10") (pinfunction "TC_10") (pintype "bidirectional"))
      (node (ref "DD11") (pin "3") (pinfunction "E_3") (pintype "input"))
      (node (ref "R329") (pin "2") (pinfunction "2_2") (pintype "passive"))
    )
    (net (code "195") (name "Net-(D17B-DA)") (class "Default")
      (node (ref "D17") (pin "3") (pinfunction "DA_3") (pintype "passive"))
      (node (ref "R298") (pin "2") (pinfunction "2_2") (pintype "passive"))
    )
    (net (code "196") (name "Net-(D17B-TC)") (class "Default")
      (node (ref "C136") (pin "1") (pinfunction "1_1") (pintype "passive"))
      (node (ref "D17") (pin "12") (pinfunction "TC_12") (pintype "bidirectional"))
      (node (ref "DD11") (pin "4") (pinfunction "F_4") (pintype "input"))
      (node (ref "R330") (pin "2") (pinfunction "2_2") (pintype "passive"))
    )
    (net (code "197") (name "Net-(D17C-DA)") (class "Default")
      (node (ref "D17") (pin "5") (pinfunction "DA_5") (pintype "passive"))
      (node (ref "R299") (pin "2") (pinfunction "2_2") (pintype "passive"))
    )
    (net (code "198") (name "Net-(D17C-TC)") (class "Default")
      (node (ref "C137") (pin "1") (pinfunction "1_1") (pintype "passive"))
      (node (ref "D17") (pin "14") (pinfunction "TC_14") (pintype "bidirectional"))
      (node (ref "DD11") (pin "5") (pinfunction "G_5") (pintype "input"))
      (node (ref "R331") (pin "2") (pinfunction "2_2") (pintype "passive"))
    )
    (net (code "199") (name "Net-(D17D-DA)") (class "Default")
      (node (ref "D17") (pin "7") (pinfunction "DA_7") (pintype "passive"))
      (node (ref "R300") (pin "2") (pinfunction "2_2") (pintype "passive"))
    )
    (net (code "200") (name "Net-(D17D-TC)") (class "Default")
      (node (ref "C138") (pin "1") (pinfunction "1_1") (pintype "passive"))
      (node (ref "D17") (pin "16") (pinfunction "TC_16") (pintype "bidirectional"))
      (node (ref "DD11") (pin "6") (pinfunction "H_6") (pintype "input"))
      (node (ref "R332") (pin "2") (pinfunction "2_2") (pintype "passive"))
    )
    (net (code "201") (name "Net-(D18A-DA)") (class "Default")
      (node (ref "D18") (pin "1") (pinfunction "DA_1") (pintype "passive"))
      (node (ref "R334") (pin "1") (pinfunction "1_1") (pintype "passive"))
    )
    (net (code "202") (name "Net-(D18A-TC)") (class "Default")
      (node (ref "D18") (pin "10") (pinfunction "TC_10") (pintype "bidirectional"))
      (node (ref "R350") (pin "1") (pinfunction "1_1") (pintype "passive"))
      (node (ref "VD196") (pin "C") (pinfunction "C_C") (pintype "passive"))
    )
    (net (code "203") (name "Net-(D18B-DA)") (class "Default")
      (node (ref "D18") (pin "3") (pinfunction "DA_3") (pintype "passive"))
      (node (ref "R335") (pin "1") (pinfunction "1_1") (pintype "passive"))
    )
    (net (code "204") (name "Net-(D18B-TC)") (class "Default")
      (node (ref "D18") (pin "12") (pinfunction "TC_12") (pintype "bidirectional"))
      (node (ref "R351") (pin "1") (pinfunction "1_1") (pintype "passive"))
      (node (ref "VD197") (pin "C") (pinfunction "C_C") (pintype "passive"))
    )
    (net (code "205") (name "Net-(D18C-DA)") (class "Default")
      (node (ref "D18") (pin "5") (pinfunction "DA_5") (pintype "passive"))
      (node (ref "R336") (pin "1") (pinfunction "1_1") (pintype "passive"))
    )
    (net (code "206") (name "Net-(D18C-TC)") (class "Default")
      (node (ref "D18") (pin "14") (pinfunction "TC_14") (pintype "bidirectional"))
      (node (ref "R352") (pin "1") (pinfunction "1_1") (pintype "passive"))
      (node (ref "VD198") (pin "C") (pinfunction "C_C") (pintype "passive"))
    )
    (net (code "207") (name "Net-(D18D-DA)") (class "Default")
      (node (ref "D18") (pin "7") (pinfunction "DA_7") (pintype "passive"))
      (node (ref "R337") (pin "1") (pinfunction "1_1") (pintype "passive"))
    )
    (net (code "208") (name "Net-(D18D-TC)") (class "Default")
      (node (ref "D18") (pin "16") (pinfunction "TC_16") (pintype "bidirectional"))
      (node (ref "R353") (pin "1") (pinfunction "1_1") (pintype "passive"))
      (node (ref "VD199") (pin "C") (pinfunction "C_C") (pintype "passive"))
    )
    (net (code "209") (name "Net-(D19A-DA)") (class "Default")
      (node (ref "D19") (pin "1") (pinfunction "DA_1") (pintype "passive"))
      (node (ref "R338") (pin "1") (pinfunction "1_1") (pintype "passive"))
    )
    (net (code "210") (name "Net-(D19A-TC)") (class "Default")
      (node (ref "D19") (pin "10") (pinfunction "TC_10") (pintype "bidirectional"))
      (node (ref "R354") (pin "1") (pinfunction "1_1") (pintype "passive"))
      (node (ref "VD200") (pin "C") (pinfunction "C_C") (pintype "passive"))
    )
    (net (code "211") (name "Net-(D19B-DA)") (class "Default")
      (node (ref "D19") (pin "3") (pinfunction "DA_3") (pintype "passive"))
      (node (ref "R339") (pin "1") (pinfunction "1_1") (pintype "passive"))
    )
    (net (code "212") (name "Net-(D19B-TC)") (class "Default")
      (node (ref "D19") (pin "12") (pinfunction "TC_12") (pintype "bidirectional"))
      (node (ref "R355") (pin "1") (pinfunction "1_1") (pintype "passive"))
      (node (ref "VD201") (pin "C") (pinfunction "C_C") (pintype "passive"))
    )
    (net (code "213") (name "Net-(D19C-DA)") (class "Default")
      (node (ref "D19") (pin "5") (pinfunction "DA_5") (pintype "passive"))
      (node (ref "R340") (pin "1") (pinfunction "1_1") (pintype "passive"))
    )
    (net (code "214") (name "Net-(D19C-TC)") (class "Default")
      (node (ref "D19") (pin "14") (pinfunction "TC_14") (pintype "bidirectional"))
      (node (ref "R356") (pin "1") (pinfunction "1_1") (pintype "passive"))
      (node (ref "VD202") (pin "C") (pinfunction "C_C") (pintype "passive"))
    )
    (net (code "215") (name "Net-(D19D-DA)") (class "Default")
      (node (ref "D19") (pin "7") (pinfunction "DA_7") (pintype "passive"))
      (node (ref "R341") (pin "1") (pinfunction "1_1") (pintype "passive"))
    )
    (net (code "216") (name "Net-(D19D-TC)") (class "Default")
      (node (ref "D19") (pin "16") (pinfunction "TC_16") (pintype "bidirectional"))
      (node (ref "R357") (pin "1") (pinfunction "1_1") (pintype "passive"))
      (node (ref "VD203") (pin "C") (pinfunction "C_C") (pintype "passive"))
    )
    (net (code "217") (name "Net-(D20-IFB)") (class "Default")
      (node (ref "D20") (pin "2") (pinfunction "IFB_2") (pintype "output"))
      (node (ref "VD204") (pin "A") (pinfunction "A_A") (pintype "passive"))
    )
    (net (code "218") (name "Net-(D20-IN)") (class "Default")
      (node (ref "D20") (pin "1") (pinfunction "IN_1") (pintype "input"))
      (node (ref "R350") (pin "2") (pinfunction "2_2") (pintype "passive"))
    )
    (net (code "219") (name "Net-(D21-IFB)") (class "Default")
      (node (ref "D21") (pin "2") (pinfunction "IFB_2") (pintype "output"))
      (node (ref "VD205") (pin "A") (pinfunction "A_A") (pintype "passive"))
    )
    (net (code "220") (name "Net-(D21-IN)") (class "Default")
      (node (ref "D21") (pin "1") (pinfunction "IN_1") (pintype "input"))
      (node (ref "R351") (pin "2") (pinfunction "2_2") (pintype "passive"))
    )
    (net (code "221") (name "Net-(D22-IFB)") (class "Default")
      (node (ref "D22") (pin "2") (pinfunction "IFB_2") (pintype "output"))
      (node (ref "VD206") (pin "A") (pinfunction "A_A") (pintype "passive"))
    )
    (net (code "222") (name "Net-(D22-IN)") (class "Default")
      (node (ref "D22") (pin "1") (pinfunction "IN_1") (pintype "input"))
      (node (ref "R352") (pin "2") (pinfunction "2_2") (pintype "passive"))
    )
    (net (code "223") (name "Net-(D23-IFB)") (class "Default")
      (node (ref "D23") (pin "2") (pinfunction "IFB_2") (pintype "output"))
      (node (ref "VD207") (pin "A") (pinfunction "A_A") (pintype "passive"))
    )
    (net (code "224") (name "Net-(D23-IN)") (class "Default")
      (node (ref "D23") (pin "1") (pinfunction "IN_1") (pintype "input"))
      (node (ref "R353") (pin "2") (pinfunction "2_2") (pintype "passive"))
    )
    (net (code "225") (name "Net-(D24-IFB)") (class "Default")
      (node (ref "D24") (pin "2") (pinfunction "IFB_2") (pintype "output"))
      (node (ref "VD208") (pin "A") (pinfunction "A_A") (pintype "passive"))
    )
    (net (code "226") (name "Net-(D24-IN)") (class "Default")
      (node (ref "D24") (pin "1") (pinfunction "IN_1") (pintype "input"))
      (node (ref "R354") (pin "2") (pinfunction "2_2") (pintype "passive"))
    )
    (net (code "227") (name "Net-(D25-IFB)") (class "Default")
      (node (ref "D25") (pin "2") (pinfunction "IFB_2") (pintype "output"))
      (node (ref "VD209") (pin "A") (pinfunction "A_A") (pintype "passive"))
    )
    (net (code "228") (name "Net-(D25-IN)") (class "Default")
      (node (ref "D25") (pin "1") (pinfunction "IN_1") (pintype "input"))
      (node (ref "R355") (pin "2") (pinfunction "2_2") (pintype "passive"))
    )
    (net (code "229") (name "Net-(D26-IFB)") (class "Default")
      (node (ref "D26") (pin "2") (pinfunction "IFB_2") (pintype "output"))
      (node (ref "VD210") (pin "A") (pinfunction "A_A") (pintype "passive"))
    )
    (net (code "230") (name "Net-(D26-IN)") (class "Default")
      (node (ref "D26") (pin "1") (pinfunction "IN_1") (pintype "input"))
      (node (ref "R356") (pin "2") (pinfunction "2_2") (pintype "passive"))
    )
    (net (code "231") (name "Net-(D27-IFB)") (class "Default")
      (node (ref "D27") (pin "2") (pinfunction "IFB_2") (pintype "output"))
      (node (ref "VD211") (pin "A") (pinfunction "A_A") (pintype "passive"))
    )
    (net (code "232") (name "Net-(D27-IN)") (class "Default")
      (node (ref "D27") (pin "1") (pinfunction "IN_1") (pintype "input"))
      (node (ref "R357") (pin "2") (pinfunction "2_2") (pintype "passive"))
    )
    (net (code "233") (name "Net-(DA1A-A)") (class "Default")
      (node (ref "DA1") (pin "3") (pinfunction "A_3") (pintype "input"))
      (node (ref "R80") (pin "2") (pinfunction "2_2") (pintype "passive"))
      (node (ref "VD43") (pin "A") (pinfunction "A_A") (pintype "passive"))
    )
    (net (code "234") (name "Net-(DA1A-B)") (class "Default")
      (node (ref "DA1") (pin "1") (pinfunction "B_1") (pintype "output"))
      (node (ref "R101") (pin "1") (pinfunction "1_1") (pintype "passive"))
      (node (ref "R86") (pin "1") (pinfunction "1_1") (pintype "passive"))
      (node (ref "R87") (pin "2") (pinfunction "2_2") (pintype "passive"))
    )
    (net (code "235") (name "Net-(DA1A-~{A})") (class "Default")
      (node (ref "DA1") (pin "2") (pinfunction "~{A}_2") (pintype "input"))
      (node (ref "R83") (pin "2") (pinfunction "2_2") (pintype "passive"))
    )
    (net (code "236") (name "Net-(DA1B-A)") (class "Default")
      (node (ref "DA1") (pin "5") (pinfunction "A_5") (pintype "input"))
      (node (ref "R77") (pin "2") (pinfunction "2_2") (pintype "passive"))
      (node (ref "VD36") (pin "A") (pinfunction "A_A") (pintype "passive"))
    )
    (net (code "237") (name "Net-(DA1B-B)") (class "Default")
      (node (ref "DA1") (pin "7") (pinfunction "B_7") (pintype "output"))
      (node (ref "R88") (pin "1") (pinfunction "1_1") (pintype "passive"))
      (node (ref "R89") (pin "2") (pinfunction "2_2") (pintype "passive"))
    )
    (net (code "238") (name "Net-(DA1B-~{A})") (class "Default")
      (node (ref "DA1") (pin "6") (pinfunction "~{A}_6") (pintype "input"))
      (node (ref "R83") (pin "1") (pinfunction "1_1") (pintype "passive"))
      (node (ref "R89") (pin "1") (pinfunction "1_1") (pintype "passive"))
      (node (ref "R90") (pin "2") (pinfunction "2_2") (pintype "passive"))
    )
    (net (code "239") (name "Net-(DA2A-A)") (class "Default")
      (node (ref "DA2") (pin "3") (pinfunction "A_3") (pintype "input"))
      (node (ref "R81") (pin "2") (pinfunction "2_2") (pintype "passive"))
      (node (ref "VD45") (pin "A") (pinfunction "A_A") (pintype "passive"))
    )
    (net (code "240") (name "Net-(DA2A-B)") (class "Default")
      (node (ref "DA2") (pin "1") (pinfunction "B_1") (pintype "output"))
      (node (ref "R102") (pin "1") (pinfunction "1_1") (pintype "passive"))
      (node (ref "R91") (pin "1") (pinfunction "1_1") (pintype "passive"))
      (node (ref "R92") (pin "2") (pinfunction "2_2") (pintype "passive"))
    )
    (net (code "241") (name "Net-(DA2A-~{A})") (class "Default")
      (node (ref "DA2") (pin "2") (pinfunction "~{A}_2") (pintype "input"))
      (node (ref "R84") (pin "2") (pinfunction "2_2") (pintype "passive"))
    )
    (net (code "242") (name "Net-(DA2B-A)") (class "Default")
      (node (ref "DA2") (pin "5") (pinfunction "A_5") (pintype "input"))
      (node (ref "R78") (pin "2") (pinfunction "2_2") (pintype "passive"))
      (node (ref "VD38") (pin "A") (pinfunction "A_A") (pintype "passive"))
    )
    (net (code "243") (name "Net-(DA2B-B)") (class "Default")
      (node (ref "DA2") (pin "7") (pinfunction "B_7") (pintype "output"))
      (node (ref "R93") (pin "1") (pinfunction "1_1") (pintype "passive"))
      (node (ref "R94") (pin "2") (pinfunction "2_2") (pintype "passive"))
    )
    (net (code "244") (name "Net-(DA2B-~{A})") (class "Default")
      (node (ref "DA2") (pin "6") (pinfunction "~{A}_6") (pintype "input"))
      (node (ref "R84") (pin "1") (pinfunction "1_1") (pintype "passive"))
      (node (ref "R94") (pin "1") (pinfunction "1_1") (pintype "passive"))
      (node (ref "R95") (pin "2") (pinfunction "2_2") (pintype "passive"))
    )
    (net (code "245") (name "Net-(DA3A-A)") (class "Default")
      (node (ref "DA3") (pin "3") (pinfunction "A_3") (pintype "input"))
      (node (ref "R82") (pin "2") (pinfunction "2_2") (pintype "passive"))
      (node (ref "VD47") (pin "A") (pinfunction "A_A") (pintype "passive"))
    )
    (net (code "246") (name "Net-(DA3A-B)") (class "Default")
      (node (ref "DA3") (pin "1") (pinfunction "B_1") (pintype "output"))
      (node (ref "R103") (pin "1") (pinfunction "1_1") (pintype "passive"))
      (node (ref "R96") (pin "1") (pinfunction "1_1") (pintype "passive"))
      (node (ref "R97") (pin "2") (pinfunction "2_2") (pintype "passive"))
    )
    (net (code "247") (name "Net-(DA3A-~{A})") (class "Default")
      (node (ref "DA3") (pin "2") (pinfunction "~{A}_2") (pintype "input"))
      (node (ref "R85") (pin "2") (pinfunction "2_2") (pintype "passive"))
    )
    (net (code "248") (name "Net-(DA3B-A)") (class "Default")
      (node (ref "DA3") (pin "5") (pinfunction "A_5") (pintype "input"))
      (node (ref "R79") (pin "2") (pinfunction "2_2") (pintype "passive"))
      (node (ref "VD40") (pin "A") (pinfunction "A_A") (pintype "passive"))
    )
    (net (code "249") (name "Net-(DA3B-B)") (class "Default")
      (node (ref "DA3") (pin "7") (pinfunction "B_7") (pintype "output"))
      (node (ref "R98") (pin "1") (pinfunction "1_1") (pintype "passive"))
      (node (ref "R99") (pin "2") (pinfunction "2_2") (pintype "passive"))
    )
    (net (code "250") (name "Net-(DA3B-~{A})") (class "Default")
      (node (ref "DA3") (pin "6") (pinfunction "~{A}_6") (pintype "input"))
      (node (ref "R100") (pin "2") (pinfunction "2_2") (pintype "passive"))
      (node (ref "R85") (pin "1") (pinfunction "1_1") (pintype "passive"))
      (node (ref "R99") (pin "1") (pinfunction "1_1") (pintype "passive"))
    )
    (net (code "251") (name "Net-(DA4A-C_OUT)") (class "Default")
      (node (ref "DA4") (pin "7") (pinfunction "C_OUT_7") (pintype "output"))
      (node (ref "DA7") (pin "2") (pinfunction "D_2") (pintype "input"))
      (node (ref "DA7") (pin "9") (pinfunction "~{D}_9") (pintype "input"))
      (node (ref "R107") (pin "2") (pinfunction "2_2") (pintype "passive"))
      (node (ref "R113") (pin "2") (pinfunction "2_2") (pintype "passive"))
    )
    (net (code "252") (name "Net-(DA4A-IN+)") (class "Default")
      (node (ref "C34") (pin "1") (pinfunction "1_1") (pintype "passive"))
      (node (ref "DA4") (pin "2") (pinfunction "IN+_2") (pintype "input"))
      (node (ref "R104") (pin "1") (pinfunction "1_1") (pintype "passive"))
      (node (ref "R107") (pin "1") (pinfunction "1_1") (pintype "passive"))
      (node (ref "R108") (pin "1") (pinfunction "1_1") (pintype "passive"))
    )
    (net (code "253") (name "Net-(DA4A-IN-)") (class "Default")
      (node (ref "C31") (pin "2") (pinfunction "2_2") (pintype "passive"))
      (node (ref "DA4") (pin "3") (pinfunction "IN-_3") (pintype "input"))
      (node (ref "R101") (pin "2") (pinfunction "2_2") (pintype "passive"))
    )
    (net (code "254") (name "Net-(DA5A-C_OUT)") (class "Default")
      (node (ref "DA5") (pin "7") (pinfunction "C_OUT_7") (pintype "output"))
      (node (ref "DA8") (pin "2") (pinfunction "D_2") (pintype "input"))
      (node (ref "DA8") (pin "9") (pinfunction "~{D}_9") (pintype "input"))
      (node (ref "R109") (pin "2") (pinfunction "2_2") (pintype "passive"))
      (node (ref "R114") (pin "2") (pinfunction "2_2") (pintype "passive"))
    )
    (net (code "255") (name "Net-(DA5A-IN+)") (class "Default")
      (node (ref "C35") (pin "1") (pinfunction "1_1") (pintype "passive"))
      (node (ref "DA5") (pin "2") (pinfunction "IN+_2") (pintype "input"))
      (node (ref "R105") (pin "1") (pinfunction "1_1") (pintype "passive"))
      (node (ref "R109") (pin "1") (pinfunction "1_1") (pintype "passive"))
      (node (ref "R110") (pin "1") (pinfunction "1_1") (pintype "passive"))
    )
    (net (code "256") (name "Net-(DA5A-IN-)") (class "Default")
      (node (ref "C32") (pin "2") (pinfunction "2_2") (pintype "passive"))
      (node (ref "DA5") (pin "3") (pinfunction "IN-_3") (pintype "input"))
      (node (ref "R102") (pin "2") (pinfunction "2_2") (pintype "passive"))
    )
    (net (code "257") (name "Net-(DA6A-C_OUT)") (class "Default")
      (node (ref "DA6") (pin "7") (pinfunction "C_OUT_7") (pintype "output"))
      (node (ref "DA9") (pin "2") (pinfunction "D_2") (pintype "input"))
      (node (ref "DA9") (pin "9") (pinfunction "~{D}_9") (pintype "input"))
      (node (ref "R111") (pin "2") (pinfunction "2_2") (pintype "passive"))
      (node (ref "R115") (pin "2") (pinfunction "2_2") (pintype "passive"))
    )
    (net (code "258") (name "Net-(DA6A-IN+)") (class "Default")
      (node (ref "C36") (pin "1") (pinfunction "1_1") (pintype "passive"))
      (node (ref "DA6") (pin "2") (pinfunction "IN+_2") (pintype "input"))
      (node (ref "R106") (pin "1") (pinfunction "1_1") (pintype "passive"))
      (node (ref "R111") (pin "1") (pinfunction "1_1") (pintype "passive"))
      (node (ref "R112") (pin "1") (pinfunction "1_1") (pintype "passive"))
    )
    (net (code "259") (name "Net-(DA6A-IN-)") (class "Default")
      (node (ref "C33") (pin "2") (pinfunction "2_2") (pintype "passive"))
      (node (ref "DA6") (pin "3") (pinfunction "IN-_3") (pintype "input"))
      (node (ref "R103") (pin "2") (pinfunction "2_2") (pintype "passive"))
    )
    (net (code "260") (name "Net-(DA7A-C)") (class "Default")
      (node (ref "C43") (pin "1") (pinfunction "1_1") (pintype "passive"))
      (node (ref "DA7") (pin "14") (pinfunction "C_14") (pintype "input"))
    )
    (net (code "261") (name "Net-(DA7A-R{slash}C)") (class "Default")
      (node (ref "C43") (pin "2") (pinfunction "2_2") (pintype "passive"))
      (node (ref "DA7") (pin "15") (pinfunction "R/C_15") (pintype "input"))
      (node (ref "R117") (pin "1") (pinfunction "1_1") (pintype "passive"))
    )
    (net (code "262") (name "Net-(DA7A-~{Q})") (class "Default")
      (node (ref "DA7") (pin "4") (pinfunction "~{Q}_4") (pintype "output"))
      (node (ref "DD3") (pin "1") (pinfunction "A_1") (pintype "input"))
    )
    (net (code "263") (name "Net-(DA7B-C)") (class "Default")
      (node (ref "C44") (pin "1") (pinfunction "1_1") (pintype "passive"))
      (node (ref "DA7") (pin "6") (pinfunction "C_6") (pintype "input"))
    )
    (net (code "264") (name "Net-(DA7B-R{slash}C)") (class "Default")
      (node (ref "C44") (pin "2") (pinfunction "2_2") (pintype "passive"))
      (node (ref "DA7") (pin "7") (pinfunction "R/C_7") (pintype "input"))
      (node (ref "R118") (pin "1") (pinfunction "1_1") (pintype "passive"))
    )
    (net (code "265") (name "Net-(DA7B-~{Q})") (class "Default")
      (node (ref "DA7") (pin "12") (pinfunction "~{Q}_12") (pintype "output"))
      (node (ref "DD3") (pin "2") (pinfunction "B_2") (pintype "input"))
    )
    (net (code "266") (name "Net-(DA8A-C)") (class "Default")
      (node (ref "C45") (pin "1") (pinfunction "1_1") (pintype "passive"))
      (node (ref "DA8") (pin "14") (pinfunction "C_14") (pintype "input"))
    )
    (net (code "267") (name "Net-(DA8A-R{slash}C)") (class "Default")
      (node (ref "C45") (pin "2") (pinfunction "2_2") (pintype "passive"))
      (node (ref "DA8") (pin "15") (pinfunction "R/C_15") (pintype "input"))
      (node (ref "R119") (pin "1") (pinfunction "1_1") (pintype "passive"))
    )
    (net (code "268") (name "Net-(DA8A-~{Q})") (class "Default")
      (node (ref "DA8") (pin "4") (pinfunction "~{Q}_4") (pintype "output"))
      (node (ref "DD3") (pin "3") (pinfunction "A_3") (pintype "input"))
    )
    (net (code "269") (name "Net-(DA8B-C)") (class "Default")
      (node (ref "C46") (pin "1") (pinfunction "1_1") (pintype "passive"))
      (node (ref "DA8") (pin "6") (pinfunction "C_6") (pintype "input"))
    )
    (net (code "270") (name "Net-(DA8B-R{slash}C)") (class "Default")
      (node (ref "C46") (pin "2") (pinfunction "2_2") (pintype "passive"))
      (node (ref "DA8") (pin "7") (pinfunction "R/C_7") (pintype "input"))
      (node (ref "R120") (pin "1") (pinfunction "1_1") (pintype "passive"))
    )
    (net (code "271") (name "Net-(DA8B-~{Q})") (class "Default")
      (node (ref "DA8") (pin "12") (pinfunction "~{Q}_12") (pintype "output"))
      (node (ref "DD3") (pin "4") (pinfunction "B_4") (pintype "input"))
    )
    (net (code "272") (name "Net-(DA9A-C)") (class "Default")
      (node (ref "C47") (pin "1") (pinfunction "1_1") (pintype "passive"))
      (node (ref "DA9") (pin "14") (pinfunction "C_14") (pintype "input"))
    )
    (net (code "273") (name "Net-(DA9A-R{slash}C)") (class "Default")
      (node (ref "C47") (pin "2") (pinfunction "2_2") (pintype "passive"))
      (node (ref "DA9") (pin "15") (pinfunction "R/C_15") (pintype "input"))
      (node (ref "R121") (pin "1") (pinfunction "1_1") (pintype "passive"))
    )
    (net (code "274") (name "Net-(DA9A-~{Q})") (class "Default")
      (node (ref "DA9") (pin "4") (pinfunction "~{Q}_4") (pintype "output"))
      (node (ref "DD3") (pin "5") (pinfunction "C_5") (pintype "input"))
    )
    (net (code "275") (name "Net-(DA9B-C)") (class "Default")
      (node (ref "C48") (pin "1") (pinfunction "1_1") (pintype "passive"))
      (node (ref "DA9") (pin "6") (pinfunction "C_6") (pintype "input"))
    )
    (net (code "276") (name "Net-(DA9B-R{slash}C)") (class "Default")
      (node (ref "C48") (pin "2") (pinfunction "2_2") (pintype "passive"))
      (node (ref "DA9") (pin "7") (pinfunction "R/C_7") (pintype "input"))
      (node (ref "R122") (pin "1") (pinfunction "1_1") (pintype "passive"))
    )
    (net (code "277") (name "Net-(DA9B-~{Q})") (class "Default")
      (node (ref "DA9") (pin "12") (pinfunction "~{Q}_12") (pintype "output"))
      (node (ref "DD3") (pin "13") (pinfunction "C_13") (pintype "input"))
    )
    (net (code "278") (name "Net-(DA10-CONT)") (class "Default")
      (node (ref "C55") (pin "1") (pinfunction "1_1") (pintype "passive"))
      (node (ref "DA10") (pin "5") (pinfunction "CONT_5") (pintype "input"))
    )
    (net (code "279") (name "Net-(DA10-DISCH)") (class "Default")
      (node (ref "C49") (pin "1") (pinfunction "1_1") (pintype "passive"))
      (node (ref "C51") (pin "1") (pinfunction "1_1") (pintype "passive"))
      (node (ref "DA10") (pin "6") (pinfunction "THRES_6") (pintype "input"))
      (node (ref "DA10") (pin "7") (pinfunction "DISCH_7") (pintype "input"))
      (node (ref "R123") (pin "1") (pinfunction "1_1") (pintype "passive"))
    )
    (net (code "280") (name "Net-(DA10-OUT)") (class "Default")
      (node (ref "DA10") (pin "3") (pinfunction "OUT_3") (pintype "output"))
      (node (ref "R130") (pin "1") (pinfunction "1_1") (pintype "passive"))
    )
    (net (code "281") (name "Net-(DA10-TRIG)") (class "Default")
      (node (ref "DA10") (pin "2") (pinfunction "TRIG_2") (pintype "input"))
      (node (ref "DD3") (pin "8") (pinfunction "Y_8") (pintype "output"))
    )
    (net (code "282") (name "Net-(DA11-DRN)") (class "Default")
      (node (ref "DA11") (pin "2") (pinfunction "DRN_2") (pintype "bidirectional"))
      (node (ref "R132") (pin "2") (pinfunction "2_2") (pintype "passive"))
      (node (ref "VD53") (pin "A2") (pinfunction "A2_A2") (pintype "passive"))
    )
    (net (code "283") (name "Net-(DA11-GATE)") (class "Default")
      (node (ref "DA11") (pin "4") (pinfunction "GATE_4") (pintype "output"))
      (node (ref "VT1") (pin "1") (pinfunction "G_1") (pintype "passive"))
    )
    (net (code "284") (name "Net-(DA11-IN)") (class "Default")
      (node (ref "DA11") (pin "7") (pinfunction "IN_7") (pintype "input"))
      (node (ref "R131") (pin "2") (pinfunction "2_2") (pintype "passive"))
      (node (ref "VD55") (pin "C") (pinfunction "C_C") (pintype "passive"))
    )
    (net (code "285") (name "Net-(DA11-SRC)") (class "Default")
      (node (ref "DA11") (pin "1") (pinfunction "SRC_1") (pintype "bidirectional"))
      (node (ref "R134") (pin "1") (pinfunction "1_1") (pintype "passive"))
    )
    (net (code "286") (name "Net-(DA11-VCC)") (class "Default")
      (node (ref "C63") (pin "1") (pinfunction "1_1") (pintype "passive"))
      (node (ref "DA11") (pin "5") (pinfunction "VCC_5") (pintype "power_in"))
      (node (ref "R135") (pin "1") (pinfunction "1_1") (pintype "passive"))
    )
    (net (code "287") (name "Net-(DA11-VT)") (class "Default")
      (node (ref "C62") (pin "1") (pinfunction "1_1") (pintype "passive"))
      (node (ref "DA11") (pin "8") (pinfunction "VT_8") (pintype "bidirectional"))
      (node (ref "R133") (pin "2") (pinfunction "2_2") (pintype "passive"))
    )
    (net (code "288") (name "Net-(DA12-FB)") (class "Default")
      (node (ref "C66") (pin "+") (pinfunction "+_+") (pintype "passive"))
      (node (ref "DA12") (pin "4") (pinfunction "FB_4") (pintype "input"))
      (node (ref "L2") (pin "2") (pinfunction "2_2") (pintype "passive"))
      (node (ref "RK2") (pin "1") (pinfunction "P$1_1") (pintype "passive"))
    )
    (net (code "289") (name "Net-(DA12-OUT)") (class "Default")
      (node (ref "DA12") (pin "2") (pinfunction "OUT_2") (pintype "output"))
      (node (ref "L2") (pin "1") (pinfunction "1_1") (pintype "passive"))
      (node (ref "VD58") (pin "C") (pinfunction "C_C") (pintype "passive"))
    )
    (net (code "290") (name "Net-(DA13-OUT)") (class "Default")
      (node (ref "DA13") (pin "2") (pinfunction "OUT_2") (pintype "output"))
      (node (ref "L3") (pin "1") (pinfunction "1_1") (pintype "passive"))
      (node (ref "VD59") (pin "C") (pinfunction "C_C") (pintype "passive"))
    )
    (net (code "291") (name "Net-(DA13-~{ON}{slash}OFF)") (class "Default")
      (node (ref "C58") (pin "1") (pinfunction "1_1") (pintype "passive"))
      (node (ref "C61") (pin "2") (pinfunction "2_2") (pintype "passive"))
      (node (ref "C67") (pin "-") (pinfunction "-_-") (pintype "passive"))
      (node (ref "DA13") (pin "3") (pinfunction "GND_3") (pintype "input"))
      (node (ref "DA13") (pin "5") (pinfunction "~{ON}/OFF_5") (pintype "input"))
      (node (ref "DA13") (pin "6") (pinfunction "GND_6") (pintype "input"))
      (node (ref "RK3") (pin "1") (pinfunction "P$1_1") (pintype "passive"))
      (node (ref "VD59") (pin "A") (pinfunction "A_A") (pintype "passive"))
    )
    (net (code "292") (name "Net-(DA14-IN)") (class "Default")
      (node (ref "C64") (pin "+") (pinfunction "+_+") (pintype "passive"))
      (node (ref "C65") (pin "1") (pinfunction "1_1") (pintype "passive"))
      (node (ref "DA14") (pin "3") (pinfunction "IN_3") (pintype "power_in"))
      (node (ref "RK1") (pin "2") (pinfunction "P$2_2") (pintype "passive"))
      (node (ref "VD60") (pin "C") (pinfunction "C_C") (pintype "passive"))
    )
    (net (code "293") (name "Net-(DA15-3.3V)") (class "Default")
      (node (ref "DA15") (pin "5") (pinfunction "3.3V_5") (pintype "power_in"))
      (node (ref "Z44") (pin "1") (pinfunction "1_1") (pintype "passive"))
    )
    (net (code "294") (name "Net-(DA15-D3)") (class "Default")
      (node (ref "DA15") (pin "4") (pinfunction "D3_4") (pintype "bidirectional"))
      (node (ref "Z43") (pin "1") (pinfunction "1_1") (pintype "passive"))
    )
    (net (code "295") (name "Net-(DA15-D4)") (class "Default")
      (node (ref "DA15") (pin "6") (pinfunction "D4_6") (pintype "bidirectional"))
      (node (ref "Z42") (pin "1") (pinfunction "1_1") (pintype "passive"))
    )
    (net (code "296") (name "Net-(DA16-CANH)") (class "Default")
      (node (ref "DA16") (pin "7") (pinfunction "CANH_7") (pintype "bidirectional"))
      (node (ref "XP12") (pin "2") (pinfunction "2_2") (pintype "passive"))
      (node (ref "XP13") (pin "1") (pinfunction "1_1") (pintype "passive"))
    )
    (net (code "297") (name "Net-(DA16-CANL)") (class "Default")
      (node (ref "DA16") (pin "6") (pinfunction "CANL_6") (pintype "bidirectional"))
      (node (ref "R358") (pin "2") (pinfunction "2_2") (pintype "passive"))
      (node (ref "XP12") (pin "1") (pinfunction "1_1") (pintype "passive"))
    )
    (net (code "298") (name "Net-(DA16-RXD)") (class "Default")
      (node (ref "DA16") (pin "4") (pinfunction "RXD_4") (pintype "output"))
      (node (ref "Z47") (pin "1") (pinfunction "1_1") (pintype "passive"))
    )
    (net (code "299") (name "Net-(DA16-TXD)") (class "Default")
      (node (ref "DA16") (pin "1") (pinfunction "TXD_1") (pintype "input"))
      (node (ref "Z50") (pin "1") (pinfunction "1_1") (pintype "passive"))
    )
    (net (code "300") (name "Net-(DA17-C1+)") (class "Default")
      (node (ref "C146") (pin "1") (pinfunction "1_1") (pintype "passive"))
      (node (ref "DA17") (pin "1") (pinfunction "C1+_1") (pintype "passive"))
    )
    (net (code "301") (name "Net-(DA17-C1-)") (class "Default")
      (node (ref "C146") (pin "2") (pinfunction "2_2") (pintype "passive"))
      (node (ref "DA17") (pin "3") (pinfunction "C1-_3") (pintype "passive"))
    )
    (net (code "302") (name "Net-(DA17-C2+)") (class "Default")
      (node (ref "C147") (pin "1") (pinfunction "1_1") (pintype "passive"))
      (node (ref "DA17") (pin "4") (pinfunction "C2+_4") (pintype "passive"))
    )
    (net (code "303") (name "Net-(DA17-C2-)") (class "Default")
      (node (ref "C147") (pin "2") (pinfunction "2_2") (pintype "passive"))
      (node (ref "DA17") (pin "5") (pinfunction "C2-_5") (pintype "passive"))
    )
    (net (code "304") (name "Net-(DA17-R2IN)") (class "Default")
      (node (ref "DA17") (pin "8") (pinfunction "R2IN_8") (pintype "input"))
      (node (ref "Z46") (pin "3") (pinfunction "3_3") (pintype "passive"))
    )
    (net (code "305") (name "Net-(DA17-T2OUT)") (class "Default")
      (node (ref "DA17") (pin "7") (pinfunction "T2OUT_7") (pintype "output"))
      (node (ref "Z45") (pin "3") (pinfunction "3_3") (pintype "passive"))
    )
    (net (code "306") (name "Net-(DA17-V+)") (class "Default")
      (node (ref "C143") (pin "1") (pinfunction "1_1") (pintype "passive"))
      (node (ref "DA17") (pin "2") (pinfunction "V+_2") (pintype "passive"))
    )
    (net (code "307") (name "Net-(DA17-V-)") (class "Default")
      (node (ref "C145") (pin "1") (pinfunction "1_1") (pintype "passive"))
      (node (ref "DA17") (pin "6") (pinfunction "V-_6") (pintype "passive"))
    )
    (net (code "308") (name "Net-(DD1-OSC_IN)") (class "Default")
      (node (ref "C3") (pin "1") (pinfunction "1_1") (pintype "passive"))
      (node (ref "DD1") (pin "12") (pinfunction "OSC_IN_12") (pintype "input"))
      (node (ref "ZQ1") (pin "2") (pinfunction "P$2_2") (pintype "bidirectional"))
    )
    (net (code "309") (name "Net-(DD1-OSC_OUT)") (class "Default")
      (node (ref "C4") (pin "1") (pinfunction "1_1") (pintype "passive"))
      (node (ref "DD1") (pin "13") (pinfunction "OSC_OUT_13") (pintype "output"))
      (node (ref "ZQ1") (pin "1") (pinfunction "P$1_1") (pintype "bidirectional"))
    )
    (net (code "310") (name "Net-(DD1-PB10(I2C2_SCL{slash}USART3_TX{slash}TIM2_CH3)*)") (class "Default")
      (node (ref "DD1") (pin "47") (pinfunction "PB10(I2C2_SCL/USART3_TX/TIM2_CH3)*_47") (pintype "bidirectional"))
      (node (ref "Z11") (pin "3") (pinfunction "3_3") (pintype "passive"))
    )
    (net (code "311") (name "Net-(DD1-PB11(I2C2_SDA{slash}USART3_RX{slash}TIM2_CH4)*)") (class "Default")
      (node (ref "DD1") (pin "48") (pinfunction "PB11(I2C2_SDA/USART3_RX/TIM2_CH4)*_48") (pintype "bidirectional"))
      (node (ref "Z17") (pin "3") (pinfunction "3_3") (pintype "passive"))
    )
    (net (code "312") (name "Net-(DD1-PB12(SPI2_NSS{slash}I2S2_WS{slash}I2C2_SMBA{slash}USART3_CK{slash}TIM1_BKIN)*)") (class "Default")
      (node (ref "DD1") (pin "51") (pinfunction "PB12(SPI2_NSS/I2S2_WS/I2C2_SMBA/USART3_CK/TIM1_BKIN)*_51") (pintype "bidirectional"))
      (node (ref "Z12") (pin "1") (pinfunction "1_1") (pintype "passive"))
    )
    (net (code "313") (name "Net-(DD1-PB13(SPI2_SCK{slash}I2S2_SCK{slash}USART3_CTS{slash}TIM1_CH1N)*)") (class "Default")
      (node (ref "DD1") (pin "52") (pinfunction "PB13(SPI2_SCK/I2S2_SCK/USART3_CTS/TIM1_CH1N)*_52") (pintype "bidirectional"))
      (node (ref "Z18") (pin "1") (pinfunction "1_1") (pintype "passive"))
    )
    (net (code "314") (name "Net-(DD1-PB14(SPI2_MISO{slash}USART3_RTS{slash}TIM1_CH2N)*)") (class "Default")
      (node (ref "DD1") (pin "53") (pinfunction "PB14(SPI2_MISO/USART3_RTS/TIM1_CH2N)*_53") (pintype "bidirectional"))
      (node (ref "Z13") (pin "1") (pinfunction "1_1") (pintype "passive"))
    )
    (net (code "315") (name "Net-(DD1-PB15(SPI2_MOSI{slash}I2S2_SD{slash}TIM1_CH3N)*)") (class "Default")
      (node (ref "DD1") (pin "54") (pinfunction "PB15(SPI2_MOSI/I2S2_SD/TIM1_CH3N)*_54") (pintype "bidirectional"))
      (node (ref "Z19") (pin "1") (pinfunction "1_1") (pintype "passive"))
    )
    (net (code "316") (name "Net-(DD1-PE0(TIM4_ETR{slash}FSMC_NBL0)*)") (class "Default")
      (node (ref "DD1") (pin "97") (pinfunction "PE0(TIM4_ETR/FSMC_NBL0)*_97") (pintype "bidirectional"))
      (node (ref "Z14") (pin "1") (pinfunction "1_1") (pintype "passive"))
    )
    (net (code "317") (name "Net-(DD1-PE2(TRACECK{slash}FSMC_A23)*)") (class "Default")
      (node (ref "DD1") (pin "1") (pinfunction "PE2(TRACECK/FSMC_A23)*_1") (pintype "bidirectional"))
      (node (ref "Z20") (pin "1") (pinfunction "1_1") (pintype "passive"))
    )
    (net (code "318") (name "Net-(DD1-PE3(TRACED0{slash}FSMC_A19)*)") (class "Default")
      (node (ref "DD1") (pin "2") (pinfunction "PE3(TRACED0/FSMC_A19)*_2") (pintype "bidirectional"))
      (node (ref "Z15") (pin "1") (pinfunction "1_1") (pintype "passive"))
    )
    (net (code "319") (name "Net-(DD1-PE4(TRACED1{slash}FSMC_A20)*)") (class "Default")
      (node (ref "DD1") (pin "3") (pinfunction "PE4(TRACED1/FSMC_A20)*_3") (pintype "bidirectional"))
      (node (ref "Z21") (pin "1") (pinfunction "1_1") (pintype "passive"))
    )
    (net (code "320") (name "Net-(DD1-PE5(TRACED2{slash}FSMC_A21)*)") (class "Default")
      (node (ref "DD1") (pin "4") (pinfunction "PE5(TRACED2/FSMC_A21)*_4") (pintype "bidirectional"))
      (node (ref "Z16") (pin "1") (pinfunction "1_1") (pintype "passive"))
    )
    (net (code "321") (name "Net-(DD1-VDD_A)") (class "Default")
      (node (ref "C7") (pin "1") (pinfunction "1_1") (pintype "passive"))
      (node (ref "DD1") (pin "21") (pinfunction "VREF+_21") (pintype "power_in"))
      (node (ref "DD1") (pin "22") (pinfunction "VDD_A_22") (pintype "power_in"))
      (node (ref "L1") (pin "2") (pinfunction "2_2") (pintype "passive"))
    )
    (net (code "322") (name "Net-(DD1-VREF-)") (class "Default")
      (node (ref "C7") (pin "2") (pinfunction "2_2") (pintype "passive"))
      (node (ref "DD1") (pin "19") (pinfunction "VSS_A_19") (pintype "power_in"))
      (node (ref "DD1") (pin "20") (pinfunction "VREF-_20") (pintype "power_in"))
      (node (ref "R10") (pin "2") (pinfunction "2_2") (pintype "passive"))
      (node (ref "Z5") (pin "3") (pinfunction "3_3") (pintype "passive"))
    )
    (net (code "323") (name "Net-(DD2-SCL)") (class "Default")
      (node (ref "DD2") (pin "6") (pinfunction "SCL_6") (pintype "open_collector"))
      (node (ref "R25") (pin "2") (pinfunction "2_2") (pintype "passive"))
      (node (ref "Z11") (pin "1") (pinfunction "1_1") (pintype "passive"))
    )
    (net (code "324") (name "Net-(DD2-SDA)") (class "Default")
      (node (ref "DD2") (pin "5") (pinfunction "SDA_5") (pintype "open_collector"))
      (node (ref "R15") (pin "2") (pinfunction "2_2") (pintype "passive"))
      (node (ref "Z17") (pin "1") (pinfunction "1_1") (pintype "passive"))
    )
    (net (code "325") (name "Net-(DD3A-Y)") (class "Default")
      (node (ref "DD3") (pin "12") (pinfunction "Y_12") (pintype "output"))
      (node (ref "DD3") (pin "9") (pinfunction "A_9") (pintype "input"))
    )
    (net (code "326") (name "Net-(DD3B-Y)") (class "Default")
      (node (ref "DD3") (pin "10") (pinfunction "B_10") (pintype "input"))
      (node (ref "DD3") (pin "11") (pinfunction "C_11") (pintype "input"))
      (node (ref "DD3") (pin "6") (pinfunction "Y_6") (pintype "output"))
    )
    (net (code "327") (name "Net-(DD4A-SER)") (class "Default")
      (node (ref "DD4") (pin "10") (pinfunction "SER_10") (pintype "input"))
      (node (ref "R188") (pin "2") (pinfunction "2_2") (pintype "passive"))
    )
    (net (code "328") (name "Net-(DD12A-QA)") (class "Default")
      (node (ref "DD12") (pin "15") (pinfunction "QA_15") (pintype "tri_state"))
      (node (ref "R334") (pin "2") (pinfunction "2_2") (pintype "passive"))
    )
    (net (code "329") (name "Net-(DD12A-QB)") (class "Default")
      (node (ref "DD12") (pin "1") (pinfunction "QB_1") (pintype "tri_state"))
      (node (ref "R335") (pin "2") (pinfunction "2_2") (pintype "passive"))
    )
    (net (code "330") (name "Net-(DD12A-QC)") (class "Default")
      (node (ref "DD12") (pin "2") (pinfunction "QC_2") (pintype "tri_state"))
      (node (ref "R336") (pin "2") (pinfunction "2_2") (pintype "passive"))
    )
    (net (code "331") (name "Net-(DD12A-QD)") (class "Default")
      (node (ref "DD12") (pin "3") (pinfunction "QD_3") (pintype "tri_state"))
      (node (ref "R337") (pin "2") (pinfunction "2_2") (pintype "passive"))
    )
    (net (code "332") (name "Net-(DD12A-QE)") (class "Default")
      (node (ref "DD12") (pin "4") (pinfunction "QE_4") (pintype "tri_state"))
      (node (ref "R338") (pin "2") (pinfunction "2_2") (pintype "passive"))
    )
    (net (code "333") (name "Net-(DD12A-QF)") (class "Default")
      (node (ref "DD12") (pin "5") (pinfunction "QF_5") (pintype "tri_state"))
      (node (ref "R339") (pin "2") (pinfunction "2_2") (pintype "passive"))
    )
    (net (code "334") (name "Net-(DD12A-QG)") (class "Default")
      (node (ref "DD12") (pin "6") (pinfunction "QG_6") (pintype "tri_state"))
      (node (ref "R340") (pin "2") (pinfunction "2_2") (pintype "passive"))
    )
    (net (code "335") (name "Net-(DD12A-QH)") (class "Default")
      (node (ref "DD12") (pin "7") (pinfunction "QH_7") (pintype "tri_state"))
      (node (ref "R341") (pin "2") (pinfunction "2_2") (pintype "passive"))
    )
    (net (code "336") (name "Net-(R1-Pad1)") (class "Default")
      (node (ref "R1") (pin "1") (pinfunction "1_1") (pintype "passive"))
      (node (ref "XP1") (pin "3") (pinfunction "3_3") (pintype "passive"))
      (node (ref "Z2") (pin "3") (pinfunction "3_3") (pintype "passive"))
    )
    (net (code "337") (name "Net-(R2-Pad1)") (class "Default")
      (node (ref "R2") (pin "1") (pinfunction "1_1") (pintype "passive"))
      (node (ref "XP1") (pin "5") (pinfunction "5_5") (pintype "passive"))
      (node (ref "Z6") (pin "3") (pinfunction "3_3") (pintype "passive"))
    )
    (net (code "338") (name "Net-(R3-Pad1)") (class "Default")
      (node (ref "R3") (pin "1") (pinfunction "1_1") (pintype "passive"))
      (node (ref "XP1") (pin "11") (pinfunction "11_11") (pintype "passive"))
    )
    (net (code "339") (name "Net-(R4-Pad1)") (class "Default")
      (node (ref "R4") (pin "1") (pinfunction "1_1") (pintype "passive"))
      (node (ref "XP1") (pin "17") (pinfunction "17_17") (pintype "passive"))
    )
    (net (code "340") (name "Net-(R5-Pad1)") (class "Default")
      (node (ref "R5") (pin "1") (pinfunction "1_1") (pintype "passive"))
      (node (ref "XP1") (pin "19") (pinfunction "19_19") (pintype "passive"))
    )
    (net (code "341") (name "Net-(R6-Pad1)") (class "Default")
      (node (ref "R6") (pin "1") (pinfunction "1_1") (pintype "passive"))
      (node (ref "XP1") (pin "7") (pinfunction "7_7") (pintype "passive"))
      (node (ref "Z3") (pin "3") (pinfunction "3_3") (pintype "passive"))
    )
    (net (code "342") (name "Net-(R7-Pad1)") (class "Default")
      (node (ref "R7") (pin "1") (pinfunction "1_1") (pintype "passive"))
      (node (ref "XP1") (pin "9") (pinfunction "9_9") (pintype "passive"))
      (node (ref "Z7") (pin "3") (pinfunction "3_3") (pintype "passive"))
    )
    (net (code "343") (name "Net-(R8-Pad1)") (class "Default")
      (node (ref "R8") (pin "1") (pinfunction "1_1") (pintype "passive"))
      (node (ref "XP1") (pin "13") (pinfunction "13_13") (pintype "passive"))
      (node (ref "Z4") (pin "3") (pinfunction "3_3") (pintype "passive"))
    )
    (net (code "344") (name "Net-(R11-Pad1)") (class "Default")
      (node (ref "R11") (pin "1") (pinfunction "1_1") (pintype "passive"))
      (node (ref "Z9") (pin "1") (pinfunction "1_1") (pintype "passive"))
    )
    (net (code "345") (name "Net-(R11-Pad2)") (class "Default")
      (node (ref "R11") (pin "2") (pinfunction "2_2") (pintype "passive"))
      (node (ref "VD1") (pin "A") (pinfunction "A_A") (pintype "passive"))
      (node (ref "XP2") (pin "2") (pinfunction "2_2") (pintype "passive"))
    )
    (net (code "346") (name "Net-(R12-Pad1)") (class "Default")
      (node (ref "R12") (pin "1") (pinfunction "1_1") (pintype "passive"))
      (node (ref "Z10") (pin "1") (pinfunction "1_1") (pintype "passive"))
    )
    (net (code "347") (name "Net-(R12-Pad2)") (class "Default")
      (node (ref "R12") (pin "2") (pinfunction "2_2") (pintype "passive"))
      (node (ref "VD2") (pin "A") (pinfunction "A_A") (pintype "passive"))
      (node (ref "XP3") (pin "2") (pinfunction "2_2") (pintype "passive"))
    )
    (net (code "348") (name "Net-(R13-Pad2)") (class "Default")
      (node (ref "R13") (pin "2") (pinfunction "2_2") (pintype "passive"))
      (node (ref "VD1") (pin "C") (pinfunction "C_C") (pintype "passive"))
    )
    (net (code "349") (name "Net-(R14-Pad2)") (class "Default")
      (node (ref "R14") (pin "2") (pinfunction "2_2") (pintype "passive"))
      (node (ref "VD2") (pin "C") (pinfunction "C_C") (pintype "passive"))
    )
    (net (code "350") (name "Net-(R16-Pad2)") (class "Default")
      (node (ref "R16") (pin "2") (pinfunction "2_2") (pintype "passive"))
      (node (ref "Z12") (pin "3") (pinfunction "3_3") (pintype "passive"))
    )
    (net (code "351") (name "Net-(R17-Pad2)") (class "Default")
      (node (ref "R17") (pin "2") (pinfunction "2_2") (pintype "passive"))
      (node (ref "Z18") (pin "3") (pinfunction "3_3") (pintype "passive"))
    )
    (net (code "352") (name "Net-(R18-Pad2)") (class "Default")
      (node (ref "R18") (pin "2") (pinfunction "2_2") (pintype "passive"))
      (node (ref "Z13") (pin "3") (pinfunction "3_3") (pintype "passive"))
    )
    (net (code "353") (name "Net-(R19-Pad2)") (class "Default")
      (node (ref "R19") (pin "2") (pinfunction "2_2") (pintype "passive"))
      (node (ref "Z19") (pin "3") (pinfunction "3_3") (pintype "passive"))
    )
    (net (code "354") (name "Net-(R20-Pad1)") (class "Default")
      (node (ref "R20") (pin "1") (pinfunction "1_1") (pintype "passive"))
      (node (ref "Z14") (pin "3") (pinfunction "3_3") (pintype "passive"))
    )
    (net (code "355") (name "Net-(R20-Pad2)") (class "Default")
      (node (ref "R20") (pin "2") (pinfunction "2_2") (pintype "passive"))
      (node (ref "VD3") (pin "C") (pinfunction "C_C") (pintype "passive"))
    )
    (net (code "356") (name "Net-(R21-Pad2)") (class "Default")
      (node (ref "R21") (pin "2") (pinfunction "2_2") (pintype "passive"))
      (node (ref "Z20") (pin "3") (pinfunction "3_3") (pintype "passive"))
    )
    (net (code "357") (name "Net-(R22-Pad2)") (class "Default")
      (node (ref "R22") (pin "2") (pinfunction "2_2") (pintype "passive"))
      (node (ref "Z15") (pin "3") (pinfunction "3_3") (pintype "passive"))
    )
    (net (code "358") (name "Net-(R23-Pad2)") (class "Default")
      (node (ref "R23") (pin "2") (pinfunction "2_2") (pintype "passive"))
      (node (ref "Z21") (pin "3") (pinfunction "3_3") (pintype "passive"))
    )
    (net (code "359") (name "Net-(R24-Pad2)") (class "Default")
      (node (ref "R24") (pin "2") (pinfunction "2_2") (pintype "passive"))
      (node (ref "Z16") (pin "3") (pinfunction "3_3") (pintype "passive"))
    )
    (net (code "360") (name "Net-(R28-Pad2)") (class "Default")
      (node (ref "R28") (pin "2") (pinfunction "2_2") (pintype "passive"))
      (node (ref "VD14") (pin "A") (pinfunction "A_A") (pintype "passive"))
      (node (ref "VD6") (pin "A1") (pinfunction "A1_A1") (pintype "passive"))
    )
    (net (code "361") (name "Net-(R34-Pad1)") (class "Default")
      (node (ref "R34") (pin "1") (pinfunction "1_1") (pintype "passive"))
      (node (ref "VD12") (pin "C") (pinfunction "C_C") (pintype "passive"))
    )
    (net (code "362") (name "Net-(R35-Pad1)") (class "Default")
      (node (ref "R35") (pin "1") (pinfunction "1_1") (pintype "passive"))
      (node (ref "VD13") (pin "C") (pinfunction "C_C") (pintype "passive"))
    )
    (net (code "363") (name "Net-(R36-Pad1)") (class "Default")
      (node (ref "R36") (pin "1") (pinfunction "1_1") (pintype "passive"))
      (node (ref "VD14") (pin "C") (pinfunction "C_C") (pintype "passive"))
    )
    (net (code "364") (name "Net-(R37-Pad1)") (class "Default")
      (node (ref "R37") (pin "1") (pinfunction "1_1") (pintype "passive"))
      (node (ref "VD15") (pin "C") (pinfunction "C_C") (pintype "passive"))
    )
    (net (code "365") (name "Net-(R38-Pad1)") (class "Default")
      (node (ref "R38") (pin "1") (pinfunction "1_1") (pintype "passive"))
      (node (ref "VD16") (pin "C") (pinfunction "C_C") (pintype "passive"))
    )
    (net (code "366") (name "Net-(R39-Pad1)") (class "Default")
      (node (ref "R39") (pin "1") (pinfunction "1_1") (pintype "passive"))
      (node (ref "VD17") (pin "C") (pinfunction "C_C") (pintype "passive"))
    )
    (net (code "367") (name "Net-(R40-Pad1)") (class "Default")
      (node (ref "R40") (pin "1") (pinfunction "1_1") (pintype "passive"))
      (node (ref "VD18") (pin "C") (pinfunction "C_C") (pintype "passive"))
    )
    (net (code "368") (name "Net-(R41-Pad1)") (class "Default")
      (node (ref "R41") (pin "1") (pinfunction "1_1") (pintype "passive"))
      (node (ref "VD19") (pin "C") (pinfunction "C_C") (pintype "passive"))
    )
    (net (code "369") (name "Net-(R58-Pad1)") (class "Default")
      (node (ref "R58") (pin "1") (pinfunction "1_1") (pintype "passive"))
      (node (ref "VD28") (pin "C") (pinfunction "C_C") (pintype "passive"))
    )
    (net (code "370") (name "Net-(R59-Pad1)") (class "Default")
      (node (ref "R59") (pin "1") (pinfunction "1_1") (pintype "passive"))
      (node (ref "VD29") (pin "C") (pinfunction "C_C") (pintype "passive"))
    )
    (net (code "371") (name "Net-(R60-Pad1)") (class "Default")
      (node (ref "R60") (pin "1") (pinfunction "1_1") (pintype "passive"))
      (node (ref "VD30") (pin "C") (pinfunction "C_C") (pintype "passive"))
    )
    (net (code "372") (name "Net-(R61-Pad1)") (class "Default")
      (node (ref "R61") (pin "1") (pinfunction "1_1") (pintype "passive"))
      (node (ref "VD31") (pin "C") (pinfunction "C_C") (pintype "passive"))
    )
    (net (code "373") (name "Net-(R62-Pad1)") (class "Default")
      (node (ref "R62") (pin "1") (pinfunction "1_1") (pintype "passive"))
      (node (ref "VD32") (pin "C") (pinfunction "C_C") (pintype "passive"))
    )
    (net (code "374") (name "Net-(R63-Pad1)") (class "Default")
      (node (ref "R63") (pin "1") (pinfunction "1_1") (pintype "passive"))
      (node (ref "VD33") (pin "C") (pinfunction "C_C") (pintype "passive"))
    )
    (net (code "375") (name "Net-(R64-Pad1)") (class "Default")
      (node (ref "R64") (pin "1") (pinfunction "1_1") (pintype "passive"))
      (node (ref "VD34") (pin "C") (pinfunction "C_C") (pintype "passive"))
    )
    (net (code "376") (name "Net-(R65-Pad1)") (class "Default")
      (node (ref "R65") (pin "1") (pinfunction "1_1") (pintype "passive"))
      (node (ref "VD35") (pin "C") (pinfunction "C_C") (pintype "passive"))
    )
    (net (code "377") (name "Net-(R87-Pad1)") (class "Default")
      (node (ref "R87") (pin "1") (pinfunction "1_1") (pintype "passive"))
      (node (ref "R88") (pin "2") (pinfunction "2_2") (pintype "passive"))
    )
    (net (code "378") (name "Net-(R92-Pad1)") (class "Default")
      (node (ref "R92") (pin "1") (pinfunction "1_1") (pintype "passive"))
      (node (ref "R93") (pin "2") (pinfunction "2_2") (pintype "passive"))
    )
    (net (code "379") (name "Net-(R97-Pad1)") (class "Default")
      (node (ref "R97") (pin "1") (pinfunction "1_1") (pintype "passive"))
      (node (ref "R98") (pin "2") (pinfunction "2_2") (pintype "passive"))
    )
    (net (code "380") (name "Net-(R116-S)") (class "Default")
      (node (ref "R108") (pin "2") (pinfunction "2_2") (pintype "passive"))
      (node (ref "R110") (pin "2") (pinfunction "2_2") (pintype "passive"))
      (node (ref "R112") (pin "2") (pinfunction "2_2") (pintype "passive"))
      (node (ref "R116") (pin "2") (pinfunction "S_2") (pintype "passive"))
    )
    (net (code "381") (name "Net-(R126-Pad2)") (class "Default")
      (node (ref "R126") (pin "2") (pinfunction "2_2") (pintype "passive"))
      (node (ref "R128") (pin "2") (pinfunction "2_2") (pintype "passive"))
      (node (ref "VD51") (pin "C") (pinfunction "C_C") (pintype "passive"))
      (node (ref "Z38") (pin "1") (pinfunction "1_1") (pintype "passive"))
    )
    (net (code "382") (name "Net-(R127-Pad2)") (class "Default")
      (node (ref "R127") (pin "2") (pinfunction "2_2") (pintype "passive"))
      (node (ref "R129") (pin "2") (pinfunction "2_2") (pintype "passive"))
      (node (ref "VD52") (pin "C") (pinfunction "C_C") (pintype "passive"))
      (node (ref "Z39") (pin "1") (pinfunction "1_1") (pintype "passive"))
    )
    (net (code "383") (name "Net-(R130-Pad2)") (class "Default")
      (node (ref "R130") (pin "2") (pinfunction "2_2") (pintype "passive"))
      (node (ref "VD50") (pin "C") (pinfunction "C_C") (pintype "passive"))
      (node (ref "Z40") (pin "1") (pinfunction "1_1") (pintype "passive"))
    )
    (net (code "384") (name "Net-(R136-Pad2)") (class "Default")
      (node (ref "R136") (pin "2") (pinfunction "2_2") (pintype "passive"))
      (node (ref "VD64") (pin "A") (pinfunction "A_A") (pintype "passive"))
    )
    (net (code "385") (name "Net-(R137-Pad1)") (class "Default")
      (node (ref "R137") (pin "1") (pinfunction "1_1") (pintype "passive"))
      (node (ref "VD65") (pin "C") (pinfunction "C_C") (pintype "passive"))
    )
    (net (code "386") (name "Net-(R154-Pad2)") (class "Default")
      (node (ref "R154") (pin "2") (pinfunction "2_2") (pintype "passive"))
      (node (ref "VD82") (pin "C") (pinfunction "C_C") (pintype "passive"))
    )
    (net (code "387") (name "Net-(R155-Pad2)") (class "Default")
      (node (ref "R155") (pin "2") (pinfunction "2_2") (pintype "passive"))
      (node (ref "VD83") (pin "C") (pinfunction "C_C") (pintype "passive"))
    )
    (net (code "388") (name "Net-(R156-Pad2)") (class "Default")
      (node (ref "R156") (pin "2") (pinfunction "2_2") (pintype "passive"))
      (node (ref "VD84") (pin "C") (pinfunction "C_C") (pintype "passive"))
    )
    (net (code "389") (name "Net-(R157-Pad2)") (class "Default")
      (node (ref "R157") (pin "2") (pinfunction "2_2") (pintype "passive"))
      (node (ref "VD85") (pin "C") (pinfunction "C_C") (pintype "passive"))
    )
    (net (code "390") (name "Net-(R158-Pad2)") (class "Default")
      (node (ref "R158") (pin "2") (pinfunction "2_2") (pintype "passive"))
      (node (ref "VD86") (pin "C") (pinfunction "C_C") (pintype "passive"))
    )
    (net (code "391") (name "Net-(R159-Pad2)") (class "Default")
      (node (ref "R159") (pin "2") (pinfunction "2_2") (pintype "passive"))
      (node (ref "VD87") (pin "C") (pinfunction "C_C") (pintype "passive"))
    )
    (net (code "392") (name "Net-(R160-Pad2)") (class "Default")
      (node (ref "R160") (pin "2") (pinfunction "2_2") (pintype "passive"))
      (node (ref "VD88") (pin "C") (pinfunction "C_C") (pintype "passive"))
    )
    (net (code "393") (name "Net-(R161-Pad2)") (class "Default")
      (node (ref "R161") (pin "2") (pinfunction "2_2") (pintype "passive"))
      (node (ref "VD89") (pin "C") (pinfunction "C_C") (pintype "passive"))
    )
    (net (code "394") (name "Net-(R162-Pad2)") (class "Default")
      (node (ref "R162") (pin "2") (pinfunction "2_2") (pintype "passive"))
      (node (ref "VD90") (pin "C") (pinfunction "C_C") (pintype "passive"))
    )
    (net (code "395") (name "Net-(R163-Pad2)") (class "Default")
      (node (ref "R163") (pin "2") (pinfunction "2_2") (pintype "passive"))
      (node (ref "VD91") (pin "C") (pinfunction "C_C") (pintype "passive"))
    )
    (net (code "396") (name "Net-(R164-Pad2)") (class "Default")
      (node (ref "R164") (pin "2") (pinfunction "2_2") (pintype "passive"))
      (node (ref "VD92") (pin "C") (pinfunction "C_C") (pintype "passive"))
    )
    (net (code "397") (name "Net-(R165-Pad2)") (class "Default")
      (node (ref "R165") (pin "2") (pinfunction "2_2") (pintype "passive"))
      (node (ref "VD93") (pin "C") (pinfunction "C_C") (pintype "passive"))
    )
    (net (code "398") (name "Net-(R166-Pad2)") (class "Default")
      (node (ref "R166") (pin "2") (pinfunction "2_2") (pintype "passive"))
      (node (ref "VD94") (pin "C") (pinfunction "C_C") (pintype "passive"))
    )
    (net (code "399") (name "Net-(R167-Pad2)") (class "Default")
      (node (ref "R167") (pin "2") (pinfunction "2_2") (pintype "passive"))
      (node (ref "VD95") (pin "C") (pinfunction "C_C") (pintype "passive"))
    )
    (net (code "400") (name "Net-(R168-Pad2)") (class "Default")
      (node (ref "R168") (pin "2") (pinfunction "2_2") (pintype "passive"))
      (node (ref "VD96") (pin "C") (pinfunction "C_C") (pintype "passive"))
    )
    (net (code "401") (name "Net-(R169-Pad2)") (class "Default")
      (node (ref "R169") (pin "2") (pinfunction "2_2") (pintype "passive"))
      (node (ref "VD97") (pin "C") (pinfunction "C_C") (pintype "passive"))
    )
    (net (code "402") (name "Net-(R186-Pad1)") (class "Default")
      (node (ref "R186") (pin "1") (pinfunction "1_1") (pintype "passive"))
      (node (ref "VD99") (pin "C") (pinfunction "C_C") (pintype "passive"))
      (node (ref "VT2") (pin "C") (pinfunction "C_C") (pintype "passive"))
    )
    (net (code "403") (name "Net-(R187-Pad2)") (class "Default")
      (node (ref "R187") (pin "2") (pinfunction "2_2") (pintype "passive"))
      (node (ref "VD98") (pin "C") (pinfunction "C_C") (pintype "passive"))
    )
    (net (code "404") (name "Net-(R205-Pad2)") (class "Default")
      (node (ref "R205") (pin "2") (pinfunction "2_2") (pintype "passive"))
      (node (ref "VD116") (pin "C") (pinfunction "C_C") (pintype "passive"))
    )
    (net (code "405") (name "Net-(R206-Pad2)") (class "Default")
      (node (ref "R206") (pin "2") (pinfunction "2_2") (pintype "passive"))
      (node (ref "VD117") (pin "C") (pinfunction "C_C") (pintype "passive"))
    )
    (net (code "406") (name "Net-(R207-Pad2)") (class "Default")
      (node (ref "R207") (pin "2") (pinfunction "2_2") (pintype "passive"))
      (node (ref "VD118") (pin "C") (pinfunction "C_C") (pintype "passive"))
    )
    (net (code "407") (name "Net-(R208-Pad2)") (class "Default")
      (node (ref "R208") (pin "2") (pinfunction "2_2") (pintype "passive"))
      (node (ref "VD119") (pin "C") (pinfunction "C_C") (pintype "passive"))
    )
    (net (code "408") (name "Net-(R209-Pad2)") (class "Default")
      (node (ref "R209") (pin "2") (pinfunction "2_2") (pintype "passive"))
      (node (ref "VD120") (pin "C") (pinfunction "C_C") (pintype "passive"))
    )
    (net (code "409") (name "Net-(R210-Pad2)") (class "Default")
      (node (ref "R210") (pin "2") (pinfunction "2_2") (pintype "passive"))
      (node (ref "VD121") (pin "C") (pinfunction "C_C") (pintype "passive"))
    )
    (net (code "410") (name "Net-(R211-Pad2)") (class "Default")
      (node (ref "R211") (pin "2") (pinfunction "2_2") (pintype "passive"))
      (node (ref "VD122") (pin "C") (pinfunction "C_C") (pintype "passive"))
    )
    (net (code "411") (name "Net-(R212-Pad2)") (class "Default")
      (node (ref "R212") (pin "2") (pinfunction "2_2") (pintype "passive"))
      (node (ref "VD123") (pin "C") (pinfunction "C_C") (pintype "passive"))
    )
    (net (code "412") (name "Net-(R213-Pad2)") (class "Default")
      (node (ref "R213") (pin "2") (pinfunction "2_2") (pintype "passive"))
      (node (ref "VD124") (pin "C") (pinfunction "C_C") (pintype "passive"))
    )
    (net (code "413") (name "Net-(R214-Pad2)") (class "Default")
      (node (ref "R214") (pin "2") (pinfunction "2_2") (pintype "passive"))
      (node (ref "VD125") (pin "C") (pinfunction "C_C") (pintype "passive"))
    )
    (net (code "414") (name "Net-(R215-Pad2)") (class "Default")
      (node (ref "R215") (pin "2") (pinfunction "2_2") (pintype "passive"))
      (node (ref "VD126") (pin "C") (pinfunction "C_C") (pintype "passive"))
    )
    (net (code "415") (name "Net-(R216-Pad2)") (class "Default")
      (node (ref "R216") (pin "2") (pinfunction "2_2") (pintype "passive"))
      (node (ref "VD127") (pin "C") (pinfunction "C_C") (pintype "passive"))
    )
    (net (code "416") (name "Net-(R217-Pad2)") (class "Default")
      (node (ref "R217") (pin "2") (pinfunction "2_2") (pintype "passive"))
      (node (ref "VD128") (pin "C") (pinfunction "C_C") (pintype "passive"))
    )
    (net (code "417") (name "Net-(R218-Pad2)") (class "Default")
      (node (ref "R218") (pin "2") (pinfunction "2_2") (pintype "passive"))
      (node (ref "VD129") (pin "C") (pinfunction "C_C") (pintype "passive"))
    )
    (net (code "418") (name "Net-(R219-Pad2)") (class "Default")
      (node (ref "R219") (pin "2") (pinfunction "2_2") (pintype "passive"))
      (node (ref "VD130") (pin "C") (pinfunction "C_C") (pintype "passive"))
    )
    (net (code "419") (name "Net-(R220-Pad2)") (class "Default")
      (node (ref "R220") (pin "2") (pinfunction "2_2") (pintype "passive"))
      (node (ref "VD131") (pin "C") (pinfunction "C_C") (pintype "passive"))
    )
    (net (code "420") (name "Net-(R253-Pad2)") (class "Default")
      (node (ref "R253") (pin "2") (pinfunction "2_2") (pintype "passive"))
      (node (ref "VD148") (pin "C") (pinfunction "C_C") (pintype "passive"))
    )
    (net (code "421") (name "Net-(R254-Pad2)") (class "Default")
      (node (ref "R254") (pin "2") (pinfunction "2_2") (pintype "passive"))
      (node (ref "VD149") (pin "C") (pinfunction "C_C") (pintype "passive"))
    )
    (net (code "422") (name "Net-(R255-Pad2)") (class "Default")
      (node (ref "R255") (pin "2") (pinfunction "2_2") (pintype "passive"))
      (node (ref "VD150") (pin "C") (pinfunction "C_C") (pintype "passive"))
    )
    (net (code "423") (name "Net-(R256-Pad2)") (class "Default")
      (node (ref "R256") (pin "2") (pinfunction "2_2") (pintype "passive"))
      (node (ref "VD151") (pin "C") (pinfunction "C_C") (pintype "passive"))
    )
    (net (code "424") (name "Net-(R257-Pad2)") (class "Default")
      (node (ref "R257") (pin "2") (pinfunction "2_2") (pintype "passive"))
      (node (ref "VD152") (pin "C") (pinfunction "C_C") (pintype "passive"))
    )
    (net (code "425") (name "Net-(R258-Pad2)") (class "Default")
      (node (ref "R258") (pin "2") (pinfunction "2_2") (pintype "passive"))
      (node (ref "VD153") (pin "C") (pinfunction "C_C") (pintype "passive"))
    )
    (net (code "426") (name "Net-(R259-Pad2)") (class "Default")
      (node (ref "R259") (pin "2") (pinfunction "2_2") (pintype "passive"))
      (node (ref "VD154") (pin "C") (pinfunction "C_C") (pintype "passive"))
    )
    (net (code "427") (name "Net-(R260-Pad2)") (class "Default")
      (node (ref "R260") (pin "2") (pinfunction "2_2") (pintype "passive"))
      (node (ref "VD155") (pin "C") (pinfunction "C_C") (pintype "passive"))
    )
    (net (code "428") (name "Net-(R261-Pad2)") (class "Default")
      (node (ref "R261") (pin "2") (pinfunction "2_2") (pintype "passive"))
      (node (ref "VD156") (pin "C") (pinfunction "C_C") (pintype "passive"))
    )
    (net (code "429") (name "Net-(R262-Pad2)") (class "Default")
      (node (ref "R262") (pin "2") (pinfunction "2_2") (pintype "passive"))
      (node (ref "VD157") (pin "C") (pinfunction "C_C") (pintype "passive"))
    )
    (net (code "430") (name "Net-(R263-Pad2)") (class "Default")
      (node (ref "R263") (pin "2") (pinfunction "2_2") (pintype "passive"))
      (node (ref "VD158") (pin "C") (pinfunction "C_C") (pintype "passive"))
    )
    (net (code "431") (name "Net-(R264-Pad2)") (class "Default")
      (node (ref "R264") (pin "2") (pinfunction "2_2") (pintype "passive"))
      (node (ref "VD159") (pin "C") (pinfunction "C_C") (pintype "passive"))
    )
    (net (code "432") (name "Net-(R265-Pad2)") (class "Default")
      (node (ref "R265") (pin "2") (pinfunction "2_2") (pintype "passive"))
      (node (ref "VD160") (pin "C") (pinfunction "C_C") (pintype "passive"))
    )
    (net (code "433") (name "Net-(R266-Pad2)") (class "Default")
      (node (ref "R266") (pin "2") (pinfunction "2_2") (pintype "passive"))
      (node (ref "VD161") (pin "C") (pinfunction "C_C") (pintype "passive"))
    )
    (net (code "434") (name "Net-(R267-Pad2)") (class "Default")
      (node (ref "R267") (pin "2") (pinfunction "2_2") (pintype "passive"))
      (node (ref "VD162") (pin "C") (pinfunction "C_C") (pintype "passive"))
    )
    (net (code "435") (name "Net-(R268-Pad2)") (class "Default")
      (node (ref "R268") (pin "2") (pinfunction "2_2") (pintype "passive"))
      (node (ref "VD163") (pin "C") (pinfunction "C_C") (pintype "passive"))
    )
    (net (code "436") (name "Net-(R301-Pad2)") (class "Default")
      (node (ref "R301") (pin "2") (pinfunction "2_2") (pintype "passive"))
      (node (ref "VD180") (pin "C") (pinfunction "C_C") (pintype "passive"))
    )
    (net (code "437") (name "Net-(R302-Pad2)") (class "Default")
      (node (ref "R302") (pin "2") (pinfunction "2_2") (pintype "passive"))
      (node (ref "VD181") (pin "C") (pinfunction "C_C") (pintype "passive"))
    )
    (net (code "438") (name "Net-(R303-Pad2)") (class "Default")
      (node (ref "R303") (pin "2") (pinfunction "2_2") (pintype "passive"))
      (node (ref "VD182") (pin "C") (pinfunction "C_C") (pintype "passive"))
    )
    (net (code "439") (name "Net-(R304-Pad2)") (class "Default")
      (node (ref "R304") (pin "2") (pinfunction "2_2") (pintype "passive"))
      (node (ref "VD183") (pin "C") (pinfunction "C_C") (pintype "passive"))
    )
    (net (code "440") (name "Net-(R305-Pad2)") (class "Default")
      (node (ref "R305") (pin "2") (pinfunction "2_2") (pintype "passive"))
      (node (ref "VD184") (pin "C") (pinfunction "C_C") (pintype "passive"))
    )
    (net (code "441") (name "Net-(R306-Pad2)") (class "Default")
      (node (ref "R306") (pin "2") (pinfunction "2_2") (pintype "passive"))
      (node (ref "VD185") (pin "C") (pinfunction "C_C") (pintype "passive"))
    )
    (net (code "442") (name "Net-(R307-Pad2)") (class "Default")
      (node (ref "R307") (pin "2") (pinfunction "2_2") (pintype "passive"))
      (node (ref "VD186") (pin "C") (pinfunction "C_C") (pintype "passive"))
    )
    (net (code "443") (name "Net-(R308-Pad2)") (class "Default")
      (node (ref "R308") (pin "2") (pinfunction "2_2") (pintype "passive"))
      (node (ref "VD187") (pin "C") (pinfunction "C_C") (pintype "passive"))
    )
    (net (code "444") (name "Net-(R309-Pad2)") (class "Default")
      (node (ref "R309") (pin "2") (pinfunction "2_2") (pintype "passive"))
      (node (ref "VD188") (pin "C") (pinfunction "C_C") (pintype "passive"))
    )
    (net (code "445") (name "Net-(R310-Pad2)") (class "Default")
      (node (ref "R310") (pin "2") (pinfunction "2_2") (pintype "passive"))
      (node (ref "VD189") (pin "C") (pinfunction "C_C") (pintype "passive"))
    )
    (net (code "446") (name "Net-(R311-Pad2)") (class "Default")
      (node (ref "R311") (pin "2") (pinfunction "2_2") (pintype "passive"))
      (node (ref "VD190") (pin "C") (pinfunction "C_C") (pintype "passive"))
    )
    (net (code "447") (name "Net-(R312-Pad2)") (class "Default")
      (node (ref "R312") (pin "2") (pinfunction "2_2") (pintype "passive"))
      (node (ref "VD191") (pin "C") (pinfunction "C_C") (pintype "passive"))
    )
    (net (code "448") (name "Net-(R313-Pad2)") (class "Default")
      (node (ref "R313") (pin "2") (pinfunction "2_2") (pintype "passive"))
      (node (ref "VD192") (pin "C") (pinfunction "C_C") (pintype "passive"))
    )
    (net (code "449") (name "Net-(R314-Pad2)") (class "Default")
      (node (ref "R314") (pin "2") (pinfunction "2_2") (pintype "passive"))
      (node (ref "VD193") (pin "C") (pinfunction "C_C") (pintype "passive"))
    )
    (net (code "450") (name "Net-(R315-Pad2)") (class "Default")
      (node (ref "R315") (pin "2") (pinfunction "2_2") (pintype "passive"))
      (node (ref "VD194") (pin "C") (pinfunction "C_C") (pintype "passive"))
    )
    (net (code "451") (name "Net-(R316-Pad2)") (class "Default")
      (node (ref "R316") (pin "2") (pinfunction "2_2") (pintype "passive"))
      (node (ref "VD195") (pin "C") (pinfunction "C_C") (pintype "passive"))
    )
    (net (code "452") (name "Net-(R342-Pad2)") (class "Default")
      (node (ref "R342") (pin "2") (pinfunction "2_2") (pintype "passive"))
      (node (ref "VD204") (pin "C") (pinfunction "C_C") (pintype "passive"))
    )
    (net (code "453") (name "Net-(R343-Pad2)") (class "Default")
      (node (ref "R343") (pin "2") (pinfunction "2_2") (pintype "passive"))
      (node (ref "VD205") (pin "C") (pinfunction "C_C") (pintype "passive"))
    )
    (net (code "454") (name "Net-(R344-Pad2)") (class "Default")
      (node (ref "R344") (pin "2") (pinfunction "2_2") (pintype "passive"))
      (node (ref "VD206") (pin "C") (pinfunction "C_C") (pintype "passive"))
    )
    (net (code "455") (name "Net-(R345-Pad2)") (class "Default")
      (node (ref "R345") (pin "2") (pinfunction "2_2") (pintype "passive"))
      (node (ref "VD207") (pin "C") (pinfunction "C_C") (pintype "passive"))
    )
    (net (code "456") (name "Net-(R346-Pad2)") (class "Default")
      (node (ref "R346") (pin "2") (pinfunction "2_2") (pintype "passive"))
      (node (ref "VD208") (pin "C") (pinfunction "C_C") (pintype "passive"))
    )
    (net (code "457") (name "Net-(R347-Pad2)") (class "Default")
      (node (ref "R347") (pin "2") (pinfunction "2_2") (pintype "passive"))
      (node (ref "VD209") (pin "C") (pinfunction "C_C") (pintype "passive"))
    )
    (net (code "458") (name "Net-(R348-Pad2)") (class "Default")
      (node (ref "R348") (pin "2") (pinfunction "2_2") (pintype "passive"))
      (node (ref "VD210") (pin "C") (pinfunction "C_C") (pintype "passive"))
    )
    (net (code "459") (name "Net-(R349-Pad2)") (class "Default")
      (node (ref "R349") (pin "2") (pinfunction "2_2") (pintype "passive"))
      (node (ref "VD211") (pin "C") (pinfunction "C_C") (pintype "passive"))
    )
    (net (code "460") (name "Net-(R358-Pad1)") (class "Default")
      (node (ref "R358") (pin "1") (pinfunction "1_1") (pintype "passive"))
      (node (ref "XP13") (pin "2") (pinfunction "2_2") (pintype "passive"))
    )
    (net (code "461") (name "Net-(R359-Pad1)") (class "Default")
      (node (ref "R359") (pin "1") (pinfunction "1_1") (pintype "passive"))
      (node (ref "R360") (pin "2") (pinfunction "2_2") (pintype "passive"))
      (node (ref "VT4") (pin "C") (pinfunction "C_C") (pintype "passive"))
    )
    (net (code "462") (name "Net-(R361-Pad1)") (class "Default")
      (node (ref "R361") (pin "1") (pinfunction "1_1") (pintype "passive"))
      (node (ref "R363") (pin "1") (pinfunction "1_1") (pintype "passive"))
      (node (ref "VD214") (pin "C") (pinfunction "C_C") (pintype "passive"))
    )
    (net (code "463") (name "Net-(R362-Pad1)") (class "Default")
      (node (ref "R362") (pin "1") (pinfunction "1_1") (pintype "passive"))
      (node (ref "R364") (pin "1") (pinfunction "1_1") (pintype "passive"))
      (node (ref "VT4") (pin "B") (pinfunction "B_B") (pintype "passive"))
    )
    (net (code "464") (name "Net-(R363-Pad2)") (class "Default")
      (node (ref "R363") (pin "2") (pinfunction "2_2") (pintype "passive"))
      (node (ref "Z48") (pin "1") (pinfunction "1_1") (pintype "passive"))
    )
    (net (code "465") (name "Net-(R364-Pad2)") (class "Default")
      (node (ref "R364") (pin "2") (pinfunction "2_2") (pintype "passive"))
      (node (ref "Z49") (pin "1") (pinfunction "1_1") (pintype "passive"))
    )
    (net (code "466") (name "Net-(RK1-P$1)") (class "Default")
      (node (ref "RK1") (pin "1") (pinfunction "P$1_1") (pintype "passive"))
      (node (ref "VD56") (pin "C") (pinfunction "C_C") (pintype "passive"))
    )
    (net (code "467") (name "Net-(VD36-PadC)") (class "Default")
      (node (ref "VD36") (pin "C") (pinfunction "C_C") (pintype "passive"))
      (node (ref "VD37") (pin "C") (pinfunction "C_C") (pintype "passive"))
    )
    (net (code "468") (name "Net-(VD38-PadC)") (class "Default")
      (node (ref "VD38") (pin "C") (pinfunction "C_C") (pintype "passive"))
      (node (ref "VD39") (pin "C") (pinfunction "C_C") (pintype "passive"))
    )
    (net (code "469") (name "Net-(VD40-PadC)") (class "Default")
      (node (ref "VD40") (pin "C") (pinfunction "C_C") (pintype "passive"))
      (node (ref "VD41") (pin "C") (pinfunction "C_C") (pintype "passive"))
    )
    (net (code "470") (name "Net-(VD42-PadC)") (class "Default")
      (node (ref "VD42") (pin "C") (pinfunction "C_C") (pintype "passive"))
      (node (ref "VD43") (pin "C") (pinfunction "C_C") (pintype "passive"))
    )
    (net (code "471") (name "Net-(VD44-PadC)") (class "Default")
      (node (ref "VD44") (pin "C") (pinfunction "C_C") (pintype "passive"))
      (node (ref "VD45") (pin "C") (pinfunction "C_C") (pintype "passive"))
    )
    (net (code "472") (name "Net-(VD46-PadC)") (class "Default")
      (node (ref "VD46") (pin "C") (pinfunction "C_C") (pintype "passive"))
      (node (ref "VD47") (pin "C") (pinfunction "C_C") (pintype "passive"))
    )
    (net (code "473") (name "Net-(VD53-PadA1)") (class "Default")
      (node (ref "VD53") (pin "A1") (pinfunction "A1_A1") (pintype "passive"))
      (node (ref "VD54") (pin "A2") (pinfunction "A2_A2") (pintype "passive"))
    )
    (net (code "474") (name "Net-(VD61-C)") (class "Default")
      (node (ref "R131") (pin "1") (pinfunction "1_1") (pintype "passive"))
      (node (ref "R132") (pin "1") (pinfunction "1_1") (pintype "passive"))
      (node (ref "R135") (pin "2") (pinfunction "2_2") (pintype "passive"))
      (node (ref "VD61") (pin "2") (pinfunction "C_2") (pintype "passive"))
      (node (ref "VT1") (pin "2") (pinfunction "D_2") (pintype "passive"))
    )
    (net (code "475") (name "Net-(VD62-PadA2)") (class "Default")
      (node (ref "VD62") (pin "A2") (pinfunction "A2_A2") (pintype "passive"))
      (node (ref "VD63") (pin "C") (pinfunction "C_C") (pintype "passive"))
    )
    (net (code "476") (name "Net-(VD212-PadA2)") (class "Default")
      (node (ref "VD212") (pin "A2") (pinfunction "A2_A2") (pintype "passive"))
      (node (ref "XP12") (pin "4") (pinfunction "4_4") (pintype "passive"))
      (node (ref "Z45") (pin "1") (pinfunction "1_1") (pintype "passive"))
    )
    (net (code "477") (name "Net-(VD213-PadA2)") (class "Default")
      (node (ref "VD213") (pin "A2") (pinfunction "A2_A2") (pintype "passive"))
      (node (ref "XP12") (pin "3") (pinfunction "3_3") (pintype "passive"))
      (node (ref "Z46") (pin "1") (pinfunction "1_1") (pintype "passive"))
    )
    (net (code "478") (name "Net-(VT1-S)") (class "Default")
      (node (ref "R134") (pin "2") (pinfunction "2_2") (pintype "passive"))
      (node (ref "VD57") (pin "A1") (pinfunction "A1_A1") (pintype "passive"))
      (node (ref "VT1") (pin "3") (pinfunction "S_3") (pintype "passive"))
      (node (ref "Z41") (pin "1") (pinfunction "1_1") (pintype "passive"))
    )
    (net (code "479") (name "Net-(VT3-PadE)") (class "Default")
      (node (ref "VT3") (pin "E") (pinfunction "E_E") (pintype "passive"))
      (node (ref "Z44") (pin "3") (pinfunction "3_3") (pintype "passive"))
    )
    (net (code "480") (name "Net-(XS1-1)") (class "Default")
      (node (ref "L4") (pin "1") (pinfunction "1_1") (pintype "passive"))
      (node (ref "XS1") (pin "VBUS") (pinfunction "1_VBUS") (pintype "passive"))
    )
    (net (code "481") (name "Net-(XS1-2)") (class "Default")
      (node (ref "XS1") (pin "D-") (pinfunction "2_D-") (pintype "passive"))
      (node (ref "Z43") (pin "3") (pinfunction "3_3") (pintype "passive"))
    )
    (net (code "482") (name "Net-(XS1-3)") (class "Default")
      (node (ref "XS1") (pin "D+") (pinfunction "3_D+") (pintype "passive"))
      (node (ref "Z42") (pin "3") (pinfunction "3_3") (pintype "passive"))
    )
    (net (code "483") (name "OUT_DRV1") (class "Default")
      (node (ref "D20") (pin "4") (pinfunction "OUT1_4") (pintype "power_in"))
      (node (ref "D20") (pin "5") (pinfunction "OUT2_5") (pintype "power_in"))
      (node (ref "XP11") (pin "1") (pinfunction "1_1") (pintype "passive"))
      (node (ref "XP11") (pin "4") (pinfunction "4_4") (pintype "passive"))
    )
    (net (code "484") (name "OUT_DRV2") (class "Default")
      (node (ref "D21") (pin "4") (pinfunction "OUT1_4") (pintype "power_in"))
      (node (ref "D21") (pin "5") (pinfunction "OUT2_5") (pintype "power_in"))
      (node (ref "XP11") (pin "5") (pinfunction "5_5") (pintype "passive"))
      (node (ref "XP11") (pin "8") (pinfunction "8_8") (pintype "passive"))
    )
    (net (code "485") (name "OUT_DRV3") (class "Default")
      (node (ref "D22") (pin "4") (pinfunction "OUT1_4") (pintype "power_in"))
      (node (ref "D22") (pin "5") (pinfunction "OUT2_5") (pintype "power_in"))
      (node (ref "XP11") (pin "12") (pinfunction "12_12") (pintype "passive"))
      (node (ref "XP11") (pin "9") (pinfunction "9_9") (pintype "passive"))
    )
    (net (code "486") (name "OUT_DRV4") (class "Default")
      (node (ref "D23") (pin "4") (pinfunction "OUT1_4") (pintype "power_in"))
      (node (ref "D23") (pin "5") (pinfunction "OUT2_5") (pintype "power_in"))
      (node (ref "XP11") (pin "13") (pinfunction "13_13") (pintype "passive"))
      (node (ref "XP11") (pin "16") (pinfunction "16_16") (pintype "passive"))
    )
    (net (code "487") (name "OUT_DRV5") (class "Default")
      (node (ref "D24") (pin "4") (pinfunction "OUT1_4") (pintype "power_in"))
      (node (ref "D24") (pin "5") (pinfunction "OUT2_5") (pintype "power_in"))
      (node (ref "XP11") (pin "17") (pinfunction "17_17") (pintype "passive"))
      (node (ref "XP11") (pin "20") (pinfunction "20_20") (pintype "passive"))
    )
    (net (code "488") (name "OUT_DRV6") (class "Default")
      (node (ref "D25") (pin "4") (pinfunction "OUT1_4") (pintype "power_in"))
      (node (ref "D25") (pin "5") (pinfunction "OUT2_5") (pintype "power_in"))
      (node (ref "XP11") (pin "21") (pinfunction "21_21") (pintype "passive"))
      (node (ref "XP11") (pin "24") (pinfunction "24_24") (pintype "passive"))
    )
    (net (code "489") (name "OUT_DRV7") (class "Default")
      (node (ref "D26") (pin "4") (pinfunction "OUT1_4") (pintype "power_in"))
      (node (ref "D26") (pin "5") (pinfunction "OUT2_5") (pintype "power_in"))
      (node (ref "XP11") (pin "25") (pinfunction "25_25") (pintype "passive"))
      (node (ref "XP11") (pin "28") (pinfunction "28_28") (pintype "passive"))
    )
    (net (code "490") (name "OUT_DRV8") (class "Default")
      (node (ref "D27") (pin "4") (pinfunction "OUT1_4") (pintype "power_in"))
      (node (ref "D27") (pin "5") (pinfunction "OUT2_5") (pintype "power_in"))
      (node (ref "XP11") (pin "29") (pinfunction "29_29") (pintype "passive"))
      (node (ref "XP11") (pin "32") (pinfunction "32_32") (pintype "passive"))
    )
    (net (code "491") (name "PHASE_1") (class "Default")
      (node (ref "R74") (pin "2") (pinfunction "2_2") (pintype "passive"))
      (node (ref "R77") (pin "1") (pinfunction "1_1") (pintype "passive"))
      (node (ref "R80") (pin "1") (pinfunction "1_1") (pintype "passive"))
      (node (ref "XP5") (pin "2") (pinfunction "2_2") (pintype "passive"))
    )
    (net (code "492") (name "PHASE_2") (class "Default")
      (node (ref "R75") (pin "2") (pinfunction "2_2") (pintype "passive"))
      (node (ref "R78") (pin "1") (pinfunction "1_1") (pintype "passive"))
      (node (ref "R81") (pin "1") (pinfunction "1_1") (pintype "passive"))
      (node (ref "XP5") (pin "4") (pinfunction "4_4") (pintype "passive"))
    )
    (net (code "493") (name "PHASE_3") (class "Default")
      (node (ref "R76") (pin "2") (pinfunction "2_2") (pintype "passive"))
      (node (ref "R79") (pin "1") (pinfunction "1_1") (pintype "passive"))
      (node (ref "R82") (pin "1") (pinfunction "1_1") (pintype "passive"))
      (node (ref "XP5") (pin "6") (pinfunction "6_6") (pintype "passive"))
    )
    (net (code "494") (name "REL_RAW_1") (class "Default")
      (node (ref "R138") (pin "1") (pinfunction "1_1") (pintype "passive"))
      (node (ref "R154") (pin "1") (pinfunction "1_1") (pintype "passive"))
      (node (ref "VD66") (pin "C") (pinfunction "C_C") (pintype "passive"))
      (node (ref "XP7") (pin "1") (pinfunction "1_1") (pintype "passive"))
    )
    (net (code "495") (name "REL_RAW_2") (class "Default")
      (node (ref "R139") (pin "1") (pinfunction "1_1") (pintype "passive"))
      (node (ref "R155") (pin "1") (pinfunction "1_1") (pintype "passive"))
      (node (ref "VD67") (pin "C") (pinfunction "C_C") (pintype "passive"))
      (node (ref "XP7") (pin "2") (pinfunction "2_2") (pintype "passive"))
    )
    (net (code "496") (name "REL_RAW_3") (class "Default")
      (node (ref "R140") (pin "1") (pinfunction "1_1") (pintype "passive"))
      (node (ref "R156") (pin "1") (pinfunction "1_1") (pintype "passive"))
      (node (ref "VD68") (pin "C") (pinfunction "C_C") (pintype "passive"))
      (node (ref "XP7") (pin "3") (pinfunction "3_3") (pintype "passive"))
    )
    (net (code "497") (name "REL_RAW_4") (class "Default")
      (node (ref "R141") (pin "1") (pinfunction "1_1") (pintype "passive"))
      (node (ref "R157") (pin "1") (pinfunction "1_1") (pintype "passive"))
      (node (ref "VD69") (pin "C") (pinfunction "C_C") (pintype "passive"))
      (node (ref "XP7") (pin "4") (pinfunction "4_4") (pintype "passive"))
    )
    (net (code "498") (name "REL_RAW_5") (class "Default")
      (node (ref "R142") (pin "1") (pinfunction "1_1") (pintype "passive"))
      (node (ref "R158") (pin "1") (pinfunction "1_1") (pintype "passive"))
      (node (ref "VD70") (pin "C") (pinfunction "C_C") (pintype "passive"))
      (node (ref "XP7") (pin "5") (pinfunction "5_5") (pintype "passive"))
    )
    (net (code "499") (name "REL_RAW_6") (class "Default")
      (node (ref "R143") (pin "1") (pinfunction "1_1") (pintype "passive"))
      (node (ref "R159") (pin "1") (pinfunction "1_1") (pintype "passive"))
      (node (ref "VD71") (pin "C") (pinfunction "C_C") (pintype "passive"))
      (node (ref "XP7") (pin "6") (pinfunction "6_6") (pintype "passive"))
    )
    (net (code "500") (name "REL_RAW_7") (class "Default")
      (node (ref "R144") (pin "1") (pinfunction "1_1") (pintype "passive"))
      (node (ref "R160") (pin "1") (pinfunction "1_1") (pintype "passive"))
      (node (ref "VD72") (pin "C") (pinfunction "C_C") (pintype "passive"))
      (node (ref "XP7") (pin "7") (pinfunction "7_7") (pintype "passive"))
    )
    (net (code "501") (name "REL_RAW_8") (class "Default")
      (node (ref "R145") (pin "1") (pinfunction "1_1") (pintype "passive"))
      (node (ref "R161") (pin "1") (pinfunction "1_1") (pintype "passive"))
      (node (ref "VD73") (pin "C") (pinfunction "C_C") (pintype "passive"))
      (node (ref "XP7") (pin "8") (pinfunction "8_8") (pintype "passive"))
    )
    (net (code "502") (name "REL_RAW_9") (class "Default")
      (node (ref "R146") (pin "1") (pinfunction "1_1") (pintype "passive"))
      (node (ref "R162") (pin "1") (pinfunction "1_1") (pintype "passive"))
      (node (ref "VD74") (pin "C") (pinfunction "C_C") (pintype "passive"))
      (node (ref "XP7") (pin "9") (pinfunction "9_9") (pintype "passive"))
    )
    (net (code "503") (name "REL_RAW_10") (class "Default")
      (node (ref "R147") (pin "1") (pinfunction "1_1") (pintype "passive"))
      (node (ref "R163") (pin "1") (pinfunction "1_1") (pintype "passive"))
      (node (ref "VD75") (pin "C") (pinfunction "C_C") (pintype "passive"))
      (node (ref "XP7") (pin "10") (pinfunction "10_10") (pintype "passive"))
    )
    (net (code "504") (name "REL_RAW_11") (class "Default")
      (node (ref "R148") (pin "1") (pinfunction "1_1") (pintype "passive"))
      (node (ref "R164") (pin "1") (pinfunction "1_1") (pintype "passive"))
      (node (ref "VD76") (pin "C") (pinfunction "C_C") (pintype "passive"))
      (node (ref "XP7") (pin "11") (pinfunction "11_11") (pintype "passive"))
    )
    (net (code "505") (name "REL_RAW_12") (class "Default")
      (node (ref "R149") (pin "1") (pinfunction "1_1") (pintype "passive"))
      (node (ref "R165") (pin "1") (pinfunction "1_1") (pintype "passive"))
      (node (ref "VD77") (pin "C") (pinfunction "C_C") (pintype "passive"))
      (node (ref "XP7") (pin "12") (pinfunction "12_12") (pintype "passive"))
    )
    (net (code "506") (name "REL_RAW_13") (class "Default")
      (node (ref "R150") (pin "1") (pinfunction "1_1") (pintype "passive"))
      (node (ref "R166") (pin "1") (pinfunction "1_1") (pintype "passive"))
      (node (ref "VD78") (pin "C") (pinfunction "C_C") (pintype "passive"))
      (node (ref "XP7") (pin "13") (pinfunction "13_13") (pintype "passive"))
    )
    (net (code "507") (name "REL_RAW_14") (class "Default")
      (node (ref "R151") (pin "1") (pinfunction "1_1") (pintype "passive"))
      (node (ref "R167") (pin "1") (pinfunction "1_1") (pintype "passive"))
      (node (ref "VD79") (pin "C") (pinfunction "C_C") (pintype "passive"))
      (node (ref "XP7") (pin "14") (pinfunction "14_14") (pintype "passive"))
    )
    (net (code "508") (name "REL_RAW_15") (class "Default")
      (node (ref "R152") (pin "1") (pinfunction "1_1") (pintype "passive"))
      (node (ref "R168") (pin "1") (pinfunction "1_1") (pintype "passive"))
      (node (ref "VD80") (pin "C") (pinfunction "C_C") (pintype "passive"))
      (node (ref "XP7") (pin "15") (pinfunction "15_15") (pintype "passive"))
    )
    (net (code "509") (name "REL_RAW_16") (class "Default")
      (node (ref "R153") (pin "1") (pinfunction "1_1") (pintype "passive"))
      (node (ref "R169") (pin "1") (pinfunction "1_1") (pintype "passive"))
      (node (ref "VD81") (pin "C") (pinfunction "C_C") (pintype "passive"))
      (node (ref "XP7") (pin "16") (pinfunction "16_16") (pintype "passive"))
    )
    (net (code "510") (name "REL_RAW_17") (class "Default")
      (node (ref "R189") (pin "1") (pinfunction "1_1") (pintype "passive"))
      (node (ref "R205") (pin "1") (pinfunction "1_1") (pintype "passive"))
      (node (ref "VD100") (pin "C") (pinfunction "C_C") (pintype "passive"))
      (node (ref "XP8") (pin "1") (pinfunction "1_1") (pintype "passive"))
    )
    (net (code "511") (name "REL_RAW_18") (class "Default")
      (node (ref "R190") (pin "1") (pinfunction "1_1") (pintype "passive"))
      (node (ref "R206") (pin "1") (pinfunction "1_1") (pintype "passive"))
      (node (ref "VD101") (pin "C") (pinfunction "C_C") (pintype "passive"))
      (node (ref "XP8") (pin "2") (pinfunction "2_2") (pintype "passive"))
    )
    (net (code "512") (name "REL_RAW_19") (class "Default")
      (node (ref "R191") (pin "1") (pinfunction "1_1") (pintype "passive"))
      (node (ref "R207") (pin "1") (pinfunction "1_1") (pintype "passive"))
      (node (ref "VD102") (pin "C") (pinfunction "C_C") (pintype "passive"))
      (node (ref "XP8") (pin "3") (pinfunction "3_3") (pintype "passive"))
    )
    (net (code "513") (name "REL_RAW_20") (class "Default")
      (node (ref "R192") (pin "1") (pinfunction "1_1") (pintype "passive"))
      (node (ref "R208") (pin "1") (pinfunction "1_1") (pintype "passive"))
      (node (ref "VD103") (pin "C") (pinfunction "C_C") (pintype "passive"))
      (node (ref "XP8") (pin "4") (pinfunction "4_4") (pintype "passive"))
    )
    (net (code "514") (name "REL_RAW_21") (class "Default")
      (node (ref "R193") (pin "1") (pinfunction "1_1") (pintype "passive"))
      (node (ref "R209") (pin "1") (pinfunction "1_1") (pintype "passive"))
      (node (ref "VD104") (pin "C") (pinfunction "C_C") (pintype "passive"))
      (node (ref "XP8") (pin "5") (pinfunction "5_5") (pintype "passive"))
    )
    (net (code "515") (name "REL_RAW_22") (class "Default")
      (node (ref "R194") (pin "1") (pinfunction "1_1") (pintype "passive"))
      (node (ref "R210") (pin "1") (pinfunction "1_1") (pintype "passive"))
      (node (ref "VD105") (pin "C") (pinfunction "C_C") (pintype "passive"))
      (node (ref "XP8") (pin "6") (pinfunction "6_6") (pintype "passive"))
    )
    (net (code "516") (name "REL_RAW_23") (class "Default")
      (node (ref "R195") (pin "1") (pinfunction "1_1") (pintype "passive"))
      (node (ref "R211") (pin "1") (pinfunction "1_1") (pintype "passive"))
      (node (ref "VD106") (pin "C") (pinfunction "C_C") (pintype "passive"))
      (node (ref "XP8") (pin "7") (pinfunction "7_7") (pintype "passive"))
    )
    (net (code "517") (name "REL_RAW_24") (class "Default")
      (node (ref "R196") (pin "1") (pinfunction "1_1") (pintype "passive"))
      (node (ref "R212") (pin "1") (pinfunction "1_1") (pintype "passive"))
      (node (ref "VD107") (pin "C") (pinfunction "C_C") (pintype "passive"))
      (node (ref "XP8") (pin "8") (pinfunction "8_8") (pintype "passive"))
    )
    (net (code "518") (name "REL_RAW_25") (class "Default")
      (node (ref "R197") (pin "1") (pinfunction "1_1") (pintype "passive"))
      (node (ref "R213") (pin "1") (pinfunction "1_1") (pintype "passive"))
      (node (ref "VD108") (pin "C") (pinfunction "C_C") (pintype "passive"))
      (node (ref "XP8") (pin "9") (pinfunction "9_9") (pintype "passive"))
    )
    (net (code "519") (name "REL_RAW_26") (class "Default")
      (node (ref "R198") (pin "1") (pinfunction "1_1") (pintype "passive"))
      (node (ref "R214") (pin "1") (pinfunction "1_1") (pintype "passive"))
      (node (ref "VD109") (pin "C") (pinfunction "C_C") (pintype "passive"))
      (node (ref "XP8") (pin "10") (pinfunction "10_10") (pintype "passive"))
    )
    (net (code "520") (name "REL_RAW_27") (class "Default")
      (node (ref "R199") (pin "1") (pinfunction "1_1") (pintype "passive"))
      (node (ref "R215") (pin "1") (pinfunction "1_1") (pintype "passive"))
      (node (ref "VD110") (pin "C") (pinfunction "C_C") (pintype "passive"))
      (node (ref "XP8") (pin "11") (pinfunction "11_11") (pintype "passive"))
    )
    (net (code "521") (name "REL_RAW_28") (class "Default")
      (node (ref "R200") (pin "1") (pinfunction "1_1") (pintype "passive"))
      (node (ref "R216") (pin "1") (pinfunction "1_1") (pintype "passive"))
      (node (ref "VD111") (pin "C") (pinfunction "C_C") (pintype "passive"))
      (node (ref "XP8") (pin "12") (pinfunction "12_12") (pintype "passive"))
    )
    (net (code "522") (name "REL_RAW_29") (class "Default")
      (node (ref "R201") (pin "1") (pinfunction "1_1") (pintype "passive"))
      (node (ref "R217") (pin "1") (pinfunction "1_1") (pintype "passive"))
      (node (ref "VD112") (pin "C") (pinfunction "C_C") (pintype "passive"))
      (node (ref "XP8") (pin "13") (pinfunction "13_13") (pintype "passive"))
    )
    (net (code "523") (name "REL_RAW_30") (class "Default")
      (node (ref "R202") (pin "1") (pinfunction "1_1") (pintype "passive"))
      (node (ref "R218") (pin "1") (pinfunction "1_1") (pintype "passive"))
      (node (ref "VD113") (pin "C") (pinfunction "C_C") (pintype "passive"))
      (node (ref "XP8") (pin "14") (pinfunction "14_14") (pintype "passive"))
    )
    (net (code "524") (name "REL_RAW_31") (class "Default")
      (node (ref "R203") (pin "1") (pinfunction "1_1") (pintype "passive"))
      (node (ref "R219") (pin "1") (pinfunction "1_1") (pintype "passive"))
      (node (ref "VD114") (pin "C") (pinfunction "C_C") (pintype "passive"))
      (node (ref "XP8") (pin "15") (pinfunction "15_15") (pintype "passive"))
    )
    (net (code "525") (name "REL_RAW_32") (class "Default")
      (node (ref "R204") (pin "1") (pinfunction "1_1") (pintype "passive"))
      (node (ref "R220") (pin "1") (pinfunction "1_1") (pintype "passive"))
      (node (ref "VD115") (pin "C") (pinfunction "C_C") (pintype "passive"))
      (node (ref "XP8") (pin "16") (pinfunction "16_16") (pintype "passive"))
    )
    (net (code "526") (name "REL_RAW_33") (class "Default")
      (node (ref "R237") (pin "1") (pinfunction "1_1") (pintype "passive"))
      (node (ref "R253") (pin "1") (pinfunction "1_1") (pintype "passive"))
      (node (ref "VD132") (pin "C") (pinfunction "C_C") (pintype "passive"))
      (node (ref "XP9") (pin "1") (pinfunction "1_1") (pintype "passive"))
    )
    (net (code "527") (name "REL_RAW_34") (class "Default")
      (node (ref "R238") (pin "1") (pinfunction "1_1") (pintype "passive"))
      (node (ref "R254") (pin "1") (pinfunction "1_1") (pintype "passive"))
      (node (ref "VD133") (pin "C") (pinfunction "C_C") (pintype "passive"))
      (node (ref "XP9") (pin "2") (pinfunction "2_2") (pintype "passive"))
    )
    (net (code "528") (name "REL_RAW_35") (class "Default")
      (node (ref "R239") (pin "1") (pinfunction "1_1") (pintype "passive"))
      (node (ref "R255") (pin "1") (pinfunction "1_1") (pintype "passive"))
      (node (ref "VD134") (pin "C") (pinfunction "C_C") (pintype "passive"))
      (node (ref "XP9") (pin "3") (pinfunction "3_3") (pintype "passive"))
    )
    (net (code "529") (name "REL_RAW_36") (class "Default")
      (node (ref "R240") (pin "1") (pinfunction "1_1") (pintype "passive"))
      (node (ref "R256") (pin "1") (pinfunction "1_1") (pintype "passive"))
      (node (ref "VD135") (pin "C") (pinfunction "C_C") (pintype "passive"))
      (node (ref "XP9") (pin "4") (pinfunction "4_4") (pintype "passive"))
    )
    (net (code "530") (name "REL_RAW_37") (class "Default")
      (node (ref "R241") (pin "1") (pinfunction "1_1") (pintype "passive"))
      (node (ref "R257") (pin "1") (pinfunction "1_1") (pintype "passive"))
      (node (ref "VD136") (pin "C") (pinfunction "C_C") (pintype "passive"))
      (node (ref "XP9") (pin "5") (pinfunction "5_5") (pintype "passive"))
    )
    (net (code "531") (name "REL_RAW_38") (class "Default")
      (node (ref "R242") (pin "1") (pinfunction "1_1") (pintype "passive"))
      (node (ref "R258") (pin "1") (pinfunction "1_1") (pintype "passive"))
      (node (ref "VD137") (pin "C") (pinfunction "C_C") (pintype "passive"))
      (node (ref "XP9") (pin "6") (pinfunction "6_6") (pintype "passive"))
    )
    (net (code "532") (name "REL_RAW_39") (class "Default")
      (node (ref "R243") (pin "1") (pinfunction "1_1") (pintype "passive"))
      (node (ref "R259") (pin "1") (pinfunction "1_1") (pintype "passive"))
      (node (ref "VD138") (pin "C") (pinfunction "C_C") (pintype "passive"))
      (node (ref "XP9") (pin "7") (pinfunction "7_7") (pintype "passive"))
    )
    (net (code "533") (name "REL_RAW_40") (class "Default")
      (node (ref "R244") (pin "1") (pinfunction "1_1") (pintype "passive"))
      (node (ref "R260") (pin "1") (pinfunction "1_1") (pintype "passive"))
      (node (ref "VD139") (pin "C") (pinfunction "C_C") (pintype "passive"))
      (node (ref "XP9") (pin "8") (pinfunction "8_8") (pintype "passive"))
    )
    (net (code "534") (name "REL_RAW_41") (class "Default")
      (node (ref "R245") (pin "1") (pinfunction "1_1") (pintype "passive"))
      (node (ref "R261") (pin "1") (pinfunction "1_1") (pintype "passive"))
      (node (ref "VD140") (pin "C") (pinfunction "C_C") (pintype "passive"))
      (node (ref "XP9") (pin "9") (pinfunction "9_9") (pintype "passive"))
    )
    (net (code "535") (name "REL_RAW_42") (class "Default")
      (node (ref "R246") (pin "1") (pinfunction "1_1") (pintype "passive"))
      (node (ref "R262") (pin "1") (pinfunction "1_1") (pintype "passive"))
      (node (ref "VD141") (pin "C") (pinfunction "C_C") (pintype "passive"))
      (node (ref "XP9") (pin "10") (pinfunction "10_10") (pintype "passive"))
    )
    (net (code "536") (name "REL_RAW_43") (class "Default")
      (node (ref "R247") (pin "1") (pinfunction "1_1") (pintype "passive"))
      (node (ref "R263") (pin "1") (pinfunction "1_1") (pintype "passive"))
      (node (ref "VD142") (pin "C") (pinfunction "C_C") (pintype "passive"))
      (node (ref "XP9") (pin "11") (pinfunction "11_11") (pintype "passive"))
    )
    (net (code "537") (name "REL_RAW_44") (class "Default")
      (node (ref "R248") (pin "1") (pinfunction "1_1") (pintype "passive"))
      (node (ref "R264") (pin "1") (pinfunction "1_1") (pintype "passive"))
      (node (ref "VD143") (pin "C") (pinfunction "C_C") (pintype "passive"))
      (node (ref "XP9") (pin "12") (pinfunction "12_12") (pintype "passive"))
    )
    (net (code "538") (name "REL_RAW_45") (class "Default")
      (node (ref "R249") (pin "1") (pinfunction "1_1") (pintype "passive"))
      (node (ref "R265") (pin "1") (pinfunction "1_1") (pintype "passive"))
      (node (ref "VD144") (pin "C") (pinfunction "C_C") (pintype "passive"))
      (node (ref "XP9") (pin "13") (pinfunction "13_13") (pintype "passive"))
    )
    (net (code "539") (name "REL_RAW_46") (class "Default")
      (node (ref "R250") (pin "1") (pinfunction "1_1") (pintype "passive"))
      (node (ref "R266") (pin "1") (pinfunction "1_1") (pintype "passive"))
      (node (ref "VD145") (pin "C") (pinfunction "C_C") (pintype "passive"))
      (node (ref "XP9") (pin "14") (pinfunction "14_14") (pintype "passive"))
    )
    (net (code "540") (name "REL_RAW_47") (class "Default")
      (node (ref "R251") (pin "1") (pinfunction "1_1") (pintype "passive"))
      (node (ref "R267") (pin "1") (pinfunction "1_1") (pintype "passive"))
      (node (ref "VD146") (pin "C") (pinfunction "C_C") (pintype "passive"))
      (node (ref "XP9") (pin "15") (pinfunction "15_15") (pintype "passive"))
    )
    (net (code "541") (name "REL_RAW_48") (class "Default")
      (node (ref "R252") (pin "1") (pinfunction "1_1") (pintype "passive"))
      (node (ref "R268") (pin "1") (pinfunction "1_1") (pintype "passive"))
      (node (ref "VD147") (pin "C") (pinfunction "C_C") (pintype "passive"))
      (node (ref "XP9") (pin "16") (pinfunction "16_16") (pintype "passive"))
    )
    (net (code "542") (name "REL_RAW_49") (class "Default")
      (node (ref "R285") (pin "1") (pinfunction "1_1") (pintype "passive"))
      (node (ref "R301") (pin "1") (pinfunction "1_1") (pintype "passive"))
      (node (ref "VD164") (pin "C") (pinfunction "C_C") (pintype "passive"))
      (node (ref "XP10") (pin "1") (pinfunction "1_1") (pintype "passive"))
    )
    (net (code "543") (name "REL_RAW_50") (class "Default")
      (node (ref "R286") (pin "1") (pinfunction "1_1") (pintype "passive"))
      (node (ref "R302") (pin "1") (pinfunction "1_1") (pintype "passive"))
      (node (ref "VD165") (pin "C") (pinfunction "C_C") (pintype "passive"))
      (node (ref "XP10") (pin "2") (pinfunction "2_2") (pintype "passive"))
    )
    (net (code "544") (name "REL_RAW_51") (class "Default")
      (node (ref "R287") (pin "1") (pinfunction "1_1") (pintype "passive"))
      (node (ref "R303") (pin "1") (pinfunction "1_1") (pintype "passive"))
      (node (ref "VD166") (pin "C") (pinfunction "C_C") (pintype "passive"))
      (node (ref "XP10") (pin "3") (pinfunction "3_3") (pintype "passive"))
    )
    (net (code "545") (name "REL_RAW_52") (class "Default")
      (node (ref "R288") (pin "1") (pinfunction "1_1") (pintype "passive"))
      (node (ref "R304") (pin "1") (pinfunction "1_1") (pintype "passive"))
      (node (ref "VD167") (pin "C") (pinfunction "C_C") (pintype "passive"))
      (node (ref "XP10") (pin "4") (pinfunction "4_4") (pintype "passive"))
    )
    (net (code "546") (name "REL_RAW_53") (class "Default")
      (node (ref "R289") (pin "1") (pinfunction "1_1") (pintype "passive"))
      (node (ref "R305") (pin "1") (pinfunction "1_1") (pintype "passive"))
      (node (ref "VD168") (pin "C") (pinfunction "C_C") (pintype "passive"))
      (node (ref "XP10") (pin "5") (pinfunction "5_5") (pintype "passive"))
    )
    (net (code "547") (name "REL_RAW_54") (class "Default")
      (node (ref "R290") (pin "1") (pinfunction "1_1") (pintype "passive"))
      (node (ref "R306") (pin "1") (pinfunction "1_1") (pintype "passive"))
      (node (ref "VD169") (pin "C") (pinfunction "C_C") (pintype "passive"))
      (node (ref "XP10") (pin "6") (pinfunction "6_6") (pintype "passive"))
    )
    (net (code "548") (name "REL_RAW_55") (class "Default")
      (node (ref "R291") (pin "1") (pinfunction "1_1") (pintype "passive"))
      (node (ref "R307") (pin "1") (pinfunction "1_1") (pintype "passive"))
      (node (ref "VD170") (pin "C") (pinfunction "C_C") (pintype "passive"))
      (node (ref "XP10") (pin "7") (pinfunction "7_7") (pintype "passive"))
    )
    (net (code "549") (name "REL_RAW_56") (class "Default")
      (node (ref "R292") (pin "1") (pinfunction "1_1") (pintype "passive"))
      (node (ref "R308") (pin "1") (pinfunction "1_1") (pintype "passive"))
      (node (ref "VD171") (pin "C") (pinfunction "C_C") (pintype "passive"))
      (node (ref "XP10") (pin "8") (pinfunction "8_8") (pintype "passive"))
    )
    (net (code "550") (name "REL_RAW_57") (class "Default")
      (node (ref "R293") (pin "1") (pinfunction "1_1") (pintype "passive"))
      (node (ref "R309") (pin "1") (pinfunction "1_1") (pintype "passive"))
      (node (ref "VD172") (pin "C") (pinfunction "C_C") (pintype "passive"))
      (node (ref "XP10") (pin "9") (pinfunction "9_9") (pintype "passive"))
    )
    (net (code "551") (name "REL_RAW_58") (class "Default")
      (node (ref "R294") (pin "1") (pinfunction "1_1") (pintype "passive"))
      (node (ref "R310") (pin "1") (pinfunction "1_1") (pintype "passive"))
      (node (ref "VD173") (pin "C") (pinfunction "C_C") (pintype "passive"))
      (node (ref "XP10") (pin "10") (pinfunction "10_10") (pintype "passive"))
    )
    (net (code "552") (name "REL_RAW_59") (class "Default")
      (node (ref "R295") (pin "1") (pinfunction "1_1") (pintype "passive"))
      (node (ref "R311") (pin "1") (pinfunction "1_1") (pintype "passive"))
      (node (ref "VD174") (pin "C") (pinfunction "C_C") (pintype "passive"))
      (node (ref "XP10") (pin "11") (pinfunction "11_11") (pintype "passive"))
    )
    (net (code "553") (name "REL_RAW_60") (class "Default")
      (node (ref "R296") (pin "1") (pinfunction "1_1") (pintype "passive"))
      (node (ref "R312") (pin "1") (pinfunction "1_1") (pintype "passive"))
      (node (ref "VD175") (pin "C") (pinfunction "C_C") (pintype "passive"))
      (node (ref "XP10") (pin "12") (pinfunction "12_12") (pintype "passive"))
    )
    (net (code "554") (name "REL_RAW_61") (class "Default")
      (node (ref "R297") (pin "1") (pinfunction "1_1") (pintype "passive"))
      (node (ref "R313") (pin "1") (pinfunction "1_1") (pintype "passive"))
      (node (ref "VD176") (pin "C") (pinfunction "C_C") (pintype "passive"))
      (node (ref "XP10") (pin "13") (pinfunction "13_13") (pintype "passive"))
    )
    (net (code "555") (name "REL_RAW_62") (class "Default")
      (node (ref "R298") (pin "1") (pinfunction "1_1") (pintype "passive"))
      (node (ref "R314") (pin "1") (pinfunction "1_1") (pintype "passive"))
      (node (ref "VD177") (pin "C") (pinfunction "C_C") (pintype "passive"))
      (node (ref "XP10") (pin "14") (pinfunction "14_14") (pintype "passive"))
    )
    (net (code "556") (name "REL_RAW_63") (class "Default")
      (node (ref "R299") (pin "1") (pinfunction "1_1") (pintype "passive"))
      (node (ref "R315") (pin "1") (pinfunction "1_1") (pintype "passive"))
      (node (ref "VD178") (pin "C") (pinfunction "C_C") (pintype "passive"))
      (node (ref "XP10") (pin "15") (pinfunction "15_15") (pintype "passive"))
    )
    (net (code "557") (name "REL_RAW_64") (class "Default")
      (node (ref "R300") (pin "1") (pinfunction "1_1") (pintype "passive"))
      (node (ref "R316") (pin "1") (pinfunction "1_1") (pintype "passive"))
      (node (ref "VD179") (pin "C") (pinfunction "C_C") (pintype "passive"))
      (node (ref "XP10") (pin "16") (pinfunction "16_16") (pintype "passive"))
    )
    (net (code "558") (name "RST") (class "Default")
      (node (ref "DD1") (pin "14") (pinfunction "NRST_14") (pintype "bidirectional"))
      (node (ref "Z8") (pin "1") (pinfunction "1_1") (pintype "passive"))
    )
    (net (code "559") (name "SPEEDOMETER") (class "Default")
      (node (ref "DD1") (pin "40") (pinfunction "PE9(FSMC_D6/TIM1_CH1)*_40") (pintype "bidirectional"))
      (node (ref "Z40") (pin "3") (pinfunction "3_3") (pintype "passive"))
    )
    (net (code "560") (name "SR_IN_NSS") (class "Default")
      (node (ref "DD10") (pin "15") (pinfunction "INH_15") (pintype "input"))
      (node (ref "DD11") (pin "15") (pinfunction "INH_15") (pintype "input"))
      (node (ref "DD4") (pin "15") (pinfunction "INH_15") (pintype "input"))
      (node (ref "DD5") (pin "15") (pinfunction "INH_15") (pintype "input"))
      (node (ref "DD6") (pin "15") (pinfunction "INH_15") (pintype "input"))
      (node (ref "DD7") (pin "15") (pinfunction "INH_15") (pintype "input"))
      (node (ref "DD8") (pin "15") (pinfunction "INH_15") (pintype "input"))
      (node (ref "DD9") (pin "15") (pinfunction "INH_15") (pintype "input"))
      (node (ref "R16") (pin "1") (pinfunction "1_1") (pintype "passive"))
    )
    (net (code "561") (name "SR_MISO") (class "Default")
      (node (ref "DD11") (pin "9") (pinfunction "QH_9") (pintype "output"))
      (node (ref "R18") (pin "1") (pinfunction "1_1") (pintype "passive"))
    )
    (net (code "562") (name "SR_MOSI") (class "Default")
      (node (ref "DD12") (pin "14") (pinfunction "SER_14") (pintype "input"))
      (node (ref "R19") (pin "1") (pinfunction "1_1") (pintype "passive"))
    )
    (net (code "563") (name "SR_OUT_1") (class "Default")
      (node (ref "DD4") (pin "9") (pinfunction "QH_9") (pintype "output"))
      (node (ref "DD5") (pin "10") (pinfunction "SER_10") (pintype "input"))
    )
    (net (code "564") (name "SR_OUT_2") (class "Default")
      (node (ref "DD5") (pin "9") (pinfunction "QH_9") (pintype "output"))
      (node (ref "DD6") (pin "10") (pinfunction "SER_10") (pintype "input"))
    )
    (net (code "565") (name "SR_OUT_3") (class "Default")
      (node (ref "DD6") (pin "9") (pinfunction "QH_9") (pintype "output"))
      (node (ref "DD7") (pin "10") (pinfunction "SER_10") (pintype "input"))
    )
    (net (code "566") (name "SR_OUT_4") (class "Default")
      (node (ref "DD7") (pin "9") (pinfunction "QH_9") (pintype "output"))
      (node (ref "DD8") (pin "10") (pinfunction "SER_10") (pintype "input"))
    )
    (net (code "567") (name "SR_OUT_5") (class "Default")
      (node (ref "DD8") (pin "9") (pinfunction "QH_9") (pintype "output"))
      (node (ref "DD9") (pin "10") (pinfunction "SER_10") (pintype "input"))
    )
    (net (code "568") (name "SR_OUT_6") (class "Default")
      (node (ref "DD10") (pin "10") (pinfunction "SER_10") (pintype "input"))
      (node (ref "DD9") (pin "9") (pinfunction "QH_9") (pintype "output"))
    )
    (net (code "569") (name "SR_OUT_7") (class "Default")
      (node (ref "DD10") (pin "9") (pinfunction "QH_9") (pintype "output"))
      (node (ref "DD11") (pin "10") (pinfunction "SER_10") (pintype "input"))
    )
    (net (code "570") (name "SR_OUT_NSS") (class "Default")
      (node (ref "DD12") (pin "12") (pinfunction "STCP_12") (pintype "input"))
      (node (ref "R22") (pin "1") (pinfunction "1_1") (pintype "passive"))
    )
    (net (code "571") (name "SR_SCK") (class "Default")
      (node (ref "DD10") (pin "2") (pinfunction "CLK_2") (pintype "input"))
      (node (ref "DD11") (pin "2") (pinfunction "CLK_2") (pintype "input"))
      (node (ref "DD12") (pin "11") (pinfunction "SHCP_11") (pintype "input"))
      (node (ref "DD4") (pin "2") (pinfunction "CLK_2") (pintype "input"))
      (node (ref "DD5") (pin "2") (pinfunction "CLK_2") (pintype "input"))
      (node (ref "DD6") (pin "2") (pinfunction "CLK_2") (pintype "input"))
      (node (ref "DD7") (pin "2") (pinfunction "CLK_2") (pintype "input"))
      (node (ref "DD8") (pin "2") (pinfunction "CLK_2") (pintype "input"))
      (node (ref "DD9") (pin "2") (pinfunction "CLK_2") (pintype "input"))
      (node (ref "R17") (pin "1") (pinfunction "1_1") (pintype "passive"))
    )
    (net (code "572") (name "TACHOMETER") (class "Default")
      (node (ref "DD1") (pin "59") (pinfunction "PD12(FSMC_A17/USART3_RTS/TIM4_CH1)*_59") (pintype "bidirectional"))
      (node (ref "Z38") (pin "3") (pinfunction "3_3") (pintype "passive"))
    )
    (net (code "573") (name "TACHO_RAW") (class "Default")
      (node (ref "R124") (pin "2") (pinfunction "2_2") (pintype "passive"))
      (node (ref "XP5") (pin "1") (pinfunction "1_1") (pintype "passive"))
    )
    (net (code "574") (name "USART_FROM_MCU") (class "Default")
      (node (ref "DA17") (pin "10") (pinfunction "T2IN_10") (pintype "input"))
      (node (ref "DD1") (pin "68") (pinfunction "PA9(USART1_TX/TIM1_CH2)*_68") (pintype "bidirectional"))
    )
    (net (code "575") (name "USART_TO_MCU") (class "Default")
      (node (ref "DA17") (pin "9") (pinfunction "R2OUT_9") (pintype "output"))
      (node (ref "DD1") (pin "69") (pinfunction "PA10(USART1_RX/TIM1_CH3)*_69") (pintype "bidirectional"))
    )
    (net (code "576") (name "USBDM") (class "Default")
      (node (ref "DA15") (pin "3") (pinfunction "D2_3") (pintype "bidirectional"))
      (node (ref "DD1") (pin "70") (pinfunction "PA11(USBDM/CAN_RX/USART1_CTS/TIM1_CH4)*_70") (pintype "bidirectional"))
    )
    (net (code "577") (name "USBDP") (class "Default")
      (node (ref "DA15") (pin "1") (pinfunction "D1_1") (pintype "bidirectional"))
      (node (ref "DD1") (pin "71") (pinfunction "PA12(USBDP/CAN_TX/USART1_RTS/TIM1_ETR)*_71") (pintype "bidirectional"))
    )
    (net (code "578") (name "USB_DISCOVERY") (class "Default")
      (node (ref "DD1") (pin "45") (pinfunction "PE14(FSMC_D11/TIM1_CH4)*_45") (pintype "bidirectional"))
      (node (ref "Z49") (pin "3") (pinfunction "3_3") (pintype "passive"))
    )
    (net (code "579") (name "USB_PRESENT") (class "Default")
      (node (ref "DD1") (pin "46") (pinfunction "PE15(FSMC_D12/TIM1_BKIN)*_46") (pintype "bidirectional"))
      (node (ref "Z48") (pin "3") (pinfunction "3_3") (pintype "passive"))
    )
    (net (code "580") (name "VCC_DRV1") (class "Default")
      (node (ref "D20") (pin "TAB") (pinfunction "VCC_TAB") (pintype "power_in"))
      (node (ref "XP11") (pin "2") (pinfunction "2_2") (pintype "passive"))
      (node (ref "XP11") (pin "3") (pinfunction "3_3") (pintype "passive"))
    )
    (net (code "581") (name "VCC_DRV2") (class "Default")
      (node (ref "D21") (pin "TAB") (pinfunction "VCC_TAB") (pintype "power_in"))
      (node (ref "XP11") (pin "6") (pinfunction "6_6") (pintype "passive"))
      (node (ref "XP11") (pin "7") (pinfunction "7_7") (pintype "passive"))
    )
    (net (code "582") (name "VCC_DRV3") (class "Default")
      (node (ref "D22") (pin "TAB") (pinfunction "VCC_TAB") (pintype "power_in"))
      (node (ref "XP11") (pin "10") (pinfunction "10_10") (pintype "passive"))
      (node (ref "XP11") (pin "11") (pinfunction "11_11") (pintype "passive"))
    )
    (net (code "583") (name "VCC_DRV4") (class "Default")
      (node (ref "D23") (pin "TAB") (pinfunction "VCC_TAB") (pintype "power_in"))
      (node (ref "XP11") (pin "14") (pinfunction "14_14") (pintype "passive"))
      (node (ref "XP11") (pin "15") (pinfunction "15_15") (pintype "passive"))
    )
    (net (code "584") (name "VCC_DRV5") (class "Default")
      (node (ref "D24") (pin "TAB") (pinfunction "VCC_TAB") (pintype "power_in"))
      (node (ref "XP11") (pin "18") (pinfunction "18_18") (pintype "passive"))
      (node (ref "XP11") (pin "19") (pinfunction "19_19") (pintype "passive"))
    )
    (net (code "585") (name "VCC_DRV6") (class "Default")
      (node (ref "D25") (pin "TAB") (pinfunction "VCC_TAB") (pintype "power_in"))
      (node (ref "XP11") (pin "22") (pinfunction "22_22") (pintype "passive"))
      (node (ref "XP11") (pin "23") (pinfunction "23_23") (pintype "passive"))
    )
    (net (code "586") (name "VCC_DRV7") (class "Default")
      (node (ref "D26") (pin "TAB") (pinfunction "VCC_TAB") (pintype "power_in"))
      (node (ref "XP11") (pin "26") (pinfunction "26_26") (pintype "passive"))
      (node (ref "XP11") (pin "27") (pinfunction "27_27") (pintype "passive"))
    )
    (net (code "587") (name "VCC_DRV8") (class "Default")
      (node (ref "D27") (pin "TAB") (pinfunction "VCC_TAB") (pintype "power_in"))
      (node (ref "XP11") (pin "30") (pinfunction "30_30") (pintype "passive"))
      (node (ref "XP11") (pin "31") (pinfunction "31_31") (pintype "passive"))
    )
    (net (code "588") (name "Z_CHECK") (class "Default")
      (node (ref "D5") (pin "4") (pinfunction "OUT1_4") (pintype "power_in"))
      (node (ref "D5") (pin "5") (pinfunction "OUT2_5") (pintype "power_in"))
      (node (ref "VD116") (pin "A") (pinfunction "A_A") (pintype "passive"))
      (node (ref "VD117") (pin "A") (pinfunction "A_A") (pintype "passive"))
      (node (ref "VD118") (pin "A") (pinfunction "A_A") (pintype "passive"))
      (node (ref "VD119") (pin "A") (pinfunction "A_A") (pintype "passive"))
      (node (ref "VD120") (pin "A") (pinfunction "A_A") (pintype "passive"))
      (node (ref "VD121") (pin "A") (pinfunction "A_A") (pintype "passive"))
      (node (ref "VD122") (pin "A") (pinfunction "A_A") (pintype "passive"))
      (node (ref "VD123") (pin "A") (pinfunction "A_A") (pintype "passive"))
      (node (ref "VD124") (pin "A") (pinfunction "A_A") (pintype "passive"))
      (node (ref "VD125") (pin "A") (pinfunction "A_A") (pintype "passive"))
      (node (ref "VD126") (pin "A") (pinfunction "A_A") (pintype "passive"))
      (node (ref "VD127") (pin "A") (pinfunction "A_A") (pintype "passive"))
      (node (ref "VD128") (pin "A") (pinfunction "A_A") (pintype "passive"))
      (node (ref "VD129") (pin "A") (pinfunction "A_A") (pintype "passive"))
      (node (ref "VD130") (pin "A") (pinfunction "A_A") (pintype "passive"))
      (node (ref "VD131") (pin "A") (pinfunction "A_A") (pintype "passive"))
      (node (ref "VD148") (pin "A") (pinfunction "A_A") (pintype "passive"))
      (node (ref "VD149") (pin "A") (pinfunction "A_A") (pintype "passive"))
      (node (ref "VD150") (pin "A") (pinfunction "A_A") (pintype "passive"))
      (node (ref "VD151") (pin "A") (pinfunction "A_A") (pintype "passive"))
      (node (ref "VD152") (pin "A") (pinfunction "A_A") (pintype "passive"))
      (node (ref "VD153") (pin "A") (pinfunction "A_A") (pintype "passive"))
      (node (ref "VD154") (pin "A") (pinfunction "A_A") (pintype "passive"))
      (node (ref "VD155") (pin "A") (pinfunction "A_A") (pintype "passive"))
      (node (ref "VD156") (pin "A") (pinfunction "A_A") (pintype "passive"))
      (node (ref "VD157") (pin "A") (pinfunction "A_A") (pintype "passive"))
      (node (ref "VD158") (pin "A") (pinfunction "A_A") (pintype "passive"))
      (node (ref "VD159") (pin "A") (pinfunction "A_A") (pintype "passive"))
      (node (ref "VD160") (pin "A") (pinfunction "A_A") (pintype "passive"))
      (node (ref "VD161") (pin "A") (pinfunction "A_A") (pintype "passive"))
      (node (ref "VD162") (pin "A") (pinfunction "A_A") (pintype "passive"))
      (node (ref "VD163") (pin "A") (pinfunction "A_A") (pintype "passive"))
      (node (ref "VD180") (pin "A") (pinfunction "A_A") (pintype "passive"))
      (node (ref "VD181") (pin "A") (pinfunction "A_A") (pintype "passive"))
      (node (ref "VD182") (pin "A") (pinfunction "A_A") (pintype "passive"))
      (node (ref "VD183") (pin "A") (pinfunction "A_A") (pintype "passive"))
      (node (ref "VD184") (pin "A") (pinfunction "A_A") (pintype "passive"))
      (node (ref "VD185") (pin "A") (pinfunction "A_A") (pintype "passive"))
      (node (ref "VD186") (pin "A") (pinfunction "A_A") (pintype "passive"))
      (node (ref "VD187") (pin "A") (pinfunction "A_A") (pintype "passive"))
      (node (ref "VD188") (pin "A") (pinfunction "A_A") (pintype "passive"))
      (node (ref "VD189") (pin "A") (pinfunction "A_A") (pintype "passive"))
      (node (ref "VD190") (pin "A") (pinfunction "A_A") (pintype "passive"))
      (node (ref "VD191") (pin "A") (pinfunction "A_A") (pintype "passive"))
      (node (ref "VD192") (pin "A") (pinfunction "A_A") (pintype "passive"))
      (node (ref "VD193") (pin "A") (pinfunction "A_A") (pintype "passive"))
      (node (ref "VD194") (pin "A") (pinfunction "A_A") (pintype "passive"))
      (node (ref "VD195") (pin "A") (pinfunction "A_A") (pintype "passive"))
      (node (ref "VD82") (pin "A") (pinfunction "A_A") (pintype "passive"))
      (node (ref "VD83") (pin "A") (pinfunction "A_A") (pintype "passive"))
      (node (ref "VD84") (pin "A") (pinfunction "A_A") (pintype "passive"))
      (node (ref "VD85") (pin "A") (pinfunction "A_A") (pintype "passive"))
      (node (ref "VD86") (pin "A") (pinfunction "A_A") (pintype "passive"))
      (node (ref "VD87") (pin "A") (pinfunction "A_A") (pintype "passive"))
      (node (ref "VD88") (pin "A") (pinfunction "A_A") (pintype "passive"))
      (node (ref "VD89") (pin "A") (pinfunction "A_A") (pintype "passive"))
      (node (ref "VD90") (pin "A") (pinfunction "A_A") (pintype "passive"))
      (node (ref "VD91") (pin "A") (pinfunction "A_A") (pintype "passive"))
      (node (ref "VD92") (pin "A") (pinfunction "A_A") (pintype "passive"))
      (node (ref "VD93") (pin "A") (pinfunction "A_A") (pintype "passive"))
      (node (ref "VD94") (pin "A") (pinfunction "A_A") (pintype "passive"))
      (node (ref "VD95") (pin "A") (pinfunction "A_A") (pintype "passive"))
      (node (ref "VD96") (pin "A") (pinfunction "A_A") (pintype "passive"))
      (node (ref "VD97") (pin "A") (pinfunction "A_A") (pintype "passive"))
    )
    (net (code "589") (name "Z_CHECK_TOGGLE") (class "Default")
      (node (ref "R24") (pin "1") (pinfunction "1_1") (pintype "passive"))
      (node (ref "VT2") (pin "B") (pinfunction "B_B") (pintype "passive"))
    )
    (net (code "590") (name "unconnected-(DA4A-BAL-Pad5)") (class "Default")
      (node (ref "DA4") (pin "5") (pinfunction "BAL_5") (pintype "bidirectional"))
    )
    (net (code "591") (name "unconnected-(DA4A-BALSTR-Pad6)") (class "Default")
      (node (ref "DA4") (pin "6") (pinfunction "BALSTR_6") (pintype "bidirectional"))
    )
    (net (code "592") (name "unconnected-(DA5A-BAL-Pad5)") (class "Default")
      (node (ref "DA5") (pin "5") (pinfunction "BAL_5") (pintype "bidirectional"))
    )
    (net (code "593") (name "unconnected-(DA5A-BALSTR-Pad6)") (class "Default")
      (node (ref "DA5") (pin "6") (pinfunction "BALSTR_6") (pintype "bidirectional"))
    )
    (net (code "594") (name "unconnected-(DA6A-BAL-Pad5)") (class "Default")
      (node (ref "DA6") (pin "5") (pinfunction "BAL_5") (pintype "bidirectional"))
    )
    (net (code "595") (name "unconnected-(DA6A-BALSTR-Pad6)") (class "Default")
      (node (ref "DA6") (pin "6") (pinfunction "BALSTR_6") (pintype "bidirectional"))
    )
    (net (code "596") (name "unconnected-(DA7A-Q-Pad13)") (class "Default")
      (node (ref "DA7") (pin "13") (pinfunction "Q_13") (pintype "output"))
    )
    (net (code "597") (name "unconnected-(DA7B-Q-Pad5)") (class "Default")
      (node (ref "DA7") (pin "5") (pinfunction "Q_5") (pintype "output"))
    )
    (net (code "598") (name "unconnected-(DA8A-Q-Pad13)") (class "Default")
      (node (ref "DA8") (pin "13") (pinfunction "Q_13") (pintype "output"))
    )
    (net (code "599") (name "unconnected-(DA8B-Q-Pad5)") (class "Default")
      (node (ref "DA8") (pin "5") (pinfunction "Q_5") (pintype "output"))
    )
    (net (code "600") (name "unconnected-(DA9A-Q-Pad13)") (class "Default")
      (node (ref "DA9") (pin "13") (pinfunction "Q_13") (pintype "output"))
    )
    (net (code "601") (name "unconnected-(DA9B-Q-Pad5)") (class "Default")
      (node (ref "DA9") (pin "5") (pinfunction "Q_5") (pintype "output"))
    )
    (net (code "602") (name "unconnected-(DA11-FAULT-Pad6)") (class "Default")
      (node (ref "DA11") (pin "6") (pinfunction "FAULT_6") (pintype "open_collector"))
    )
    (net (code "603") (name "unconnected-(DA17-R1IN-Pad13)") (class "Default")
      (node (ref "DA17") (pin "13") (pinfunction "R1IN_13") (pintype "input"))
    )
    (net (code "604") (name "unconnected-(DA17-R1OUT-Pad12)") (class "Default")
      (node (ref "DA17") (pin "12") (pinfunction "R1OUT_12") (pintype "output"))
    )
    (net (code "605") (name "unconnected-(DA17-T1IN-Pad11)") (class "Default")
      (node (ref "DA17") (pin "11") (pinfunction "T1IN_11") (pintype "input"))
    )
    (net (code "606") (name "unconnected-(DA17-T1OUT-Pad14)") (class "Default")
      (node (ref "DA17") (pin "14") (pinfunction "T1OUT_14") (pintype "output"))
    )
    (net (code "607") (name "unconnected-(DD1-NC-Pad73)") (class "Default")
      (node (ref "DD1") (pin "73") (pinfunction "NC_73") (pintype "bidirectional"))
    )
    (net (code "608") (name "unconnected-(DD1-PA8(USART1_CK{slash}TIM1_CH1{slash}MCO)*-Pad67)") (class "Default")
      (node (ref "DD1") (pin "67") (pinfunction "PA8(USART1_CK/TIM1_CH1/MCO)*_67") (pintype "bidirectional"))
    )
    (net (code "609") (name "unconnected-(DD1-PB5(I2C1_SMBA{slash}SPI3_MOSI{slash}I2S3_SD{slash}TIM3_CH2{slash}SPI1_MOSI)-Pad91)") (class "Default")
      (node (ref "DD1") (pin "91") (pinfunction "PB5(I2C1_SMBA/SPI3_MOSI/I2S3_SD/TIM3_CH2/SPI1_MOSI)_91") (pintype "bidirectional"))
    )
    (net (code "610") (name "unconnected-(DD1-PB6(I2C1_SCL{slash}TIM4_CH1{slash}USART1_TX)*-Pad92)") (class "Default")
      (node (ref "DD1") (pin "92") (pinfunction "PB6(I2C1_SCL/TIM4_CH1/USART1_TX)*_92") (pintype "bidirectional"))
    )
    (net (code "611") (name "unconnected-(DD1-PB7(I2C1_SDA{slash}FSMC_NADV{slash}TIM4_CH2{slash}USART1_RX)*-Pad93)") (class "Default")
      (node (ref "DD1") (pin "93") (pinfunction "PB7(I2C1_SDA/FSMC_NADV/TIM4_CH2/USART1_RX)*_93") (pintype "bidirectional"))
    )
    (net (code "612") (name "unconnected-(DD1-PB8(TIM4_CH3{slash}SDIO_D4{slash}I2C1_SCL{slash}CAN_RX)*-Pad95)") (class "Default")
      (node (ref "DD1") (pin "95") (pinfunction "PB8(TIM4_CH3/SDIO_D4/I2C1_SCL/CAN_RX)*_95") (pintype "bidirectional"))
    )
    (net (code "613") (name "unconnected-(DD1-PB9(TIM4_CH4{slash}SDIO_D5{slash}I2C1_SDA{slash}CAN_TX)*-Pad96)") (class "Default")
      (node (ref "DD1") (pin "96") (pinfunction "PB9(TIM4_CH4/SDIO_D5/I2C1_SDA/CAN_TX)*_96") (pintype "bidirectional"))
    )
    (net (code "614") (name "unconnected-(DD1-PC7(I2S3_MCK{slash}TIM8_CH2{slash}SDIO_D7{slash}TIM3_CH2)*-Pad64)") (class "Default")
      (node (ref "DD1") (pin "64") (pinfunction "PC7(I2S3_MCK/TIM8_CH2/SDIO_D7/TIM3_CH2)*_64") (pintype "bidirectional"))
    )
    (net (code "615") (name "unconnected-(DD1-PC8(TIM8_CH3{slash}SDIO_D0{slash}TIM3_CH3)*-Pad65)") (class "Default")
      (node (ref "DD1") (pin "65") (pinfunction "PC8(TIM8_CH3/SDIO_D0/TIM3_CH3)*_65") (pintype "bidirectional"))
    )
    (net (code "616") (name "unconnected-(DD1-PC9(TIM8_CH4{slash}SDIO_D1{slash}TIM3_CH4)*-Pad66)") (class "Default")
      (node (ref "DD1") (pin "66") (pinfunction "PC9(TIM8_CH4/SDIO_D1/TIM3_CH4)*_66") (pintype "bidirectional"))
    )
    (net (code "617") (name "unconnected-(DD1-PC10(UART4_TX{slash}SDIO_D2{slash}USART3_TX)*-Pad78)") (class "Default")
      (node (ref "DD1") (pin "78") (pinfunction "PC10(UART4_TX/SDIO_D2/USART3_TX)*_78") (pintype "bidirectional"))
    )
    (net (code "618") (name "unconnected-(DD1-PC11(UART4_RX{slash}SDIO_D3{slash}USART3_RX)*-Pad79)") (class "Default")
      (node (ref "DD1") (pin "79") (pinfunction "PC11(UART4_RX/SDIO_D3/USART3_RX)*_79") (pintype "bidirectional"))
    )
    (net (code "619") (name "unconnected-(DD1-PC12(UART5_TX{slash}SDIO_CK{slash}USART3_CK)*-Pad80)") (class "Default")
      (node (ref "DD1") (pin "80") (pinfunction "PC12(UART5_TX/SDIO_CK/USART3_CK)*_80") (pintype "bidirectional"))
    )
    (net (code "620") (name "unconnected-(DD1-PC13(TAMPER-RTC)-Pad7)") (class "Default")
      (node (ref "DD1") (pin "7") (pinfunction "PC13(TAMPER-RTC)_7") (pintype "bidirectional"))
    )
    (net (code "621") (name "unconnected-(DD1-PC14(OSC32_IN)-Pad8)") (class "Default")
      (node (ref "DD1") (pin "8") (pinfunction "PC14(OSC32_IN)_8") (pintype "bidirectional"))
    )
    (net (code "622") (name "unconnected-(DD1-PC15(OSC32_OUT)-Pad9)") (class "Default")
      (node (ref "DD1") (pin "9") (pinfunction "PC15(OSC32_OUT)_9") (pintype "bidirectional"))
    )
    (net (code "623") (name "unconnected-(DD1-PD2(TIM3_ETR{slash}UART5_RX{slash}SDIO_CMD)*-Pad83)") (class "Default")
      (node (ref "DD1") (pin "83") (pinfunction "PD2(TIM3_ETR/UART5_RX/SDIO_CMD)*_83") (pintype "bidirectional"))
    )
    (net (code "624") (name "unconnected-(DD1-PD3(FSMC_CLK{slash}USART2_CTS)*-Pad84)") (class "Default")
      (node (ref "DD1") (pin "84") (pinfunction "PD3(FSMC_CLK/USART2_CTS)*_84") (pintype "bidirectional"))
    )
    (net (code "625") (name "unconnected-(DD1-PD4(FSMC_NOE{slash}USART2_RTS)*-Pad85)") (class "Default")
      (node (ref "DD1") (pin "85") (pinfunction "PD4(FSMC_NOE/USART2_RTS)*_85") (pintype "bidirectional"))
    )
    (net (code "626") (name "unconnected-(DD1-PD5(FSMC_NWE{slash}USART2_TX)*-Pad86)") (class "Default")
      (node (ref "DD1") (pin "86") (pinfunction "PD5(FSMC_NWE/USART2_TX)*_86") (pintype "bidirectional"))
    )
    (net (code "627") (name "unconnected-(DD1-PD6(FSMC_NWAIT{slash}USART2_RX)*-Pad87)") (class "Default")
      (node (ref "DD1") (pin "87") (pinfunction "PD6(FSMC_NWAIT/USART2_RX)*_87") (pintype "bidirectional"))
    )
    (net (code "628") (name "unconnected-(DD1-PD7(FSMC_NE1{slash}FSMC_NCE2{slash}USART2_CK)*-Pad88)") (class "Default")
      (node (ref "DD1") (pin "88") (pinfunction "PD7(FSMC_NE1/FSMC_NCE2/USART2_CK)*_88") (pintype "bidirectional"))
    )
    (net (code "629") (name "unconnected-(DD1-PD8(FSMC_D13{slash}USART3_TX)*-Pad55)") (class "Default")
      (node (ref "DD1") (pin "55") (pinfunction "PD8(FSMC_D13/USART3_TX)*_55") (pintype "bidirectional"))
    )
    (net (code "630") (name "unconnected-(DD1-PD9(FSMC_D14{slash}USART3_RX)*-Pad56)") (class "Default")
      (node (ref "DD1") (pin "56") (pinfunction "PD9(FSMC_D14/USART3_RX)*_56") (pintype "bidirectional"))
    )
    (net (code "631") (name "unconnected-(DD1-PD10(FSMC_D15{slash}USART3_CK)*-Pad57)") (class "Default")
      (node (ref "DD1") (pin "57") (pinfunction "PD10(FSMC_D15/USART3_CK)*_57") (pintype "bidirectional"))
    )
    (net (code "632") (name "unconnected-(DD1-PD11(FSMC_A16{slash}USART3_CTS)*-Pad58)") (class "Default")
      (node (ref "DD1") (pin "58") (pinfunction "PD11(FSMC_A16/USART3_CTS)*_58") (pintype "bidirectional"))
    )
    (net (code "633") (name "unconnected-(DD1-PD13(FSMC_A18{slash}TIM4_CH2)*-Pad60)") (class "Default")
      (node (ref "DD1") (pin "60") (pinfunction "PD13(FSMC_A18/TIM4_CH2)*_60") (pintype "bidirectional"))
    )
    (net (code "634") (name "unconnected-(DD1-PD14(FSMC_D0{slash}TIM4_CH3)*-Pad61)") (class "Default")
      (node (ref "DD1") (pin "61") (pinfunction "PD14(FSMC_D0/TIM4_CH3)*_61") (pintype "bidirectional"))
    )
    (net (code "635") (name "unconnected-(DD1-PD15(FSMC_D1{slash}TIM4_CH4)*-Pad62)") (class "Default")
      (node (ref "DD1") (pin "62") (pinfunction "PD15(FSMC_D1/TIM4_CH4)*_62") (pintype "bidirectional"))
    )
    (net (code "636") (name "unconnected-(DD1-PE1(FSMC_NBL1)*-Pad98)") (class "Default")
      (node (ref "DD1") (pin "98") (pinfunction "PE1(FSMC_NBL1)*_98") (pintype "bidirectional"))
    )
    (net (code "637") (name "unconnected-(DD1-PE6(TRACED3{slash}FSMC_A22)*-Pad5)") (class "Default")
      (node (ref "DD1") (pin "5") (pinfunction "PE6(TRACED3/FSMC_A22)*_5") (pintype "bidirectional"))
    )
    (net (code "638") (name "unconnected-(DD1-PE7(FSMC_D4{slash}TIM1_ETR)*-Pad38)") (class "Default")
      (node (ref "DD1") (pin "38") (pinfunction "PE7(FSMC_D4/TIM1_ETR)*_38") (pintype "bidirectional"))
    )
    (net (code "639") (name "unconnected-(DD1-PE8(FSMC_D5{slash}TIM1_CH1N)*-Pad39)") (class "Default")
      (node (ref "DD1") (pin "39") (pinfunction "PE8(FSMC_D5/TIM1_CH1N)*_39") (pintype "bidirectional"))
    )
    (net (code "640") (name "unconnected-(DD1-PE10(FSMC_D7{slash}TIM1_CH2N)*-Pad41)") (class "Default")
      (node (ref "DD1") (pin "41") (pinfunction "PE10(FSMC_D7/TIM1_CH2N)*_41") (pintype "bidirectional"))
    )
    (net (code "641") (name "unconnected-(DD1-PE11(FSMC_D8{slash}TIM1_CH2)*-Pad42)") (class "Default")
      (node (ref "DD1") (pin "42") (pinfunction "PE11(FSMC_D8/TIM1_CH2)*_42") (pintype "bidirectional"))
    )
    (net (code "642") (name "unconnected-(DD1-PE12(FSMC_D9{slash}TIM1_CH3N)*-Pad43)") (class "Default")
      (node (ref "DD1") (pin "43") (pinfunction "PE12(FSMC_D9/TIM1_CH3N)*_43") (pintype "bidirectional"))
    )
    (net (code "643") (name "unconnected-(DD1-PE13(FSMC_D10{slash}TIM1_CH3)*-Pad44)") (class "Default")
      (node (ref "DD1") (pin "44") (pinfunction "PE13(FSMC_D10/TIM1_CH3)*_44") (pintype "bidirectional"))
    )
    (net (code "644") (name "unconnected-(DD4A-~{QH}-Pad7)") (class "Default")
      (node (ref "DD4") (pin "7") (pinfunction "~{QH}_7") (pintype "output"))
    )
    (net (code "645") (name "unconnected-(DD5A-~{QH}-Pad7)") (class "Default")
      (node (ref "DD5") (pin "7") (pinfunction "~{QH}_7") (pintype "output"))
    )
    (net (code "646") (name "unconnected-(DD6A-~{QH}-Pad7)") (class "Default")
      (node (ref "DD6") (pin "7") (pinfunction "~{QH}_7") (pintype "output"))
    )
    (net (code "647") (name "unconnected-(DD7A-~{QH}-Pad7)") (class "Default")
      (node (ref "DD7") (pin "7") (pinfunction "~{QH}_7") (pintype "output"))
    )
    (net (code "648") (name "unconnected-(DD8A-~{QH}-Pad7)") (class "Default")
      (node (ref "DD8") (pin "7") (pinfunction "~{QH}_7") (pintype "output"))
    )
    (net (code "649") (name "unconnected-(DD9A-~{QH}-Pad7)") (class "Default")
      (node (ref "DD9") (pin "7") (pinfunction "~{QH}_7") (pintype "output"))
    )
    (net (code "650") (name "unconnected-(DD10A-~{QH}-Pad7)") (class "Default")
      (node (ref "DD10") (pin "7") (pinfunction "~{QH}_7") (pintype "output"))
    )
    (net (code "651") (name "unconnected-(DD11A-~{QH}-Pad7)") (class "Default")
      (node (ref "DD11") (pin "7") (pinfunction "~{QH}_7") (pintype "output"))
    )
    (net (code "652") (name "unconnected-(DD12A-Q7S-Pad9)") (class "Default")
      (node (ref "DD12") (pin "9") (pinfunction "Q7S_9") (pintype "tri_state"))
    )
    (net (code "653") (name "unconnected-(XP5-Pad5)") (class "Default")
      (node (ref "XP5") (pin "5") (pinfunction "5_5") (pintype "passive"))
    )
    (net (code "654") (name "unconnected-(XP5-Pad7)") (class "Default")
      (node (ref "XP5") (pin "7") (pinfunction "7_7") (pintype "passive"))
    )
    (net (code "655") (name "unconnected-(XP5-Pad8)") (class "Default")
      (node (ref "XP5") (pin "8") (pinfunction "8_8") (pintype "passive"))
    )
    (net (code "656") (name "unconnected-(XP11-Pad33)") (class "Default")
      (node (ref "XP11") (pin "33") (pinfunction "33_33") (pintype "passive"))
    )
    (net (code "657") (name "unconnected-(XP11-Pad34)") (class "Default")
      (node (ref "XP11") (pin "34") (pinfunction "34_34") (pintype "passive"))
    )
    (net (code "658") (name "unconnected-(XP12-Pad5)") (class "Default")
      (node (ref "XP12") (pin "5") (pinfunction "5_5") (pintype "passive"))
    )
    (net (code "659") (name "unconnected-(XP12-Pad6)") (class "Default")
      (node (ref "XP12") (pin "6") (pinfunction "6_6") (pintype "passive"))
    )
    (net (code "660") (name "unconnected-(XP12-Pad7)") (class "Default")
      (node (ref "XP12") (pin "7") (pinfunction "7_7") (pintype "passive"))
    )
    (net (code "661") (name "unconnected-(XP12-Pad8)") (class "Default")
      (node (ref "XP12") (pin "8") (pinfunction "8_8") (pintype "passive"))
    )
    (net (code "662") (name "unconnected-(XS1-4-PadID)") (class "Default")
      (node (ref "XS1") (pin "ID") (pinfunction "4_ID") (pintype "passive"))
    )
    (net (code "663") (name "unconnected-(XS1-6-PadSHIELD1)") (class "Default")
      (node (ref "XS1") (pin "SHIELD1") (pinfunction "6_SHIELD1") (pintype "passive"))
    )
    (net (code "664") (name "unconnected-(XS1-7-PadSHIELD2)") (class "Default")
      (node (ref "XS1") (pin "SHIELD2") (pinfunction "7_SHIELD2") (pintype "passive"))
    )
    (net (code "665") (name "unconnected-(XS1-8-PadSHIELD3)") (class "Default")
      (node (ref "XS1") (pin "SHIELD3") (pinfunction "8_SHIELD3") (pintype "passive"))
    )
    (net (code "666") (name "unconnected-(XS1-9-PadSHIELD4)") (class "Default")
      (node (ref "XS1") (pin "SHIELD4") (pinfunction "9_SHIELD4") (pintype "passive"))
    )
    (net (code "667") (name "~{SR_OUT_ENABLE}") (class "Default")
      (node (ref "DD12") (pin "13") (pinfunction "~{OE}_13") (pintype "input"))
      (node (ref "R21") (pin "1") (pinfunction "1_1") (pintype "passive"))
      (node (ref "R333") (pin "1") (pinfunction "1_1") (pintype "passive"))
    )
    (net (code "668") (name "~{SR_SAMPLE}") (class "Default")
      (node (ref "DD10") (pin "1") (pinfunction "SH/~{LD}_1") (pintype "input"))
      (node (ref "DD11") (pin "1") (pinfunction "SH/~{LD}_1") (pintype "input"))
      (node (ref "DD4") (pin "1") (pinfunction "SH/~{LD}_1") (pintype "input"))
      (node (ref "DD5") (pin "1") (pinfunction "SH/~{LD}_1") (pintype "input"))
      (node (ref "DD6") (pin "1") (pinfunction "SH/~{LD}_1") (pintype "input"))
      (node (ref "DD7") (pin "1") (pinfunction "SH/~{LD}_1") (pintype "input"))
      (node (ref "DD8") (pin "1") (pinfunction "SH/~{LD}_1") (pintype "input"))
      (node (ref "DD9") (pin "1") (pinfunction "SH/~{LD}_1") (pintype "input"))
      (node (ref "R23") (pin "1") (pinfunction "1_1") (pintype "passive"))
    )
  )
)
